# IPG-V1_rev0_24.net
KiCad netlist of a schematic drawn in Altium Designer
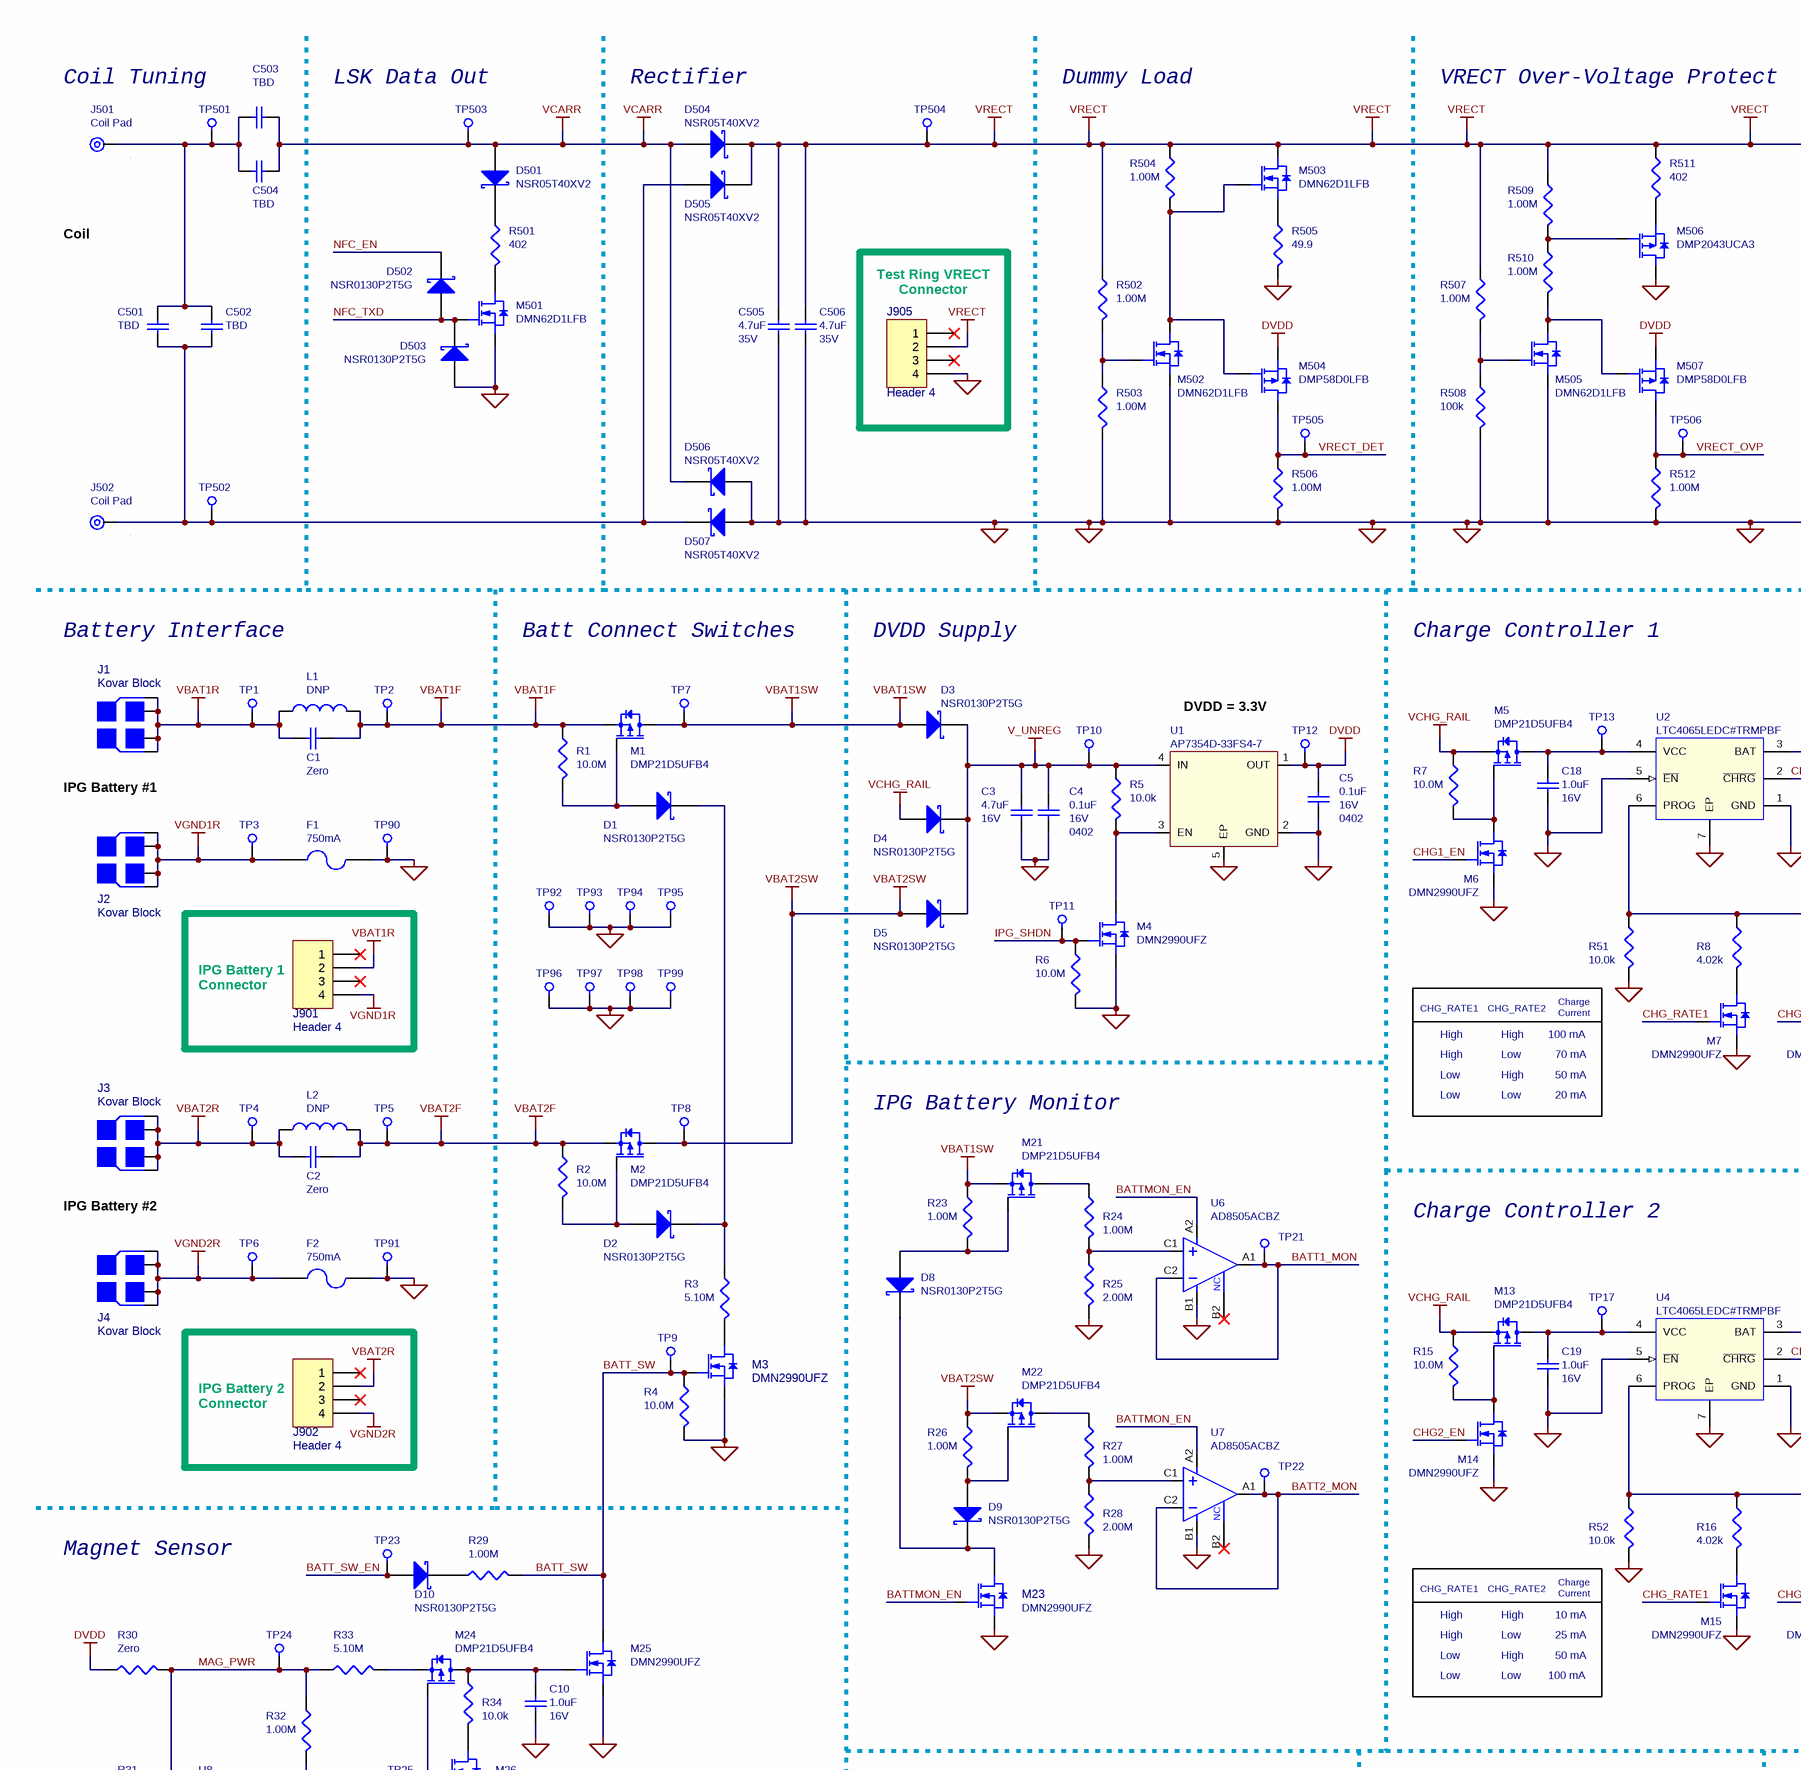
[diagram p0: IPG-V1_rev0.24.SchDoc, top left]
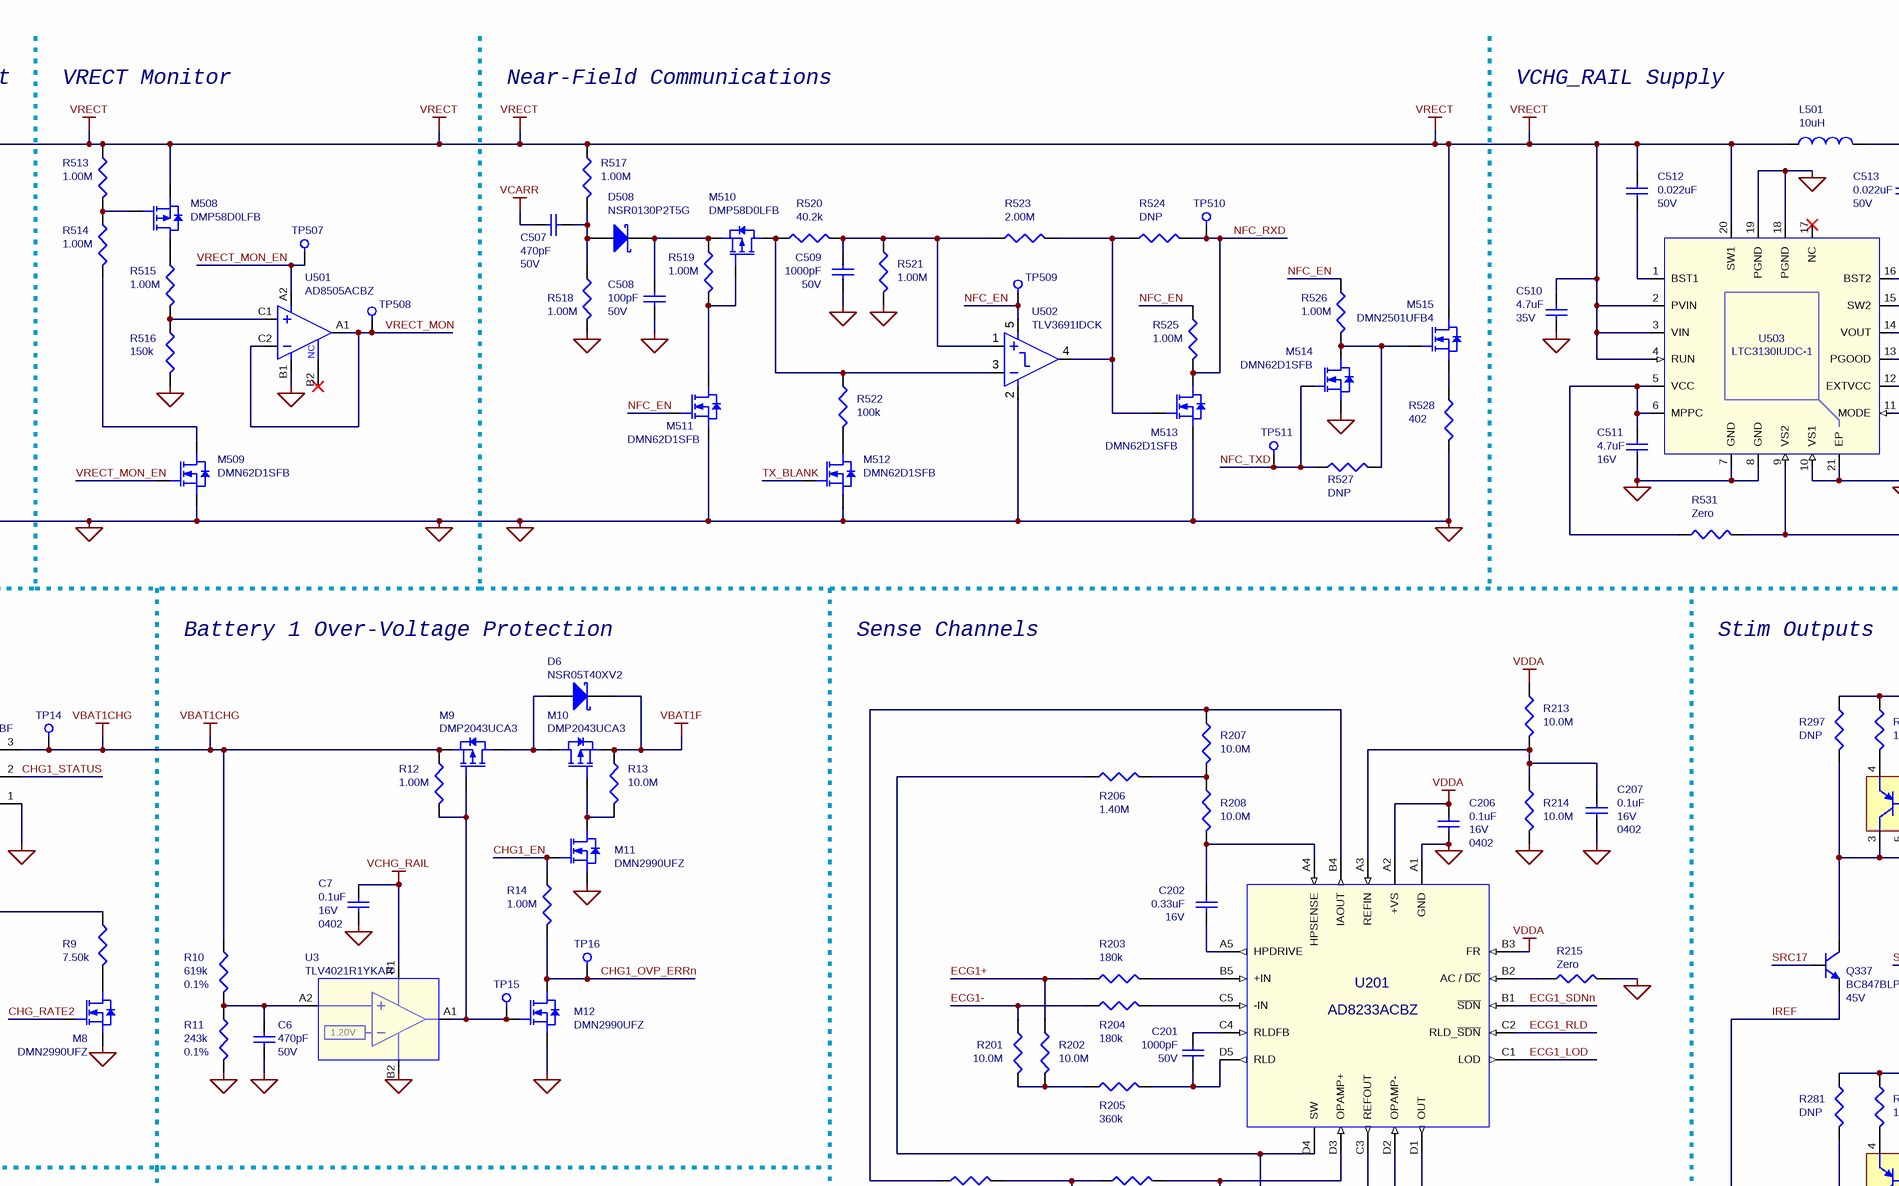
[diagram p1: IPG-V1_rev0.24.SchDoc, top middle]
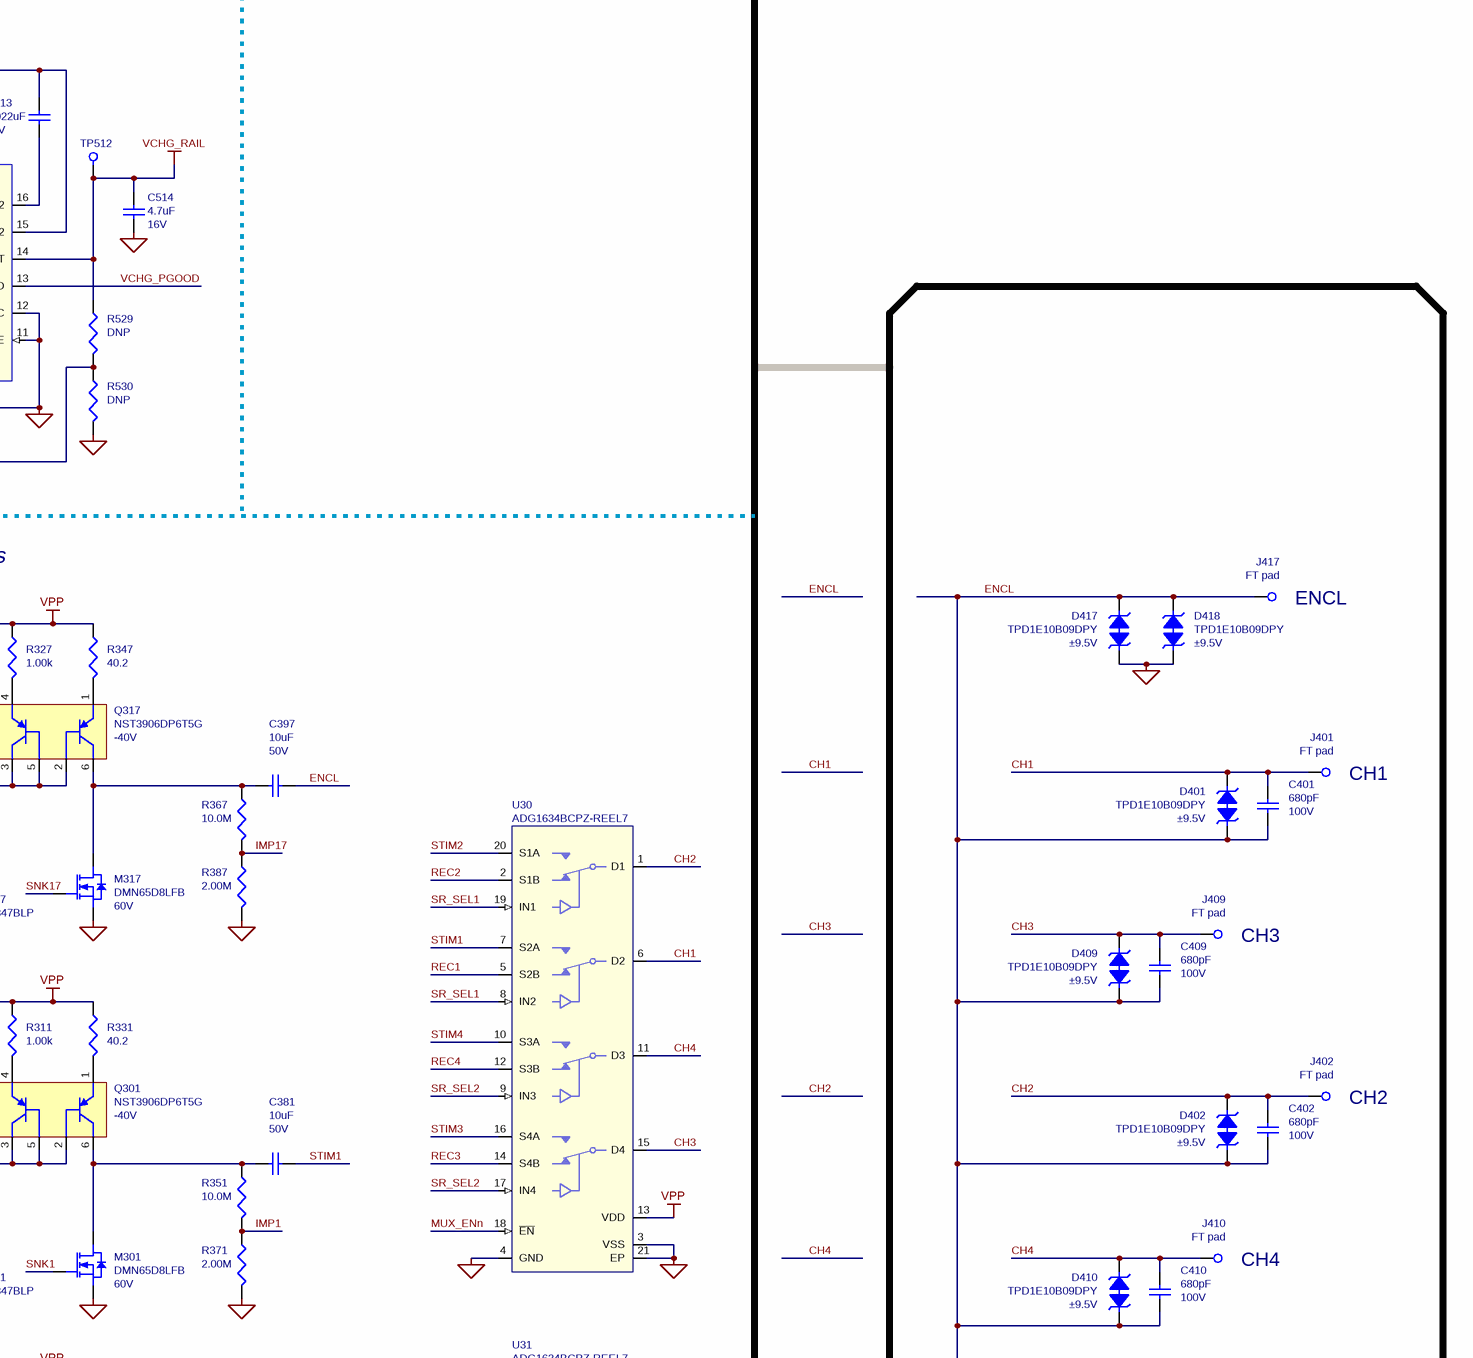
[diagram p2: IPG-V1_rev0.24.SchDoc, top right]
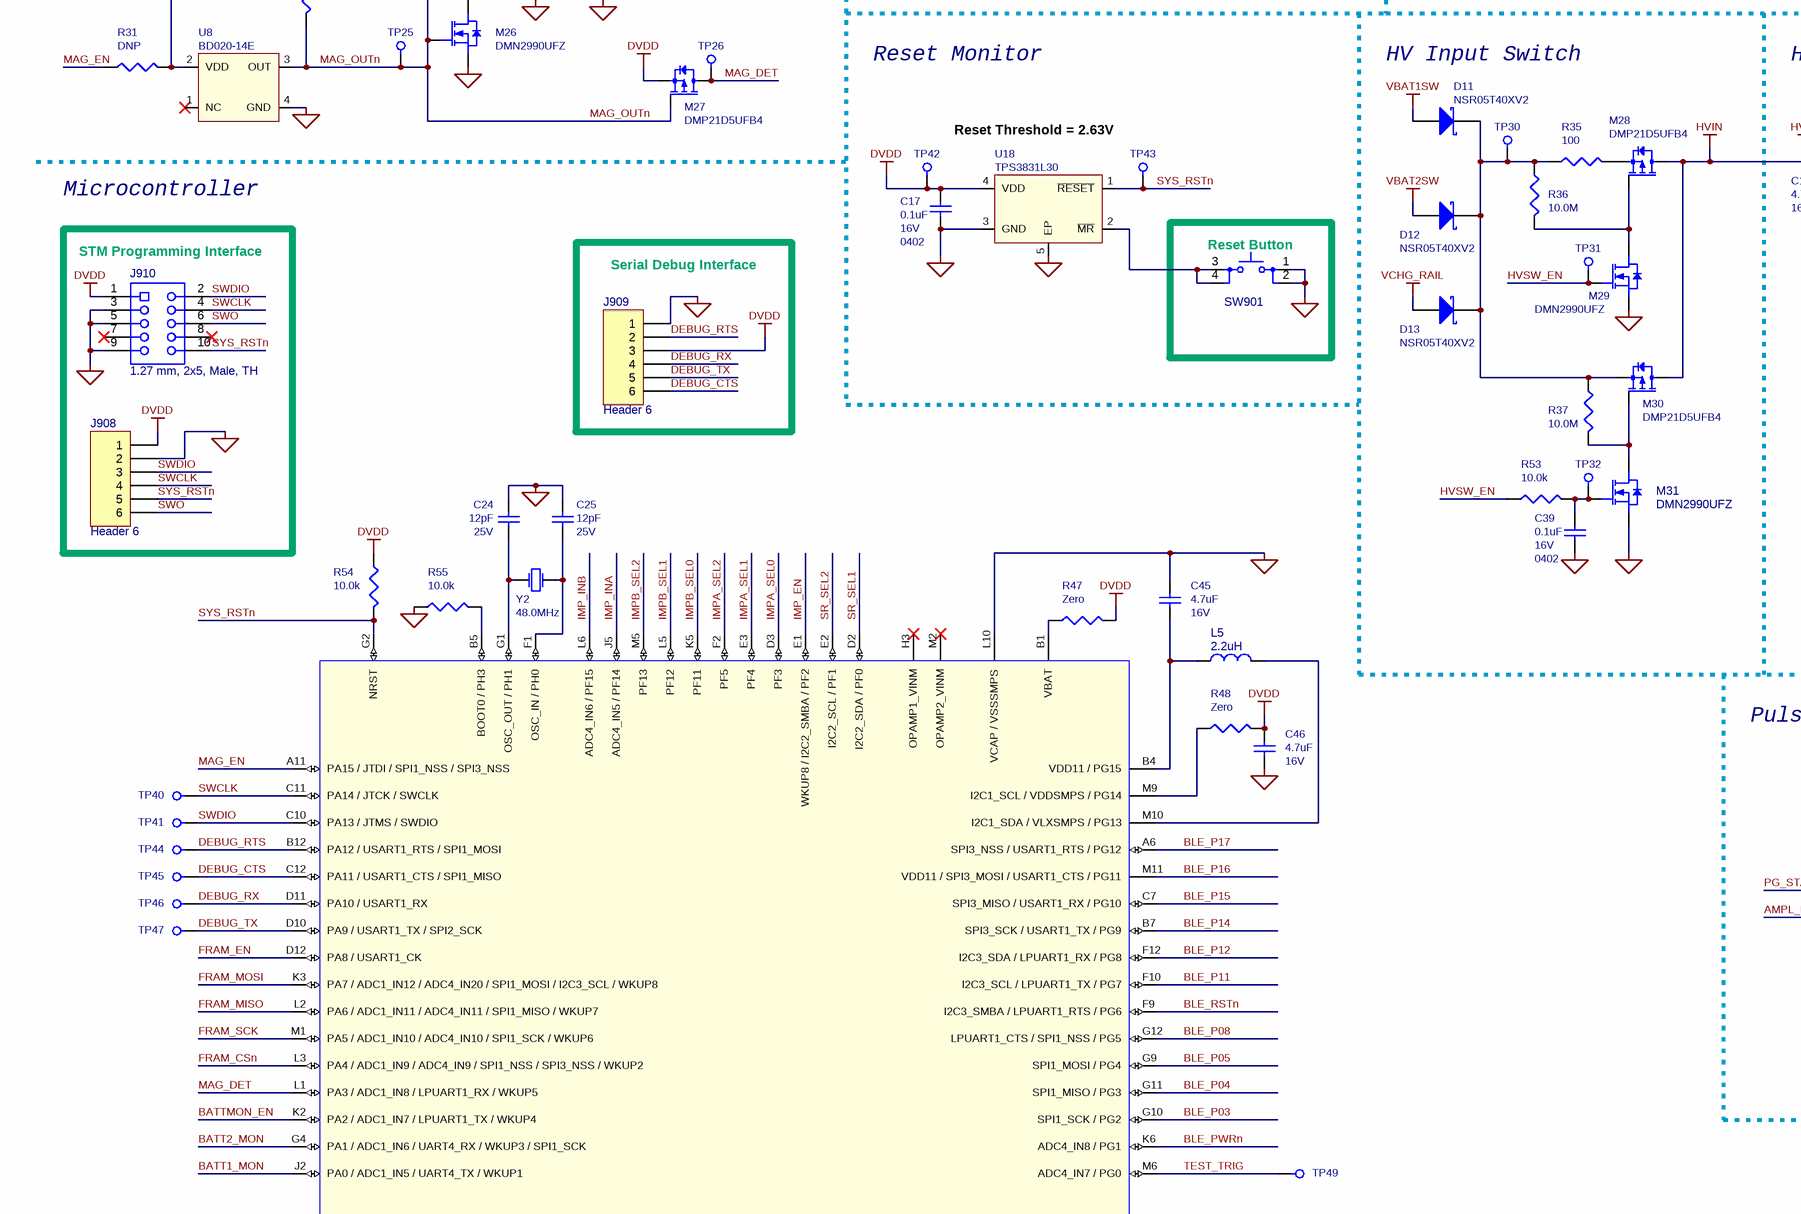
[diagram p3: IPG-V1_rev0.24.SchDoc, centre left]
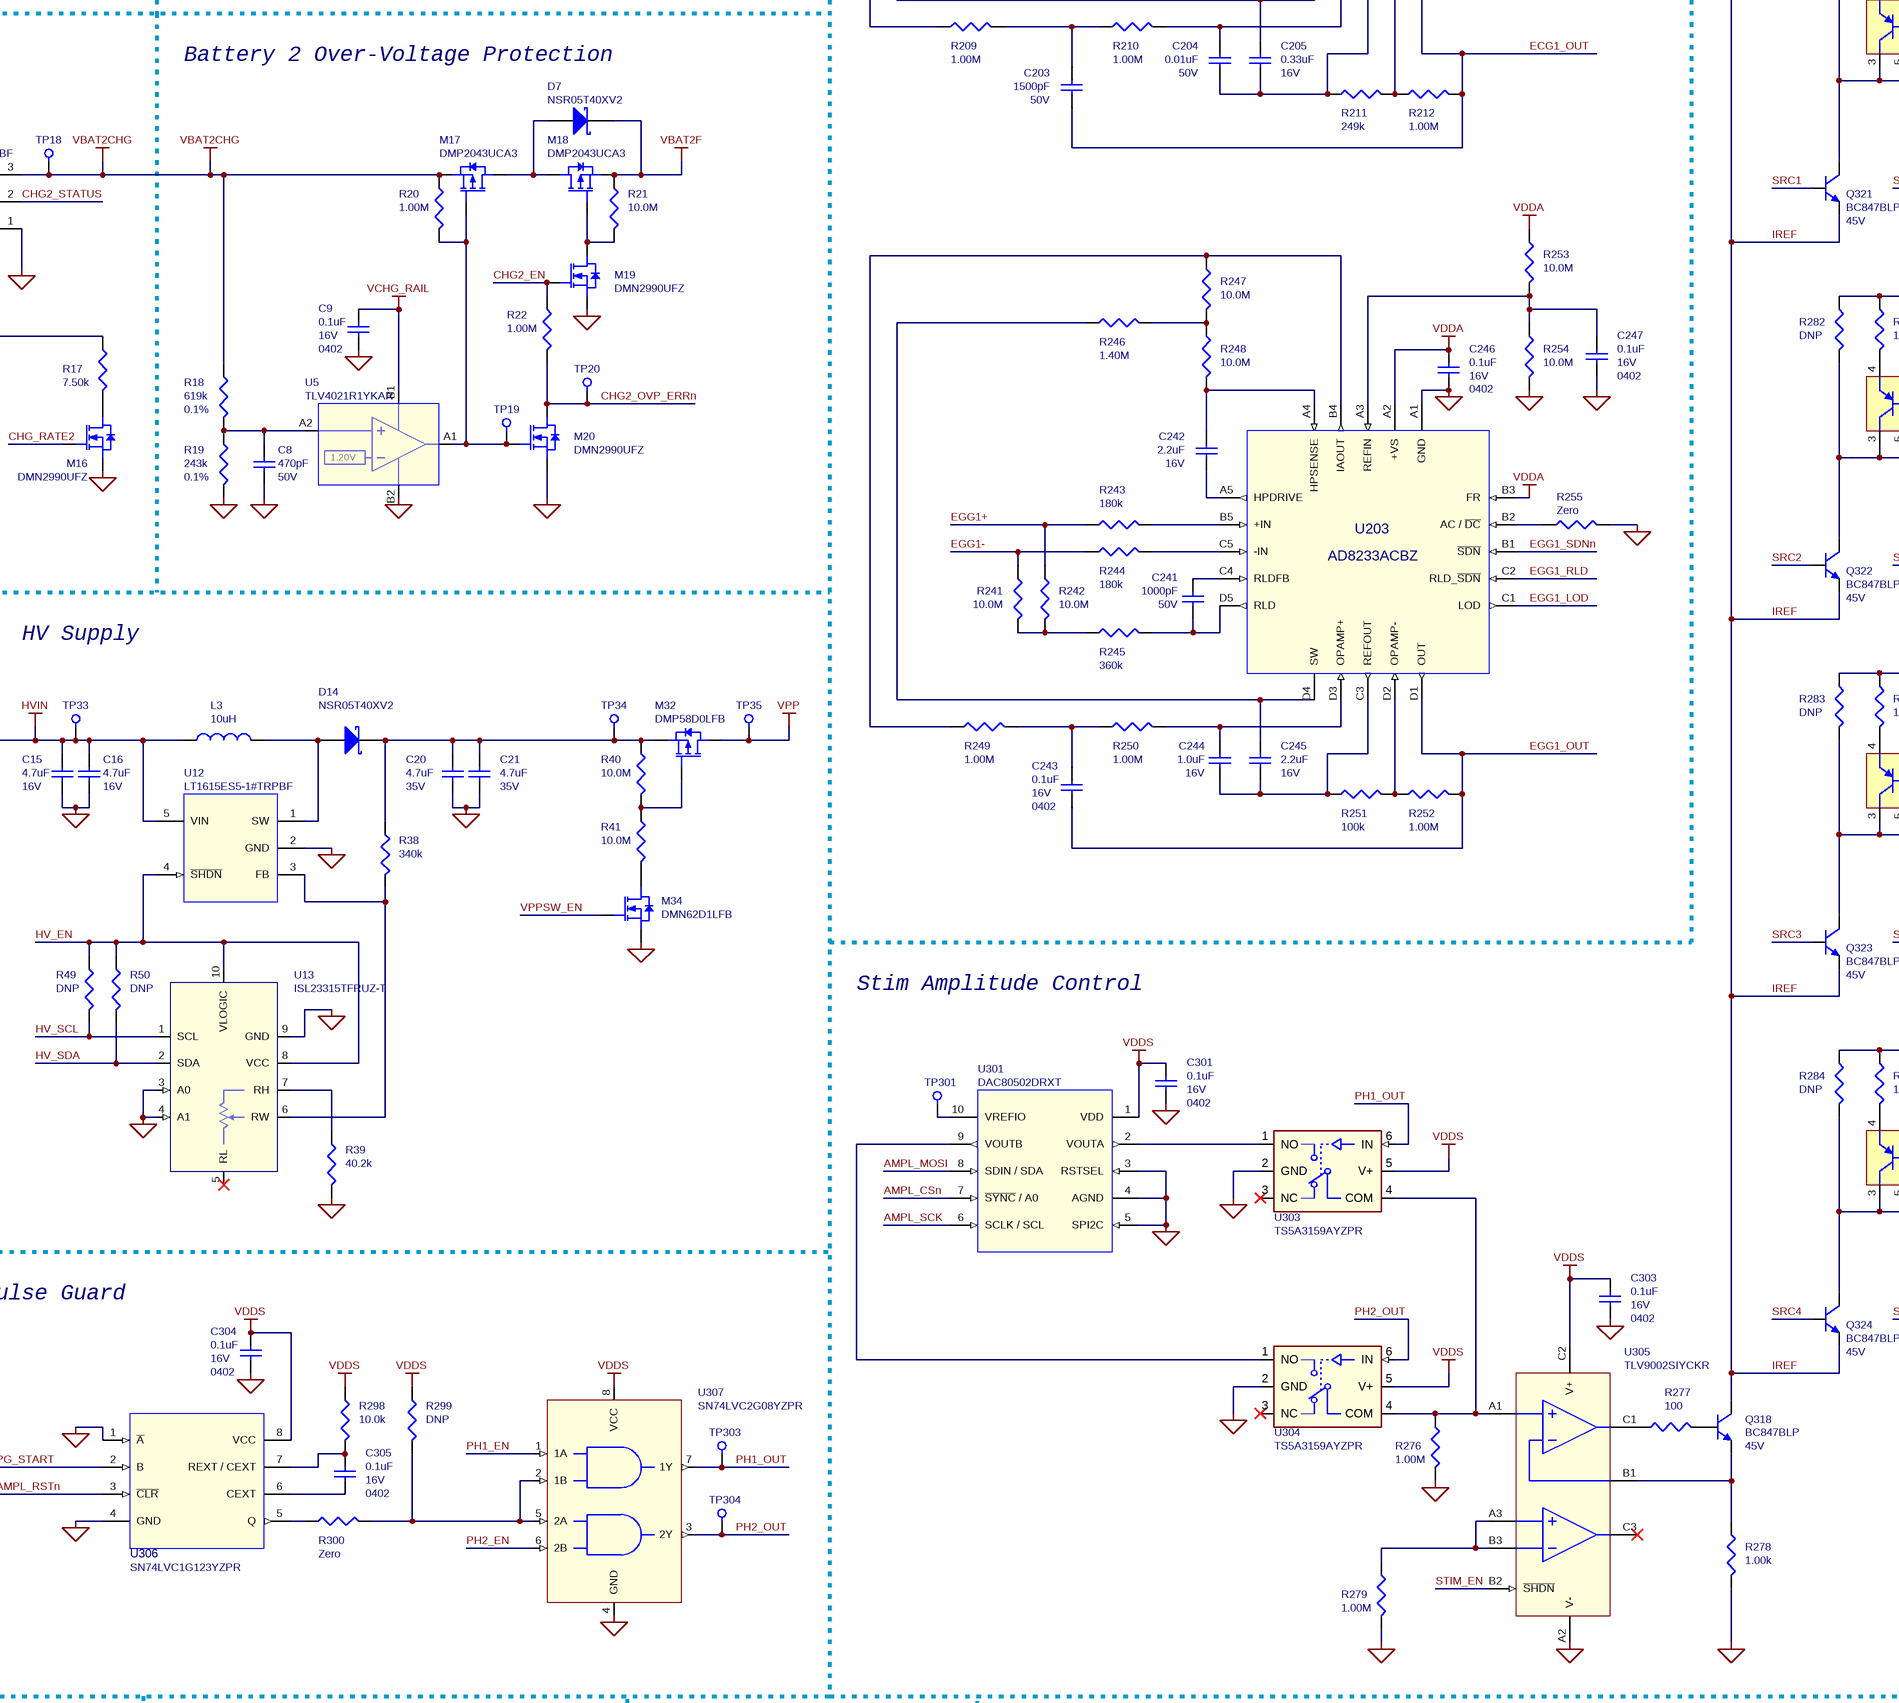
[diagram p4: IPG-V1_rev0.24.SchDoc, centre middle]
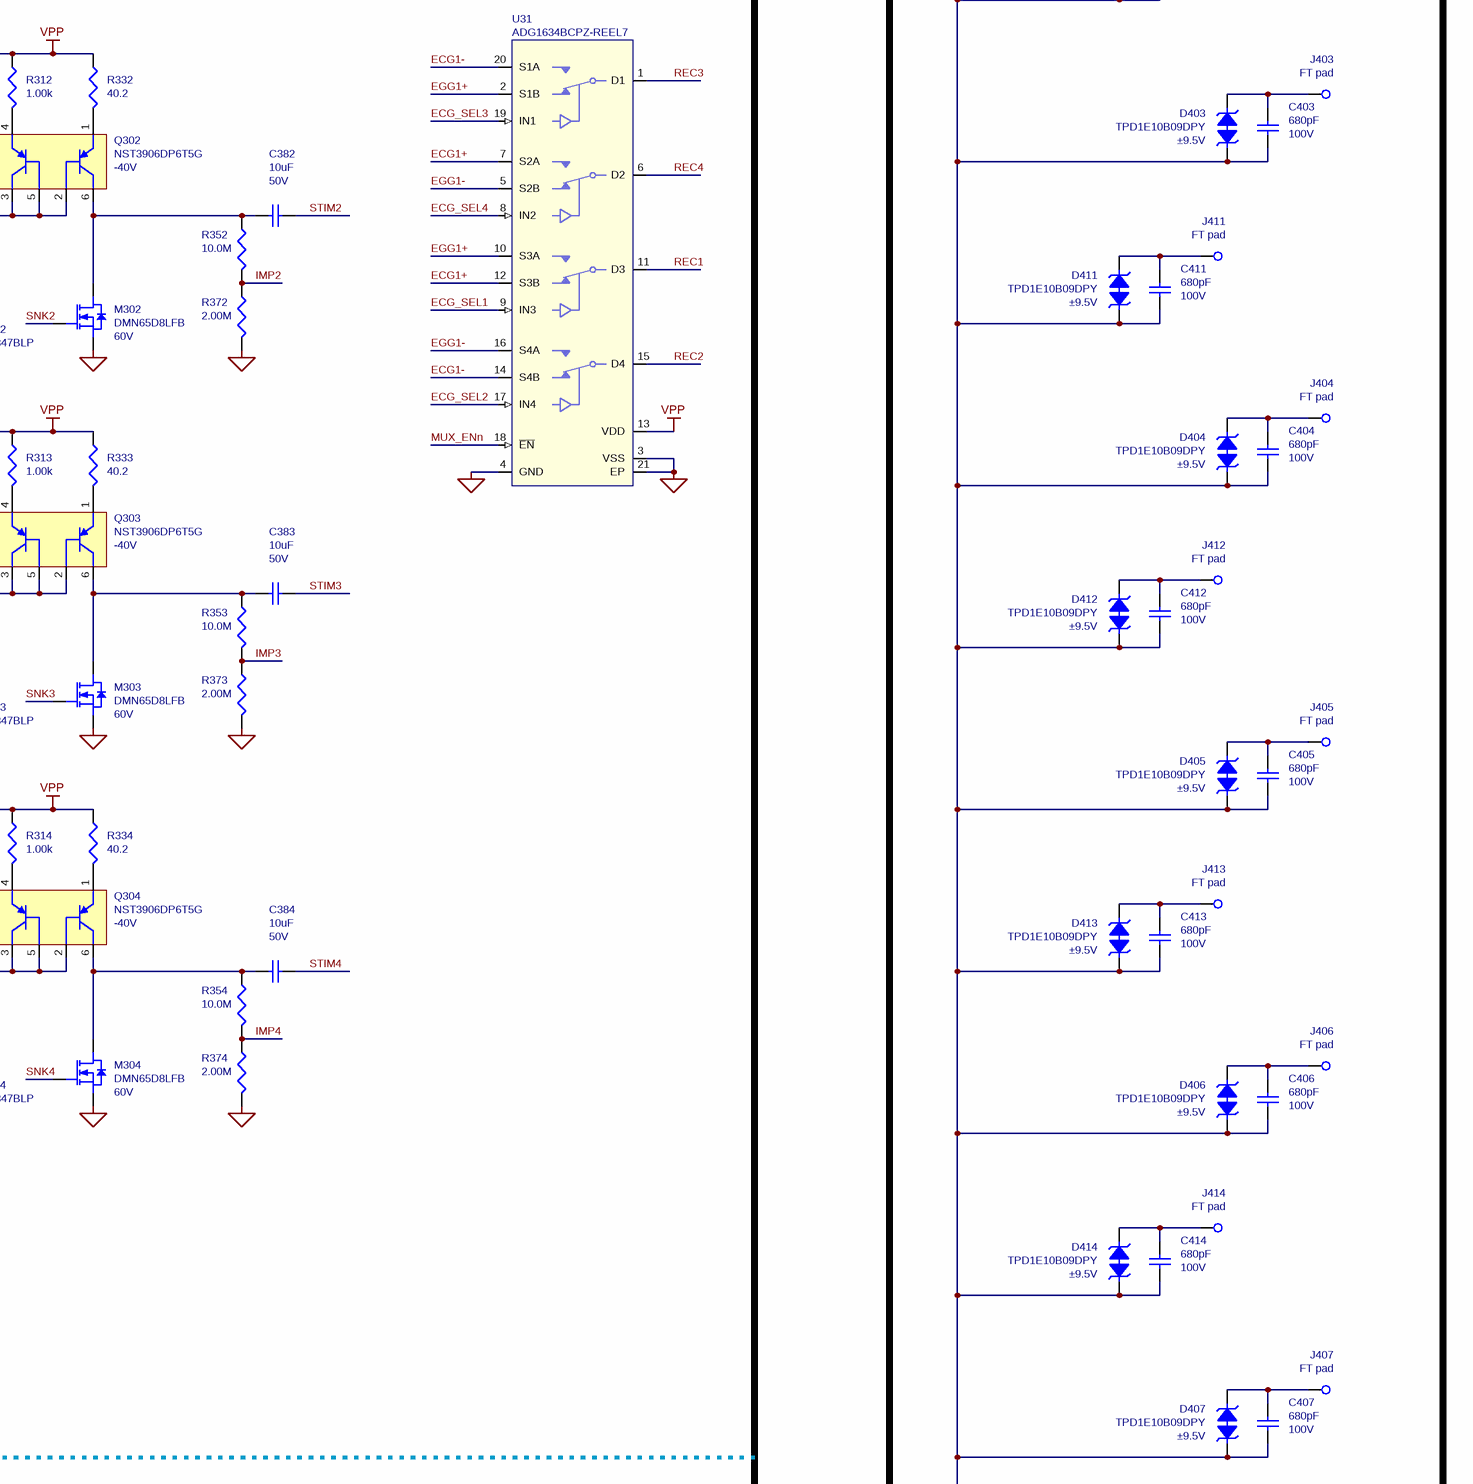
[diagram p5: IPG-V1_rev0.24.SchDoc, centre right]
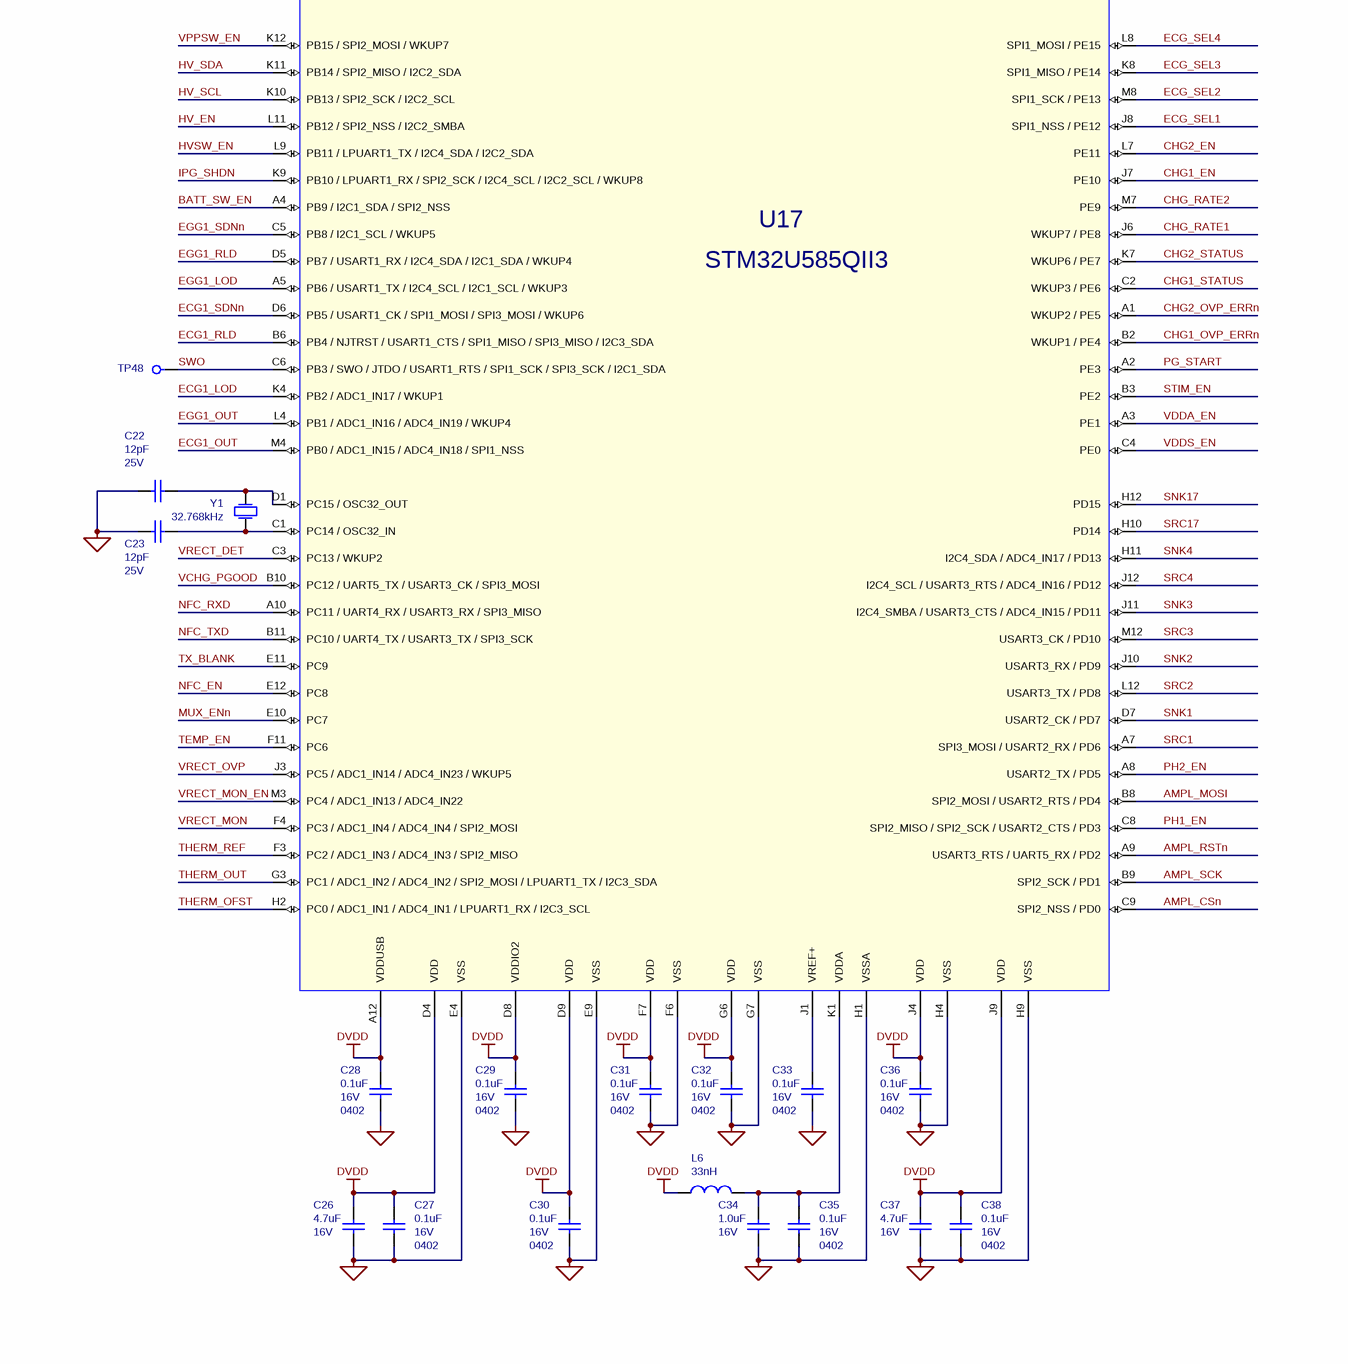
[diagram p6: IPG-V1_rev0.24.SchDoc, bottom left]
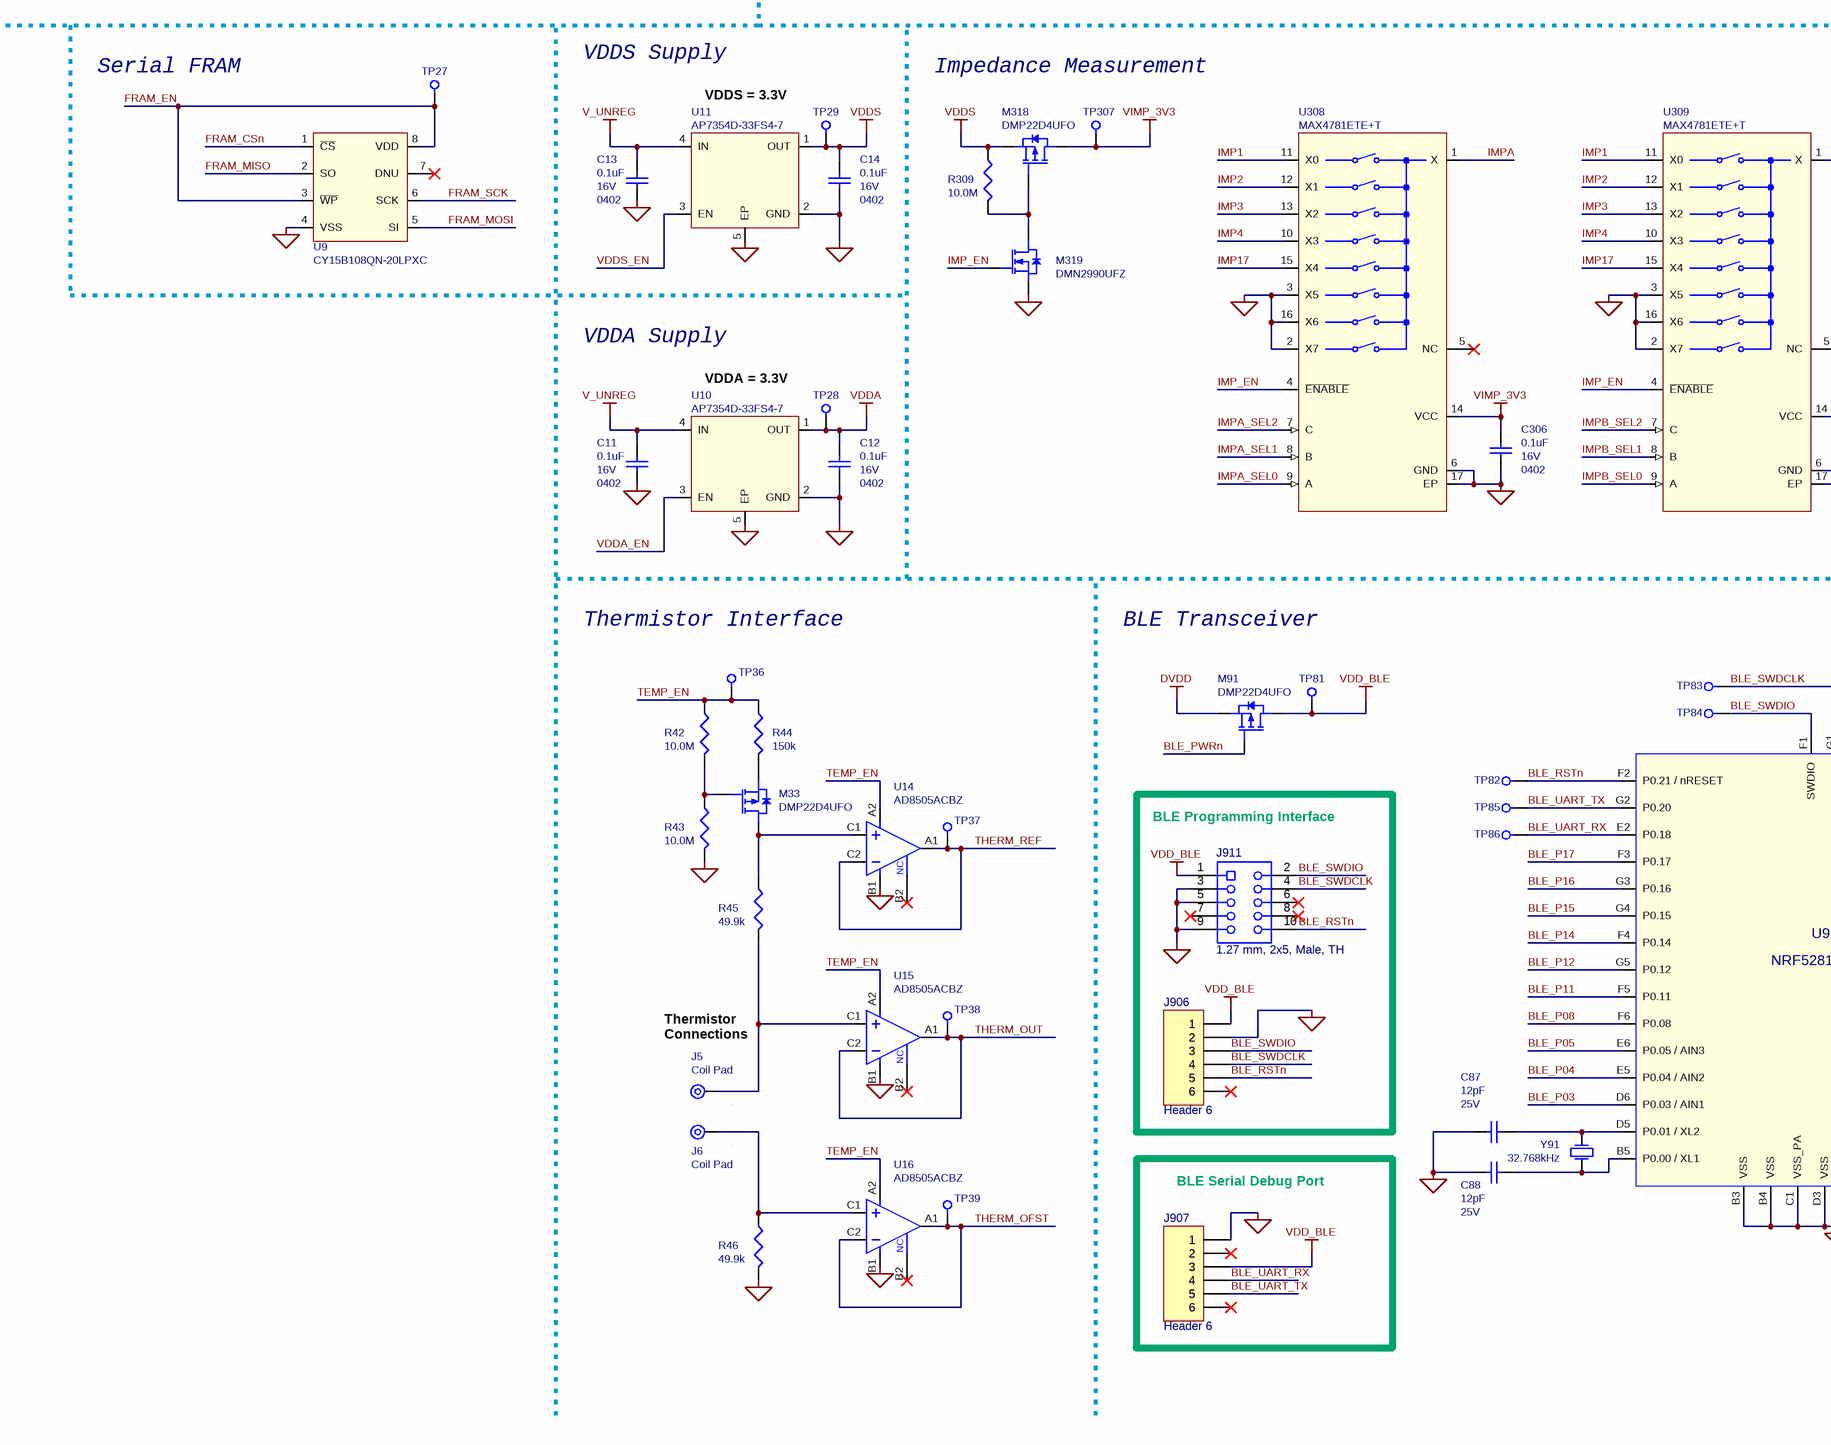
[diagram p7: IPG-V1_rev0.24.SchDoc, bottom middle]
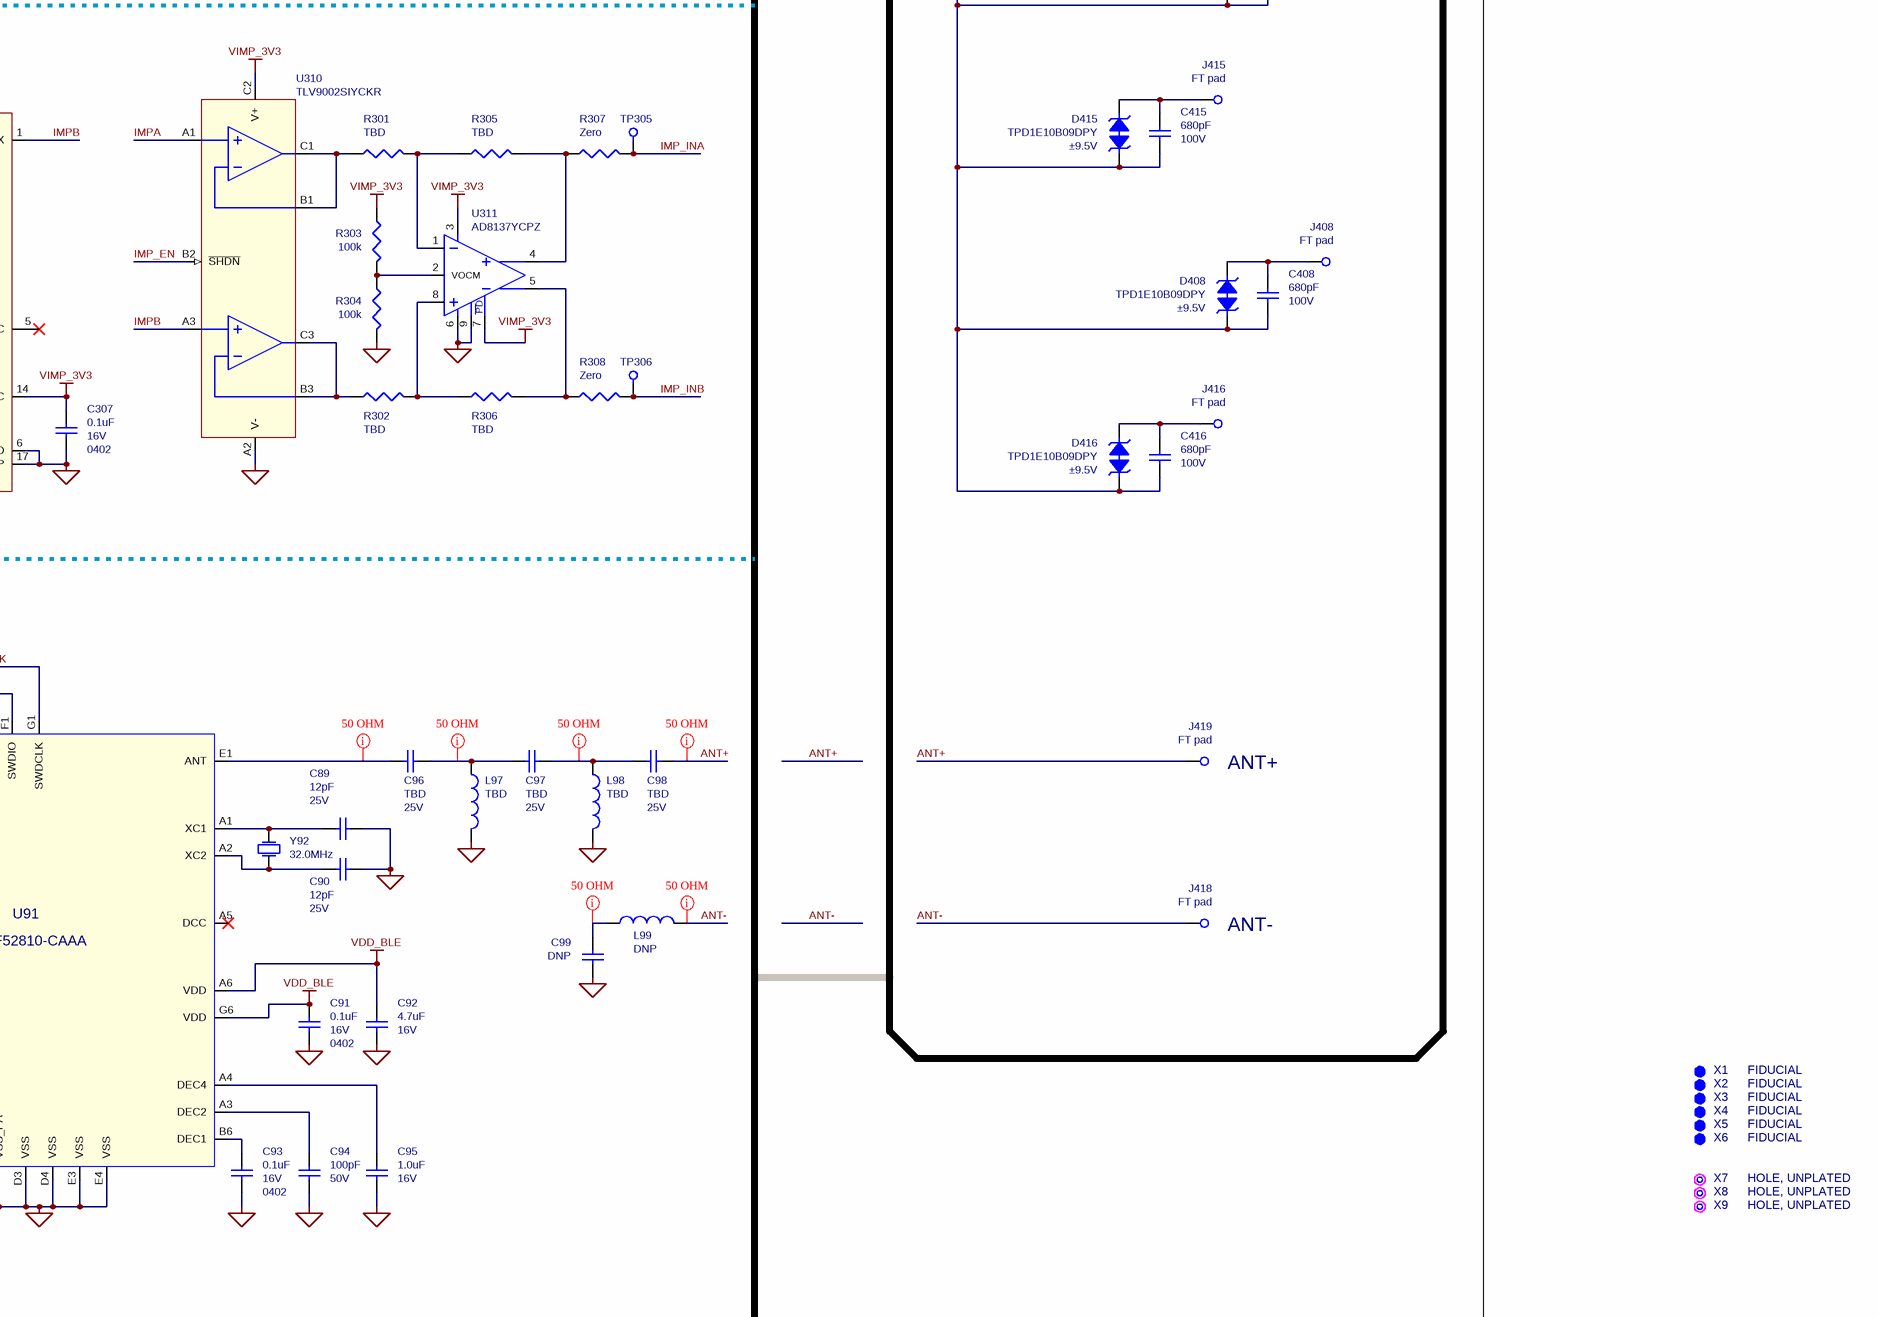
[diagram p8: IPG-V1_rev0.24.SchDoc, bottom right]

(export (version "E")
  (design (tool "Eeschema 10.0.6"))
  (components
    (comp (ref "C1")
      (value "Zero")
      (footprint "Capacitor:CAP0402_REDUCED")
      (description "Resistor, Zero ohms, 40V, 40mW, 1%, 0402, Implant-grade")
      (fields (field (name "MANUFACTURER") "Panasonic") (field (name "Comment") "Capacitor, Zero ohms, 0402"))
      (libsource (lib "Miscellaneous Devices") (part "Cap"))
    )
    (comp (ref "C2")
      (value "Zero")
      (footprint "Capacitor:CAP0402_REDUCED")
      (description "Resistor, Zero ohms, 40V, 40mW, 1%, 0402, Implant-grade")
      (fields (field (name "MANUFACTURER") "Panasonic") (field (name "Comment") "Capacitor, Zero ohms, 0402"))
      (libsource (lib "Miscellaneous Devices") (part "Cap"))
    )
    (comp (ref "C3")
      (value "4.7uF")
      (footprint "Capacitor:CAP0603_REDUCED")
      (description "Capacitor, 4.7uF, X5R, 16V, 10%, 0603, Implant-grade")
      (fields
        (field (name "MANUFACTURER") "Murata")
        (field (name "RATING") "16V")
        (field (name "Comment") "GCH188R61C475KE11")
      )
      (libsource (lib "Miscellaneous Devices") (part "Cap"))
    )
    (comp (ref "C4")
      (value "0.1uF")
      (footprint "Capacitor:CAP0402_REDUCED")
      (description "Capacitor, 0.1uF, X7R, 16V, 10%, 0402, Implant-grade")
      (fields
        (field (name "MANUFACTURER") "Murata")
        (field (name "RATING") "16V")
        (field (name "PACKAGE DESCRIPTION") "0402")
        (field (name "Comment") "GCH155R71C104KE01")
      )
      (libsource (lib "Miscellaneous Devices") (part "Cap"))
    )
    (comp (ref "C5")
      (value "0.1uF")
      (footprint "Capacitor:CAP0402_REDUCED")
      (description "Capacitor, 0.1uF, X7R, 16V, 10%, 0402, Implant-grade")
      (fields
        (field (name "MANUFACTURER") "Murata")
        (field (name "RATING") "16V")
        (field (name "PACKAGE DESCRIPTION") "0402")
        (field (name "Comment") "GCH155R71C104KE01")
      )
      (libsource (lib "Miscellaneous Devices") (part "Cap"))
    )
    (comp (ref "C6")
      (value "470pF")
      (footprint "Capacitor:CAP0402_REDUCED")
      (description "Capacitor, 470pF, X7R, 50V, 10%, 0402, Implant-grade")
      (fields
        (field (name "MANUFACTURER") "Murata")
        (field (name "RATING") "50V")
        (field (name "Comment") "GCH155R71H471KE01")
      )
      (libsource (lib "Miscellaneous Devices") (part "Cap"))
    )
    (comp (ref "C7")
      (value "0.1uF")
      (footprint "Capacitor:CAP0402_REDUCED")
      (description "Capacitor, 0.1uF, X7R, 16V, 10%, 0402, Implant-grade")
      (fields
        (field (name "MANUFACTURER") "Murata")
        (field (name "RATING") "16V")
        (field (name "PACKAGE DESCRIPTION") "0402")
        (field (name "Comment") "GCH155R71C104KE01")
      )
      (libsource (lib "Miscellaneous Devices") (part "Cap"))
    )
    (comp (ref "C8")
      (value "470pF")
      (footprint "Capacitor:CAP0402_REDUCED")
      (description "Capacitor, 470pF, X7R, 50V, 10%, 0402, Implant-grade")
      (fields
        (field (name "MANUFACTURER") "Murata")
        (field (name "RATING") "50V")
        (field (name "Comment") "GCH155R71H471KE01")
      )
      (libsource (lib "Miscellaneous Devices") (part "Cap"))
    )
    (comp (ref "C9")
      (value "0.1uF")
      (footprint "Capacitor:CAP0402_REDUCED")
      (description "Capacitor, 0.1uF, X7R, 16V, 10%, 0402, Implant-grade")
      (fields
        (field (name "MANUFACTURER") "Murata")
        (field (name "RATING") "16V")
        (field (name "PACKAGE DESCRIPTION") "0402")
        (field (name "Comment") "GCH155R71C104KE01")
      )
      (libsource (lib "Miscellaneous Devices") (part "Cap"))
    )
    (comp (ref "C10")
      (value "1.0uF")
      (footprint "Capacitor:CAP0603_REDUCED")
      (description "Capacitor, 1.0uF, X5R, 16V, 10%, 0603, Implant-grade")
      (fields
        (field (name "MANUFACTURER") "Murata")
        (field (name "RATING") "16V")
        (field (name "Comment") "GCH188R71C105KE01")
      )
      (libsource (lib "Miscellaneous Devices") (part "Cap"))
    )
    (comp (ref "C11")
      (value "0.1uF")
      (footprint "Capacitor:CAP0402_REDUCED")
      (description "Capacitor, 0.1uF, X7R, 16V, 10%, 0402, Implant-grade")
      (fields
        (field (name "MANUFACTURER") "Murata")
        (field (name "RATING") "16V")
        (field (name "PACKAGE DESCRIPTION") "0402")
        (field (name "Comment") "GCH155R71C104KE01")
      )
      (libsource (lib "Miscellaneous Devices") (part "Cap"))
    )
    (comp (ref "C12")
      (value "0.1uF")
      (footprint "Capacitor:CAP0402_REDUCED")
      (description "Capacitor, 0.1uF, X7R, 16V, 10%, 0402, Implant-grade")
      (fields
        (field (name "MANUFACTURER") "Murata")
        (field (name "RATING") "16V")
        (field (name "PACKAGE DESCRIPTION") "0402")
        (field (name "Comment") "GCH155R71C104KE01")
      )
      (libsource (lib "Miscellaneous Devices") (part "Cap"))
    )
    (comp (ref "C13")
      (value "0.1uF")
      (footprint "Capacitor:CAP0402_REDUCED")
      (description "Capacitor, 0.1uF, X7R, 16V, 10%, 0402, Implant-grade")
      (fields
        (field (name "MANUFACTURER") "Murata")
        (field (name "RATING") "16V")
        (field (name "PACKAGE DESCRIPTION") "0402")
        (field (name "Comment") "GCH155R71C104KE01")
      )
      (libsource (lib "Miscellaneous Devices") (part "Cap"))
    )
    (comp (ref "C14")
      (value "0.1uF")
      (footprint "Capacitor:CAP0402_REDUCED")
      (description "Capacitor, 0.1uF, X7R, 16V, 10%, 0402, Implant-grade")
      (fields
        (field (name "MANUFACTURER") "Murata")
        (field (name "RATING") "16V")
        (field (name "PACKAGE DESCRIPTION") "0402")
        (field (name "Comment") "GCH155R71C104KE01")
      )
      (libsource (lib "Miscellaneous Devices") (part "Cap"))
    )
    (comp (ref "C15")
      (value "4.7uF")
      (footprint "Capacitor:CAP0603_REDUCED")
      (description "Capacitor, 4.7uF, X5R, 16V, 10%, 0603, Implant-grade")
      (fields
        (field (name "MANUFACTURER") "Murata")
        (field (name "RATING") "16V")
        (field (name "Comment") "GCH188R61C475KE11")
      )
      (libsource (lib "Miscellaneous Devices") (part "Cap"))
    )
    (comp (ref "C16")
      (value "4.7uF")
      (footprint "Capacitor:CAP0603_REDUCED")
      (description "Capacitor, 4.7uF, X5R, 16V, 10%, 0603, Implant-grade")
      (fields
        (field (name "MANUFACTURER") "Murata")
        (field (name "RATING") "16V")
        (field (name "Comment") "GCH188R61C475KE11")
      )
      (libsource (lib "Miscellaneous Devices") (part "Cap"))
    )
    (comp (ref "C17")
      (value "0.1uF")
      (footprint "Capacitor:CAP0402_REDUCED")
      (description "Capacitor, 0.1uF, X7R, 16V, 10%, 0402, Implant-grade")
      (fields
        (field (name "MANUFACTURER") "Murata")
        (field (name "RATING") "16V")
        (field (name "PACKAGE DESCRIPTION") "0402")
        (field (name "Comment") "GCH155R71C104KE01")
      )
      (libsource (lib "Miscellaneous Devices") (part "Cap"))
    )
    (comp (ref "C18")
      (value "1.0uF")
      (footprint "Capacitor:CAP0603_REDUCED")
      (description "Capacitor, 1.0uF, X5R, 16V, 10%, 0603, Implant-grade")
      (fields
        (field (name "MANUFACTURER") "Murata")
        (field (name "RATING") "16V")
        (field (name "Comment") "GCH188R71C105KE01")
      )
      (libsource (lib "Miscellaneous Devices") (part "Cap"))
    )
    (comp (ref "C19")
      (value "1.0uF")
      (footprint "Capacitor:CAP0603_REDUCED")
      (description "Capacitor, 1.0uF, X5R, 16V, 10%, 0603, Implant-grade")
      (fields
        (field (name "MANUFACTURER") "Murata")
        (field (name "RATING") "16V")
        (field (name "Comment") "GCH188R71C105KE01")
      )
      (libsource (lib "Miscellaneous Devices") (part "Cap"))
    )
    (comp (ref "C20")
      (value "4.7uF")
      (footprint "Capacitor:CAP0805_REDUCED")
      (description "Capacitor, 4.7uF, X7S, 35V, 10%, 0805, Implant-grade")
      (fields
        (field (name "MANUFACTURER") "Murata")
        (field (name "RATING") "35V")
        (field (name "Comment") "GCH21BC7YA475KE11")
      )
      (libsource (lib "Miscellaneous Devices") (part "Cap"))
    )
    (comp (ref "C21")
      (value "4.7uF")
      (footprint "Capacitor:CAP0805_REDUCED")
      (description "Capacitor, 4.7uF, X7S, 35V, 10%, 0805, Implant-grade")
      (fields
        (field (name "MANUFACTURER") "Murata")
        (field (name "RATING") "35V")
        (field (name "Comment") "GCH21BC7YA475KE11")
      )
      (libsource (lib "Miscellaneous Devices") (part "Cap"))
    )
    (comp (ref "C22")
      (value "12pF")
      (footprint "Capacitor:CAP0402_REDUCED")
      (description "Capacitor, 12pF, C0G, 25V, ±0.05pF, 0402, Implant-grade")
      (fields
        (field (name "MANUFACTURER") "AVX")
        (field (name "RATING") "25V")
        (field (name "Comment") "C0402C120J3GACAUTO")
      )
      (libsource (lib "Miscellaneous Devices") (part "Cap"))
    )
    (comp (ref "C23")
      (value "12pF")
      (footprint "Capacitor:CAP0402_REDUCED")
      (description "Capacitor, 12pF, C0G, 25V, ±0.05pF, 0402, Implant-grade")
      (fields
        (field (name "MANUFACTURER") "AVX")
        (field (name "RATING") "25V")
        (field (name "Comment") "C0402C120J3GACAUTO")
      )
      (libsource (lib "Miscellaneous Devices") (part "Cap"))
    )
    (comp (ref "C24")
      (value "12pF")
      (footprint "Capacitor:CAP0402_REDUCED")
      (description "Capacitor, 12pF, C0G, 25V, ±0.05pF, 0402, Implant-grade")
      (fields
        (field (name "MANUFACTURER") "AVX")
        (field (name "RATING") "25V")
        (field (name "Comment") "C0402C120J3GACAUTO")
      )
      (libsource (lib "Miscellaneous Devices") (part "Cap"))
    )
    (comp (ref "C25")
      (value "12pF")
      (footprint "Capacitor:CAP0402_REDUCED")
      (description "Capacitor, 12pF, C0G, 25V, ±0.05pF, 0402, Implant-grade")
      (fields
        (field (name "MANUFACTURER") "AVX")
        (field (name "RATING") "25V")
        (field (name "Comment") "C0402C120J3GACAUTO")
      )
      (libsource (lib "Miscellaneous Devices") (part "Cap"))
    )
    (comp (ref "C26")
      (value "4.7uF")
      (footprint "Capacitor:CAP0603_REDUCED")
      (description "Capacitor, 4.7uF, X5R, 16V, 10%, 0603, Implant-grade")
      (fields
        (field (name "MANUFACTURER") "Murata")
        (field (name "RATING") "16V")
        (field (name "Comment") "GCH188R61C475KE11")
      )
      (libsource (lib "Miscellaneous Devices") (part "Cap"))
    )
    (comp (ref "C27")
      (value "0.1uF")
      (footprint "Capacitor:CAP0402_REDUCED")
      (description "Capacitor, 0.1uF, X7R, 16V, 10%, 0402, Implant-grade")
      (fields
        (field (name "MANUFACTURER") "Murata")
        (field (name "RATING") "16V")
        (field (name "PACKAGE DESCRIPTION") "0402")
        (field (name "Comment") "GCH155R71C104KE01")
      )
      (libsource (lib "Miscellaneous Devices") (part "Cap"))
    )
    (comp (ref "C28")
      (value "0.1uF")
      (footprint "Capacitor:CAP0402_REDUCED")
      (description "Capacitor, 0.1uF, X7R, 16V, 10%, 0402, Implant-grade")
      (fields
        (field (name "MANUFACTURER") "Murata")
        (field (name "RATING") "16V")
        (field (name "PACKAGE DESCRIPTION") "0402")
        (field (name "Comment") "GCH155R71C104KE01")
      )
      (libsource (lib "Miscellaneous Devices") (part "Cap"))
    )
    (comp (ref "C29")
      (value "0.1uF")
      (footprint "Capacitor:CAP0402_REDUCED")
      (description "Capacitor, 0.1uF, X7R, 16V, 10%, 0402, Implant-grade")
      (fields
        (field (name "MANUFACTURER") "Murata")
        (field (name "RATING") "16V")
        (field (name "PACKAGE DESCRIPTION") "0402")
        (field (name "Comment") "GCH155R71C104KE01")
      )
      (libsource (lib "Miscellaneous Devices") (part "Cap"))
    )
    (comp (ref "C30")
      (value "0.1uF")
      (footprint "Capacitor:CAP0402_REDUCED")
      (description "Capacitor, 0.1uF, X7R, 16V, 10%, 0402, Implant-grade")
      (fields
        (field (name "MANUFACTURER") "Murata")
        (field (name "RATING") "16V")
        (field (name "PACKAGE DESCRIPTION") "0402")
        (field (name "Comment") "GCH155R71C104KE01")
      )
      (libsource (lib "Miscellaneous Devices") (part "Cap"))
    )
    (comp (ref "C31")
      (value "0.1uF")
      (footprint "Capacitor:CAP0402_REDUCED")
      (description "Capacitor, 0.1uF, X7R, 16V, 10%, 0402, Implant-grade")
      (fields
        (field (name "MANUFACTURER") "Murata")
        (field (name "RATING") "16V")
        (field (name "PACKAGE DESCRIPTION") "0402")
        (field (name "Comment") "GCH155R71C104KE01")
      )
      (libsource (lib "Miscellaneous Devices") (part "Cap"))
    )
    (comp (ref "C32")
      (value "0.1uF")
      (footprint "Capacitor:CAP0402_REDUCED")
      (description "Capacitor, 0.1uF, X7R, 16V, 10%, 0402, Implant-grade")
      (fields
        (field (name "MANUFACTURER") "Murata")
        (field (name "RATING") "16V")
        (field (name "PACKAGE DESCRIPTION") "0402")
        (field (name "Comment") "GCH155R71C104KE01")
      )
      (libsource (lib "Miscellaneous Devices") (part "Cap"))
    )
    (comp (ref "C33")
      (value "0.1uF")
      (footprint "Capacitor:CAP0402_REDUCED")
      (description "Capacitor, 0.1uF, X7R, 16V, 10%, 0402, Implant-grade")
      (fields
        (field (name "MANUFACTURER") "Murata")
        (field (name "RATING") "16V")
        (field (name "PACKAGE DESCRIPTION") "0402")
        (field (name "Comment") "GCH155R71C104KE01")
      )
      (libsource (lib "Miscellaneous Devices") (part "Cap"))
    )
    (comp (ref "C34")
      (value "1.0uF")
      (footprint "Capacitor:CAP0603_REDUCED")
      (description "Capacitor, 1.0uF, X5R, 16V, 10%, 0603, Implant-grade")
      (fields
        (field (name "MANUFACTURER") "Murata")
        (field (name "RATING") "16V")
        (field (name "Comment") "GCH188R71C105KE01")
      )
      (libsource (lib "Miscellaneous Devices") (part "Cap"))
    )
    (comp (ref "C35")
      (value "0.1uF")
      (footprint "Capacitor:CAP0402_REDUCED")
      (description "Capacitor, 0.1uF, X7R, 16V, 10%, 0402, Implant-grade")
      (fields
        (field (name "MANUFACTURER") "Murata")
        (field (name "RATING") "16V")
        (field (name "PACKAGE DESCRIPTION") "0402")
        (field (name "Comment") "GCH155R71C104KE01")
      )
      (libsource (lib "Miscellaneous Devices") (part "Cap"))
    )
    (comp (ref "C36")
      (value "0.1uF")
      (footprint "Capacitor:CAP0402_REDUCED")
      (description "Capacitor, 0.1uF, X7R, 16V, 10%, 0402, Implant-grade")
      (fields
        (field (name "MANUFACTURER") "Murata")
        (field (name "RATING") "16V")
        (field (name "PACKAGE DESCRIPTION") "0402")
        (field (name "Comment") "GCH155R71C104KE01")
      )
      (libsource (lib "Miscellaneous Devices") (part "Cap"))
    )
    (comp (ref "C37")
      (value "4.7uF")
      (footprint "Capacitor:CAP0603_REDUCED")
      (description "Capacitor, 4.7uF, X5R, 16V, 10%, 0603, Implant-grade")
      (fields
        (field (name "MANUFACTURER") "Murata")
        (field (name "RATING") "16V")
        (field (name "Comment") "GCH188R61C475KE11")
      )
      (libsource (lib "Miscellaneous Devices") (part "Cap"))
    )
    (comp (ref "C38")
      (value "0.1uF")
      (footprint "Capacitor:CAP0402_REDUCED")
      (description "Capacitor, 0.1uF, X7R, 16V, 10%, 0402, Implant-grade")
      (fields
        (field (name "MANUFACTURER") "Murata")
        (field (name "RATING") "16V")
        (field (name "PACKAGE DESCRIPTION") "0402")
        (field (name "Comment") "GCH155R71C104KE01")
      )
      (libsource (lib "Miscellaneous Devices") (part "Cap"))
    )
    (comp (ref "C39")
      (value "0.1uF")
      (footprint "Capacitor:CAP0402_REDUCED")
      (description "Capacitor, 0.1uF, X7R, 16V, 10%, 0402, Implant-grade")
      (fields
        (field (name "MANUFACTURER") "Murata")
        (field (name "RATING") "16V")
        (field (name "PACKAGE DESCRIPTION") "0402")
        (field (name "Comment") "GCH155R71C104KE01")
      )
      (libsource (lib "Miscellaneous Devices") (part "Cap"))
    )
    (comp (ref "C45")
      (value "4.7uF")
      (footprint "Capacitor:CAP0603_REDUCED")
      (description "Capacitor, 4.7uF, X5R, 16V, 10%, 0603, Implant-grade")
      (fields
        (field (name "MANUFACTURER") "Murata")
        (field (name "RATING") "16V")
        (field (name "Comment") "GCH188R61C475KE11")
      )
      (libsource (lib "Miscellaneous Devices") (part "Cap"))
    )
    (comp (ref "C46")
      (value "4.7uF")
      (footprint "Capacitor:CAP0603_REDUCED")
      (description "Capacitor, 4.7uF, X5R, 16V, 10%, 0603, Implant-grade")
      (fields
        (field (name "MANUFACTURER") "Murata")
        (field (name "RATING") "16V")
        (field (name "Comment") "GCH188R61C475KE11")
      )
      (libsource (lib "Miscellaneous Devices") (part "Cap"))
    )
    (comp (ref "C87")
      (value "12pF")
      (footprint "Capacitor:CAP0402_REDUCED")
      (description "Capacitor, 12pF, C0G, 25V, ±0.05pF, 0402, Implant-grade")
      (fields
        (field (name "MANUFACTURER") "AVX")
        (field (name "RATING") "25V")
        (field (name "Comment") "C0402C120J3GACAUTO")
      )
      (libsource (lib "Miscellaneous Devices") (part "Cap"))
    )
    (comp (ref "C88")
      (value "12pF")
      (footprint "Capacitor:CAP0402_REDUCED")
      (description "Capacitor, 12pF, C0G, 25V, ±0.05pF, 0402, Implant-grade")
      (fields
        (field (name "MANUFACTURER") "AVX")
        (field (name "RATING") "25V")
        (field (name "Comment") "C0402C120J3GACAUTO")
      )
      (libsource (lib "Miscellaneous Devices") (part "Cap"))
    )
    (comp (ref "C89")
      (value "12pF")
      (footprint "Capacitor:CAP0402_REDUCED")
      (description "Capacitor, 12pF, C0G, 25V, ±0.05pF, 0402, Implant-grade")
      (fields
        (field (name "MANUFACTURER") "AVX")
        (field (name "RATING") "25V")
        (field (name "Comment") "C0402C120J3GACAUTO")
      )
      (libsource (lib "Miscellaneous Devices") (part "Cap"))
    )
    (comp (ref "C90")
      (value "12pF")
      (footprint "Capacitor:CAP0402_REDUCED")
      (description "Capacitor, 12pF, C0G, 25V, ±0.05pF, 0402, Implant-grade")
      (fields
        (field (name "MANUFACTURER") "AVX")
        (field (name "RATING") "25V")
        (field (name "Comment") "C0402C120J3GACAUTO")
      )
      (libsource (lib "Miscellaneous Devices") (part "Cap"))
    )
    (comp (ref "C91")
      (value "0.1uF")
      (footprint "Capacitor:CAP0402_REDUCED")
      (description "Capacitor, 0.1uF, X7R, 16V, 10%, 0402, Implant-grade")
      (fields
        (field (name "MANUFACTURER") "Murata")
        (field (name "RATING") "16V")
        (field (name "PACKAGE DESCRIPTION") "0402")
        (field (name "Comment") "GCH155R71C104KE01")
      )
      (libsource (lib "Miscellaneous Devices") (part "Cap"))
    )
    (comp (ref "C92")
      (value "4.7uF")
      (footprint "Capacitor:CAP0603_REDUCED")
      (description "Capacitor, 4.7uF, X5R, 16V, 10%, 0603, Implant-grade")
      (fields
        (field (name "MANUFACTURER") "Murata")
        (field (name "RATING") "16V")
        (field (name "Comment") "GCH188R61C475KE11")
      )
      (libsource (lib "Miscellaneous Devices") (part "Cap"))
    )
    (comp (ref "C93")
      (value "0.1uF")
      (footprint "Capacitor:CAP0402_REDUCED")
      (description "Capacitor, 0.1uF, X7R, 16V, 10%, 0402, Implant-grade")
      (fields
        (field (name "MANUFACTURER") "Murata")
        (field (name "RATING") "16V")
        (field (name "PACKAGE DESCRIPTION") "0402")
        (field (name "Comment") "GCH155R71C104KE01")
      )
      (libsource (lib "Miscellaneous Devices") (part "Cap"))
    )
    (comp (ref "C94")
      (value "100pF")
      (footprint "Capacitor:CAP0402_REDUCED")
      (description "Capacitor, 100pF, C0G, 50V, 5%, 0402, Implant-grade")
      (fields
        (field (name "MANUFACTURER") "Murata")
        (field (name "RATING") "50V")
        (field (name "Comment") "GCH1555C1H101JE01")
      )
      (libsource (lib "Miscellaneous Devices") (part "Cap"))
    )
    (comp (ref "C95")
      (value "1.0uF")
      (footprint "Capacitor:CAP0603_REDUCED")
      (description "Capacitor, 1.0uF, X5R, 16V, 10%, 0603, Implant-grade")
      (fields
        (field (name "MANUFACTURER") "Murata")
        (field (name "RATING") "16V")
        (field (name "Comment") "GCH188R71C105KE01")
      )
      (libsource (lib "Miscellaneous Devices") (part "Cap"))
    )
    (comp (ref "C96")
      (value "TBD")
      (footprint "Capacitor:CAP0402_REDUCED")
      (description "Capacitor, TBD, 0402")
      (fields (field (name "RATING") "25V"))
      (libsource (lib "Miscellaneous Devices") (part "Cap"))
    )
    (comp (ref "C97")
      (value "TBD")
      (footprint "Capacitor:CAP0402_REDUCED")
      (description "Capacitor, TBD, 0402")
      (fields (field (name "RATING") "25V"))
      (libsource (lib "Miscellaneous Devices") (part "Cap"))
    )
    (comp (ref "C98")
      (value "TBD")
      (footprint "Capacitor:CAP0402_REDUCED")
      (description "Capacitor, TBD, 0402")
      (fields (field (name "RATING") "25V"))
      (libsource (lib "Miscellaneous Devices") (part "Cap"))
    )
    (comp (ref "C99")
      (value "DNP")
      (footprint "Capacitor:CAP0402_REDUCED")
      (description "Capacitor, DNP, 0402")
      (libsource (lib "Miscellaneous Devices") (part "Cap"))
    )
    (comp (ref "C201")
      (value "1000pF")
      (footprint "Capacitor:CAP0402_REDUCED")
      (description "Capacitor, 1000pF, X7R, 50V, 10%, 0402, Implant-grade")
      (fields
        (field (name "MANUFACTURER") "Murata")
        (field (name "RATING") "50V")
        (field (name "Comment") "GRM1555C1H102JA01D")
      )
      (libsource (lib "Miscellaneous Devices") (part "Cap"))
    )
    (comp (ref "C202")
      (value "0.33uF")
      (footprint "Capacitor:CAP0402_REDUCED")
      (description "Capacitor, 0.33uF, X7S, 16V, 10%, 0402")
      (fields
        (field (name "MANUFACTURER") "TDK")
        (field (name "RATING") "16V")
        (field (name "Comment") "CGA2B1X7S1C334K050BC")
      )
      (libsource (lib "Miscellaneous Devices") (part "Cap"))
    )
    (comp (ref "C203")
      (value "1500pF")
      (footprint "Capacitor:CAP0402_REDUCED")
      (description "Capacitor, 1500pF, X7R, 50V, 10%, 0402")
      (fields
        (field (name "MANUFACTURER") "Murata")
        (field (name "RATING") "50V")
        (field (name "Comment") "GCM155R71H152KA37D")
      )
      (libsource (lib "Miscellaneous Devices") (part "Cap"))
    )
    (comp (ref "C204")
      (value "0.01uF")
      (footprint "Capacitor:CAP0402_REDUCED")
      (description "Capacitor, 0.01uF, X7R, 50V, 10%, 0402, Implant-grade")
      (fields
        (field (name "MANUFACTURER") "Murata")
        (field (name "RATING") "50V")
        (field (name "Comment") "GCH155R71H103KE01")
      )
      (libsource (lib "Miscellaneous Devices") (part "Cap"))
    )
    (comp (ref "C205")
      (value "0.33uF")
      (footprint "Capacitor:CAP0402_REDUCED")
      (description "Capacitor, 0.33uF, X7S, 16V, 10%, 0402")
      (fields
        (field (name "MANUFACTURER") "TDK")
        (field (name "RATING") "16V")
        (field (name "Comment") "CGA2B1X7S1C334K050BC")
      )
      (libsource (lib "Miscellaneous Devices") (part "Cap"))
    )
    (comp (ref "C206")
      (value "0.1uF")
      (footprint "Capacitor:CAP0402_REDUCED")
      (description "Capacitor, 0.1uF, X7R, 16V, 10%, 0402, Implant-grade")
      (fields
        (field (name "MANUFACTURER") "Murata")
        (field (name "RATING") "16V")
        (field (name "PACKAGE DESCRIPTION") "0402")
        (field (name "Comment") "GCH155R71C104KE01")
      )
      (libsource (lib "Miscellaneous Devices") (part "Cap"))
    )
    (comp (ref "C207")
      (value "0.1uF")
      (footprint "Capacitor:CAP0402_REDUCED")
      (description "Capacitor, 0.1uF, X7R, 16V, 10%, 0402, Implant-grade")
      (fields
        (field (name "MANUFACTURER") "Murata")
        (field (name "RATING") "16V")
        (field (name "PACKAGE DESCRIPTION") "0402")
        (field (name "Comment") "GCH155R71C104KE01")
      )
      (libsource (lib "Miscellaneous Devices") (part "Cap"))
    )
    (comp (ref "C241")
      (value "1000pF")
      (footprint "Capacitor:CAP0402_REDUCED")
      (description "Capacitor, 1000pF, X7R, 50V, 10%, 0402, Implant-grade")
      (fields
        (field (name "MANUFACTURER") "Murata")
        (field (name "RATING") "50V")
        (field (name "Comment") "GRM1555C1H102JA01D")
      )
      (libsource (lib "Miscellaneous Devices") (part "Cap"))
    )
    (comp (ref "C242")
      (value "2.2uF")
      (footprint "Capacitor:CAP0603_REDUCED")
      (description "Capacitor, 2.2uF, X7R, 16V, 10%, 0603, Implant-grade")
      (fields
        (field (name "MANUFACTURER") "Murata")
        (field (name "RATING") "16V")
        (field (name "Comment") "GRM188Z71C225ME43J")
      )
      (libsource (lib "Miscellaneous Devices") (part "Cap"))
    )
    (comp (ref "C243")
      (value "0.1uF")
      (footprint "Capacitor:CAP0402_REDUCED")
      (description "Capacitor, 0.1uF, X7R, 16V, 10%, 0402, Implant-grade")
      (fields
        (field (name "MANUFACTURER") "Murata")
        (field (name "RATING") "16V")
        (field (name "PACKAGE DESCRIPTION") "0402")
        (field (name "Comment") "GCH155R71C104KE01")
      )
      (libsource (lib "Miscellaneous Devices") (part "Cap"))
    )
    (comp (ref "C244")
      (value "1.0uF")
      (footprint "Capacitor:CAP0603_REDUCED")
      (description "Capacitor, 1.0uF, X5R, 16V, 10%, 0603, Implant-grade")
      (fields
        (field (name "MANUFACTURER") "Murata")
        (field (name "RATING") "16V")
        (field (name "Comment") "GCH188R71C105KE01")
      )
      (libsource (lib "Miscellaneous Devices") (part "Cap"))
    )
    (comp (ref "C245")
      (value "2.2uF")
      (footprint "Capacitor:CAP0603_REDUCED")
      (description "Capacitor, 2.2uF, X7R, 16V, 10%, 0603, Implant-grade")
      (fields
        (field (name "MANUFACTURER") "Murata")
        (field (name "RATING") "16V")
        (field (name "Comment") "GRM188Z71C225ME43J")
      )
      (libsource (lib "Miscellaneous Devices") (part "Cap"))
    )
    (comp (ref "C246")
      (value "0.1uF")
      (footprint "Capacitor:CAP0402_REDUCED")
      (description "Capacitor, 0.1uF, X7R, 16V, 10%, 0402, Implant-grade")
      (fields
        (field (name "MANUFACTURER") "Murata")
        (field (name "RATING") "16V")
        (field (name "PACKAGE DESCRIPTION") "0402")
        (field (name "Comment") "GCH155R71C104KE01")
      )
      (libsource (lib "Miscellaneous Devices") (part "Cap"))
    )
    (comp (ref "C247")
      (value "0.1uF")
      (footprint "Capacitor:CAP0402_REDUCED")
      (description "Capacitor, 0.1uF, X7R, 16V, 10%, 0402, Implant-grade")
      (fields
        (field (name "MANUFACTURER") "Murata")
        (field (name "RATING") "16V")
        (field (name "PACKAGE DESCRIPTION") "0402")
        (field (name "Comment") "GCH155R71C104KE01")
      )
      (libsource (lib "Miscellaneous Devices") (part "Cap"))
    )
    (comp (ref "C301")
      (value "0.1uF")
      (footprint "Capacitor:CAP0402_REDUCED")
      (description "Capacitor, 0.1uF, X7R, 16V, 10%, 0402, Implant-grade")
      (fields
        (field (name "MANUFACTURER") "Murata")
        (field (name "RATING") "16V")
        (field (name "PACKAGE DESCRIPTION") "0402")
        (field (name "Comment") "GCH155R71C104KE01")
      )
      (libsource (lib "Miscellaneous Devices") (part "Cap"))
    )
    (comp (ref "C303")
      (value "0.1uF")
      (footprint "Capacitor:CAP0402_REDUCED")
      (description "Capacitor, 0.1uF, X7R, 16V, 10%, 0402, Implant-grade")
      (fields
        (field (name "MANUFACTURER") "Murata")
        (field (name "RATING") "16V")
        (field (name "PACKAGE DESCRIPTION") "0402")
        (field (name "Comment") "GCH155R71C104KE01")
      )
      (libsource (lib "Miscellaneous Devices") (part "Cap"))
    )
    (comp (ref "C304")
      (value "0.1uF")
      (footprint "Capacitor:CAP0402_REDUCED")
      (description "Capacitor, 0.1uF, X7R, 16V, 10%, 0402, Implant-grade")
      (fields
        (field (name "MANUFACTURER") "Murata")
        (field (name "RATING") "16V")
        (field (name "PACKAGE DESCRIPTION") "0402")
        (field (name "Comment") "GCH155R71C104KE01")
      )
      (libsource (lib "Miscellaneous Devices") (part "Cap"))
    )
    (comp (ref "C305")
      (value "0.1uF")
      (footprint "Capacitor:CAP0402_REDUCED")
      (description "Capacitor, 0.1uF, X7R, 16V, 10%, 0402, Implant-grade")
      (fields
        (field (name "MANUFACTURER") "Murata")
        (field (name "RATING") "16V")
        (field (name "PACKAGE DESCRIPTION") "0402")
        (field (name "Comment") "GCH155R71C104KE01")
      )
      (libsource (lib "Miscellaneous Devices") (part "Cap"))
    )
    (comp (ref "C306")
      (value "0.1uF")
      (footprint "Capacitor:CAP0402_REDUCED")
      (description "Capacitor, 0.1uF, X7R, 16V, 10%, 0402, Implant-grade")
      (fields
        (field (name "MANUFACTURER") "Murata")
        (field (name "RATING") "16V")
        (field (name "PACKAGE DESCRIPTION") "0402")
        (field (name "Comment") "GCH155R71C104KE01")
      )
      (libsource (lib "Miscellaneous Devices") (part "Cap"))
    )
    (comp (ref "C307")
      (value "0.1uF")
      (footprint "Capacitor:CAP0402_REDUCED")
      (description "Capacitor, 0.1uF, X7R, 16V, 10%, 0402, Implant-grade")
      (fields
        (field (name "MANUFACTURER") "Murata")
        (field (name "RATING") "16V")
        (field (name "PACKAGE DESCRIPTION") "0402")
        (field (name "Comment") "GCH155R71C104KE01")
      )
      (libsource (lib "Miscellaneous Devices") (part "Cap"))
    )
    (comp (ref "C381")
      (value "10uF")
      (footprint "Capacitor:CAP0805_REDUCED")
      (description "Capacitor, 10uF, X5R, 50V, 10%, 0805")
      (fields
        (field (name "MANUFACTURER") "Murata")
        (field (name "RATING") "50V")
        (field (name "Comment") "GRM21BR61H106ME43L")
      )
      (libsource (lib "Miscellaneous Devices") (part "Cap"))
    )
    (comp (ref "C382")
      (value "10uF")
      (footprint "Capacitor:CAP0805_REDUCED")
      (description "Capacitor, 10uF, X5R, 50V, 10%, 0805")
      (fields
        (field (name "MANUFACTURER") "Murata")
        (field (name "RATING") "50V")
        (field (name "Comment") "GRM21BR61H106ME43L")
      )
      (libsource (lib "Miscellaneous Devices") (part "Cap"))
    )
    (comp (ref "C383")
      (value "10uF")
      (footprint "Capacitor:CAP0805_REDUCED")
      (description "Capacitor, 10uF, X5R, 50V, 10%, 0805")
      (fields
        (field (name "MANUFACTURER") "Murata")
        (field (name "RATING") "50V")
        (field (name "Comment") "GRM21BR61H106ME43L")
      )
      (libsource (lib "Miscellaneous Devices") (part "Cap"))
    )
    (comp (ref "C384")
      (value "10uF")
      (footprint "Capacitor:CAP0805_REDUCED")
      (description "Capacitor, 10uF, X5R, 50V, 10%, 0805")
      (fields
        (field (name "MANUFACTURER") "Murata")
        (field (name "RATING") "50V")
        (field (name "Comment") "GRM21BR61H106ME43L")
      )
      (libsource (lib "Miscellaneous Devices") (part "Cap"))
    )
    (comp (ref "C397")
      (value "10uF")
      (footprint "Capacitor:CAP0805_REDUCED")
      (description "Capacitor, 10uF, X5R, 50V, 10%, 0805")
      (fields
        (field (name "MANUFACTURER") "Murata")
        (field (name "RATING") "50V")
        (field (name "Comment") "GRM21BR61H106ME43L")
      )
      (libsource (lib "Miscellaneous Devices") (part "Cap"))
    )
    (comp (ref "C401")
      (value "680pF")
      (footprint "CAP0402_REDUCED")
      (description "Capacitor, 680pF, C0G, 100V, 5%, 0402")
      (fields
        (field (name "MANUFACTURER") "TDK")
        (field (name "RATING") "100V")
        (field (name "Comment") "C1005C0G2A681J050BE")
      )
      (libsource (lib "Miscellaneous Devices") (part "Cap"))
    )
    (comp (ref "C402")
      (value "680pF")
      (footprint "CAP0402_REDUCED")
      (description "Capacitor, 680pF, C0G, 100V, 5%, 0402")
      (fields
        (field (name "MANUFACTURER") "TDK")
        (field (name "RATING") "100V")
        (field (name "Comment") "C1005C0G2A681J050BE")
      )
      (libsource (lib "Miscellaneous Devices") (part "Cap"))
    )
    (comp (ref "C403")
      (value "680pF")
      (footprint "CAP0402_REDUCED")
      (description "Capacitor, 680pF, C0G, 100V, 5%, 0402")
      (fields
        (field (name "MANUFACTURER") "TDK")
        (field (name "RATING") "100V")
        (field (name "Comment") "C1005C0G2A681J050BE")
      )
      (libsource (lib "Miscellaneous Devices") (part "Cap"))
    )
    (comp (ref "C404")
      (value "680pF")
      (footprint "CAP0402_REDUCED")
      (description "Capacitor, 680pF, C0G, 100V, 5%, 0402")
      (fields
        (field (name "MANUFACTURER") "TDK")
        (field (name "RATING") "100V")
        (field (name "Comment") "C1005C0G2A681J050BE")
      )
      (libsource (lib "Miscellaneous Devices") (part "Cap"))
    )
    (comp (ref "C405")
      (value "680pF")
      (footprint "CAP0402_REDUCED")
      (description "Capacitor, 680pF, C0G, 100V, 5%, 0402")
      (fields
        (field (name "MANUFACTURER") "TDK")
        (field (name "RATING") "100V")
        (field (name "Comment") "C1005C0G2A681J050BE")
      )
      (libsource (lib "Miscellaneous Devices") (part "Cap"))
    )
    (comp (ref "C406")
      (value "680pF")
      (footprint "CAP0402_REDUCED")
      (description "Capacitor, 680pF, C0G, 100V, 5%, 0402")
      (fields
        (field (name "MANUFACTURER") "TDK")
        (field (name "RATING") "100V")
        (field (name "Comment") "C1005C0G2A681J050BE")
      )
      (libsource (lib "Miscellaneous Devices") (part "Cap"))
    )
    (comp (ref "C407")
      (value "680pF")
      (footprint "CAP0402_REDUCED")
      (description "Capacitor, 680pF, C0G, 100V, 5%, 0402")
      (fields
        (field (name "MANUFACTURER") "TDK")
        (field (name "RATING") "100V")
        (field (name "Comment") "C1005C0G2A681J050BE")
      )
      (libsource (lib "Miscellaneous Devices") (part "Cap"))
    )
    (comp (ref "C408")
      (value "680pF")
      (footprint "CAP0402_REDUCED")
      (description "Capacitor, 680pF, C0G, 100V, 5%, 0402")
      (fields
        (field (name "MANUFACTURER") "TDK")
        (field (name "RATING") "100V")
        (field (name "Comment") "C1005C0G2A681J050BE")
      )
      (libsource (lib "Miscellaneous Devices") (part "Cap"))
    )
    (comp (ref "C409")
      (value "680pF")
      (footprint "CAP0402_REDUCED")
      (description "Capacitor, 680pF, C0G, 100V, 5%, 0402")
      (fields
        (field (name "MANUFACTURER") "TDK")
        (field (name "RATING") "100V")
        (field (name "Comment") "C1005C0G2A681J050BE")
      )
      (libsource (lib "Miscellaneous Devices") (part "Cap"))
    )
    (comp (ref "C410")
      (value "680pF")
      (footprint "CAP0402_REDUCED")
      (description "Capacitor, 680pF, C0G, 100V, 5%, 0402")
      (fields
        (field (name "MANUFACTURER") "TDK")
        (field (name "RATING") "100V")
        (field (name "Comment") "C1005C0G2A681J050BE")
      )
      (libsource (lib "Miscellaneous Devices") (part "Cap"))
    )
    (comp (ref "C411")
      (value "680pF")
      (footprint "CAP0402_REDUCED")
      (description "Capacitor, 680pF, C0G, 100V, 5%, 0402")
      (fields
        (field (name "MANUFACTURER") "TDK")
        (field (name "RATING") "100V")
        (field (name "Comment") "C1005C0G2A681J050BE")
      )
      (libsource (lib "Miscellaneous Devices") (part "Cap"))
    )
    (comp (ref "C412")
      (value "680pF")
      (footprint "CAP0402_REDUCED")
      (description "Capacitor, 680pF, C0G, 100V, 5%, 0402")
      (fields
        (field (name "MANUFACTURER") "TDK")
        (field (name "RATING") "100V")
        (field (name "Comment") "C1005C0G2A681J050BE")
      )
      (libsource (lib "Miscellaneous Devices") (part "Cap"))
    )
    (comp (ref "C413")
      (value "680pF")
      (footprint "CAP0402_REDUCED")
      (description "Capacitor, 680pF, C0G, 100V, 5%, 0402")
      (fields
        (field (name "MANUFACTURER") "TDK")
        (field (name "RATING") "100V")
        (field (name "Comment") "C1005C0G2A681J050BE")
      )
      (libsource (lib "Miscellaneous Devices") (part "Cap"))
    )
    (comp (ref "C414")
      (value "680pF")
      (footprint "CAP0402_REDUCED")
      (description "Capacitor, 680pF, C0G, 100V, 5%, 0402")
      (fields
        (field (name "MANUFACTURER") "TDK")
        (field (name "RATING") "100V")
        (field (name "Comment") "C1005C0G2A681J050BE")
      )
      (libsource (lib "Miscellaneous Devices") (part "Cap"))
    )
    (comp (ref "C415")
      (value "680pF")
      (footprint "CAP0402_REDUCED")
      (description "Capacitor, 680pF, C0G, 100V, 5%, 0402")
      (fields
        (field (name "MANUFACTURER") "TDK")
        (field (name "RATING") "100V")
        (field (name "Comment") "C1005C0G2A681J050BE")
      )
      (libsource (lib "Miscellaneous Devices") (part "Cap"))
    )
    (comp (ref "C416")
      (value "680pF")
      (footprint "CAP0402_REDUCED")
      (description "Capacitor, 680pF, C0G, 100V, 5%, 0402")
      (fields
        (field (name "MANUFACTURER") "TDK")
        (field (name "RATING") "100V")
        (field (name "Comment") "C1005C0G2A681J050BE")
      )
      (libsource (lib "Miscellaneous Devices") (part "Cap"))
    )
    (comp (ref "C501")
      (value "TBD")
      (footprint "Capacitor:CAP0805_REDUCED")
      (description "Capacitor, TBD, 0805")
      (libsource (lib "Miscellaneous Devices") (part "Cap"))
    )
    (comp (ref "C502")
      (value "TBD")
      (footprint "Capacitor:CAP0805_REDUCED")
      (description "Capacitor, TBD, 0805")
      (libsource (lib "Miscellaneous Devices") (part "Cap"))
    )
    (comp (ref "C503")
      (value "TBD")
      (footprint "Capacitor:CAP0805_REDUCED")
      (description "Capacitor, TBD, 0805")
      (libsource (lib "Miscellaneous Devices") (part "Cap"))
    )
    (comp (ref "C504")
      (value "TBD")
      (footprint "Capacitor:CAP0805_REDUCED")
      (description "Capacitor, TBD, 0805")
      (libsource (lib "Miscellaneous Devices") (part "Cap"))
    )
    (comp (ref "C505")
      (value "4.7uF")
      (footprint "Capacitor:CAP0805_REDUCED")
      (description "Capacitor, 4.7uF, X7S, 35V, 10%, 0805, Implant-grade")
      (fields
        (field (name "MANUFACTURER") "Murata")
        (field (name "RATING") "35V")
        (field (name "Comment") "GCH21BC7YA475KE11")
      )
      (libsource (lib "Miscellaneous Devices") (part "Cap"))
    )
    (comp (ref "C506")
      (value "4.7uF")
      (footprint "Capacitor:CAP0805_REDUCED")
      (description "Capacitor, 4.7uF, X7S, 35V, 10%, 0805, Implant-grade")
      (fields
        (field (name "MANUFACTURER") "Murata")
        (field (name "RATING") "35V")
        (field (name "Comment") "GCH21BC7YA475KE11")
      )
      (libsource (lib "Miscellaneous Devices") (part "Cap"))
    )
    (comp (ref "C507")
      (value "470pF")
      (footprint "Capacitor:CAP0402_REDUCED")
      (description "Capacitor, 470pF, X7R, 50V, 10%, 0402, Implant-grade")
      (fields
        (field (name "MANUFACTURER") "Murata")
        (field (name "RATING") "50V")
        (field (name "Comment") "GCH155R71H471KE01")
      )
      (libsource (lib "Miscellaneous Devices") (part "Cap"))
    )
    (comp (ref "C508")
      (value "100pF")
      (footprint "Capacitor:CAP0402_REDUCED")
      (description "Capacitor, 100pF, C0G, 50V, 5%, 0402, Implant-grade")
      (fields
        (field (name "MANUFACTURER") "Murata")
        (field (name "RATING") "50V")
        (field (name "Comment") "GCH1555C1H101JE01")
      )
      (libsource (lib "Miscellaneous Devices") (part "Cap"))
    )
    (comp (ref "C509")
      (value "1000pF")
      (footprint "Capacitor:CAP0402_REDUCED")
      (description "Capacitor, 1000pF, X7R, 50V, 10%, 0402, Implant-grade")
      (fields
        (field (name "MANUFACTURER") "Murata")
        (field (name "RATING") "50V")
        (field (name "Comment") "GRM1555C1H102JA01D")
      )
      (libsource (lib "Miscellaneous Devices") (part "Cap"))
    )
    (comp (ref "C510")
      (value "4.7uF")
      (footprint "Capacitor:CAP0805_REDUCED")
      (description "Capacitor, 4.7uF, X7S, 35V, 10%, 0805, Implant-grade")
      (fields
        (field (name "MANUFACTURER") "Murata")
        (field (name "RATING") "35V")
        (field (name "Comment") "GCH21BC7YA475KE11")
      )
      (libsource (lib "Miscellaneous Devices") (part "Cap"))
    )
    (comp (ref "C511")
      (value "4.7uF")
      (footprint "Capacitor:CAP0603_REDUCED")
      (description "Capacitor, 4.7uF, X5R, 16V, 10%, 0603, Implant-grade")
      (fields
        (field (name "MANUFACTURER") "Murata")
        (field (name "RATING") "16V")
        (field (name "Comment") "GCH188R61C475KE11")
      )
      (libsource (lib "Miscellaneous Devices") (part "Cap"))
    )
    (comp (ref "C512")
      (value "0.022uF")
      (footprint "Capacitor:CAP0402_REDUCED")
      (description "Capacitor, 0.022uF, X7R, 50V, 10%, 0402, Implant-grade")
      (fields
        (field (name "MANUFACTURER") "Murata")
        (field (name "RATING") "50V")
        (field (name "Comment") "GCH155R71H223KE01")
      )
      (libsource (lib "Miscellaneous Devices") (part "Cap"))
    )
    (comp (ref "C513")
      (value "0.022uF")
      (footprint "Capacitor:CAP0402_REDUCED")
      (description "Capacitor, 0.022uF, X7R, 50V, 10%, 0402, Implant-grade")
      (fields
        (field (name "MANUFACTURER") "Murata")
        (field (name "RATING") "50V")
        (field (name "Comment") "GCH155R71H223KE01")
      )
      (libsource (lib "Miscellaneous Devices") (part "Cap"))
    )
    (comp (ref "C514")
      (value "4.7uF")
      (footprint "Capacitor:CAP0603_REDUCED")
      (description "Capacitor, 4.7uF, X5R, 16V, 10%, 0603, Implant-grade")
      (fields
        (field (name "MANUFACTURER") "Murata")
        (field (name "RATING") "16V")
        (field (name "Comment") "GCH188R61C475KE11")
      )
      (libsource (lib "Miscellaneous Devices") (part "Cap"))
    )
    (comp (ref "D1")
      (value "NSR0130P2T5G")
      (footprint "DiodeTransistor:ONSC_SOD-923_CASE514AB")
      (description "Schottky, 30V, 100mA, 385mV, 200mW, SOD-923")
      (fields (field (name "MANUFACTURER") "ON Semiconductor"))
      (libsource (lib "DiodeTransistor") (part "NSR0130P2T5G"))
    )
    (comp (ref "D2")
      (value "NSR0130P2T5G")
      (footprint "DiodeTransistor:ONSC_SOD-923_CASE514AB")
      (description "Schottky, 30V, 100mA, 385mV, 200mW, SOD-923")
      (fields (field (name "MANUFACTURER") "ON Semiconductor"))
      (libsource (lib "DiodeTransistor") (part "NSR0130P2T5G"))
    )
    (comp (ref "D3")
      (value "NSR0130P2T5G")
      (footprint "DiodeTransistor:ONSC_SOD-923_CASE514AB")
      (description "Schottky, 30V, 100mA, 385mV, 200mW, SOD-923")
      (fields (field (name "MANUFACTURER") "ON Semiconductor"))
      (libsource (lib "DiodeTransistor") (part "NSR0130P2T5G"))
    )
    (comp (ref "D4")
      (value "NSR0130P2T5G")
      (footprint "DiodeTransistor:ONSC_SOD-923_CASE514AB")
      (description "Schottky, 30V, 100mA, 385mV, 200mW, SOD-923")
      (fields (field (name "MANUFACTURER") "ON Semiconductor"))
      (libsource (lib "DiodeTransistor") (part "NSR0130P2T5G"))
    )
    (comp (ref "D5")
      (value "NSR0130P2T5G")
      (footprint "DiodeTransistor:ONSC_SOD-923_CASE514AB")
      (description "Schottky, 30V, 100mA, 385mV, 200mW, SOD-923")
      (fields (field (name "MANUFACTURER") "ON Semiconductor"))
      (libsource (lib "DiodeTransistor") (part "NSR0130P2T5G"))
    )
    (comp (ref "D6")
      (value "NSR05T40XV2")
      (footprint "DiodeTransistor:STM_SOD-523_REDUCED")
      (description "Schottky, 40V, 500mA, 530mV, SOD-523")
      (fields (field (name "MANUFACTURER") "ON Semiconductor"))
      (libsource (lib "DiodeTransistor") (part "NSR05T40XV2T5G"))
    )
    (comp (ref "D7")
      (value "NSR05T40XV2")
      (footprint "DiodeTransistor:STM_SOD-523_REDUCED")
      (description "Schottky, 40V, 500mA, 530mV, SOD-523")
      (fields (field (name "MANUFACTURER") "ON Semiconductor"))
      (libsource (lib "DiodeTransistor") (part "NSR05T40XV2T5G"))
    )
    (comp (ref "D8")
      (value "NSR0130P2T5G")
      (footprint "DiodeTransistor:ONSC_SOD-923_CASE514AB")
      (description "Schottky, 30V, 100mA, 385mV, 200mW, SOD-923")
      (fields (field (name "MANUFACTURER") "ON Semiconductor"))
      (libsource (lib "DiodeTransistor") (part "NSR0130P2T5G"))
    )
    (comp (ref "D9")
      (value "NSR0130P2T5G")
      (footprint "DiodeTransistor:ONSC_SOD-923_CASE514AB")
      (description "Schottky, 30V, 100mA, 385mV, 200mW, SOD-923")
      (fields (field (name "MANUFACTURER") "ON Semiconductor"))
      (libsource (lib "DiodeTransistor") (part "NSR0130P2T5G"))
    )
    (comp (ref "D10")
      (value "NSR0130P2T5G")
      (footprint "DiodeTransistor:ONSC_SOD-923_CASE514AB")
      (description "Schottky, 30V, 100mA, 385mV, 200mW, SOD-923")
      (fields (field (name "MANUFACTURER") "ON Semiconductor"))
      (libsource (lib "DiodeTransistor") (part "NSR0130P2T5G"))
    )
    (comp (ref "D11")
      (value "NSR05T40XV2")
      (footprint "DiodeTransistor:STM_SOD-523_REDUCED")
      (description "Schottky, 40V, 500mA, 530mV, SOD-523")
      (fields (field (name "MANUFACTURER") "ON Semiconductor"))
      (libsource (lib "DiodeTransistor") (part "NSR05T40XV2T5G"))
    )
    (comp (ref "D12")
      (value "NSR05T40XV2")
      (footprint "DiodeTransistor:STM_SOD-523_REDUCED")
      (description "Schottky, 40V, 500mA, 530mV, SOD-523")
      (fields (field (name "MANUFACTURER") "ON Semiconductor"))
      (libsource (lib "DiodeTransistor") (part "NSR05T40XV2T5G"))
    )
    (comp (ref "D13")
      (value "NSR05T40XV2")
      (footprint "DiodeTransistor:STM_SOD-523_REDUCED")
      (description "Schottky, 40V, 500mA, 530mV, SOD-523")
      (fields (field (name "MANUFACTURER") "ON Semiconductor"))
      (libsource (lib "DiodeTransistor") (part "NSR05T40XV2T5G"))
    )
    (comp (ref "D14")
      (value "NSR05T40XV2")
      (footprint "DiodeTransistor:STM_SOD-523_REDUCED")
      (description "Schottky, 40V, 500mA, 530mV, SOD-523")
      (fields (field (name "MANUFACTURER") "ON Semiconductor"))
      (libsource (lib "DiodeTransistor") (part "NSR05T40XV2T5G"))
    )
    (comp (ref "D401")
      (value "TPD1E10B09DPY")
      (footprint "DiodeTransistor:TI_DPY_R-PX1SON-N2")
      (description "TVS Diode, Bidirectional, ±9.5V, 4.5A, 0402")
      (fields
        (field (name "MANUFACTURER") "Texas Instruments")
        (field (name "RATING") "±9.5V")
        (field (name "Comment") "TPD1E10B09")
      )
      (libsource (lib "CB_Altium_Library") (part "TPD1E10B09"))
    )
    (comp (ref "D402")
      (value "TPD1E10B09DPY")
      (footprint "DiodeTransistor:TI_DPY_R-PX1SON-N2")
      (description "TVS Diode, Bidirectional, ±9.5V, 4.5A, 0402")
      (fields
        (field (name "MANUFACTURER") "Texas Instruments")
        (field (name "RATING") "±9.5V")
        (field (name "Comment") "TPD1E10B09")
      )
      (libsource (lib "CB_Altium_Library") (part "TPD1E10B09"))
    )
    (comp (ref "D403")
      (value "TPD1E10B09DPY")
      (footprint "DiodeTransistor:TI_DPY_R-PX1SON-N2")
      (description "TVS Diode, Bidirectional, ±9.5V, 4.5A, 0402")
      (fields
        (field (name "MANUFACTURER") "Texas Instruments")
        (field (name "RATING") "±9.5V")
        (field (name "Comment") "TPD1E10B09")
      )
      (libsource (lib "CB_Altium_Library") (part "TPD1E10B09"))
    )
    (comp (ref "D404")
      (value "TPD1E10B09DPY")
      (footprint "DiodeTransistor:TI_DPY_R-PX1SON-N2")
      (description "TVS Diode, Bidirectional, ±9.5V, 4.5A, 0402")
      (fields
        (field (name "MANUFACTURER") "Texas Instruments")
        (field (name "RATING") "±9.5V")
        (field (name "Comment") "TPD1E10B09")
      )
      (libsource (lib "CB_Altium_Library") (part "TPD1E10B09"))
    )
    (comp (ref "D405")
      (value "TPD1E10B09DPY")
      (footprint "DiodeTransistor:TI_DPY_R-PX1SON-N2")
      (description "TVS Diode, Bidirectional, ±9.5V, 4.5A, 0402")
      (fields
        (field (name "MANUFACTURER") "Texas Instruments")
        (field (name "RATING") "±9.5V")
        (field (name "Comment") "TPD1E10B09")
      )
      (libsource (lib "CB_Altium_Library") (part "TPD1E10B09"))
    )
    (comp (ref "D406")
      (value "TPD1E10B09DPY")
      (footprint "DiodeTransistor:TI_DPY_R-PX1SON-N2")
      (description "TVS Diode, Bidirectional, ±9.5V, 4.5A, 0402")
      (fields
        (field (name "MANUFACTURER") "Texas Instruments")
        (field (name "RATING") "±9.5V")
        (field (name "Comment") "TPD1E10B09")
      )
      (libsource (lib "CB_Altium_Library") (part "TPD1E10B09"))
    )
    (comp (ref "D407")
      (value "TPD1E10B09DPY")
      (footprint "DiodeTransistor:TI_DPY_R-PX1SON-N2")
      (description "TVS Diode, Bidirectional, ±9.5V, 4.5A, 0402")
      (fields
        (field (name "MANUFACTURER") "Texas Instruments")
        (field (name "RATING") "±9.5V")
        (field (name "Comment") "TPD1E10B09")
      )
      (libsource (lib "CB_Altium_Library") (part "TPD1E10B09"))
    )
    (comp (ref "D408")
      (value "TPD1E10B09DPY")
      (footprint "DiodeTransistor:TI_DPY_R-PX1SON-N2")
      (description "TVS Diode, Bidirectional, ±9.5V, 4.5A, 0402")
      (fields
        (field (name "MANUFACTURER") "Texas Instruments")
        (field (name "RATING") "±9.5V")
        (field (name "Comment") "TPD1E10B09")
      )
      (libsource (lib "CB_Altium_Library") (part "TPD1E10B09"))
    )
    (comp (ref "D409")
      (value "TPD1E10B09DPY")
      (footprint "DiodeTransistor:TI_DPY_R-PX1SON-N2")
      (description "TVS Diode, Bidirectional, ±9.5V, 4.5A, 0402")
      (fields
        (field (name "MANUFACTURER") "Texas Instruments")
        (field (name "RATING") "±9.5V")
        (field (name "Comment") "TPD1E10B09")
      )
      (libsource (lib "CB_Altium_Library") (part "TPD1E10B09"))
    )
    (comp (ref "D410")
      (value "TPD1E10B09DPY")
      (footprint "DiodeTransistor:TI_DPY_R-PX1SON-N2")
      (description "TVS Diode, Bidirectional, ±9.5V, 4.5A, 0402")
      (fields
        (field (name "MANUFACTURER") "Texas Instruments")
        (field (name "RATING") "±9.5V")
        (field (name "Comment") "TPD1E10B09")
      )
      (libsource (lib "CB_Altium_Library") (part "TPD1E10B09"))
    )
    (comp (ref "D411")
      (value "TPD1E10B09DPY")
      (footprint "DiodeTransistor:TI_DPY_R-PX1SON-N2")
      (description "TVS Diode, Bidirectional, ±9.5V, 4.5A, 0402")
      (fields
        (field (name "MANUFACTURER") "Texas Instruments")
        (field (name "RATING") "±9.5V")
        (field (name "Comment") "TPD1E10B09")
      )
      (libsource (lib "CB_Altium_Library") (part "TPD1E10B09"))
    )
    (comp (ref "D412")
      (value "TPD1E10B09DPY")
      (footprint "DiodeTransistor:TI_DPY_R-PX1SON-N2")
      (description "TVS Diode, Bidirectional, ±9.5V, 4.5A, 0402")
      (fields
        (field (name "MANUFACTURER") "Texas Instruments")
        (field (name "RATING") "±9.5V")
        (field (name "Comment") "TPD1E10B09")
      )
      (libsource (lib "CB_Altium_Library") (part "TPD1E10B09"))
    )
    (comp (ref "D413")
      (value "TPD1E10B09DPY")
      (footprint "DiodeTransistor:TI_DPY_R-PX1SON-N2")
      (description "TVS Diode, Bidirectional, ±9.5V, 4.5A, 0402")
      (fields
        (field (name "MANUFACTURER") "Texas Instruments")
        (field (name "RATING") "±9.5V")
        (field (name "Comment") "TPD1E10B09")
      )
      (libsource (lib "CB_Altium_Library") (part "TPD1E10B09"))
    )
    (comp (ref "D414")
      (value "TPD1E10B09DPY")
      (footprint "DiodeTransistor:TI_DPY_R-PX1SON-N2")
      (description "TVS Diode, Bidirectional, ±9.5V, 4.5A, 0402")
      (fields
        (field (name "MANUFACTURER") "Texas Instruments")
        (field (name "RATING") "±9.5V")
        (field (name "Comment") "TPD1E10B09")
      )
      (libsource (lib "CB_Altium_Library") (part "TPD1E10B09"))
    )
    (comp (ref "D415")
      (value "TPD1E10B09DPY")
      (footprint "DiodeTransistor:TI_DPY_R-PX1SON-N2")
      (description "TVS Diode, Bidirectional, ±9.5V, 4.5A, 0402")
      (fields
        (field (name "MANUFACTURER") "Texas Instruments")
        (field (name "RATING") "±9.5V")
        (field (name "Comment") "TPD1E10B09")
      )
      (libsource (lib "CB_Altium_Library") (part "TPD1E10B09"))
    )
    (comp (ref "D416")
      (value "TPD1E10B09DPY")
      (footprint "DiodeTransistor:TI_DPY_R-PX1SON-N2")
      (description "TVS Diode, Bidirectional, ±9.5V, 4.5A, 0402")
      (fields
        (field (name "MANUFACTURER") "Texas Instruments")
        (field (name "RATING") "±9.5V")
        (field (name "Comment") "TPD1E10B09")
      )
      (libsource (lib "CB_Altium_Library") (part "TPD1E10B09"))
    )
    (comp (ref "D417")
      (value "TPD1E10B09DPY")
      (footprint "DiodeTransistor:TI_DPY_R-PX1SON-N2")
      (description "TVS Diode, Bidirectional, ±9.5V, 4.5A, 0402")
      (fields
        (field (name "MANUFACTURER") "Texas Instruments")
        (field (name "RATING") "±9.5V")
        (field (name "Comment") "TPD1E10B09")
      )
      (libsource (lib "CB_Altium_Library") (part "TPD1E10B09"))
    )
    (comp (ref "D418")
      (value "TPD1E10B09DPY")
      (footprint "DiodeTransistor:TI_DPY_R-PX1SON-N2")
      (description "TVS Diode, Bidirectional, ±9.5V, 4.5A, 0402")
      (fields
        (field (name "MANUFACTURER") "Texas Instruments")
        (field (name "RATING") "±9.5V")
        (field (name "Comment") "TPD1E10B09")
      )
      (libsource (lib "CB_Altium_Library") (part "TPD1E10B09"))
    )
    (comp (ref "D501")
      (value "NSR05T40XV2")
      (footprint "DiodeTransistor:STM_SOD-523_REDUCED")
      (description "Schottky, 40V, 500mA, 530mV, SOD-523")
      (fields (field (name "MANUFACTURER") "ON Semiconductor"))
      (libsource (lib "DiodeTransistor") (part "NSR05T40XV2T5G"))
    )
    (comp (ref "D502")
      (value "NSR0130P2T5G")
      (footprint "DiodeTransistor:ONSC_SOD-923_CASE514AB")
      (description "Schottky, 30V, 100mA, 385mV, 200mW, SOD-923")
      (fields (field (name "MANUFACTURER") "ON Semiconductor"))
      (libsource (lib "DiodeTransistor") (part "NSR0130P2T5G"))
    )
    (comp (ref "D503")
      (value "NSR0130P2T5G")
      (footprint "DiodeTransistor:ONSC_SOD-923_CASE514AB")
      (description "Schottky, 30V, 100mA, 385mV, 200mW, SOD-923")
      (fields (field (name "MANUFACTURER") "ON Semiconductor"))
      (libsource (lib "DiodeTransistor") (part "NSR0130P2T5G"))
    )
    (comp (ref "D504")
      (value "NSR05T40XV2")
      (footprint "DiodeTransistor:STM_SOD-523_REDUCED")
      (description "Schottky, 40V, 500mA, 530mV, SOD-523")
      (fields (field (name "MANUFACTURER") "ON Semiconductor"))
      (libsource (lib "DiodeTransistor") (part "NSR05T40XV2T5G"))
    )
    (comp (ref "D505")
      (value "NSR05T40XV2")
      (footprint "DiodeTransistor:STM_SOD-523_REDUCED")
      (description "Schottky, 40V, 500mA, 530mV, SOD-523")
      (fields (field (name "MANUFACTURER") "ON Semiconductor"))
      (libsource (lib "DiodeTransistor") (part "NSR05T40XV2T5G"))
    )
    (comp (ref "D506")
      (value "NSR05T40XV2")
      (footprint "DiodeTransistor:STM_SOD-523_REDUCED")
      (description "Schottky, 40V, 500mA, 530mV, SOD-523")
      (fields (field (name "MANUFACTURER") "ON Semiconductor"))
      (libsource (lib "DiodeTransistor") (part "NSR05T40XV2T5G"))
    )
    (comp (ref "D507")
      (value "NSR05T40XV2")
      (footprint "DiodeTransistor:STM_SOD-523_REDUCED")
      (description "Schottky, 40V, 500mA, 530mV, SOD-523")
      (fields (field (name "MANUFACTURER") "ON Semiconductor"))
      (libsource (lib "DiodeTransistor") (part "NSR05T40XV2T5G"))
    )
    (comp (ref "D508")
      (value "NSR0130P2T5G")
      (footprint "DiodeTransistor:ONSC_SOD-923_CASE514AB")
      (description "Schottky, 30V, 100mA, 385mV, 200mW, SOD-923")
      (fields (field (name "MANUFACTURER") "ON Semiconductor"))
      (libsource (lib "DiodeTransistor") (part "NSR0130P2T5G"))
    )
    (comp (ref "F1")
      (value "750mA")
      (footprint "Resistor:LITTELFUSE_440series_1206_REDUCED")
      (description "Fuse, 750mA, 63V, 1206")
      (fields (field (name "MANUFACTURER") "Littelfuse") (field (name "Comment") "0440.750WR"))
      (libsource (lib "Miscellaneous Devices") (part "Fuse 2"))
    )
    (comp (ref "F2")
      (value "750mA")
      (footprint "Resistor:LITTELFUSE_440series_1206_REDUCED")
      (description "Fuse, 750mA, 63V, 1206")
      (fields (field (name "MANUFACTURER") "Littelfuse") (field (name "Comment") "0440.750WR"))
      (libsource (lib "Miscellaneous Devices") (part "Fuse 2"))
    )
    (comp (ref "J1")
      (value "Kovar Block")
      (footprint "KOVAR_BLOCK_PAD_1.53MM")
      (description "Kovar block, TBD")
      (fields (field (name "MANUFACTURER") "TBD"))
      (libsource (lib "CB") (part "Kovar Block"))
    )
    (comp (ref "J2")
      (value "Kovar Block")
      (footprint "KOVAR_BLOCK_PAD_1.53MM")
      (description "Kovar block, TBD")
      (fields (field (name "MANUFACTURER") "TBD"))
      (libsource (lib "CB") (part "Kovar Block"))
    )
    (comp (ref "J3")
      (value "Kovar Block")
      (footprint "KOVAR_BLOCK_PAD_1.53MM")
      (description "Kovar block, TBD")
      (fields (field (name "MANUFACTURER") "TBD"))
      (libsource (lib "CB") (part "Kovar Block"))
    )
    (comp (ref "J4")
      (value "Kovar Block")
      (footprint "KOVAR_BLOCK_PAD_1.53MM")
      (description "Kovar block, TBD")
      (fields (field (name "MANUFACTURER") "TBD"))
      (libsource (lib "CB") (part "Kovar Block"))
    )
    (comp (ref "J5")
      (value "Coil Pad")
      (footprint "FEEDHOLE_20mil")
      (description "Coil TH pad, hole size and ring TBD")
      (libsource (lib "CB_Altium_Library") (part "FT Pad"))
    )
    (comp (ref "J6")
      (value "Coil Pad")
      (footprint "FEEDHOLE_20mil")
      (description "Coil TH pad, hole size and ring TBD")
      (libsource (lib "CB_Altium_Library") (part "FT Pad"))
    )
    (comp (ref "J401")
      (value "FT pad")
      (footprint "FEEDHOLE_20mil")
      (description "FT pad, Thru-hole, 20 mil hole")
      (fields (field (name "Comment") "THPAD_20m"))
      (libsource (lib "Mechanical") (part "HOLE_20m"))
    )
    (comp (ref "J402")
      (value "FT pad")
      (footprint "FEEDHOLE_20mil")
      (description "FT pad, Thru-hole, 20 mil hole")
      (fields (field (name "Comment") "THPAD_20m"))
      (libsource (lib "Mechanical") (part "HOLE_20m"))
    )
    (comp (ref "J403")
      (value "FT pad")
      (footprint "FEEDHOLE_20mil")
      (description "FT pad, Thru-hole, 20 mil hole")
      (fields (field (name "Comment") "THPAD_20m"))
      (libsource (lib "Mechanical") (part "HOLE_20m"))
    )
    (comp (ref "J404")
      (value "FT pad")
      (footprint "FEEDHOLE_20mil")
      (description "FT pad, Thru-hole, 20 mil hole")
      (fields (field (name "Comment") "THPAD_20m"))
      (libsource (lib "Mechanical") (part "HOLE_20m"))
    )
    (comp (ref "J405")
      (value "FT pad")
      (footprint "FEEDHOLE_20mil")
      (description "FT pad, Thru-hole, 20 mil hole")
      (fields (field (name "Comment") "THPAD_20m"))
      (libsource (lib "Mechanical") (part "HOLE_20m"))
    )
    (comp (ref "J406")
      (value "FT pad")
      (footprint "FEEDHOLE_20mil")
      (description "FT pad, Thru-hole, 20 mil hole")
      (fields (field (name "Comment") "THPAD_20m"))
      (libsource (lib "Mechanical") (part "HOLE_20m"))
    )
    (comp (ref "J407")
      (value "FT pad")
      (footprint "FEEDHOLE_20mil")
      (description "FT pad, Thru-hole, 20 mil hole")
      (fields (field (name "Comment") "THPAD_20m"))
      (libsource (lib "Mechanical") (part "HOLE_20m"))
    )
    (comp (ref "J408")
      (value "FT pad")
      (footprint "FEEDHOLE_20mil")
      (description "FT pad, Thru-hole, 20 mil hole")
      (fields (field (name "Comment") "THPAD_20m"))
      (libsource (lib "Mechanical") (part "HOLE_20m"))
    )
    (comp (ref "J409")
      (value "FT pad")
      (footprint "FEEDHOLE_20mil")
      (description "FT pad, Thru-hole, 20 mil hole")
      (fields (field (name "Comment") "THPAD_20m"))
      (libsource (lib "Mechanical") (part "HOLE_20m"))
    )
    (comp (ref "J410")
      (value "FT pad")
      (footprint "FEEDHOLE_20mil")
      (description "FT pad, Thru-hole, 20 mil hole")
      (fields (field (name "Comment") "THPAD_20m"))
      (libsource (lib "Mechanical") (part "HOLE_20m"))
    )
    (comp (ref "J411")
      (value "FT pad")
      (footprint "FEEDHOLE_20mil")
      (description "FT pad, Thru-hole, 20 mil hole")
      (fields (field (name "Comment") "THPAD_20m"))
      (libsource (lib "Mechanical") (part "HOLE_20m"))
    )
    (comp (ref "J412")
      (value "FT pad")
      (footprint "FEEDHOLE_20mil")
      (description "FT pad, Thru-hole, 20 mil hole")
      (fields (field (name "Comment") "THPAD_20m"))
      (libsource (lib "Mechanical") (part "HOLE_20m"))
    )
    (comp (ref "J413")
      (value "FT pad")
      (footprint "FEEDHOLE_20mil")
      (description "FT pad, Thru-hole, 20 mil hole")
      (fields (field (name "Comment") "THPAD_20m"))
      (libsource (lib "Mechanical") (part "HOLE_20m"))
    )
    (comp (ref "J414")
      (value "FT pad")
      (footprint "FEEDHOLE_20mil")
      (description "FT pad, Thru-hole, 20 mil hole")
      (fields (field (name "Comment") "THPAD_20m"))
      (libsource (lib "Mechanical") (part "HOLE_20m"))
    )
    (comp (ref "J415")
      (value "FT pad")
      (footprint "FEEDHOLE_20mil")
      (description "FT pad, Thru-hole, 20 mil hole")
      (fields (field (name "Comment") "THPAD_20m"))
      (libsource (lib "Mechanical") (part "HOLE_20m"))
    )
    (comp (ref "J416")
      (value "FT pad")
      (footprint "FEEDHOLE_20mil")
      (description "FT pad, Thru-hole, 20 mil hole")
      (fields (field (name "Comment") "THPAD_20m"))
      (libsource (lib "Mechanical") (part "HOLE_20m"))
    )
    (comp (ref "J417")
      (value "FT pad")
      (footprint "FEEDHOLE_20mil")
      (description "FT pad, Thru-hole, 20 mil hole")
      (fields (field (name "Comment") "THPAD_20m"))
      (libsource (lib "Mechanical") (part "HOLE_20m"))
    )
    (comp (ref "J418")
      (value "FT pad")
      (footprint "FEEDHOLE_20mil")
      (description "FT pad, Thru-hole, 20 mil hole")
      (fields (field (name "Comment") "THPAD_20m"))
      (libsource (lib "Mechanical") (part "HOLE_20m"))
    )
    (comp (ref "J419")
      (value "FT pad")
      (footprint "FEEDHOLE_20mil")
      (description "FT pad, Thru-hole, 20 mil hole")
      (fields (field (name "Comment") "THPAD_20m"))
      (libsource (lib "Mechanical") (part "HOLE_20m"))
    )
    (comp (ref "J501")
      (value "Coil Pad")
      (footprint "FEEDHOLE_20mil")
      (description "Coil TH pad, hole size and ring TBD")
      (libsource (lib "CB_Altium_Library") (part "FT Pad"))
    )
    (comp (ref "J502")
      (value "Coil Pad")
      (footprint "FEEDHOLE_20mil")
      (description "Coil TH pad, hole size and ring TBD")
      (libsource (lib "CB_Altium_Library") (part "FT Pad"))
    )
    (comp (ref "J901")
      (value "Header 4")
      (footprint "Mechanical:SAMTEC_TMS-104-01-G-S")
      (description "Header, 1.27mm, male, 1x4, thru-hole")
      (fields (field (name "MANUFACTURER") "Samtec"))
      (libsource (lib "Mechanical") (part "TMS-104-01-G-S"))
    )
    (comp (ref "J902")
      (value "Header 4")
      (footprint "Mechanical:SAMTEC_TMS-104-01-G-S")
      (description "Header, 1.27mm, male, 1x4, thru-hole")
      (fields (field (name "MANUFACTURER") "Samtec"))
      (libsource (lib "Mechanical") (part "TMS-104-01-G-S"))
    )
    (comp (ref "J905")
      (value "Header 4")
      (footprint "Mechanical:SAMTEC_TMS-104-01-G-S")
      (description "Header, 1.27mm, male, 1x4, thru-hole")
      (fields (field (name "MANUFACTURER") "Samtec"))
      (libsource (lib "Mechanical") (part "TMS-104-01-G-S"))
    )
    (comp (ref "J906")
      (value "Header 6")
      (footprint "Mechanical:SAMTEC_TMS-106-01-G-S")
      (description "Header, 1.27mm, male, 1x6, thru-hole")
      (fields (field (name "MANUFACTURER") "Samtec"))
      (libsource (lib "Mechanical") (part "TMS-106-01-G-S"))
    )
    (comp (ref "J907")
      (value "Header 6")
      (footprint "Mechanical:SAMTEC_TMS-106-01-G-S")
      (description "Header, 1.27mm, male, 1x6, thru-hole")
      (fields (field (name "MANUFACTURER") "Samtec"))
      (libsource (lib "Mechanical") (part "TMS-106-01-G-S"))
    )
    (comp (ref "J908")
      (value "Header 6")
      (footprint "Mechanical:SAMTEC_TMS-106-01-G-S")
      (description "Header, 1.27mm, male, 1x6, thru-hole")
      (fields (field (name "MANUFACTURER") "Samtec"))
      (libsource (lib "Mechanical") (part "TMS-106-01-G-S"))
    )
    (comp (ref "J909")
      (value "Header 6")
      (footprint "Mechanical:SAMTEC_TMS-106-01-G-S")
      (description "Header, 1.27mm, male, 1x6, thru-hole")
      (fields (field (name "MANUFACTURER") "Samtec"))
      (libsource (lib "Mechanical") (part "TMS-106-01-G-S"))
    )
    (comp (ref "J910")
      (value "1.27 mm, 2x5, Male, TH")
      (footprint "Mechanical:SAMTEC_FTSH-105-01-XXX-D-K")
      (description "Connector, 1.27 mm, 2x5, Male, TH")
      (fields (field (name "MANUFACTURER") "Samtec"))
      (libsource (lib "Mechanical") (part "FTSH-105-01-F-D-K"))
    )
    (comp (ref "J911")
      (value "1.27 mm, 2x5, Male, TH")
      (footprint "Mechanical:SAMTEC_FTSH-105-01-XXX-D-K")
      (description "Connector, 1.27 mm, 2x5, Male, TH")
      (fields (field (name "MANUFACTURER") "Samtec"))
      (libsource (lib "Mechanical") (part "FTSH-105-01-F-D-K"))
    )
    (comp (ref "L1")
      (value "DNP")
      (footprint "Resistor:RES0402_REDUCED")
      (description "Inductor, DNP, 0402")
      (libsource (lib "Miscellaneous Devices") (part "Inductor"))
    )
    (comp (ref "L2")
      (value "DNP")
      (footprint "Resistor:RES0402_REDUCED")
      (description "Inductor, DNP, 0402")
      (libsource (lib "Miscellaneous Devices") (part "Inductor"))
    )
    (comp (ref "L3")
      (value "10uH")
      (footprint "Inductor:WURTH_74438323100_REDUCED")
      (description "Inductor, 10uH, 600mA, 20%, 1008")
      (fields (field (name "MANUFACTURER") "Wurth") (field (name "Comment") "74438323100"))
      (libsource (lib "Miscellaneous Devices") (part "Inductor"))
    )
    (comp (ref "L5")
      (value "2.2uH")
      (footprint "TDK_VLS252010HBX-1")
      (description "Inductor, 2.2uH, 1.76A, 1008")
      (fields (field (name "MANUFACTURER") "TDK") (field (name "Comment") "VLS252010HBX-2R2M-1"))
      (libsource (lib "Inductor") (part "VLS252010HBX-2R2M-1"))
    )
    (comp (ref "L6")
      (value "33nH")
      (footprint "Inductor:MURATA_LQG15HS")
      (description "Inductor, Unshielded, 33nH, 350mA, 0402")
      (fields (field (name "MANUFACTURER") "Murata") (field (name "Comment") "LQG15HS33NJ02D"))
      (libsource (lib "Inductor") (part "LQG15HS33NJ02D"))
    )
    (comp (ref "L97")
      (value "TBD")
      (footprint "Inductor:MURATA_LQG15HS_0.52mm_0.49mm")
      (description "Inductor, TBD, 0402")
      (libsource (lib "Miscellaneous Devices") (part "Inductor"))
    )
    (comp (ref "L98")
      (value "TBD")
      (footprint "Inductor:MURATA_LQG15HS_0.52mm_0.49mm")
      (description "Inductor, TBD, 0402")
      (libsource (lib "Miscellaneous Devices") (part "Inductor"))
    )
    (comp (ref "L99")
      (value "DNP")
      (footprint "Inductor:MURATA_LQG15HS_REDUCED")
      (description "Inductor, DNP, 0402")
      (libsource (lib "Miscellaneous Devices") (part "Inductor"))
    )
    (comp (ref "L501")
      (value "10uH")
      (footprint "Inductor:WURTH_74438323100_REDUCED")
      (description "Inductor, 10uH, 600mA, 20%, 1008")
      (fields (field (name "MANUFACTURER") "Wurth") (field (name "Comment") "74438323100"))
      (libsource (lib "Miscellaneous Devices") (part "Inductor"))
    )
    (comp (ref "M1")
      (value "DMP21D5UFB4")
      (footprint "DIODESINC_X2-DFN1006-3_REDUCED")
      (description "MOSFET, P-chan, -20V, X2-DFN1006-3")
      (fields (field (name "MANUFACTURER") "Diodes Inc") (field (name "Comment") "DMP21D5UFB4-7B"))
      (libsource (lib "DiodeTransistor") (part "DMP21D5UFB4-7B"))
    )
    (comp (ref "M2")
      (value "DMP21D5UFB4")
      (footprint "DIODESINC_X2-DFN1006-3_REDUCED")
      (description "MOSFET, P-chan, -20V, X2-DFN1006-3")
      (fields (field (name "MANUFACTURER") "Diodes Inc") (field (name "Comment") "DMP21D5UFB4-7B"))
      (libsource (lib "DiodeTransistor") (part "DMP21D5UFB4-7B"))
    )
    (comp (ref "M3")
      (value "DMN2990UFZ")
      (footprint "DiodeTransistor:DIODESINC_X2-DFN0606-3")
      (description "MOSFET, N-Chan, 20V, DFN0606")
      (fields (field (name "MANUFACTURER") "Diodes Inc"))
      (libsource (lib "DiodeTransistor") (part "DMN2990UFZ"))
    )
    (comp (ref "M4")
      (value "DMN2990UFZ")
      (footprint "DiodeTransistor:DIODESINC_X2-DFN0606-3")
      (description "MOSFET, N-Chan, 20V, DFN0606")
      (fields (field (name "MANUFACTURER") "Diodes Inc"))
      (libsource (lib "DiodeTransistor") (part "DMN2990UFZ"))
    )
    (comp (ref "M5")
      (value "DMP21D5UFB4")
      (footprint "DIODESINC_X2-DFN1006-3_REDUCED")
      (description "MOSFET, P-chan, -20V, X2-DFN1006-3")
      (fields (field (name "MANUFACTURER") "Diodes Inc") (field (name "Comment") "DMP21D5UFB4-7B"))
      (libsource (lib "DiodeTransistor") (part "DMP21D5UFB4-7B"))
    )
    (comp (ref "M6")
      (value "DMN2990UFZ")
      (footprint "DiodeTransistor:DIODESINC_X2-DFN0606-3")
      (description "MOSFET, N-Chan, 20V, DFN0606")
      (fields (field (name "MANUFACTURER") "Diodes Inc"))
      (libsource (lib "DiodeTransistor") (part "DMN2990UFZ"))
    )
    (comp (ref "M7")
      (value "DMN2990UFZ")
      (footprint "DiodeTransistor:DIODESINC_X2-DFN0606-3")
      (description "MOSFET, N-Chan, 20V, DFN0606")
      (fields (field (name "MANUFACTURER") "Diodes Inc"))
      (libsource (lib "DiodeTransistor") (part "DMN2990UFZ"))
    )
    (comp (ref "M8")
      (value "DMN2990UFZ")
      (footprint "DiodeTransistor:DIODESINC_X2-DFN0606-3")
      (description "MOSFET, N-Chan, 20V, DFN0606")
      (fields (field (name "MANUFACTURER") "Diodes Inc"))
      (libsource (lib "DiodeTransistor") (part "DMN2990UFZ"))
    )
    (comp (ref "M9")
      (value "DMP2043UCA3")
      (footprint "DiodeTransistor:DIODESINC_X2-DSN1010-3_CUSTOMPIN")
      (description "MOSFET, P-chan, -20V, DFN1010-3")
      (fields (field (name "MANUFACTURER") "Diodes Inc") (field (name "Comment") "DMP2043UCA3-7"))
      (libsource (lib "CB_Altium_Library") (part "DMP22D4UFO"))
    )
    (comp (ref "M10")
      (value "DMP2043UCA3")
      (footprint "DiodeTransistor:DIODESINC_X2-DSN1010-3_CUSTOMPIN")
      (description "MOSFET, P-chan, -20V, DFN1010-3")
      (fields (field (name "MANUFACTURER") "Diodes Inc") (field (name "Comment") "DMP2043UCA3-7"))
      (libsource (lib "CB_Altium_Library") (part "DMP22D4UFO"))
    )
    (comp (ref "M11")
      (value "DMN2990UFZ")
      (footprint "DiodeTransistor:DIODESINC_X2-DFN0606-3")
      (description "MOSFET, N-Chan, 20V, DFN0606")
      (fields (field (name "MANUFACTURER") "Diodes Inc"))
      (libsource (lib "DiodeTransistor") (part "DMN2990UFZ"))
    )
    (comp (ref "M12")
      (value "DMN2990UFZ")
      (footprint "DiodeTransistor:DIODESINC_X2-DFN0606-3")
      (description "MOSFET, N-Chan, 20V, DFN0606")
      (fields (field (name "MANUFACTURER") "Diodes Inc"))
      (libsource (lib "DiodeTransistor") (part "DMN2990UFZ"))
    )
    (comp (ref "M13")
      (value "DMP21D5UFB4")
      (footprint "DIODESINC_X2-DFN1006-3_REDUCED")
      (description "MOSFET, P-chan, -20V, X2-DFN1006-3")
      (fields (field (name "MANUFACTURER") "Diodes Inc") (field (name "Comment") "DMP21D5UFB4-7B"))
      (libsource (lib "DiodeTransistor") (part "DMP21D5UFB4-7B"))
    )
    (comp (ref "M14")
      (value "DMN2990UFZ")
      (footprint "DiodeTransistor:DIODESINC_X2-DFN0606-3")
      (description "MOSFET, N-Chan, 20V, DFN0606")
      (fields (field (name "MANUFACTURER") "Diodes Inc"))
      (libsource (lib "DiodeTransistor") (part "DMN2990UFZ"))
    )
    (comp (ref "M15")
      (value "DMN2990UFZ")
      (footprint "DiodeTransistor:DIODESINC_X2-DFN0606-3")
      (description "MOSFET, N-Chan, 20V, DFN0606")
      (fields (field (name "MANUFACTURER") "Diodes Inc"))
      (libsource (lib "DiodeTransistor") (part "DMN2990UFZ"))
    )
    (comp (ref "M16")
      (value "DMN2990UFZ")
      (footprint "DiodeTransistor:DIODESINC_X2-DFN0606-3")
      (description "MOSFET, N-Chan, 20V, DFN0606")
      (fields (field (name "MANUFACTURER") "Diodes Inc"))
      (libsource (lib "DiodeTransistor") (part "DMN2990UFZ"))
    )
    (comp (ref "M17")
      (value "DMP2043UCA3")
      (footprint "DiodeTransistor:DIODESINC_X2-DSN1010-3_CUSTOMPIN")
      (description "MOSFET, P-chan, -20V, DFN1010-3")
      (fields (field (name "MANUFACTURER") "Diodes Inc") (field (name "Comment") "DMP2043UCA3-7"))
      (libsource (lib "CB_Altium_Library") (part "DMP22D4UFO"))
    )
    (comp (ref "M18")
      (value "DMP2043UCA3")
      (footprint "DiodeTransistor:DIODESINC_X2-DSN1010-3_CUSTOMPIN")
      (description "MOSFET, P-chan, -20V, DFN1010-3")
      (fields (field (name "MANUFACTURER") "Diodes Inc") (field (name "Comment") "DMP2043UCA3-7"))
      (libsource (lib "CB_Altium_Library") (part "DMP22D4UFO"))
    )
    (comp (ref "M19")
      (value "DMN2990UFZ")
      (footprint "DiodeTransistor:DIODESINC_X2-DFN0606-3")
      (description "MOSFET, N-Chan, 20V, DFN0606")
      (fields (field (name "MANUFACTURER") "Diodes Inc"))
      (libsource (lib "DiodeTransistor") (part "DMN2990UFZ"))
    )
    (comp (ref "M20")
      (value "DMN2990UFZ")
      (footprint "DiodeTransistor:DIODESINC_X2-DFN0606-3")
      (description "MOSFET, N-Chan, 20V, DFN0606")
      (fields (field (name "MANUFACTURER") "Diodes Inc"))
      (libsource (lib "DiodeTransistor") (part "DMN2990UFZ"))
    )
    (comp (ref "M21")
      (value "DMP21D5UFB4")
      (footprint "DIODESINC_X2-DFN1006-3_REDUCED")
      (description "MOSFET, P-chan, -20V, X2-DFN1006-3")
      (fields (field (name "MANUFACTURER") "Diodes Inc") (field (name "Comment") "DMP21D5UFB4-7B"))
      (libsource (lib "DiodeTransistor") (part "DMP21D5UFB4-7B"))
    )
    (comp (ref "M22")
      (value "DMP21D5UFB4")
      (footprint "DIODESINC_X2-DFN1006-3_REDUCED")
      (description "MOSFET, P-chan, -20V, X2-DFN1006-3")
      (fields (field (name "MANUFACTURER") "Diodes Inc") (field (name "Comment") "DMP21D5UFB4-7B"))
      (libsource (lib "DiodeTransistor") (part "DMP21D5UFB4-7B"))
    )
    (comp (ref "M23")
      (value "DMN2990UFZ")
      (footprint "DiodeTransistor:DIODESINC_X2-DFN0606-3")
      (description "MOSFET, N-Chan, 20V, DFN0606")
      (fields (field (name "MANUFACTURER") "Diodes Inc"))
      (libsource (lib "DiodeTransistor") (part "DMN2990UFZ"))
    )
    (comp (ref "M24")
      (value "DMP21D5UFB4")
      (footprint "DIODESINC_X2-DFN1006-3_REDUCED")
      (description "MOSFET, P-chan, -20V, X2-DFN1006-3")
      (fields (field (name "MANUFACTURER") "Diodes Inc") (field (name "Comment") "DMP21D5UFB4-7B"))
      (libsource (lib "DiodeTransistor") (part "DMP21D5UFB4-7B"))
    )
    (comp (ref "M25")
      (value "DMN2990UFZ")
      (footprint "DiodeTransistor:DIODESINC_X2-DFN0606-3")
      (description "MOSFET, N-Chan, 20V, DFN0606")
      (fields (field (name "MANUFACTURER") "Diodes Inc"))
      (libsource (lib "DiodeTransistor") (part "DMN2990UFZ"))
    )
    (comp (ref "M26")
      (value "DMN2990UFZ")
      (footprint "DiodeTransistor:DIODESINC_X2-DFN0606-3")
      (description "MOSFET, N-Chan, 20V, DFN0606")
      (fields (field (name "MANUFACTURER") "Diodes Inc"))
      (libsource (lib "DiodeTransistor") (part "DMN2990UFZ"))
    )
    (comp (ref "M27")
      (value "DMP21D5UFB4")
      (footprint "DIODESINC_X2-DFN1006-3_REDUCED")
      (description "MOSFET, P-chan, -20V, X2-DFN1006-3")
      (fields (field (name "MANUFACTURER") "Diodes Inc") (field (name "Comment") "DMP21D5UFB4-7B"))
      (libsource (lib "DiodeTransistor") (part "DMP21D5UFB4-7B"))
    )
    (comp (ref "M28")
      (value "DMP21D5UFB4")
      (footprint "DIODESINC_X2-DFN1006-3_REDUCED")
      (description "MOSFET, P-chan, -20V, X2-DFN1006-3")
      (fields (field (name "MANUFACTURER") "Diodes Inc") (field (name "Comment") "DMP21D5UFB4-7B"))
      (libsource (lib "DiodeTransistor") (part "DMP21D5UFB4-7B"))
    )
    (comp (ref "M29")
      (value "DMN2990UFZ")
      (footprint "DiodeTransistor:DIODESINC_X2-DFN0606-3")
      (description "MOSFET, N-Chan, 20V, DFN0606")
      (fields (field (name "MANUFACTURER") "Diodes Inc"))
      (libsource (lib "DiodeTransistor") (part "DMN2990UFZ"))
    )
    (comp (ref "M30")
      (value "DMP21D5UFB4")
      (footprint "DIODESINC_X2-DFN1006-3_REDUCED")
      (description "MOSFET, P-chan, -20V, X2-DFN1006-3")
      (fields (field (name "MANUFACTURER") "Diodes Inc") (field (name "Comment") "DMP21D5UFB4-7B"))
      (libsource (lib "DiodeTransistor") (part "DMP21D5UFB4-7B"))
    )
    (comp (ref "M31")
      (value "DMN2990UFZ")
      (footprint "DiodeTransistor:DIODESINC_X2-DFN0606-3")
      (description "MOSFET, N-Chan, 20V, DFN0606")
      (fields (field (name "MANUFACTURER") "Diodes Inc"))
      (libsource (lib "DiodeTransistor") (part "DMN2990UFZ"))
    )
    (comp (ref "M32")
      (value "DMP58D0LFB")
      (footprint "DiodeTransistor:DIODESINC_X1-DFN1006-3")
      (description "MOSFET, P-chan, -50V, DFN1006")
      (fields (field (name "MANUFACTURER") "Diodes Inc"))
      (libsource (lib "DiodeTransistor") (part "DMP58D0LFB"))
    )
    (comp (ref "M33")
      (value "DMP22D4UFO")
      (footprint "DiodeTransistor:DIODESINC_X2-DFN0604-3")
      (description "MOSFET, P-chan, -20V, DFN0604")
      (fields (field (name "MANUFACTURER") "Diodes Inc"))
      (libsource (lib "DiodeTransistor") (part "DMP22D4UFO"))
    )
    (comp (ref "M34")
      (value "DMN62D1LFB")
      (footprint "DiodeTransistor:DIODESINC_X1-DFN1006-3")
      (description "MOSFET, N-Chan, 60V, 320mA, DFN1006")
      (fields (field (name "MANUFACTURER") "Diodes Inc") (field (name "Comment") "DMN62D1LFB-7B"))
      (libsource (lib "DiodeTransistor") (part "DMN62D1SFB"))
    )
    (comp (ref "M91")
      (value "DMP22D4UFO")
      (footprint "DiodeTransistor:DIODESINC_X2-DFN0604-3")
      (description "MOSFET, P-chan, -20V, DFN0604")
      (fields (field (name "MANUFACTURER") "Diodes Inc"))
      (libsource (lib "DiodeTransistor") (part "DMP22D4UFO"))
    )
    (comp (ref "M301")
      (value "DMN65D8LFB")
      (footprint "DIODESINC_X1-DFN1006-3")
      (description "MOSFET, N-Chan, 60V, DFN1006")
      (fields
        (field (name "MANUFACTURER") "Diodes Inc")
        (field (name "RATING") "60V")
        (field (name "Comment") "DMN65D8LFB-7B")
      )
      (libsource (lib "DiodeTransistor") (part "DMN65D8LFB-7B"))
    )
    (comp (ref "M302")
      (value "DMN65D8LFB")
      (footprint "DIODESINC_X1-DFN1006-3")
      (description "MOSFET, N-Chan, 60V, DFN1006")
      (fields
        (field (name "MANUFACTURER") "Diodes Inc")
        (field (name "RATING") "60V")
        (field (name "Comment") "DMN65D8LFB-7B")
      )
      (libsource (lib "DiodeTransistor") (part "DMN65D8LFB-7B"))
    )
    (comp (ref "M303")
      (value "DMN65D8LFB")
      (footprint "DIODESINC_X1-DFN1006-3")
      (description "MOSFET, N-Chan, 60V, DFN1006")
      (fields
        (field (name "MANUFACTURER") "Diodes Inc")
        (field (name "RATING") "60V")
        (field (name "Comment") "DMN65D8LFB-7B")
      )
      (libsource (lib "DiodeTransistor") (part "DMN65D8LFB-7B"))
    )
    (comp (ref "M304")
      (value "DMN65D8LFB")
      (footprint "DIODESINC_X1-DFN1006-3")
      (description "MOSFET, N-Chan, 60V, DFN1006")
      (fields
        (field (name "MANUFACTURER") "Diodes Inc")
        (field (name "RATING") "60V")
        (field (name "Comment") "DMN65D8LFB-7B")
      )
      (libsource (lib "DiodeTransistor") (part "DMN65D8LFB-7B"))
    )
    (comp (ref "M317")
      (value "DMN65D8LFB")
      (footprint "DIODESINC_X1-DFN1006-3")
      (description "MOSFET, N-Chan, 60V, DFN1006")
      (fields
        (field (name "MANUFACTURER") "Diodes Inc")
        (field (name "RATING") "60V")
        (field (name "Comment") "DMN65D8LFB-7B")
      )
      (libsource (lib "DiodeTransistor") (part "DMN65D8LFB-7B"))
    )
    (comp (ref "M318")
      (value "DMP22D4UFO")
      (footprint "DiodeTransistor:DIODESINC_X2-DFN0604-3")
      (description "MOSFET, P-chan, -20V, DFN0604")
      (fields (field (name "MANUFACTURER") "Diodes Inc"))
      (libsource (lib "DiodeTransistor") (part "DMP22D4UFO"))
    )
    (comp (ref "M319")
      (value "DMN2990UFZ")
      (footprint "DiodeTransistor:DIODESINC_X2-DFN0606-3")
      (description "MOSFET, N-Chan, 20V, DFN0606")
      (fields (field (name "MANUFACTURER") "Diodes Inc"))
      (libsource (lib "DiodeTransistor") (part "DMN2990UFZ"))
    )
    (comp (ref "M501")
      (value "DMN62D1LFB")
      (footprint "DiodeTransistor:DIODESINC_X1-DFN1006-3")
      (description "MOSFET, N-Chan, 60V, 320mA, DFN1006")
      (fields (field (name "MANUFACTURER") "Diodes Inc") (field (name "Comment") "DMN62D1LFB-7B"))
      (libsource (lib "DiodeTransistor") (part "DMN62D1SFB"))
    )
    (comp (ref "M502")
      (value "DMN62D1LFB")
      (footprint "DiodeTransistor:DIODESINC_X1-DFN1006-3")
      (description "MOSFET, N-Chan, 60V, 320mA, DFN1006")
      (fields (field (name "MANUFACTURER") "Diodes Inc") (field (name "Comment") "DMN62D1LFB-7B"))
      (libsource (lib "DiodeTransistor") (part "DMN62D1SFB"))
    )
    (comp (ref "M503")
      (value "DMN62D1LFB")
      (footprint "DiodeTransistor:DIODESINC_X1-DFN1006-3")
      (description "MOSFET, N-Chan, 60V, 320mA, DFN1006")
      (fields (field (name "MANUFACTURER") "Diodes Inc") (field (name "Comment") "DMN62D1LFB-7B"))
      (libsource (lib "DiodeTransistor") (part "DMN62D1SFB"))
    )
    (comp (ref "M504")
      (value "DMP58D0LFB")
      (footprint "DiodeTransistor:DIODESINC_X1-DFN1006-3")
      (description "MOSFET, P-chan, -50V, DFN1006")
      (fields (field (name "MANUFACTURER") "Diodes Inc"))
      (libsource (lib "DiodeTransistor") (part "DMP58D0LFB"))
    )
    (comp (ref "M505")
      (value "DMN62D1LFB")
      (footprint "DiodeTransistor:DIODESINC_X1-DFN1006-3")
      (description "MOSFET, N-Chan, 60V, 320mA, DFN1006")
      (fields (field (name "MANUFACTURER") "Diodes Inc") (field (name "Comment") "DMN62D1LFB-7B"))
      (libsource (lib "DiodeTransistor") (part "DMN62D1SFB"))
    )
    (comp (ref "M506")
      (value "DMP2043UCA3")
      (footprint "DiodeTransistor:DIODESINC_X2-DSN1010-3_CUSTOMPIN")
      (description "MOSFET, P-chan, -20V, DFN1010-3")
      (fields (field (name "MANUFACTURER") "Diodes Inc") (field (name "Comment") "DMP2043UCA3-7"))
      (libsource (lib "CB_Altium_Library") (part "DMP22D4UFO"))
    )
    (comp (ref "M507")
      (value "DMP58D0LFB")
      (footprint "DiodeTransistor:DIODESINC_X1-DFN1006-3")
      (description "MOSFET, P-chan, -50V, DFN1006")
      (fields (field (name "MANUFACTURER") "Diodes Inc"))
      (libsource (lib "DiodeTransistor") (part "DMP58D0LFB"))
    )
    (comp (ref "M508")
      (value "DMP58D0LFB")
      (footprint "DiodeTransistor:DIODESINC_X1-DFN1006-3")
      (description "MOSFET, P-chan, -50V, DFN1006")
      (fields (field (name "MANUFACTURER") "Diodes Inc"))
      (libsource (lib "DiodeTransistor") (part "DMP58D0LFB"))
    )
    (comp (ref "M509")
      (value "DMN62D1SFB")
      (footprint "DiodeTransistor:DIODESINC_X1-DFN1006-3")
      (description "MOSFET, N-Chan, 60V, DFN1006")
      (fields (field (name "MANUFACTURER") "Diodes Inc"))
      (libsource (lib "DiodeTransistor") (part "DMN62D1SFB"))
    )
    (comp (ref "M510")
      (value "DMP58D0LFB")
      (footprint "DiodeTransistor:DIODESINC_X1-DFN1006-3")
      (description "MOSFET, P-chan, -50V, DFN1006")
      (fields (field (name "MANUFACTURER") "Diodes Inc"))
      (libsource (lib "DiodeTransistor") (part "DMP58D0LFB"))
    )
    (comp (ref "M511")
      (value "DMN62D1SFB")
      (footprint "DiodeTransistor:DIODESINC_X1-DFN1006-3")
      (description "MOSFET, N-Chan, 60V, DFN1006")
      (fields (field (name "MANUFACTURER") "Diodes Inc"))
      (libsource (lib "DiodeTransistor") (part "DMN62D1SFB"))
    )
    (comp (ref "M512")
      (value "DMN62D1SFB")
      (footprint "DiodeTransistor:DIODESINC_X1-DFN1006-3")
      (description "MOSFET, N-Chan, 60V, DFN1006")
      (fields (field (name "MANUFACTURER") "Diodes Inc"))
      (libsource (lib "DiodeTransistor") (part "DMN62D1SFB"))
    )
    (comp (ref "M513")
      (value "DMN62D1SFB")
      (footprint "DiodeTransistor:DIODESINC_X1-DFN1006-3")
      (description "MOSFET, N-Chan, 60V, DFN1006")
      (fields (field (name "MANUFACTURER") "Diodes Inc"))
      (libsource (lib "DiodeTransistor") (part "DMN62D1SFB"))
    )
    (comp (ref "M514")
      (value "DMN62D1SFB")
      (footprint "DiodeTransistor:DIODESINC_X1-DFN1006-3")
      (description "MOSFET, N-Chan, 60V, DFN1006")
      (fields (field (name "MANUFACTURER") "Diodes Inc"))
      (libsource (lib "DiodeTransistor") (part "DMN62D1SFB"))
    )
    (comp (ref "M515")
      (value "DMN2501UFB4")
      (footprint "DiodeTransistor:DIODESINC_X1-DFN1006-3")
      (description "MOSFET, N-Chan, 20V, DFN1006")
      (fields (field (name "MANUFACTURER") "Diodes Inc"))
      (libsource (lib "DiodeTransistor") (part "DMN62D1SFB"))
    )
    (comp (ref "Q301")
      (value "NST3906DP6T5G")
      (footprint "DiodeTransistor:DIODESINC_SOT-963-6")
      (description "Transistor, Dual PNP, -40V, 200mA, SOT963")
      (fields (field (name "MANUFACTURER") "ON Semi") (field (name "RATING") "-40V"))
      (libsource (lib "MPS") (part "DP0150BDJ"))
    )
    (comp (ref "Q302")
      (value "NST3906DP6T5G")
      (footprint "DiodeTransistor:DIODESINC_SOT-963-6")
      (description "Transistor, Dual PNP, -40V, 200mA, SOT963")
      (fields (field (name "MANUFACTURER") "ON Semi") (field (name "RATING") "-40V"))
      (libsource (lib "MPS") (part "DP0150BDJ"))
    )
    (comp (ref "Q303")
      (value "NST3906DP6T5G")
      (footprint "DiodeTransistor:DIODESINC_SOT-963-6")
      (description "Transistor, Dual PNP, -40V, 200mA, SOT963")
      (fields (field (name "MANUFACTURER") "ON Semi") (field (name "RATING") "-40V"))
      (libsource (lib "MPS") (part "DP0150BDJ"))
    )
    (comp (ref "Q304")
      (value "NST3906DP6T5G")
      (footprint "DiodeTransistor:DIODESINC_SOT-963-6")
      (description "Transistor, Dual PNP, -40V, 200mA, SOT963")
      (fields (field (name "MANUFACTURER") "ON Semi") (field (name "RATING") "-40V"))
      (libsource (lib "MPS") (part "DP0150BDJ"))
    )
    (comp (ref "Q317")
      (value "NST3906DP6T5G")
      (footprint "DiodeTransistor:DIODESINC_SOT-963-6")
      (description "Transistor, Dual PNP, -40V, 200mA, SOT963")
      (fields (field (name "MANUFACTURER") "ON Semi") (field (name "RATING") "-40V"))
      (libsource (lib "MPS") (part "DP0150BDJ"))
    )
    (comp (ref "Q318")
      (value "BC847BLP")
      (footprint "DIODESINC_X1-DFN1006-3")
      (description "Transistor, NPN, 45V, 100mA, DFN1006")
      (fields
        (field (name "MANUFACTURER") "Diodes Inc")
        (field (name "RATING") "45V")
        (field (name "Comment") "BC847BLP-7B")
      )
      (libsource (lib "DiodeTransistor") (part "BC847BLP-7B"))
    )
    (comp (ref "Q321")
      (value "BC847BLP")
      (footprint "DIODESINC_X1-DFN1006-3")
      (description "Transistor, NPN, 45V, 100mA, DFN1006")
      (fields
        (field (name "MANUFACTURER") "Diodes Inc")
        (field (name "RATING") "45V")
        (field (name "Comment") "BC847BLP-7B")
      )
      (libsource (lib "DiodeTransistor") (part "BC847BLP-7B"))
    )
    (comp (ref "Q322")
      (value "BC847BLP")
      (footprint "DIODESINC_X1-DFN1006-3")
      (description "Transistor, NPN, 45V, 100mA, DFN1006")
      (fields
        (field (name "MANUFACTURER") "Diodes Inc")
        (field (name "RATING") "45V")
        (field (name "Comment") "BC847BLP-7B")
      )
      (libsource (lib "DiodeTransistor") (part "BC847BLP-7B"))
    )
    (comp (ref "Q323")
      (value "BC847BLP")
      (footprint "DIODESINC_X1-DFN1006-3")
      (description "Transistor, NPN, 45V, 100mA, DFN1006")
      (fields
        (field (name "MANUFACTURER") "Diodes Inc")
        (field (name "RATING") "45V")
        (field (name "Comment") "BC847BLP-7B")
      )
      (libsource (lib "DiodeTransistor") (part "BC847BLP-7B"))
    )
    (comp (ref "Q324")
      (value "BC847BLP")
      (footprint "DIODESINC_X1-DFN1006-3")
      (description "Transistor, NPN, 45V, 100mA, DFN1006")
      (fields
        (field (name "MANUFACTURER") "Diodes Inc")
        (field (name "RATING") "45V")
        (field (name "Comment") "BC847BLP-7B")
      )
      (libsource (lib "DiodeTransistor") (part "BC847BLP-7B"))
    )
    (comp (ref "Q337")
      (value "BC847BLP")
      (footprint "DIODESINC_X1-DFN1006-3")
      (description "Transistor, NPN, 45V, 100mA, DFN1006")
      (fields
        (field (name "MANUFACTURER") "Diodes Inc")
        (field (name "RATING") "45V")
        (field (name "Comment") "BC847BLP-7B")
      )
      (libsource (lib "DiodeTransistor") (part "BC847BLP-7B"))
    )
    (comp (ref "R1")
      (value "10.0M")
      (footprint "Resistor:RES0402_REDUCED")
      (description "Resistor, 10.0M, 40V, 40mW, 1%, 0402, Implant-grade")
      (fields (field (name "MANUFACTURER") "Panasonic") (field (name "Comment") "WA20SM-1005F-NS62TRX"))
      (libsource (lib "GTXSchematicLibrary") (part "RC1005F106CS"))
    )
    (comp (ref "R2")
      (value "10.0M")
      (footprint "Resistor:RES0402_REDUCED")
      (description "Resistor, 10.0M, 40V, 40mW, 1%, 0402, Implant-grade")
      (fields (field (name "MANUFACTURER") "Panasonic") (field (name "Comment") "WA20SM-1005F-NS62TRX"))
      (libsource (lib "GTXSchematicLibrary") (part "RC1005F106CS"))
    )
    (comp (ref "R3")
      (value "5.10M")
      (footprint "Resistor:RES0402_REDUCED")
      (description "Resistor, 5.10M, 40V, 40mW, 5%, 0402, Implant-grade")
      (fields (field (name "MANUFACTURER") "Panasonic") (field (name "Comment") "WA20SM-5104F-NS62TRX"))
      (libsource (lib "GTXSchematicLibrary") (part "RC1005F106CS"))
    )
    (comp (ref "R4")
      (value "10.0M")
      (footprint "Resistor:RES0402_REDUCED")
      (description "Resistor, 10.0M, 40V, 40mW, 1%, 0402, Implant-grade")
      (fields (field (name "MANUFACTURER") "Panasonic") (field (name "Comment") "WA20SM-1005F-NS62TRX"))
      (libsource (lib "GTXSchematicLibrary") (part "RC1005F106CS"))
    )
    (comp (ref "R5")
      (value "10.0k")
      (footprint "Resistor:RES0402_REDUCED")
      (description "Resistor, 10.0k, 40V, 40mW, 1%, 0402, Implant-grade")
      (fields (field (name "MANUFACTURER") "Panasonic") (field (name "Comment") "WA20SM-1002F-NS62TRX"))
      (libsource (lib "GTXSchematicLibrary") (part "RC1005F106CS"))
    )
    (comp (ref "R6")
      (value "10.0M")
      (footprint "RES0402_REDUCED")
      (description "Resistor, 10.0M, 40V, 40mW, 1%, 0402, Implant-grade")
      (fields (field (name "MANUFACTURER") "Panasonic") (field (name "Comment") "WA20SM-1005F-NS62TRX"))
      (libsource (lib "GTXSchematicLibrary") (part "RC1005F106CS"))
    )
    (comp (ref "R7")
      (value "10.0M")
      (footprint "RES0402_REDUCED")
      (description "Resistor, 10.0M, 40V, 40mW, 1%, 0402, Implant-grade")
      (fields (field (name "MANUFACTURER") "Panasonic") (field (name "Comment") "WA20SM-1005F-NS62TRX"))
      (libsource (lib "GTXSchematicLibrary") (part "RC1005F106CS"))
    )
    (comp (ref "R8")
      (value "4.02k")
      (footprint "Resistor:RES0402_REDUCED")
      (description "Resistor, 4.02k, 40V, 40mW, 1%, 0402, Implant-grade")
      (fields (field (name "MANUFACTURER") "Panasonic") (field (name "Comment") "WA20SM-4021F-NS62TRX"))
      (libsource (lib "GTXSchematicLibrary") (part "RC1005F106CS"))
    )
    (comp (ref "R9")
      (value "7.50k")
      (footprint "Resistor:RES0402_REDUCED")
      (description "Resistor, 7.50k, 40V, 40mW, 1%, 0402, Implant-grade")
      (fields (field (name "MANUFACTURER") "Panasonic") (field (name "Comment") "WA20SM-7501F-NS62TRX"))
      (libsource (lib "GTXSchematicLibrary") (part "RC1005F106CS"))
    )
    (comp (ref "R10")
      (value "619k")
      (footprint "Resistor:RES0402_REDUCED")
      (description "Resistor, 619k, 40V, 100mW, 0.1%, 0402")
      (fields
        (field (name "MANUFACTURER") "Vishay")
        (field (name "RATING") "0.1%")
        (field (name "Comment") "MCS0402MD6193BE000")
      )
      (libsource (lib "GTXSchematicLibrary") (part "RC1005F106CS"))
    )
    (comp (ref "R11")
      (value "243k")
      (footprint "Resistor:RES0402_REDUCED")
      (description "Resistor, 243k, 40V, 100mW, 0.1%, 0402")
      (fields
        (field (name "MANUFACTURER") "TE Connectivity")
        (field (name "RATING") "0.1%")
        (field (name "Comment") "RP73PF1E243KBTDF")
      )
      (libsource (lib "GTXSchematicLibrary") (part "RC1005F106CS"))
    )
    (comp (ref "R12")
      (value "1.00M")
      (footprint "Resistor:RES0402_REDUCED")
      (description "Resistor, 1.00M, 40V, 40mW, 1%, 0402, Implant-grade")
      (fields (field (name "MANUFACTURER") "Panasonic") (field (name "Comment") "WA20SM-1004F-NS62TRX"))
      (libsource (lib "GTXSchematicLibrary") (part "RC1005F106CS"))
    )
    (comp (ref "R13")
      (value "10.0M")
      (footprint "Resistor:RES0402_REDUCED")
      (description "Resistor, 10.0M, 40V, 40mW, 1%, 0402, Implant-grade")
      (fields (field (name "MANUFACTURER") "Panasonic") (field (name "Comment") "WA20SM-1005F-NS62TRX"))
      (libsource (lib "GTXSchematicLibrary") (part "RC1005F106CS"))
    )
    (comp (ref "R14")
      (value "1.00M")
      (footprint "Resistor:RES0402_REDUCED")
      (description "Resistor, 1.00M, 40V, 40mW, 1%, 0402, Implant-grade")
      (fields (field (name "MANUFACTURER") "Panasonic") (field (name "Comment") "WA20SM-1004F-NS62TRX"))
      (libsource (lib "GTXSchematicLibrary") (part "RC1005F106CS"))
    )
    (comp (ref "R15")
      (value "10.0M")
      (footprint "RES0402_REDUCED")
      (description "Resistor, 10.0M, 40V, 40mW, 1%, 0402, Implant-grade")
      (fields (field (name "MANUFACTURER") "Panasonic") (field (name "Comment") "WA20SM-1005F-NS62TRX"))
      (libsource (lib "GTXSchematicLibrary") (part "RC1005F106CS"))
    )
    (comp (ref "R16")
      (value "4.02k")
      (footprint "Resistor:RES0402_REDUCED")
      (description "Resistor, 4.02k, 40V, 40mW, 1%, 0402, Implant-grade")
      (fields (field (name "MANUFACTURER") "Panasonic") (field (name "Comment") "WA20SM-4021F-NS62TRX"))
      (libsource (lib "GTXSchematicLibrary") (part "RC1005F106CS"))
    )
    (comp (ref "R17")
      (value "7.50k")
      (footprint "Resistor:RES0402_REDUCED")
      (description "Resistor, 7.50k, 40V, 40mW, 1%, 0402, Implant-grade")
      (fields (field (name "MANUFACTURER") "Panasonic") (field (name "Comment") "WA20SM-7501F-NS62TRX"))
      (libsource (lib "GTXSchematicLibrary") (part "RC1005F106CS"))
    )
    (comp (ref "R18")
      (value "619k")
      (footprint "Resistor:RES0402_REDUCED")
      (description "Resistor, 619k, 40V, 100mW, 0.1%, 0402")
      (fields
        (field (name "MANUFACTURER") "Vishay")
        (field (name "RATING") "0.1%")
        (field (name "Comment") "MCS0402MD6193BE000")
      )
      (libsource (lib "GTXSchematicLibrary") (part "RC1005F106CS"))
    )
    (comp (ref "R19")
      (value "243k")
      (footprint "Resistor:RES0402_REDUCED")
      (description "Resistor, 243k, 40V, 100mW, 0.1%, 0402")
      (fields
        (field (name "MANUFACTURER") "TE Connectivity")
        (field (name "RATING") "0.1%")
        (field (name "Comment") "RP73PF1E243KBTDF")
      )
      (libsource (lib "GTXSchematicLibrary") (part "RC1005F106CS"))
    )
    (comp (ref "R20")
      (value "1.00M")
      (footprint "Resistor:RES0402_REDUCED")
      (description "Resistor, 1.00M, 40V, 40mW, 1%, 0402, Implant-grade")
      (fields (field (name "MANUFACTURER") "Panasonic") (field (name "Comment") "WA20SM-1004F-NS62TRX"))
      (libsource (lib "GTXSchematicLibrary") (part "RC1005F106CS"))
    )
    (comp (ref "R21")
      (value "10.0M")
      (footprint "Resistor:RES0402_REDUCED")
      (description "Resistor, 10.0M, 40V, 40mW, 1%, 0402, Implant-grade")
      (fields (field (name "MANUFACTURER") "Panasonic") (field (name "Comment") "WA20SM-1005F-NS62TRX"))
      (libsource (lib "GTXSchematicLibrary") (part "RC1005F106CS"))
    )
    (comp (ref "R22")
      (value "1.00M")
      (footprint "Resistor:RES0402_REDUCED")
      (description "Resistor, 1.00M, 40V, 40mW, 1%, 0402, Implant-grade")
      (fields (field (name "MANUFACTURER") "Panasonic") (field (name "Comment") "WA20SM-1004F-NS62TRX"))
      (libsource (lib "GTXSchematicLibrary") (part "RC1005F106CS"))
    )
    (comp (ref "R23")
      (value "1.00M")
      (footprint "Resistor:RES0402_REDUCED")
      (description "Resistor, 1.00M, 40V, 40mW, 1%, 0402, Implant-grade")
      (fields (field (name "MANUFACTURER") "Panasonic") (field (name "Comment") "WA20SM-1004F-NS62TRX"))
      (libsource (lib "GTXSchematicLibrary") (part "RC1005F106CS"))
    )
    (comp (ref "R24")
      (value "1.00M")
      (footprint "Resistor:RES0402_REDUCED")
      (description "Resistor, 1.00M, 40V, 40mW, 1%, 0402, Implant-grade")
      (fields (field (name "MANUFACTURER") "Panasonic") (field (name "Comment") "WA20SM-1004F-NS62TRX"))
      (libsource (lib "GTXSchematicLibrary") (part "RC1005F106CS"))
    )
    (comp (ref "R25")
      (value "2.00M")
      (footprint "Resistor:RES0402_REDUCED")
      (description "Resistor, 2.00M, 40V, 40mW, 1%, 0402, Implant-grade")
      (fields (field (name "MANUFACTURER") "Panasonic") (field (name "Comment") "WA20SM-2004F-NS62TRX"))
      (libsource (lib "GTXSchematicLibrary") (part "RC1005F106CS"))
    )
    (comp (ref "R26")
      (value "1.00M")
      (footprint "Resistor:RES0402_REDUCED")
      (description "Resistor, 1.00M, 40V, 40mW, 1%, 0402, Implant-grade")
      (fields (field (name "MANUFACTURER") "Panasonic") (field (name "Comment") "WA20SM-1004F-NS62TRX"))
      (libsource (lib "GTXSchematicLibrary") (part "RC1005F106CS"))
    )
    (comp (ref "R27")
      (value "1.00M")
      (footprint "Resistor:RES0402_REDUCED")
      (description "Resistor, 1.00M, 40V, 40mW, 1%, 0402, Implant-grade")
      (fields (field (name "MANUFACTURER") "Panasonic") (field (name "Comment") "WA20SM-1004F-NS62TRX"))
      (libsource (lib "GTXSchematicLibrary") (part "RC1005F106CS"))
    )
    (comp (ref "R28")
      (value "2.00M")
      (footprint "Resistor:RES0402_REDUCED")
      (description "Resistor, 2.00M, 40V, 40mW, 1%, 0402, Implant-grade")
      (fields (field (name "MANUFACTURER") "Panasonic") (field (name "Comment") "WA20SM-2004F-NS62TRX"))
      (libsource (lib "GTXSchematicLibrary") (part "RC1005F106CS"))
    )
    (comp (ref "R29")
      (value "1.00M")
      (footprint "Resistor:RES0402_REDUCED")
      (description "Resistor, 1.00M, 40V, 40mW, 1%, 0402, Implant-grade")
      (fields (field (name "MANUFACTURER") "Panasonic") (field (name "Comment") "WA20SM-1004F-NS62TRX"))
      (libsource (lib "GTXSchematicLibrary") (part "RC1005F106CS"))
    )
    (comp (ref "R30")
      (value "Zero")
      (footprint "Resistor:RES0402_REDUCED")
      (description "Resistor, Zero ohms, 40V, 40mW, 1%, 0402, Implant-grade")
      (fields (field (name "MANUFACTURER") "Panasonic") (field (name "Comment") "WAJ20PG-NS62TRX"))
      (libsource (lib "CELERO") (part "R_ZERO_0402"))
    )
    (comp (ref "R31")
      (value "DNP")
      (footprint "Resistor:RES0402_REDUCED")
      (description "Resistor, DNP, 0402")
      (libsource (lib "GTXSchematicLibrary") (part "RC1005F106CS"))
    )
    (comp (ref "R32")
      (value "1.00M")
      (footprint "Resistor:RES0402_REDUCED")
      (description "Resistor, 1.00M, 40V, 40mW, 1%, 0402, Implant-grade")
      (fields (field (name "MANUFACTURER") "Panasonic") (field (name "Comment") "WA20SM-1004F-NS62TRX"))
      (libsource (lib "GTXSchematicLibrary") (part "RC1005F106CS"))
    )
    (comp (ref "R33")
      (value "5.10M")
      (footprint "Resistor:RES0402_REDUCED")
      (description "Resistor, 5.10M, 40V, 40mW, 5%, 0402, Implant-grade")
      (fields (field (name "MANUFACTURER") "Panasonic") (field (name "Comment") "WA20SM-5104F-NS62TRX"))
      (libsource (lib "GTXSchematicLibrary") (part "RC1005F106CS"))
    )
    (comp (ref "R34")
      (value "10.0k")
      (footprint "Resistor:RES0402_REDUCED")
      (description "Resistor, 10.0k, 40V, 40mW, 1%, 0402, Implant-grade")
      (fields (field (name "MANUFACTURER") "Panasonic") (field (name "Comment") "WA20SM-1002F-NS62TRX"))
      (libsource (lib "GTXSchematicLibrary") (part "RC1005F106CS"))
    )
    (comp (ref "R35")
      (value "100")
      (footprint "Resistor:RES0402_REDUCED")
      (description "Resistor, 100, 40V, 40mW, 1%, 0402, Implant-grade")
      (fields (field (name "MANUFACTURER") "Panasonic") (field (name "Comment") "WA20SM-1000F-NS62TRX"))
      (libsource (lib "GTXSchematicLibrary") (part "RC1005F106CS"))
    )
    (comp (ref "R36")
      (value "10.0M")
      (footprint "RES0402_REDUCED")
      (description "Resistor, 10.0M, 40V, 40mW, 1%, 0402, Implant-grade")
      (fields (field (name "MANUFACTURER") "Panasonic") (field (name "Comment") "WA20SM-1005F-NS62TRX"))
      (libsource (lib "GTXSchematicLibrary") (part "RC1005F106CS"))
    )
    (comp (ref "R37")
      (value "10.0M")
      (footprint "RES0402_REDUCED")
      (description "Resistor, 10.0M, 40V, 40mW, 1%, 0402, Implant-grade")
      (fields (field (name "MANUFACTURER") "Panasonic") (field (name "Comment") "WA20SM-1005F-NS62TRX"))
      (libsource (lib "GTXSchematicLibrary") (part "RC1005F106CS"))
    )
    (comp (ref "R38")
      (value "340k")
      (footprint "Resistor:RES0402_REDUCED")
      (description "Resistor, 340k, 40V, 40mW, 1%, 0402, Implant-grade")
      (fields (field (name "MANUFACTURER") "Panasonic") (field (name "Comment") "WA20SM-3403F-NS62TRX"))
      (libsource (lib "GTXSchematicLibrary") (part "RC1005F106CS"))
    )
    (comp (ref "R39")
      (value "40.2k")
      (footprint "Resistor:RES0402_REDUCED")
      (description "Resistor, 40.2k, 40V, 40mW, 1%, 0402, Implant-grade")
      (fields (field (name "MANUFACTURER") "Panasonic") (field (name "Comment") "WA20SM-4022F-NS62TRX"))
      (libsource (lib "GTXSchematicLibrary") (part "RC1005F106CS"))
    )
    (comp (ref "R40")
      (value "10.0M")
      (footprint "Resistor:RES0402_REDUCED")
      (description "Resistor, 10.0M, 40V, 40mW, 1%, 0402, Implant-grade")
      (fields (field (name "MANUFACTURER") "Panasonic") (field (name "Comment") "WA20SM-1005F-NS62TRX"))
      (libsource (lib "GTXSchematicLibrary") (part "RC1005F106CS"))
    )
    (comp (ref "R41")
      (value "10.0M")
      (footprint "Resistor:RES0402_REDUCED")
      (description "Resistor, 10.0M, 40V, 40mW, 1%, 0402, Implant-grade")
      (fields (field (name "MANUFACTURER") "Panasonic") (field (name "Comment") "WA20SM-1005F-NS62TRX"))
      (libsource (lib "GTXSchematicLibrary") (part "RC1005F106CS"))
    )
    (comp (ref "R42")
      (value "10.0M")
      (footprint "Resistor:RES0402_REDUCED")
      (description "Resistor, 10.0M, 40V, 40mW, 1%, 0402, Implant-grade")
      (fields (field (name "MANUFACTURER") "Panasonic") (field (name "Comment") "WA20SM-1005F-NS62TRX"))
      (libsource (lib "GTXSchematicLibrary") (part "RC1005F106CS"))
    )
    (comp (ref "R43")
      (value "10.0M")
      (footprint "Resistor:RES0402_REDUCED")
      (description "Resistor, 10.0M, 40V, 40mW, 1%, 0402, Implant-grade")
      (fields (field (name "MANUFACTURER") "Panasonic") (field (name "Comment") "WA20SM-1005F-NS62TRX"))
      (libsource (lib "GTXSchematicLibrary") (part "RC1005F106CS"))
    )
    (comp (ref "R44")
      (value "150k")
      (footprint "Resistor:RES0402_REDUCED")
      (description "Resistor, 150k, 40V, 40mW, 1%, 0402, Implant-grade")
      (fields (field (name "MANUFACTURER") "Panasonic") (field (name "Comment") "WA20SM-1503F-NS62TRX"))
      (libsource (lib "GTXSchematicLibrary") (part "RC1005F106CS"))
    )
    (comp (ref "R45")
      (value "49.9k")
      (footprint "Resistor:RES0402_REDUCED")
      (description "Resistor, 49.9k, 40V, 40mW, 1%, 0402, Implant-grade")
      (fields (field (name "MANUFACTURER") "Panasonic") (field (name "Comment") "WA20SM-4992F-NS62TRX"))
      (libsource (lib "GTXSchematicLibrary") (part "RC1005F106CS"))
    )
    (comp (ref "R46")
      (value "49.9k")
      (footprint "Resistor:RES0402_REDUCED")
      (description "Resistor, 49.9k, 40V, 40mW, 1%, 0402, Implant-grade")
      (fields (field (name "MANUFACTURER") "Panasonic") (field (name "Comment") "WA20SM-4992F-NS62TRX"))
      (libsource (lib "GTXSchematicLibrary") (part "RC1005F106CS"))
    )
    (comp (ref "R47")
      (value "Zero")
      (footprint "Resistor:RES0402_REDUCED")
      (description "Resistor, Zero ohms, 40V, 40mW, 1%, 0402, Implant-grade")
      (fields (field (name "MANUFACTURER") "Panasonic") (field (name "Comment") "WAJ20PG-NS62TRX"))
      (libsource (lib "CELERO") (part "R_ZERO_0402"))
    )
    (comp (ref "R48")
      (value "Zero")
      (footprint "Resistor:RES0402_REDUCED")
      (description "Resistor, Zero ohms, 40V, 40mW, 1%, 0402, Implant-grade")
      (fields (field (name "MANUFACTURER") "Panasonic") (field (name "Comment") "WAJ20PG-NS62TRX"))
      (libsource (lib "CELERO") (part "R_ZERO_0402"))
    )
    (comp (ref "R49")
      (value "DNP")
      (footprint "Resistor:RES0402_REDUCED")
      (description "Resistor, DNP, 0402")
      (libsource (lib "GTXSchematicLibrary") (part "RC1005F106CS"))
    )
    (comp (ref "R50")
      (value "DNP")
      (footprint "Resistor:RES0402_REDUCED")
      (description "Resistor, DNP, 0402")
      (libsource (lib "GTXSchematicLibrary") (part "RC1005F106CS"))
    )
    (comp (ref "R51")
      (value "10.0k")
      (footprint "Resistor:RES0402_REDUCED")
      (description "Resistor, 10.0k, 40V, 40mW, 1%, 0402, Implant-grade")
      (fields (field (name "MANUFACTURER") "Panasonic") (field (name "Comment") "WA20SM-1002F-NS62TRX"))
      (libsource (lib "GTXSchematicLibrary") (part "RC1005F106CS"))
    )
    (comp (ref "R52")
      (value "10.0k")
      (footprint "Resistor:RES0402_REDUCED")
      (description "Resistor, 10.0k, 40V, 40mW, 1%, 0402, Implant-grade")
      (fields (field (name "MANUFACTURER") "Panasonic") (field (name "Comment") "WA20SM-1002F-NS62TRX"))
      (libsource (lib "GTXSchematicLibrary") (part "RC1005F106CS"))
    )
    (comp (ref "R53")
      (value "10.0k")
      (footprint "Resistor:RES0402_REDUCED")
      (description "Resistor, 10.0k, 40V, 40mW, 1%, 0402, Implant-grade")
      (fields (field (name "MANUFACTURER") "Panasonic") (field (name "Comment") "WA20SM-1002F-NS62TRX"))
      (libsource (lib "GTXSchematicLibrary") (part "RC1005F106CS"))
    )
    (comp (ref "R54")
      (value "10.0k")
      (footprint "Resistor:RES0402_REDUCED")
      (description "Resistor, 10.0k, 40V, 40mW, 1%, 0402, Implant-grade")
      (fields (field (name "MANUFACTURER") "Panasonic") (field (name "Comment") "WA20SM-1002F-NS62TRX"))
      (libsource (lib "GTXSchematicLibrary") (part "RC1005F106CS"))
    )
    (comp (ref "R55")
      (value "10.0k")
      (footprint "Resistor:RES0402_REDUCED")
      (description "Resistor, 10.0k, 40V, 40mW, 1%, 0402, Implant-grade")
      (fields (field (name "MANUFACTURER") "Panasonic") (field (name "Comment") "WA20SM-1002F-NS62TRX"))
      (libsource (lib "GTXSchematicLibrary") (part "RC1005F106CS"))
    )
    (comp (ref "R201")
      (value "10.0M")
      (footprint "RES0402_REDUCED")
      (description "Resistor, 10.0M, 40V, 40mW, 1%, 0402, Implant-grade")
      (fields (field (name "MANUFACTURER") "Panasonic") (field (name "Comment") "WA20SM-1005F-NS62TRX"))
      (libsource (lib "GTXSchematicLibrary") (part "RC1005F106CS"))
    )
    (comp (ref "R202")
      (value "10.0M")
      (footprint "RES0402_REDUCED")
      (description "Resistor, 10.0M, 40V, 40mW, 1%, 0402, Implant-grade")
      (fields (field (name "MANUFACTURER") "Panasonic") (field (name "Comment") "WA20SM-1005F-NS62TRX"))
      (libsource (lib "GTXSchematicLibrary") (part "RC1005F106CS"))
    )
    (comp (ref "R203")
      (value "180k")
      (footprint "Resistor:RES0402_REDUCED")
      (description "Resistor, 180k, 40V, 40mW, 1%, 0402")
      (fields (field (name "MANUFACTURER") "KOA Speer") (field (name "Comment") "RK73H1ETTP1803F"))
      (libsource (lib "GTXSchematicLibrary") (part "RC1005F106CS"))
    )
    (comp (ref "R204")
      (value "180k")
      (footprint "Resistor:RES0402_REDUCED")
      (description "Resistor, 180k, 40V, 40mW, 1%, 0402")
      (fields (field (name "MANUFACTURER") "KOA Speer") (field (name "Comment") "RK73H1ETTP1803F"))
      (libsource (lib "GTXSchematicLibrary") (part "RC1005F106CS"))
    )
    (comp (ref "R205")
      (value "360k")
      (footprint "Resistor:RES0402_REDUCED")
      (description "Resistor, 360k, 40V, 40mW, 1%, 0402, Implant-grade")
      (fields (field (name "MANUFACTURER") "Panasonic") (field (name "Comment") "WA20SM-3603F-NS62TRX"))
      (libsource (lib "GTXSchematicLibrary") (part "RC1005F106CS"))
    )
    (comp (ref "R206")
      (value "1.40M")
      (footprint "Resistor:RES0402_REDUCED")
      (description "Resistor, 1.40M, 40V, 40mW, 1%, 0402, Implant-grade")
      (fields (field (name "MANUFACTURER") "Yageo") (field (name "Comment") "WA20SM-1404F-NS62TRX"))
      (libsource (lib "GTXSchematicLibrary") (part "RC1005F106CS"))
    )
    (comp (ref "R207")
      (value "10.0M")
      (footprint "RES0402_REDUCED")
      (description "Resistor, 10.0M, 40V, 40mW, 1%, 0402, Implant-grade")
      (fields (field (name "MANUFACTURER") "Panasonic") (field (name "Comment") "WA20SM-1005F-NS62TRX"))
      (libsource (lib "GTXSchematicLibrary") (part "RC1005F106CS"))
    )
    (comp (ref "R208")
      (value "10.0M")
      (footprint "RES0402_REDUCED")
      (description "Resistor, 10.0M, 40V, 40mW, 1%, 0402, Implant-grade")
      (fields (field (name "MANUFACTURER") "Panasonic") (field (name "Comment") "WA20SM-1005F-NS62TRX"))
      (libsource (lib "GTXSchematicLibrary") (part "RC1005F106CS"))
    )
    (comp (ref "R209")
      (value "1.00M")
      (footprint "Resistor:RES0402_REDUCED")
      (description "Resistor, 1.00M, 40V, 40mW, 1%, 0402, Implant-grade")
      (fields (field (name "MANUFACTURER") "Panasonic") (field (name "Comment") "WA20SM-1004F-NS62TRX"))
      (libsource (lib "GTXSchematicLibrary") (part "RC1005F106CS"))
    )
    (comp (ref "R210")
      (value "1.00M")
      (footprint "Resistor:RES0402_REDUCED")
      (description "Resistor, 1.00M, 40V, 40mW, 1%, 0402, Implant-grade")
      (fields (field (name "MANUFACTURER") "Panasonic") (field (name "Comment") "WA20SM-1004F-NS62TRX"))
      (libsource (lib "GTXSchematicLibrary") (part "RC1005F106CS"))
    )
    (comp (ref "R211")
      (value "249k")
      (footprint "Resistor:RES0402_REDUCED")
      (description "Resistor, 249k, 40V, 40mW, 1%, 0402, Implant-grade")
      (fields (field (name "MANUFACTURER") "Panasonic") (field (name "Comment") "WA20SM-2493F-NS62TRX"))
      (libsource (lib "GTXSchematicLibrary") (part "RC1005F106CS"))
    )
    (comp (ref "R212")
      (value "1.00M")
      (footprint "Resistor:RES0402_REDUCED")
      (description "Resistor, 1.00M, 40V, 40mW, 1%, 0402, Implant-grade")
      (fields (field (name "MANUFACTURER") "Panasonic") (field (name "Comment") "WA20SM-1004F-NS62TRX"))
      (libsource (lib "GTXSchematicLibrary") (part "RC1005F106CS"))
    )
    (comp (ref "R213")
      (value "10.0M")
      (footprint "RES0402_REDUCED")
      (description "Resistor, 10.0M, 40V, 40mW, 1%, 0402, Implant-grade")
      (fields (field (name "MANUFACTURER") "Panasonic") (field (name "Comment") "WA20SM-1005F-NS62TRX"))
      (libsource (lib "GTXSchematicLibrary") (part "RC1005F106CS"))
    )
    (comp (ref "R214")
      (value "10.0M")
      (footprint "RES0402_REDUCED")
      (description "Resistor, 10.0M, 40V, 40mW, 1%, 0402, Implant-grade")
      (fields (field (name "MANUFACTURER") "Panasonic") (field (name "Comment") "WA20SM-1005F-NS62TRX"))
      (libsource (lib "GTXSchematicLibrary") (part "RC1005F106CS"))
    )
    (comp (ref "R215")
      (value "Zero")
      (footprint "Resistor:RES0402_REDUCED")
      (description "Resistor, Zero ohms, 40V, 40mW, 1%, 0402, Implant-grade")
      (fields (field (name "MANUFACTURER") "Panasonic") (field (name "Comment") "WAJ20PG-NS62TRX"))
      (libsource (lib "CELERO") (part "R_ZERO_0402"))
    )
    (comp (ref "R241")
      (value "10.0M")
      (footprint "RES0402_REDUCED")
      (description "Resistor, 10.0M, 40V, 40mW, 1%, 0402, Implant-grade")
      (fields (field (name "MANUFACTURER") "Panasonic") (field (name "Comment") "WA20SM-1005F-NS62TRX"))
      (libsource (lib "GTXSchematicLibrary") (part "RC1005F106CS"))
    )
    (comp (ref "R242")
      (value "10.0M")
      (footprint "RES0402_REDUCED")
      (description "Resistor, 10.0M, 40V, 40mW, 1%, 0402, Implant-grade")
      (fields (field (name "MANUFACTURER") "Panasonic") (field (name "Comment") "WA20SM-1005F-NS62TRX"))
      (libsource (lib "GTXSchematicLibrary") (part "RC1005F106CS"))
    )
    (comp (ref "R243")
      (value "180k")
      (footprint "Resistor:RES0402_REDUCED")
      (description "Resistor, 180k, 40V, 40mW, 1%, 0402")
      (fields (field (name "MANUFACTURER") "KOA Speer") (field (name "Comment") "RK73H1ETTP1803F"))
      (libsource (lib "GTXSchematicLibrary") (part "RC1005F106CS"))
    )
    (comp (ref "R244")
      (value "180k")
      (footprint "Resistor:RES0402_REDUCED")
      (description "Resistor, 180k, 40V, 40mW, 1%, 0402")
      (fields (field (name "MANUFACTURER") "KOA Speer") (field (name "Comment") "RK73H1ETTP1803F"))
      (libsource (lib "GTXSchematicLibrary") (part "RC1005F106CS"))
    )
    (comp (ref "R245")
      (value "360k")
      (footprint "Resistor:RES0402_REDUCED")
      (description "Resistor, 360k, 40V, 40mW, 1%, 0402, Implant-grade")
      (fields (field (name "MANUFACTURER") "Panasonic") (field (name "Comment") "WA20SM-3603F-NS62TRX"))
      (libsource (lib "GTXSchematicLibrary") (part "RC1005F106CS"))
    )
    (comp (ref "R246")
      (value "1.40M")
      (footprint "Resistor:RES0402_REDUCED")
      (description "Resistor, 1.40M, 40V, 40mW, 1%, 0402, Implant-grade")
      (fields (field (name "MANUFACTURER") "Yageo") (field (name "Comment") "WA20SM-1404F-NS62TRX"))
      (libsource (lib "GTXSchematicLibrary") (part "RC1005F106CS"))
    )
    (comp (ref "R247")
      (value "10.0M")
      (footprint "RES0402_REDUCED")
      (description "Resistor, 10.0M, 40V, 40mW, 1%, 0402, Implant-grade")
      (fields (field (name "MANUFACTURER") "Panasonic") (field (name "Comment") "WA20SM-1005F-NS62TRX"))
      (libsource (lib "GTXSchematicLibrary") (part "RC1005F106CS"))
    )
    (comp (ref "R248")
      (value "10.0M")
      (footprint "RES0402_REDUCED")
      (description "Resistor, 10.0M, 40V, 40mW, 1%, 0402, Implant-grade")
      (fields (field (name "MANUFACTURER") "Panasonic") (field (name "Comment") "WA20SM-1005F-NS62TRX"))
      (libsource (lib "GTXSchematicLibrary") (part "RC1005F106CS"))
    )
    (comp (ref "R249")
      (value "1.00M")
      (footprint "Resistor:RES0402_REDUCED")
      (description "Resistor, 1.00M, 40V, 40mW, 1%, 0402, Implant-grade")
      (fields (field (name "MANUFACTURER") "Panasonic") (field (name "Comment") "WA20SM-1004F-NS62TRX"))
      (libsource (lib "GTXSchematicLibrary") (part "RC1005F106CS"))
    )
    (comp (ref "R250")
      (value "1.00M")
      (footprint "Resistor:RES0402_REDUCED")
      (description "Resistor, 1.00M, 40V, 40mW, 1%, 0402, Implant-grade")
      (fields (field (name "MANUFACTURER") "Panasonic") (field (name "Comment") "WA20SM-1004F-NS62TRX"))
      (libsource (lib "GTXSchematicLibrary") (part "RC1005F106CS"))
    )
    (comp (ref "R251")
      (value "100k")
      (footprint "Resistor:RES0402_REDUCED")
      (description "Resistor, 100k, 40V, 40mW, 1%, 0402, Implant-grade")
      (fields (field (name "MANUFACTURER") "Panasonic") (field (name "Comment") "WA20SM-1003F-NS62TRX"))
      (libsource (lib "GTXSchematicLibrary") (part "RC1005F106CS"))
    )
    (comp (ref "R252")
      (value "1.00M")
      (footprint "Resistor:RES0402_REDUCED")
      (description "Resistor, 1.00M, 40V, 40mW, 1%, 0402, Implant-grade")
      (fields (field (name "MANUFACTURER") "Panasonic") (field (name "Comment") "WA20SM-1004F-NS62TRX"))
      (libsource (lib "GTXSchematicLibrary") (part "RC1005F106CS"))
    )
    (comp (ref "R253")
      (value "10.0M")
      (footprint "RES0402_REDUCED")
      (description "Resistor, 10.0M, 40V, 40mW, 1%, 0402, Implant-grade")
      (fields (field (name "MANUFACTURER") "Panasonic") (field (name "Comment") "WA20SM-1005F-NS62TRX"))
      (libsource (lib "GTXSchematicLibrary") (part "RC1005F106CS"))
    )
    (comp (ref "R254")
      (value "10.0M")
      (footprint "RES0402_REDUCED")
      (description "Resistor, 10.0M, 40V, 40mW, 1%, 0402, Implant-grade")
      (fields (field (name "MANUFACTURER") "Panasonic") (field (name "Comment") "WA20SM-1005F-NS62TRX"))
      (libsource (lib "GTXSchematicLibrary") (part "RC1005F106CS"))
    )
    (comp (ref "R255")
      (value "Zero")
      (footprint "Resistor:RES0402_REDUCED")
      (description "Resistor, Zero ohms, 40V, 40mW, 1%, 0402, Implant-grade")
      (fields (field (name "MANUFACTURER") "Panasonic") (field (name "Comment") "WAJ20PG-NS62TRX"))
      (libsource (lib "CELERO") (part "R_ZERO_0402"))
    )
    (comp (ref "R276")
      (value "1.00M")
      (footprint "Resistor:RES0402_REDUCED")
      (description "Resistor, 1.00M, 40V, 40mW, 1%, 0402, Implant-grade")
      (fields (field (name "MANUFACTURER") "Panasonic") (field (name "Comment") "WA20SM-1004F-NS62TRX"))
      (libsource (lib "GTXSchematicLibrary") (part "RC1005F106CS"))
    )
    (comp (ref "R277")
      (value "100")
      (footprint "Resistor:RES0402_REDUCED")
      (description "Resistor, 100 ohms, 1%, 50V, 0.1W, 0402")
      (fields (field (name "MANUFACTURER") "Panasonic") (field (name "Comment") "ERJ-2RKF1000X"))
      (libsource (lib "MPS") (part "ERJ-2GEJ106X"))
    )
    (comp (ref "R278")
      (value "1.00k")
      (footprint "Resistor:RES0402_REDUCED")
      (description "Resistor, 1.00k, 1%, 50V, 0.1W, 0402")
      (fields (field (name "MANUFACTURER") "Panasonic") (field (name "Comment") "ERJ-2RKF1001X"))
      (libsource (lib "MPS") (part "ERJ-2GEJ106X"))
    )
    (comp (ref "R279")
      (value "1.00M")
      (footprint "Resistor:RES0402_REDUCED")
      (description "Resistor, 1.00M, 40V, 40mW, 1%, 0402, Implant-grade")
      (fields (field (name "MANUFACTURER") "Panasonic") (field (name "Comment") "WA20SM-1004F-NS62TRX"))
      (libsource (lib "GTXSchematicLibrary") (part "RC1005F106CS"))
    )
    (comp (ref "R281")
      (value "DNP")
      (footprint "Resistor:RES0402_REDUCED")
      (description "Resistor, DNP, 0402")
      (libsource (lib "GTXSchematicLibrary") (part "RC1005F106CS"))
    )
    (comp (ref "R282")
      (value "DNP")
      (footprint "Resistor:RES0402_REDUCED")
      (description "Resistor, DNP, 0402")
      (libsource (lib "GTXSchematicLibrary") (part "RC1005F106CS"))
    )
    (comp (ref "R283")
      (value "DNP")
      (footprint "Resistor:RES0402_REDUCED")
      (description "Resistor, DNP, 0402")
      (libsource (lib "GTXSchematicLibrary") (part "RC1005F106CS"))
    )
    (comp (ref "R284")
      (value "DNP")
      (footprint "Resistor:RES0402_REDUCED")
      (description "Resistor, DNP, 0402")
      (libsource (lib "GTXSchematicLibrary") (part "RC1005F106CS"))
    )
    (comp (ref "R297")
      (value "DNP")
      (footprint "Resistor:RES0402_REDUCED")
      (description "Resistor, DNP, 0402")
      (libsource (lib "GTXSchematicLibrary") (part "RC1005F106CS"))
    )
    (comp (ref "R298")
      (value "10.0k")
      (footprint "Resistor:RES0402_REDUCED")
      (description "Resistor, 10.0k, 40V, 40mW, 1%, 0402, Implant-grade")
      (fields (field (name "MANUFACTURER") "Panasonic") (field (name "Comment") "WA20SM-1002F-NS62TRX"))
      (libsource (lib "GTXSchematicLibrary") (part "RC1005F106CS"))
    )
    (comp (ref "R299")
      (value "DNP")
      (footprint "Resistor:RES0402_REDUCED")
      (description "Resistor, DNP, 0402")
      (libsource (lib "GTXSchematicLibrary") (part "RC1005F106CS"))
    )
    (comp (ref "R300")
      (value "Zero")
      (footprint "Resistor:RES0402_REDUCED")
      (description "Resistor, Zero ohms, 40V, 40mW, 1%, 0402, Implant-grade")
      (fields (field (name "MANUFACTURER") "Panasonic") (field (name "Comment") "WAJ20PG-NS62TRX"))
      (libsource (lib "CELERO") (part "R_ZERO_0402"))
    )
    (comp (ref "R301")
      (value "TBD")
      (footprint "Resistor:RES0402_REDUCED")
      (description "Resistor, TBD, 0402")
      (fields (field (name "Comment") "Resistor. TBD, 0402"))
      (libsource (lib "GTXSchematicLibrary") (part "RC1005F106CS"))
    )
    (comp (ref "R302")
      (value "TBD")
      (footprint "Resistor:RES0402_REDUCED")
      (description "Resistor, TBD, 0402")
      (fields (field (name "Comment") "Resistor. TBD, 0402"))
      (libsource (lib "GTXSchematicLibrary") (part "RC1005F106CS"))
    )
    (comp (ref "R303")
      (value "100k")
      (footprint "Resistor:RES0402_REDUCED")
      (description "Resistor, 100k, 40V, 40mW, 1%, 0402, Implant-grade")
      (fields (field (name "MANUFACTURER") "Panasonic") (field (name "Comment") "WA20SM-1003F-NS62TRX"))
      (libsource (lib "GTXSchematicLibrary") (part "RC1005F106CS"))
    )
    (comp (ref "R304")
      (value "100k")
      (footprint "Resistor:RES0402_REDUCED")
      (description "Resistor, 100k, 40V, 40mW, 1%, 0402, Implant-grade")
      (fields (field (name "MANUFACTURER") "Panasonic") (field (name "Comment") "WA20SM-1003F-NS62TRX"))
      (libsource (lib "GTXSchematicLibrary") (part "RC1005F106CS"))
    )
    (comp (ref "R305")
      (value "TBD")
      (footprint "Resistor:RES0402_REDUCED")
      (description "Resistor, TBD, 0402")
      (fields (field (name "Comment") "Resistor. TBD, 0402"))
      (libsource (lib "GTXSchematicLibrary") (part "RC1005F106CS"))
    )
    (comp (ref "R306")
      (value "TBD")
      (footprint "Resistor:RES0402_REDUCED")
      (description "Resistor, TBD, 0402")
      (fields (field (name "Comment") "Resistor. TBD, 0402"))
      (libsource (lib "GTXSchematicLibrary") (part "RC1005F106CS"))
    )
    (comp (ref "R307")
      (value "Zero")
      (footprint "Resistor:RES0402_REDUCED")
      (description "Resistor, Zero ohms, 40V, 40mW, 1%, 0402, Implant-grade")
      (fields (field (name "MANUFACTURER") "Panasonic") (field (name "Comment") "WAJ20PG-NS62TRX"))
      (libsource (lib "CELERO") (part "R_ZERO_0402"))
    )
    (comp (ref "R308")
      (value "Zero")
      (footprint "Resistor:RES0402_REDUCED")
      (description "Resistor, Zero ohms, 40V, 40mW, 1%, 0402, Implant-grade")
      (fields (field (name "MANUFACTURER") "Panasonic") (field (name "Comment") "WAJ20PG-NS62TRX"))
      (libsource (lib "CELERO") (part "R_ZERO_0402"))
    )
    (comp (ref "R309")
      (value "10.0M")
      (footprint "RES0402_REDUCED")
      (description "Resistor, 10.0M, 40V, 40mW, 1%, 0402, Implant-grade")
      (fields (field (name "MANUFACTURER") "Panasonic") (field (name "Comment") "WA20SM-1005F-NS62TRX"))
      (libsource (lib "GTXSchematicLibrary") (part "RC1005F106CS"))
    )
    (comp (ref "R311")
      (value "1.00k")
      (footprint "Resistor:RES0402_REDUCED")
      (description "Resistor, 1.00k, 1%, 50V, 0.1W, 0402")
      (fields (field (name "MANUFACTURER") "Panasonic") (field (name "Comment") "ERJ-2RKF1001X"))
      (libsource (lib "MPS") (part "ERJ-2GEJ106X"))
    )
    (comp (ref "R312")
      (value "1.00k")
      (footprint "Resistor:RES0402_REDUCED")
      (description "Resistor, 1.00k, 1%, 50V, 0.1W, 0402")
      (fields (field (name "MANUFACTURER") "Panasonic") (field (name "Comment") "ERJ-2RKF1001X"))
      (libsource (lib "MPS") (part "ERJ-2GEJ106X"))
    )
    (comp (ref "R313")
      (value "1.00k")
      (footprint "Resistor:RES0402_REDUCED")
      (description "Resistor, 1.00k, 1%, 50V, 0.1W, 0402")
      (fields (field (name "MANUFACTURER") "Panasonic") (field (name "Comment") "ERJ-2RKF1001X"))
      (libsource (lib "MPS") (part "ERJ-2GEJ106X"))
    )
    (comp (ref "R314")
      (value "1.00k")
      (footprint "Resistor:RES0402_REDUCED")
      (description "Resistor, 1.00k, 1%, 50V, 0.1W, 0402")
      (fields (field (name "MANUFACTURER") "Panasonic") (field (name "Comment") "ERJ-2RKF1001X"))
      (libsource (lib "MPS") (part "ERJ-2GEJ106X"))
    )
    (comp (ref "R327")
      (value "1.00k")
      (footprint "Resistor:RES0402_REDUCED")
      (description "Resistor, 1.00k, 1%, 50V, 0.1W, 0402")
      (fields (field (name "MANUFACTURER") "Panasonic") (field (name "Comment") "ERJ-2RKF1001X"))
      (libsource (lib "MPS") (part "ERJ-2GEJ106X"))
    )
    (comp (ref "R331")
      (value "40.2")
      (footprint "Resistor:RES0402_REDUCED")
      (description "Resistor, 40.2 ohms, 50V, 100mW, 1%, 0402")
      (fields (field (name "MANUFACTURER") "Panasonic") (field (name "Comment") "ERJ-2RKF40R2X"))
      (libsource (lib "MPS") (part "ERJ-2GEJ106X"))
    )
    (comp (ref "R332")
      (value "40.2")
      (footprint "Resistor:RES0402_REDUCED")
      (description "Resistor, 40.2 ohms, 50V, 100mW, 1%, 0402")
      (fields (field (name "MANUFACTURER") "Panasonic") (field (name "Comment") "ERJ-2RKF40R2X"))
      (libsource (lib "MPS") (part "ERJ-2GEJ106X"))
    )
    (comp (ref "R333")
      (value "40.2")
      (footprint "Resistor:RES0402_REDUCED")
      (description "Resistor, 40.2 ohms, 50V, 100mW, 1%, 0402")
      (fields (field (name "MANUFACTURER") "Panasonic") (field (name "Comment") "ERJ-2RKF40R2X"))
      (libsource (lib "MPS") (part "ERJ-2GEJ106X"))
    )
    (comp (ref "R334")
      (value "40.2")
      (footprint "Resistor:RES0402_REDUCED")
      (description "Resistor, 40.2 ohms, 50V, 100mW, 1%, 0402")
      (fields (field (name "MANUFACTURER") "Panasonic") (field (name "Comment") "ERJ-2RKF40R2X"))
      (libsource (lib "MPS") (part "ERJ-2GEJ106X"))
    )
    (comp (ref "R347")
      (value "40.2")
      (footprint "Resistor:RES0402_REDUCED")
      (description "Resistor, 40.2 ohms, 50V, 100mW, 1%, 0402")
      (fields (field (name "MANUFACTURER") "Panasonic") (field (name "Comment") "ERJ-2RKF40R2X"))
      (libsource (lib "MPS") (part "ERJ-2GEJ106X"))
    )
    (comp (ref "R351")
      (value "10.0M")
      (footprint "RES0402_REDUCED")
      (description "Resistor, 10.0M, 40V, 40mW, 1%, 0402, Implant-grade")
      (fields (field (name "MANUFACTURER") "Panasonic") (field (name "Comment") "WA20SM-1005F-NS62TRX"))
      (libsource (lib "GTXSchematicLibrary") (part "RC1005F106CS"))
    )
    (comp (ref "R352")
      (value "10.0M")
      (footprint "RES0402_REDUCED")
      (description "Resistor, 10.0M, 40V, 40mW, 1%, 0402, Implant-grade")
      (fields (field (name "MANUFACTURER") "Panasonic") (field (name "Comment") "WA20SM-1005F-NS62TRX"))
      (libsource (lib "GTXSchematicLibrary") (part "RC1005F106CS"))
    )
    (comp (ref "R353")
      (value "10.0M")
      (footprint "RES0402_REDUCED")
      (description "Resistor, 10.0M, 40V, 40mW, 1%, 0402, Implant-grade")
      (fields (field (name "MANUFACTURER") "Panasonic") (field (name "Comment") "WA20SM-1005F-NS62TRX"))
      (libsource (lib "GTXSchematicLibrary") (part "RC1005F106CS"))
    )
    (comp (ref "R354")
      (value "10.0M")
      (footprint "RES0402_REDUCED")
      (description "Resistor, 10.0M, 40V, 40mW, 1%, 0402, Implant-grade")
      (fields (field (name "MANUFACTURER") "Panasonic") (field (name "Comment") "WA20SM-1005F-NS62TRX"))
      (libsource (lib "GTXSchematicLibrary") (part "RC1005F106CS"))
    )
    (comp (ref "R367")
      (value "10.0M")
      (footprint "RES0402_REDUCED")
      (description "Resistor, 10.0M, 40V, 40mW, 1%, 0402, Implant-grade")
      (fields (field (name "MANUFACTURER") "Panasonic") (field (name "Comment") "WA20SM-1005F-NS62TRX"))
      (libsource (lib "GTXSchematicLibrary") (part "RC1005F106CS"))
    )
    (comp (ref "R371")
      (value "2.00M")
      (footprint "Resistor:RES0402_REDUCED")
      (description "Resistor, 2.00M, 40V, 40mW, 1%, 0402, Implant-grade")
      (fields (field (name "MANUFACTURER") "Panasonic") (field (name "Comment") "WA20SM-2004F-NS62TRX"))
      (libsource (lib "GTXSchematicLibrary") (part "RC1005F106CS"))
    )
    (comp (ref "R372")
      (value "2.00M")
      (footprint "Resistor:RES0402_REDUCED")
      (description "Resistor, 2.00M, 40V, 40mW, 1%, 0402, Implant-grade")
      (fields (field (name "MANUFACTURER") "Panasonic") (field (name "Comment") "WA20SM-2004F-NS62TRX"))
      (libsource (lib "GTXSchematicLibrary") (part "RC1005F106CS"))
    )
    (comp (ref "R373")
      (value "2.00M")
      (footprint "Resistor:RES0402_REDUCED")
      (description "Resistor, 2.00M, 40V, 40mW, 1%, 0402, Implant-grade")
      (fields (field (name "MANUFACTURER") "Panasonic") (field (name "Comment") "WA20SM-2004F-NS62TRX"))
      (libsource (lib "GTXSchematicLibrary") (part "RC1005F106CS"))
    )
    (comp (ref "R374")
      (value "2.00M")
      (footprint "Resistor:RES0402_REDUCED")
      (description "Resistor, 2.00M, 40V, 40mW, 1%, 0402, Implant-grade")
      (fields (field (name "MANUFACTURER") "Panasonic") (field (name "Comment") "WA20SM-2004F-NS62TRX"))
      (libsource (lib "GTXSchematicLibrary") (part "RC1005F106CS"))
    )
    (comp (ref "R387")
      (value "2.00M")
      (footprint "Resistor:RES0402_REDUCED")
      (description "Resistor, 2.00M, 40V, 40mW, 1%, 0402, Implant-grade")
      (fields (field (name "MANUFACTURER") "Panasonic") (field (name "Comment") "WA20SM-2004F-NS62TRX"))
      (libsource (lib "GTXSchematicLibrary") (part "RC1005F106CS"))
    )
    (comp (ref "R501")
      (value "402")
      (footprint "Resistor:RES0805_L_REDUCED")
      (description "Resistor, 402 ohms, 40V, 40mW, 1%, 0805, Implant-grade")
      (fields (field (name "MANUFACTURER") "Panasonic") (field (name "Comment") "WA20SM-4020F-NS62TRX"))
      (libsource (lib "GTXSchematicLibrary") (part "RC1005F106CS"))
    )
    (comp (ref "R502")
      (value "1.00M")
      (footprint "Resistor:RES0402_REDUCED")
      (description "Resistor, 1.00M, 40V, 40mW, 1%, 0402, Implant-grade")
      (fields (field (name "MANUFACTURER") "Panasonic") (field (name "Comment") "WA20SM-1004F-NS62TRX"))
      (libsource (lib "GTXSchematicLibrary") (part "RC1005F106CS"))
    )
    (comp (ref "R503")
      (value "1.00M")
      (footprint "Resistor:RES0402_REDUCED")
      (description "Resistor, 1.00M, 40V, 40mW, 1%, 0402, Implant-grade")
      (fields (field (name "MANUFACTURER") "Panasonic") (field (name "Comment") "WA20SM-1004F-NS62TRX"))
      (libsource (lib "GTXSchematicLibrary") (part "RC1005F106CS"))
    )
    (comp (ref "R504")
      (value "1.00M")
      (footprint "Resistor:RES0402_REDUCED")
      (description "Resistor, 1.00M, 40V, 40mW, 1%, 0402, Implant-grade")
      (fields (field (name "MANUFACTURER") "Panasonic") (field (name "Comment") "WA20SM-1004F-NS62TRX"))
      (libsource (lib "GTXSchematicLibrary") (part "RC1005F106CS"))
    )
    (comp (ref "R505")
      (value "49.9")
      (footprint "Resistor:RES0805_L_REDUCED")
      (description "Resistor, 49.9 ohms, 125V, 200mW, 1%, 0805, Implant-grade")
      (fields (field (name "MANUFACTURER") "Panasonic") (field (name "Comment") "WA86SM-49R9F-NS62TRX"))
      (libsource (lib "GTXSchematicLibrary") (part "RC1005F106CS"))
    )
    (comp (ref "R506")
      (value "1.00M")
      (footprint "Resistor:RES0402_REDUCED")
      (description "Resistor, 1.00M, 40V, 40mW, 1%, 0402, Implant-grade")
      (fields (field (name "MANUFACTURER") "Panasonic") (field (name "Comment") "WA20SM-1004F-NS62TRX"))
      (libsource (lib "GTXSchematicLibrary") (part "RC1005F106CS"))
    )
    (comp (ref "R507")
      (value "1.00M")
      (footprint "Resistor:RES0402_REDUCED")
      (description "Resistor, 1.00M, 40V, 40mW, 1%, 0402, Implant-grade")
      (fields (field (name "MANUFACTURER") "Panasonic") (field (name "Comment") "WA20SM-1004F-NS62TRX"))
      (libsource (lib "GTXSchematicLibrary") (part "RC1005F106CS"))
    )
    (comp (ref "R508")
      (value "100k")
      (footprint "Resistor:RES0402_REDUCED")
      (description "Resistor, 100k, 40V, 40mW, 1%, 0402, Implant-grade")
      (fields (field (name "MANUFACTURER") "Panasonic") (field (name "Comment") "WA20SM-1003F-NS62TRX"))
      (libsource (lib "GTXSchematicLibrary") (part "RC1005F106CS"))
    )
    (comp (ref "R509")
      (value "1.00M")
      (footprint "Resistor:RES0402_REDUCED")
      (description "Resistor, 1.00M, 40V, 40mW, 1%, 0402, Implant-grade")
      (fields (field (name "MANUFACTURER") "Panasonic") (field (name "Comment") "WA20SM-1004F-NS62TRX"))
      (libsource (lib "GTXSchematicLibrary") (part "RC1005F106CS"))
    )
    (comp (ref "R510")
      (value "1.00M")
      (footprint "Resistor:RES0402_REDUCED")
      (description "Resistor, 1.00M, 40V, 40mW, 1%, 0402, Implant-grade")
      (fields (field (name "MANUFACTURER") "Panasonic") (field (name "Comment") "WA20SM-1004F-NS62TRX"))
      (libsource (lib "GTXSchematicLibrary") (part "RC1005F106CS"))
    )
    (comp (ref "R511")
      (value "402")
      (footprint "Resistor:RES0805_L_REDUCED")
      (description "Resistor, 402 ohms, 40V, 40mW, 1%, 0805, Implant-grade")
      (fields (field (name "MANUFACTURER") "Panasonic") (field (name "Comment") "WA20SM-4020F-NS62TRX"))
      (libsource (lib "GTXSchematicLibrary") (part "RC1005F106CS"))
    )
    (comp (ref "R512")
      (value "1.00M")
      (footprint "Resistor:RES0402_REDUCED")
      (description "Resistor, 1.00M, 40V, 40mW, 1%, 0402, Implant-grade")
      (fields (field (name "MANUFACTURER") "Panasonic") (field (name "Comment") "WA20SM-1004F-NS62TRX"))
      (libsource (lib "GTXSchematicLibrary") (part "RC1005F106CS"))
    )
    (comp (ref "R513")
      (value "1.00M")
      (footprint "Resistor:RES0402_REDUCED")
      (description "Resistor, 1.00M, 40V, 40mW, 1%, 0402, Implant-grade")
      (fields (field (name "MANUFACTURER") "Panasonic") (field (name "Comment") "WA20SM-1004F-NS62TRX"))
      (libsource (lib "GTXSchematicLibrary") (part "RC1005F106CS"))
    )
    (comp (ref "R514")
      (value "1.00M")
      (footprint "Resistor:RES0402_REDUCED")
      (description "Resistor, 1.00M, 40V, 40mW, 1%, 0402, Implant-grade")
      (fields (field (name "MANUFACTURER") "Panasonic") (field (name "Comment") "WA20SM-1004F-NS62TRX"))
      (libsource (lib "GTXSchematicLibrary") (part "RC1005F106CS"))
    )
    (comp (ref "R515")
      (value "1.00M")
      (footprint "Resistor:RES0402_REDUCED")
      (description "Resistor, 1.00M, 40V, 40mW, 1%, 0402, Implant-grade")
      (fields (field (name "MANUFACTURER") "Panasonic") (field (name "Comment") "WA20SM-1004F-NS62TRX"))
      (libsource (lib "GTXSchematicLibrary") (part "RC1005F106CS"))
    )
    (comp (ref "R516")
      (value "150k")
      (footprint "Resistor:RES0402_REDUCED")
      (description "Resistor, 150k, 40V, 40mW, 1%, 0402, Implant-grade")
      (fields (field (name "MANUFACTURER") "Panasonic") (field (name "Comment") "WA20SM-1503F-NS62TRX"))
      (libsource (lib "GTXSchematicLibrary") (part "RC1005F106CS"))
    )
    (comp (ref "R517")
      (value "1.00M")
      (footprint "Resistor:RES0402_REDUCED")
      (description "Resistor, 1.00M, 40V, 40mW, 1%, 0402, Implant-grade")
      (fields (field (name "MANUFACTURER") "Panasonic") (field (name "Comment") "WA20SM-1004F-NS62TRX"))
      (libsource (lib "GTXSchematicLibrary") (part "RC1005F106CS"))
    )
    (comp (ref "R518")
      (value "1.00M")
      (footprint "Resistor:RES0402_REDUCED")
      (description "Resistor, 1.00M, 40V, 40mW, 1%, 0402, Implant-grade")
      (fields (field (name "MANUFACTURER") "Panasonic") (field (name "Comment") "WA20SM-1004F-NS62TRX"))
      (libsource (lib "GTXSchematicLibrary") (part "RC1005F106CS"))
    )
    (comp (ref "R519")
      (value "1.00M")
      (footprint "Resistor:RES0402_REDUCED")
      (description "Resistor, 1.00M, 40V, 40mW, 1%, 0402, Implant-grade")
      (fields (field (name "MANUFACTURER") "Panasonic") (field (name "Comment") "WA20SM-1004F-NS62TRX"))
      (libsource (lib "GTXSchematicLibrary") (part "RC1005F106CS"))
    )
    (comp (ref "R520")
      (value "40.2k")
      (footprint "Resistor:RES0402_REDUCED")
      (description "Resistor, 40.2k, 40V, 40mW, 1%, 0402, Implant-grade")
      (fields (field (name "MANUFACTURER") "Panasonic") (field (name "Comment") "WA20SM-4022F-NS62TRX"))
      (libsource (lib "GTXSchematicLibrary") (part "RC1005F106CS"))
    )
    (comp (ref "R521")
      (value "1.00M")
      (footprint "Resistor:RES0402_REDUCED")
      (description "Resistor, 1.00M, 40V, 40mW, 1%, 0402, Implant-grade")
      (fields (field (name "MANUFACTURER") "Panasonic") (field (name "Comment") "WA20SM-1004F-NS62TRX"))
      (libsource (lib "GTXSchematicLibrary") (part "RC1005F106CS"))
    )
    (comp (ref "R522")
      (value "100k")
      (footprint "Resistor:RES0402_REDUCED")
      (description "Resistor, 100k, 40V, 40mW, 1%, 0402, Implant-grade")
      (fields (field (name "MANUFACTURER") "Panasonic") (field (name "Comment") "WA20SM-1003F-NS62TRX"))
      (libsource (lib "GTXSchematicLibrary") (part "RC1005F106CS"))
    )
    (comp (ref "R523")
      (value "2.00M")
      (footprint "Resistor:RES0402_REDUCED")
      (description "Resistor, 2.00M, 40V, 40mW, 1%, 0402, Implant-grade")
      (fields (field (name "MANUFACTURER") "Panasonic") (field (name "Comment") "WA20SM-2004F-NS62TRX"))
      (libsource (lib "GTXSchematicLibrary") (part "RC1005F106CS"))
    )
    (comp (ref "R524")
      (value "DNP")
      (footprint "Resistor:RES0402_REDUCED")
      (description "Resistor, DNP, 0402")
      (libsource (lib "GTXSchematicLibrary") (part "RC1005F106CS"))
    )
    (comp (ref "R525")
      (value "1.00M")
      (footprint "Resistor:RES0402_REDUCED")
      (description "Resistor, 1.00M, 40V, 40mW, 1%, 0402, Implant-grade")
      (fields (field (name "MANUFACTURER") "Panasonic") (field (name "Comment") "WA20SM-1004F-NS62TRX"))
      (libsource (lib "GTXSchematicLibrary") (part "RC1005F106CS"))
    )
    (comp (ref "R526")
      (value "1.00M")
      (footprint "Resistor:RES0402_REDUCED")
      (description "Resistor, 1.00M, 40V, 40mW, 1%, 0402, Implant-grade")
      (fields (field (name "MANUFACTURER") "Panasonic") (field (name "Comment") "WA20SM-1004F-NS62TRX"))
      (libsource (lib "GTXSchematicLibrary") (part "RC1005F106CS"))
    )
    (comp (ref "R527")
      (value "DNP")
      (footprint "Resistor:RES0402_REDUCED")
      (description "Resistor, DNP, 0402")
      (libsource (lib "GTXSchematicLibrary") (part "RC1005F106CS"))
    )
    (comp (ref "R528")
      (value "402")
      (footprint "Resistor:RES0805_L_REDUCED")
      (description "Resistor, 402 ohms, 40V, 40mW, 1%, 0805, Implant-grade")
      (fields (field (name "MANUFACTURER") "Panasonic") (field (name "Comment") "WA20SM-4020F-NS62TRX"))
      (libsource (lib "GTXSchematicLibrary") (part "RC1005F106CS"))
    )
    (comp (ref "R529")
      (value "DNP")
      (footprint "Resistor:RES0402_REDUCED")
      (description "Resistor, DNP, 0402")
      (libsource (lib "GTXSchematicLibrary") (part "RC1005F106CS"))
    )
    (comp (ref "R530")
      (value "DNP")
      (footprint "Resistor:RES0402_REDUCED")
      (description "Resistor, DNP, 0402")
      (libsource (lib "GTXSchematicLibrary") (part "RC1005F106CS"))
    )
    (comp (ref "R531")
      (value "Zero")
      (footprint "Resistor:RES0402_REDUCED")
      (description "Resistor, Zero ohms, 40V, 40mW, 1%, 0402, Implant-grade")
      (fields (field (name "MANUFACTURER") "Panasonic") (field (name "Comment") "WAJ20PG-NS62TRX"))
      (libsource (lib "CELERO") (part "R_ZERO_0402"))
    )
    (comp (ref "SW901")
      (value "PB")
      (footprint "CK_PTS647")
      (description "Pushbutton, NO-MOM, 12V, 0.05A, SMT")
      (fields (field (name "MANUFACTURER") "C&K"))
      (libsource (lib "Mechanical") (part "PTS 647 SN50 SMTR2 LFS"))
    )
    (comp (ref "TP1")
      (value "Test Point")
      (footprint "Mechanical:testpad_0.9mm")
      (description "Test pad, 0.90mm circular pad")
      (libsource (lib "CB_Altium_Library") (part "Test Point"))
    )
    (comp (ref "TP2")
      (value "Test Point")
      (footprint "Mechanical:testpad_0.9mm")
      (description "Test pad, 0.90mm circular pad")
      (libsource (lib "CB_Altium_Library") (part "Test Point"))
    )
    (comp (ref "TP3")
      (value "Test Point")
      (footprint "Mechanical:testpad_0.9mm")
      (description "Test pad, 0.90mm circular pad")
      (libsource (lib "CB_Altium_Library") (part "Test Point"))
    )
    (comp (ref "TP4")
      (value "Test Point")
      (footprint "Mechanical:testpad_0.9mm")
      (description "Test pad, 0.90mm circular pad")
      (libsource (lib "CB_Altium_Library") (part "Test Point"))
    )
    (comp (ref "TP5")
      (value "Test Point")
      (footprint "Mechanical:testpad_0.9mm")
      (description "Test pad, 0.90mm circular pad")
      (libsource (lib "CB_Altium_Library") (part "Test Point"))
    )
    (comp (ref "TP6")
      (value "Test Point")
      (footprint "Mechanical:testpad_0.9mm")
      (description "Test pad, 0.90mm circular pad")
      (libsource (lib "CB_Altium_Library") (part "Test Point"))
    )
    (comp (ref "TP7")
      (value "Test Point")
      (footprint "Mechanical:testpad_0.9mm")
      (description "Test pad, 0.90mm circular pad")
      (libsource (lib "CB_Altium_Library") (part "Test Point"))
    )
    (comp (ref "TP8")
      (value "Test Point")
      (footprint "Mechanical:testpad_0.9mm")
      (description "Test pad, 0.90mm circular pad")
      (libsource (lib "CB_Altium_Library") (part "Test Point"))
    )
    (comp (ref "TP9")
      (value "Test Point")
      (footprint "Mechanical:testpad_0.9mm")
      (description "Test pad, 0.90mm circular pad")
      (libsource (lib "CB_Altium_Library") (part "Test Point"))
    )
    (comp (ref "TP10")
      (value "Test Point")
      (footprint "Mechanical:testpad_0.9mm")
      (description "Test pad, 0.90mm circular pad")
      (libsource (lib "CB_Altium_Library") (part "Test Point"))
    )
    (comp (ref "TP11")
      (value "Test Point")
      (footprint "Mechanical:testpad_0.9mm")
      (description "Test pad, 0.90mm circular pad")
      (libsource (lib "CB_Altium_Library") (part "Test Point"))
    )
    (comp (ref "TP12")
      (value "Test Point")
      (footprint "Mechanical:testpad_0.9mm")
      (description "Test pad, 0.90mm circular pad")
      (libsource (lib "CB_Altium_Library") (part "Test Point"))
    )
    (comp (ref "TP13")
      (value "Test Point")
      (footprint "Mechanical:testpad_0.9mm")
      (description "Test pad, 0.90mm circular pad")
      (libsource (lib "CB_Altium_Library") (part "Test Point"))
    )
    (comp (ref "TP14")
      (value "Test Point")
      (footprint "Mechanical:testpad_0.9mm")
      (description "Test pad, 0.90mm circular pad")
      (libsource (lib "CB_Altium_Library") (part "Test Point"))
    )
    (comp (ref "TP15")
      (value "Test Point")
      (footprint "Mechanical:testpad_0.9mm")
      (description "Test pad, 0.90mm circular pad")
      (libsource (lib "CB_Altium_Library") (part "Test Point"))
    )
    (comp (ref "TP16")
      (value "Test Point")
      (footprint "Mechanical:testpad_0.9mm")
      (description "Test pad, 0.90mm circular pad")
      (libsource (lib "CB_Altium_Library") (part "Test Point"))
    )
    (comp (ref "TP17")
      (value "Test Point")
      (footprint "Mechanical:testpad_0.9mm")
      (description "Test pad, 0.90mm circular pad")
      (libsource (lib "CB_Altium_Library") (part "Test Point"))
    )
    (comp (ref "TP18")
      (value "Test Point")
      (footprint "Mechanical:testpad_0.9mm")
      (description "Test pad, 0.90mm circular pad")
      (libsource (lib "CB_Altium_Library") (part "Test Point"))
    )
    (comp (ref "TP19")
      (value "Test Point")
      (footprint "Mechanical:testpad_0.9mm")
      (description "Test pad, 0.90mm circular pad")
      (libsource (lib "CB_Altium_Library") (part "Test Point"))
    )
    (comp (ref "TP20")
      (value "Test Point")
      (footprint "Mechanical:testpad_0.9mm")
      (description "Test pad, 0.90mm circular pad")
      (libsource (lib "CB_Altium_Library") (part "Test Point"))
    )
    (comp (ref "TP21")
      (value "Test Point")
      (footprint "Mechanical:testpad_0.9mm")
      (description "Test pad, 0.90mm circular pad")
      (libsource (lib "CB_Altium_Library") (part "Test Point"))
    )
    (comp (ref "TP22")
      (value "Test Point")
      (footprint "Mechanical:testpad_0.9mm")
      (description "Test pad, 0.90mm circular pad")
      (libsource (lib "CB_Altium_Library") (part "Test Point"))
    )
    (comp (ref "TP23")
      (value "Test Point")
      (footprint "Mechanical:testpad_0.9mm")
      (description "Test pad, 0.90mm circular pad")
      (libsource (lib "CB_Altium_Library") (part "Test Point"))
    )
    (comp (ref "TP24")
      (value "Test Point")
      (footprint "Mechanical:testpad_0.9mm")
      (description "Test pad, 0.90mm circular pad")
      (libsource (lib "CB_Altium_Library") (part "Test Point"))
    )
    (comp (ref "TP25")
      (value "Test Point")
      (footprint "Mechanical:testpad_0.9mm")
      (description "Test pad, 0.90mm circular pad")
      (libsource (lib "CB_Altium_Library") (part "Test Point"))
    )
    (comp (ref "TP26")
      (value "Test Point")
      (footprint "Mechanical:testpad_0.9mm")
      (description "Test pad, 0.90mm circular pad")
      (libsource (lib "CB_Altium_Library") (part "Test Point"))
    )
    (comp (ref "TP27")
      (value "Test Point")
      (footprint "Mechanical:testpad_0.9mm")
      (description "Test pad, 0.90mm circular pad")
      (libsource (lib "CB_Altium_Library") (part "Test Point"))
    )
    (comp (ref "TP28")
      (value "Test Point")
      (footprint "Mechanical:testpad_0.9mm")
      (description "Test pad, 0.90mm circular pad")
      (libsource (lib "CB_Altium_Library") (part "Test Point"))
    )
    (comp (ref "TP29")
      (value "Test Point")
      (footprint "Mechanical:testpad_0.9mm")
      (description "Test pad, 0.90mm circular pad")
      (libsource (lib "CB_Altium_Library") (part "Test Point"))
    )
    (comp (ref "TP30")
      (value "Test Point")
      (footprint "Mechanical:testpad_0.9mm")
      (description "Test pad, 0.90mm circular pad")
      (libsource (lib "CB_Altium_Library") (part "Test Point"))
    )
    (comp (ref "TP31")
      (value "Test Point")
      (footprint "Mechanical:testpad_0.9mm")
      (description "Test pad, 0.90mm circular pad")
      (libsource (lib "CB_Altium_Library") (part "Test Point"))
    )
    (comp (ref "TP32")
      (value "Test Point")
      (footprint "Mechanical:testpad_0.9mm")
      (description "Test pad, 0.90mm circular pad")
      (libsource (lib "CB_Altium_Library") (part "Test Point"))
    )
    (comp (ref "TP33")
      (value "Test Point")
      (footprint "Mechanical:testpad_0.9mm")
      (description "Test pad, 0.90mm circular pad")
      (libsource (lib "CB_Altium_Library") (part "Test Point"))
    )
    (comp (ref "TP34")
      (value "Test Point")
      (footprint "Mechanical:testpad_0.9mm")
      (description "Test pad, 0.90mm circular pad")
      (libsource (lib "CB_Altium_Library") (part "Test Point"))
    )
    (comp (ref "TP35")
      (value "Test Point")
      (footprint "Mechanical:testpad_0.9mm")
      (description "Test pad, 0.90mm circular pad")
      (libsource (lib "CB_Altium_Library") (part "Test Point"))
    )
    (comp (ref "TP36")
      (value "Test Point")
      (footprint "Mechanical:testpad_0.9mm")
      (description "Test pad, 0.90mm circular pad")
      (libsource (lib "CB_Altium_Library") (part "Test Point"))
    )
    (comp (ref "TP37")
      (value "Test Point")
      (footprint "Mechanical:testpad_0.9mm")
      (description "Test pad, 0.90mm circular pad")
      (libsource (lib "CB_Altium_Library") (part "Test Point"))
    )
    (comp (ref "TP38")
      (value "Test Point")
      (footprint "Mechanical:testpad_0.9mm")
      (description "Test pad, 0.90mm circular pad")
      (libsource (lib "CB_Altium_Library") (part "Test Point"))
    )
    (comp (ref "TP39")
      (value "Test Point")
      (footprint "Mechanical:testpad_0.9mm")
      (description "Test pad, 0.90mm circular pad")
      (libsource (lib "CB_Altium_Library") (part "Test Point"))
    )
    (comp (ref "TP40")
      (value "Test Point")
      (footprint "Mechanical:testpad_0.9mm")
      (description "Test pad, 0.90mm circular pad")
      (libsource (lib "CB_Altium_Library") (part "Test Point"))
    )
    (comp (ref "TP41")
      (value "Test Point")
      (footprint "Mechanical:testpad_0.9mm")
      (description "Test pad, 0.90mm circular pad")
      (libsource (lib "CB_Altium_Library") (part "Test Point"))
    )
    (comp (ref "TP42")
      (value "Test Point")
      (footprint "Mechanical:testpad_0.9mm")
      (description "Test pad, 0.90mm circular pad")
      (libsource (lib "CB_Altium_Library") (part "Test Point"))
    )
    (comp (ref "TP43")
      (value "Test Point")
      (footprint "Mechanical:testpad_0.9mm")
      (description "Test pad, 0.90mm circular pad")
      (libsource (lib "CB_Altium_Library") (part "Test Point"))
    )
    (comp (ref "TP44")
      (value "Test Point")
      (footprint "Mechanical:testpad_0.9mm")
      (description "Test pad, 0.90mm circular pad")
      (libsource (lib "CB_Altium_Library") (part "Test Point"))
    )
    (comp (ref "TP45")
      (value "Test Point")
      (footprint "Mechanical:testpad_0.9mm")
      (description "Test pad, 0.90mm circular pad")
      (libsource (lib "CB_Altium_Library") (part "Test Point"))
    )
    (comp (ref "TP46")
      (value "Test Point")
      (footprint "Mechanical:testpad_0.9mm")
      (description "Test pad, 0.90mm circular pad")
      (libsource (lib "CB_Altium_Library") (part "Test Point"))
    )
    (comp (ref "TP47")
      (value "Test Point")
      (footprint "Mechanical:testpad_0.9mm")
      (description "Test pad, 0.90mm circular pad")
      (libsource (lib "CB_Altium_Library") (part "Test Point"))
    )
    (comp (ref "TP48")
      (value "Test Point")
      (footprint "Mechanical:testpad_0.9mm")
      (description "Test pad, 0.90mm circular pad")
      (libsource (lib "CB_Altium_Library") (part "Test Point"))
    )
    (comp (ref "TP49")
      (value "Test Point")
      (footprint "Mechanical:testpad_0.9mm")
      (description "Test pad, 0.90mm circular pad")
      (libsource (lib "CB_Altium_Library") (part "Test Point"))
    )
    (comp (ref "TP81")
      (value "Test Point")
      (footprint "Mechanical:testpad_0.9mm")
      (description "Test pad, 0.90mm circular pad")
      (libsource (lib "CB_Altium_Library") (part "Test Point"))
    )
    (comp (ref "TP82")
      (value "Test Point")
      (footprint "Mechanical:testpad_0.9mm")
      (description "Test pad, 0.90mm circular pad")
      (libsource (lib "CB_Altium_Library") (part "Test Point"))
    )
    (comp (ref "TP83")
      (value "Test Point")
      (footprint "Mechanical:testpad_0.9mm")
      (description "Test pad, 0.90mm circular pad")
      (libsource (lib "CB_Altium_Library") (part "Test Point"))
    )
    (comp (ref "TP84")
      (value "Test Point")
      (footprint "Mechanical:testpad_0.9mm")
      (description "Test pad, 0.90mm circular pad")
      (libsource (lib "CB_Altium_Library") (part "Test Point"))
    )
    (comp (ref "TP85")
      (value "Test Point")
      (footprint "Mechanical:testpad_0.9mm")
      (description "Test pad, 0.90mm circular pad")
      (libsource (lib "CB_Altium_Library") (part "Test Point"))
    )
    (comp (ref "TP86")
      (value "Test Point")
      (footprint "Mechanical:testpad_0.9mm")
      (description "Test pad, 0.90mm circular pad")
      (libsource (lib "CB_Altium_Library") (part "Test Point"))
    )
    (comp (ref "TP90")
      (value "Test Point")
      (footprint "Mechanical:testpad_0.9mm")
      (description "Test pad, 0.90mm circular pad")
      (libsource (lib "CB_Altium_Library") (part "Test Point"))
    )
    (comp (ref "TP91")
      (value "Test Point")
      (footprint "Mechanical:testpad_0.9mm")
      (description "Test pad, 0.90mm circular pad")
      (libsource (lib "CB_Altium_Library") (part "Test Point"))
    )
    (comp (ref "TP92")
      (value "Test Point")
      (footprint "Mechanical:testpad_0.9mm")
      (description "Test pad, 0.90mm circular pad")
      (libsource (lib "CB_Altium_Library") (part "Test Point"))
    )
    (comp (ref "TP93")
      (value "Test Point")
      (footprint "Mechanical:testpad_0.9mm")
      (description "Test pad, 0.90mm circular pad")
      (libsource (lib "CB_Altium_Library") (part "Test Point"))
    )
    (comp (ref "TP94")
      (value "Test Point")
      (footprint "Mechanical:testpad_0.9mm")
      (description "Test pad, 0.90mm circular pad")
      (libsource (lib "CB_Altium_Library") (part "Test Point"))
    )
    (comp (ref "TP95")
      (value "Test Point")
      (footprint "Mechanical:testpad_0.9mm")
      (description "Test pad, 0.90mm circular pad")
      (libsource (lib "CB_Altium_Library") (part "Test Point"))
    )
    (comp (ref "TP96")
      (value "Test Point")
      (footprint "Mechanical:testpad_0.9mm")
      (description "Test pad, 0.90mm circular pad")
      (libsource (lib "CB_Altium_Library") (part "Test Point"))
    )
    (comp (ref "TP97")
      (value "Test Point")
      (footprint "Mechanical:testpad_0.9mm")
      (description "Test pad, 0.90mm circular pad")
      (libsource (lib "CB_Altium_Library") (part "Test Point"))
    )
    (comp (ref "TP98")
      (value "Test Point")
      (footprint "Mechanical:testpad_0.9mm")
      (description "Test pad, 0.90mm circular pad")
      (libsource (lib "CB_Altium_Library") (part "Test Point"))
    )
    (comp (ref "TP99")
      (value "Test Point")
      (footprint "Mechanical:testpad_0.9mm")
      (description "Test pad, 0.90mm circular pad")
      (libsource (lib "CB_Altium_Library") (part "Test Point"))
    )
    (comp (ref "TP301")
      (value "Test Point")
      (footprint "Mechanical:testpad_0.9mm")
      (description "Test pad, 0.90mm circular pad")
      (libsource (lib "CB_Altium_Library") (part "Test Point"))
    )
    (comp (ref "TP303")
      (value "Test Point")
      (footprint "Mechanical:testpad_0.9mm")
      (description "Test pad, 0.90mm circular pad")
      (libsource (lib "CB_Altium_Library") (part "Test Point"))
    )
    (comp (ref "TP304")
      (value "Test Point")
      (footprint "Mechanical:testpad_0.9mm")
      (description "Test pad, 0.90mm circular pad")
      (libsource (lib "CB_Altium_Library") (part "Test Point"))
    )
    (comp (ref "TP305")
      (value "Test Point")
      (footprint "Mechanical:testpad_0.9mm")
      (description "Test pad, 0.90mm circular pad")
      (libsource (lib "CB_Altium_Library") (part "Test Point"))
    )
    (comp (ref "TP306")
      (value "Test Point")
      (footprint "Mechanical:testpad_0.9mm")
      (description "Test pad, 0.90mm circular pad")
      (libsource (lib "CB_Altium_Library") (part "Test Point"))
    )
    (comp (ref "TP307")
      (value "Test Point")
      (footprint "Mechanical:testpad_0.9mm")
      (description "Test pad, 0.90mm circular pad")
      (libsource (lib "CB_Altium_Library") (part "Test Point"))
    )
    (comp (ref "TP501")
      (value "Test Point")
      (footprint "Mechanical:testpad_0.9mm")
      (description "Test pad, 0.90mm circular pad")
      (libsource (lib "CB_Altium_Library") (part "Test Point"))
    )
    (comp (ref "TP502")
      (value "Test Point")
      (footprint "Mechanical:testpad_0.9mm")
      (description "Test pad, 0.90mm circular pad")
      (libsource (lib "CB_Altium_Library") (part "Test Point"))
    )
    (comp (ref "TP503")
      (value "Test Point")
      (footprint "Mechanical:testpad_0.9mm")
      (description "Test pad, 0.90mm circular pad")
      (libsource (lib "CB_Altium_Library") (part "Test Point"))
    )
    (comp (ref "TP504")
      (value "Test Point")
      (footprint "Mechanical:testpad_0.9mm")
      (description "Test pad, 0.90mm circular pad")
      (libsource (lib "CB_Altium_Library") (part "Test Point"))
    )
    (comp (ref "TP505")
      (value "Test Point")
      (footprint "Mechanical:testpad_0.9mm")
      (description "Test pad, 0.90mm circular pad")
      (libsource (lib "CB_Altium_Library") (part "Test Point"))
    )
    (comp (ref "TP506")
      (value "Test Point")
      (footprint "Mechanical:testpad_0.9mm")
      (description "Test pad, 0.90mm circular pad")
      (libsource (lib "CB_Altium_Library") (part "Test Point"))
    )
    (comp (ref "TP507")
      (value "Test Point")
      (footprint "Mechanical:testpad_0.9mm")
      (description "Test pad, 0.90mm circular pad")
      (libsource (lib "CB_Altium_Library") (part "Test Point"))
    )
    (comp (ref "TP508")
      (value "Test Point")
      (footprint "Mechanical:testpad_0.9mm")
      (description "Test pad, 0.90mm circular pad")
      (libsource (lib "CB_Altium_Library") (part "Test Point"))
    )
    (comp (ref "TP509")
      (value "Test Point")
      (footprint "Mechanical:testpad_0.9mm")
      (description "Test pad, 0.90mm circular pad")
      (libsource (lib "CB_Altium_Library") (part "Test Point"))
    )
    (comp (ref "TP510")
      (value "Test Point")
      (footprint "Mechanical:testpad_0.9mm")
      (description "Test pad, 0.90mm circular pad")
      (libsource (lib "CB_Altium_Library") (part "Test Point"))
    )
    (comp (ref "TP511")
      (value "Test Point")
      (footprint "Mechanical:testpad_0.9mm")
      (description "Test pad, 0.90mm circular pad")
      (libsource (lib "CB_Altium_Library") (part "Test Point"))
    )
    (comp (ref "TP512")
      (value "Test Point")
      (footprint "Mechanical:testpad_0.9mm")
      (description "Test pad, 0.90mm circular pad")
      (libsource (lib "CB_Altium_Library") (part "Test Point"))
    )
    (comp (ref "U1")
      (value "AP7354D-33FS4-7")
      (footprint "DIODESINC_X2-DFN1010-4 (Type B)_REDUCED")
      (description "LDO Regulator, 3.3V, Shutdown, DFN1010-4")
      (fields (field (name "MANUFACTURER") "Diodes Inc"))
      (libsource (lib "CB_Altium_Library") (part "AP7354D"))
    )
    (comp (ref "U2")
      (value "LTC4065LEDC#TRMPBF")
      (footprint "LT_DC6")
      (description "Charge Controller, 4.2V, 250mA, DFN-6")
      (fields (field (name "MANUFACTURER") "Linear Technology"))
      (libsource (lib "CB_Altium_Library") (part "LTC4065"))
    )
    (comp (ref "U3")
      (value "TLV4021R1YKAR")
      (footprint "TI_YKA0004")
      (description "Comparator, 1.2V Reference, Open-drain, BGA-4")
      (fields (field (name "MANUFACTURER") "Texas Instruments"))
      (libsource (lib "CB_Altium_Library") (part "TLV4021R1YKAR"))
    )
    (comp (ref "U4")
      (value "LTC4065LEDC#TRMPBF")
      (footprint "LT_DC6")
      (description "Charge Controller, 4.2V, 250mA, DFN-6")
      (fields (field (name "MANUFACTURER") "Linear Technology"))
      (libsource (lib "CB_Altium_Library") (part "LTC4065"))
    )
    (comp (ref "U5")
      (value "TLV4021R1YKAR")
      (footprint "TI_YKA0004")
      (description "Comparator, 1.2V Reference, Open-drain, BGA-4")
      (fields (field (name "MANUFACTURER") "Texas Instruments"))
      (libsource (lib "CB_Altium_Library") (part "TLV4021R1YKAR"))
    )
    (comp (ref "U6")
      (value "AD8505ACBZ")
      (footprint "CB_Library:AD_CB-6-7(WLCSP6)")
      (description "Op Amp, Rail-to-Rail, 95kHz, WLCSP-6")
      (fields (field (name "MANUFACTURER") "Analog Devices"))
      (libsource (lib "CB_Altium_Library") (part "AD8505ACBZ"))
    )
    (comp (ref "U7")
      (value "AD8505ACBZ")
      (footprint "CB_Library:AD_CB-6-7(WLCSP6)")
      (description "Op Amp, Rail-to-Rail, 95kHz, WLCSP-6")
      (fields (field (name "MANUFACTURER") "Analog Devices"))
      (libsource (lib "CB_Altium_Library") (part "AD8505ACBZ"))
    )
    (comp (ref "U8")
      (value "BD020-14E")
      (footprint "NVE_ULLGA4")
      (description "Magnet Sensor, 15 Gauss, ULLGA4, Implant-grade")
      (fields (field (name "MANUFACTURER") "NVE"))
      (libsource (lib "CB_Altium_Library") (part "BD027-14E"))
    )
    (comp (ref "U9")
      (value "CY15B108QN-20LPXC")
      (footprint "CY_002-18131_GQFN8")
      (description "FRAM, 8 Mbit (1024k x 8), SPI, 1.8-3.6V, QFN-8")
      (fields (field (name "MANUFACTURER") "Cypress Semiconductor"))
      (libsource (lib "CB_Altium_Library") (part "CY15B108QN"))
    )
    (comp (ref "U10")
      (value "AP7354D-33FS4-7")
      (footprint "DIODESINC_X2-DFN1010-4 (Type B)_REDUCED")
      (description "LDO Regulator, 3.3V, Shutdown, DFN1010-4")
      (fields (field (name "MANUFACTURER") "Diodes Inc"))
      (libsource (lib "CB_Altium_Library") (part "AP7354D"))
    )
    (comp (ref "U11")
      (value "AP7354D-33FS4-7")
      (footprint "DIODESINC_X2-DFN1010-4 (Type B)_REDUCED")
      (description "LDO Regulator, 3.3V, Shutdown, DFN1010-4")
      (fields (field (name "MANUFACTURER") "Diodes Inc"))
      (libsource (lib "CB_Altium_Library") (part "AP7354D"))
    )
    (comp (ref "U12")
      (value "LT1615ES5-1#TRPBF")
      (footprint "LT_S5_L")
      (description "Boost converter, SEPIC, 100 mA, SOT23-5")
      (fields (field (name "MANUFACTURER") "Linear Technology"))
      (libsource (lib "CB_Altium_Library") (part "LT1615"))
    )
    (comp (ref "U13")
      (value "ISL23315TFRUZ-T")
      (footprint "RENESAS_L10.2.1X1.6A_UTQFN10")
      (description "Digital potentiometer, 256 taps, 100k, I2C, QFN-10")
      (fields (field (name "MANUFACTURER") "Renesas"))
      (libsource (lib "CB_Altium_Library") (part "ISL23315"))
    )
    (comp (ref "U14")
      (value "AD8505ACBZ")
      (footprint "AD_CB-6-7(WLCSP6)")
      (description "Op Amp, Rail-to-Rail, 95kHz, WLCSP-6")
      (fields (field (name "MANUFACTURER") "Analog Devices"))
      (libsource (lib "CB_Altium_Library") (part "AD8505ACBZ"))
    )
    (comp (ref "U15")
      (value "AD8505ACBZ")
      (footprint "AD_CB-6-7(WLCSP6)")
      (description "Op Amp, Rail-to-Rail, 95kHz, WLCSP-6")
      (fields (field (name "MANUFACTURER") "Analog Devices"))
      (libsource (lib "CB_Altium_Library") (part "AD8505ACBZ"))
    )
    (comp (ref "U16")
      (value "AD8505ACBZ")
      (footprint "AD_CB-6-7(WLCSP6)")
      (description "Op Amp, Rail-to-Rail, 95kHz, WLCSP-6")
      (fields (field (name "MANUFACTURER") "Analog Devices"))
      (libsource (lib "CB_Altium_Library") (part "AD8505ACBZ"))
    )
    (comp (ref "U17")
      (value "STM32U585QII3")
      (footprint "STM_UFBGA132")
      (description "Microcontroller, ARM Cortex-M33, 2.0 MB Flash, 786 kB RAM, BGA-132")
      (fields (field (name "MANUFACTURER") "STMicro"))
      (libsource (lib "CB_Altium_Library") (part "STM32U585QII3"))
    )
    (comp (ref "U18")
      (value "TPS3831L30")
      (footprint "TI_X2SON_DQN0004A")
      (description "Reset Monitor, 2.63V, Active low, X2SON")
      (fields (field (name "MANUFACTURER") "Texas Instruments"))
      (libsource (lib "CB_Altium_Library") (part "TPS3831_b"))
    )
    (comp (ref "U30")
      (value "ADG1634BCPZ-REEL7")
      (footprint "AD_CP-20-8")
      (description "Analog switch, Quad SPDT, 4.5 ohm, QFN20")
      (fields (field (name "MANUFACTURER") "Analog Devices"))
      (libsource (lib "CB_Altium_Library") (part "ADG5234"))
    )
    (comp (ref "U31")
      (value "ADG1634BCPZ-REEL7")
      (footprint "AD_CP-20-8")
      (description "Analog switch, Quad SPDT, 4.5 ohm, QFN20")
      (fields (field (name "MANUFACTURER") "Analog Devices"))
      (libsource (lib "CB_Altium_Library") (part "ADG5234"))
    )
    (comp (ref "U91")
      (value "NRF52810-CAAA")
      (footprint "NORDIC_WLCSP_2.482x2.464")
      (description "Bluetooth radio, v5.0, 192 kB Flash, 24 kB RAM, BGA-33")
      (fields (field (name "MANUFACTURER") "Nordic"))
      (libsource (lib "CB_Altium_Library") (part "NRF52810"))
    )
    (comp (ref "U201")
      (value "AD8233ACBZ")
      (footprint "AD_CB-20-13_WLCSP20")
      (description "Analog front end, ECG, RLD amp, BGA-20")
      (fields (field (name "MANUFACTURER") "Analog Devices"))
      (libsource (lib "CB_Altium_Library") (part "AD8233"))
    )
    (comp (ref "U203")
      (value "AD8233ACBZ")
      (footprint "AD_CB-20-13_WLCSP20")
      (description "Analog front end, ECG, RLD amp, BGA-20")
      (fields (field (name "MANUFACTURER") "Analog Devices"))
      (libsource (lib "CB_Altium_Library") (part "AD8233"))
    )
    (comp (ref "U301")
      (value "DAC80502DRXT")
      (footprint "TI_DRX0010A")
      (description "DAC, 16-bit, Dual channel, SPI/I2C, WSON-10")
      (fields (field (name "MANUFACTURER") "Texas Instruments"))
      (libsource (lib "CB_Altium_Library") (part "DAC80502DRXT"))
    )
    (comp (ref "U303")
      (value "TS5A3159AYZPR")
      (footprint "TI_YZP6")
      (description "Analog Switch, SPDT, 2:1, DSBGA6")
      (fields (field (name "MANUFACTURER") "Texas Instruments"))
      (libsource (lib "*") (part "TS5A3159A_0"))
    )
    (comp (ref "U304")
      (value "TS5A3159AYZPR")
      (footprint "TI_YZP6")
      (description "Analog Switch, SPDT, 2:1, DSBGA6")
      (fields (field (name "MANUFACTURER") "Texas Instruments"))
      (libsource (lib "*") (part "TS5A3159A_0"))
    )
    (comp (ref "U305")
      (value "TLV9002SIYCKR")
      (footprint "TI_YCK0009")
      (description "Op Amp, Dual, Rail-to-Rail, 1MHz, BGA-9")
      (fields (field (name "MANUFACTURER") "Texas Instruments"))
      (libsource (lib "CB_Altium_Library") (part "TLV9002SIYCKR_d"))
    )
    (comp (ref "U306")
      (value "SN74LVC1G123YZPR")
      (footprint "TI_YZP0008")
      (description "Monostable, RC set, dual triggers, BGA-8")
      (fields (field (name "MANUFACTURER") "Texas Instruments"))
      (libsource (lib "CB_Altium_Library") (part "SN74LVC1G123DCUR"))
    )
    (comp (ref "U307")
      (value "SN74LVC2G08YZPR")
      (footprint "TI_YZP0008")
      (description "AND gate, Dual 2-input, BGA-8")
      (fields (field (name "MANUFACTURER") "Texas Instruments"))
      (libsource (lib "CB_Altium_Library") (part "SN74LVC2G08DCU"))
    )
    (comp (ref "U308")
      (value "MAX4781ETE+T")
      (footprint "MAXIM_21-0136")
      (description "Multiplexer, 8:1, 0.7 ohms, QFN-16")
      (fields (field (name "MANUFACTURER") "Maxim"))
      (libsource (lib "CB_Altium_Library") (part "MAX4781ETE+T"))
    )
    (comp (ref "U309")
      (value "MAX4781ETE+T")
      (footprint "MAXIM_21-0136")
      (description "Multiplexer, 8:1, 0.7 ohms, QFN-16")
      (fields (field (name "MANUFACTURER") "Maxim"))
      (libsource (lib "CB_Altium_Library") (part "MAX4781ETE+T"))
    )
    (comp (ref "U310")
      (value "TLV9002SIYCKR")
      (footprint "TI_YCK0009")
      (description "Op Amp, Dual, Rail-to-Rail, 1MHz, BGA-9")
      (fields (field (name "MANUFACTURER") "Texas Instruments"))
      (libsource (lib "CB_Altium_Library") (part "TLV9002SIYCKR_b"))
    )
    (comp (ref "U311")
      (value "AD8137YCPZ")
      (footprint "AD_CP-8-13")
      (description "Differential Amplifier, 110 MHz, DFN-8")
      (fields (field (name "MANUFACTURER") "Analog Devices"))
      (libsource (lib "CB_Altium_Library") (part "AD8137"))
    )
    (comp (ref "U501")
      (value "AD8505ACBZ")
      (footprint "AD_CB-6-7(WLCSP6)")
      (description "Op Amp, Rail-to-Rail, 95kHz, WLCSP-6")
      (fields (field (name "MANUFACTURER") "Analog Devices"))
      (libsource (lib "CB_Altium_Library") (part "AD8505ACBZ"))
    )
    (comp (ref "U502")
      (value "TLV3691IDCK")
      (footprint "TI_DCK5_REDUCED")
      (description "Comparator, Push-pull output, SC-70")
      (fields (field (name "MANUFACTURER") "Texas Instruments"))
      (libsource (lib "CB_Library") (part "TLV3691IDCK"))
    )
    (comp (ref "U503")
      (value "LTC3130IUDC-1")
      (footprint "LT_UDC-20_REDUCED")
      (description "Buck-Boost Converter, Selectable Voltage, QFN-20")
      (fields (field (name "MANUFACTURER") "Analog Devices"))
      (libsource (lib "CB_Altium_Library") (part "LTC3130IUDC-1"))
    )
    (comp (ref "X1")
      (value "FIDUCIAL")
      (footprint "Fid_IPC-7351B")
      (description "FIDUCIAL_MARK")
      (libsource (lib "Mechanical") (part "FIDUCIAL"))
    )
    (comp (ref "X2")
      (value "FIDUCIAL")
      (footprint "Fid_IPC-7351B")
      (description "FIDUCIAL_MARK")
      (libsource (lib "Mechanical") (part "FIDUCIAL"))
    )
    (comp (ref "X3")
      (value "FIDUCIAL")
      (footprint "Fid_IPC-7351B")
      (description "FIDUCIAL_MARK")
      (libsource (lib "Mechanical") (part "FIDUCIAL"))
    )
    (comp (ref "X4")
      (value "FIDUCIAL")
      (footprint "Fid_IPC-7351B")
      (description "FIDUCIAL_MARK")
      (libsource (lib "Mechanical") (part "FIDUCIAL"))
    )
    (comp (ref "X5")
      (value "FIDUCIAL")
      (footprint "Fid_IPC-7351B")
      (description "FIDUCIAL_MARK")
      (libsource (lib "Mechanical") (part "FIDUCIAL"))
    )
    (comp (ref "X6")
      (value "FIDUCIAL")
      (footprint "Fid_IPC-7351B")
      (description "FIDUCIAL_MARK")
      (libsource (lib "Mechanical") (part "FIDUCIAL"))
    )
    (comp (ref "X7")
      (value "HOLE, UNPLATED")
      (footprint "HOLE_UNPLATED_3.5MM")
      (description "Hole, Unplated")
      (libsource (lib "Mechanical") (part "HOLE_UNPLATED"))
    )
    (comp (ref "X8")
      (value "HOLE, UNPLATED")
      (footprint "HOLE_UNPLATED_3.5MM")
      (description "Hole, Unplated")
      (libsource (lib "Mechanical") (part "HOLE_UNPLATED"))
    )
    (comp (ref "X9")
      (value "HOLE, UNPLATED")
      (footprint "HOLE_UNPLATED_3.5MM")
      (description "Hole, Unplated")
      (libsource (lib "Mechanical") (part "HOLE_UNPLATED"))
    )
    (comp (ref "Y1")
      (value "32.768kHz")
      (footprint "Crystal:MICROCRYSTAL_CC8V-T1A")
      (description "Crystal, 32.768kHz, 6.0pF, 70k, CC8V, Implant-grade")
      (fields (field (name "MANUFACTURER") "TBD") (field (name "Comment") "CC8V-T1A32.768kHz"))
      (libsource (lib "") (part "Crystal_1"))
    )
    (comp (ref "Y2")
      (value "48.0MHz")
      (footprint "Crystal:MICROCRYSTAL_CC8A-T1A")
      (description "Crystal, 48.0MHz, 9.0pF, 20 ohms, CC8A, Implant-grade")
      (fields (field (name "MANUFACTURER") "TBD") (field (name "Comment") "CC8A-T1A48.000MHz"))
      (libsource (lib "CB_Altium_Library") (part "Crystal"))
    )
    (comp (ref "Y91")
      (value "32.768kHz")
      (footprint "Crystal:MICROCRYSTAL_CC8V-T1A")
      (description "Crystal, 32.768kHz, 6.0pF, 70k, CC8V, Implant-grade")
      (fields (field (name "MANUFACTURER") "TBD") (field (name "Comment") "CC8V-T1A32.768kHz"))
      (libsource (lib "") (part "Crystal_1"))
    )
    (comp (ref "Y92")
      (value "32.0MHz")
      (footprint "Crystal:MICROCRYSTAL_CC8A-T1A")
      (description "Crystal, 48.0MHz, 9.0pF, 20 ohms, CC8A, Implant-grade")
      (fields (field (name "MANUFACTURER") "TBD") (field (name "Comment") "CC8A-T1A48.000MHz"))
      (libsource (lib "") (part "Crystal_1"))
    )
  )
  (nets
    (net (code "1") (name "/AMPL_CSn") (class "Default")
      (node (ref "U17") (pin "C9") (pinfunction "SPI2_NSS_/_PD0_C9") (pintype "bidirectional"))
      (node (ref "U301") (pin "7") (pinfunction "~{SYNC}_/_A0_7") (pintype "input"))
    )
    (net (code "2") (name "/AMPL_MOSI") (class "Default")
      (node (ref "U17") (pin "B8") (pinfunction "SPI2_MOSI_/_USART2_RTS_/_PD4_B8") (pintype "bidirectional"))
      (node (ref "U301") (pin "8") (pinfunction "SDIN_/_SDA_8") (pintype "input"))
    )
    (net (code "3") (name "/AMPL_RSTn") (class "Default")
      (node (ref "U17") (pin "A9") (pinfunction "USART3_RTS_/_UART5_RX_/_PD2_A9") (pintype "bidirectional"))
      (node (ref "U306") (pin "3") (pinfunction "~{CLR}_3") (pintype "input"))
    )
    (net (code "4") (name "/AMPL_SCK") (class "Default")
      (node (ref "U17") (pin "B9") (pinfunction "SPI2_SCK_/_PD1_B9") (pintype "bidirectional"))
      (node (ref "U301") (pin "6") (pinfunction "SCLK_/_SCL_6") (pintype "input"))
    )
    (net (code "5") (name "/ANT+") (class "Default")
      (node (ref "C98") (pin "2") (pinfunction "2_2") (pintype "passive"))
      (node (ref "J419") (pin "1") (pinfunction "1_1") (pintype "passive"))
    )
    (net (code "6") (name "/ANT-") (class "Default")
      (node (ref "J418") (pin "1") (pinfunction "1_1") (pintype "passive"))
      (node (ref "L99") (pin "2") (pinfunction "2_2") (pintype "passive"))
    )
    (net (code "7") (name "/BATT1_MON") (class "Default")
      (node (ref "TP21") (pin "1") (pinfunction "1_1") (pintype "passive"))
      (node (ref "U17") (pin "J2") (pinfunction "PA0_/_ADC1_IN5_/_UART4_TX_/_WKUP1_J2") (pintype "bidirectional"))
      (node (ref "U6") (pin "A1") (pinfunction "OUT_A1") (pintype "passive"))
      (node (ref "U6") (pin "C2") (pinfunction "IN-_C2") (pintype "passive"))
    )
    (net (code "8") (name "/BATT2_MON") (class "Default")
      (node (ref "TP22") (pin "1") (pinfunction "1_1") (pintype "passive"))
      (node (ref "U17") (pin "G4") (pinfunction "PA1_/_ADC1_IN6_/_UART4_RX_/_WKUP3_/_SPI1_SCK_G4") (pintype "bidirectional"))
      (node (ref "U7") (pin "A1") (pinfunction "OUT_A1") (pintype "passive"))
      (node (ref "U7") (pin "C2") (pinfunction "IN-_C2") (pintype "passive"))
    )
    (net (code "9") (name "/BATTMON_EN") (class "Default")
      (node (ref "M23") (pin "1") (pinfunction "G_1") (pintype "passive"))
      (node (ref "U17") (pin "K2") (pinfunction "PA2_/_ADC1_IN7_/_LPUART1_TX_/_WKUP4_K2") (pintype "bidirectional"))
      (node (ref "U6") (pin "A2") (pinfunction "V+_A2") (pintype "power_in"))
      (node (ref "U7") (pin "A2") (pinfunction "V+_A2") (pintype "power_in"))
    )
    (net (code "10") (name "/BATT_SW") (class "Default")
      (node (ref "M25") (pin "3") (pinfunction "D_3") (pintype "passive"))
      (node (ref "M3") (pin "1") (pinfunction "G_1") (pintype "passive"))
      (node (ref "R29") (pin "2") (pinfunction "2_2") (pintype "passive"))
      (node (ref "R4") (pin "1") (pinfunction "1_1") (pintype "passive"))
      (node (ref "TP9") (pin "1") (pinfunction "1_1") (pintype "passive"))
    )
    (net (code "11") (name "/BATT_SW_EN") (class "Default")
      (node (ref "D10") (pin "2") (pinfunction "A_2") (pintype "passive"))
      (node (ref "TP23") (pin "1") (pinfunction "1_1") (pintype "passive"))
      (node (ref "U17") (pin "A4") (pinfunction "PB9_/_I2C1_SDA_/_SPI2_NSS_A4") (pintype "bidirectional"))
    )
    (net (code "12") (name "/BLE_P03") (class "Default")
      (node (ref "U17") (pin "G10") (pinfunction "SPI1_SCK_/_PG2_G10") (pintype "bidirectional"))
      (node (ref "U91") (pin "D6") (pinfunction "P0.03_/_AIN1_D6") (pintype "passive"))
    )
    (net (code "13") (name "/BLE_P04") (class "Default")
      (node (ref "U17") (pin "G11") (pinfunction "SPI1_MISO_/_PG3_G11") (pintype "bidirectional"))
      (node (ref "U91") (pin "E5") (pinfunction "P0.04_/_AIN2_E5") (pintype "passive"))
    )
    (net (code "14") (name "/BLE_P05") (class "Default")
      (node (ref "U17") (pin "G9") (pinfunction "SPI1_MOSI_/_PG4_G9") (pintype "bidirectional"))
      (node (ref "U91") (pin "E6") (pinfunction "P0.05_/_AIN3_E6") (pintype "passive"))
    )
    (net (code "15") (name "/BLE_P08") (class "Default")
      (node (ref "U17") (pin "G12") (pinfunction "LPUART1_CTS_/_SPI1_NSS_/_PG5_G12") (pintype "bidirectional"))
      (node (ref "U91") (pin "F6") (pinfunction "P0.08_F6") (pintype "passive"))
    )
    (net (code "16") (name "/BLE_P11") (class "Default")
      (node (ref "U17") (pin "F10") (pinfunction "I2C3_SCL_/_LPUART1_TX_/_PG7_F10") (pintype "bidirectional"))
      (node (ref "U91") (pin "F5") (pinfunction "P0.11_F5") (pintype "passive"))
    )
    (net (code "17") (name "/BLE_P12") (class "Default")
      (node (ref "U17") (pin "F12") (pinfunction "I2C3_SDA_/_LPUART1_RX_/_PG8_F12") (pintype "bidirectional"))
      (node (ref "U91") (pin "G5") (pinfunction "P0.12_G5") (pintype "passive"))
    )
    (net (code "18") (name "/BLE_P14") (class "Default")
      (node (ref "U17") (pin "B7") (pinfunction "SPI3_SCK_/_USART1_TX_/_PG9_B7") (pintype "bidirectional"))
      (node (ref "U91") (pin "F4") (pinfunction "P0.14_F4") (pintype "passive"))
    )
    (net (code "19") (name "/BLE_P15") (class "Default")
      (node (ref "U17") (pin "C7") (pinfunction "SPI3_MISO_/_USART1_RX_/_PG10_C7") (pintype "bidirectional"))
      (node (ref "U91") (pin "G4") (pinfunction "P0.15_G4") (pintype "passive"))
    )
    (net (code "20") (name "/BLE_P16") (class "Default")
      (node (ref "U17") (pin "M11") (pinfunction "VDD11_/_SPI3_MOSI_/_USART1_CTS_/_PG11_M11") (pintype "power_in"))
      (node (ref "U91") (pin "G3") (pinfunction "P0.16_G3") (pintype "passive"))
    )
    (net (code "21") (name "/BLE_P17") (class "Default")
      (node (ref "U17") (pin "A6") (pinfunction "SPI3_NSS_/_USART1_RTS_/_PG12_A6") (pintype "bidirectional"))
      (node (ref "U91") (pin "F3") (pinfunction "P0.17_F3") (pintype "passive"))
    )
    (net (code "22") (name "/BLE_PWRn") (class "Default")
      (node (ref "M91") (pin "1") (pinfunction "G_1") (pintype "passive"))
      (node (ref "U17") (pin "K6") (pinfunction "ADC4_IN8_/_PG1_K6") (pintype "bidirectional"))
    )
    (net (code "23") (name "/BLE_RSTn") (class "Default")
      (node (ref "J906") (pin "5") (pinfunction "5_5") (pintype "passive"))
      (node (ref "J911") (pin "10") (pinfunction "10_10") (pintype "passive"))
      (node (ref "TP82") (pin "1") (pinfunction "1_1") (pintype "passive"))
      (node (ref "U17") (pin "F9") (pinfunction "I2C3_SMBA_/_LPUART1_RTS_/_PG6_F9") (pintype "bidirectional"))
      (node (ref "U91") (pin "F2") (pinfunction "P0.21_/_nRESET_F2") (pintype "passive"))
    )
    (net (code "24") (name "/BLE_SWDCLK") (class "Default")
      (node (ref "J906") (pin "4") (pinfunction "4_4") (pintype "passive"))
      (node (ref "J911") (pin "4") (pinfunction "4_4") (pintype "passive"))
      (node (ref "TP83") (pin "1") (pinfunction "1_1") (pintype "passive"))
      (node (ref "U91") (pin "G1") (pinfunction "SWDCLK_G1") (pintype "passive"))
    )
    (net (code "25") (name "/BLE_SWDIO") (class "Default")
      (node (ref "J906") (pin "3") (pinfunction "3_3") (pintype "passive"))
      (node (ref "J911") (pin "2") (pinfunction "2_2") (pintype "passive"))
      (node (ref "TP84") (pin "1") (pinfunction "1_1") (pintype "passive"))
      (node (ref "U91") (pin "F1") (pinfunction "SWDIO_F1") (pintype "passive"))
    )
    (net (code "26") (name "/BLE_UART_RX") (class "Default")
      (node (ref "J907") (pin "4") (pinfunction "4_4") (pintype "passive"))
      (node (ref "TP86") (pin "1") (pinfunction "1_1") (pintype "passive"))
      (node (ref "U91") (pin "E2") (pinfunction "P0.18_E2") (pintype "passive"))
    )
    (net (code "27") (name "/BLE_UART_TX") (class "Default")
      (node (ref "J907") (pin "5") (pinfunction "5_5") (pintype "passive"))
      (node (ref "TP85") (pin "1") (pinfunction "1_1") (pintype "passive"))
      (node (ref "U91") (pin "G2") (pinfunction "P0.20_G2") (pintype "passive"))
    )
    (net (code "28") (name "/CH1") (class "Default")
      (node (ref "C401") (pin "2") (pinfunction "2_2") (pintype "passive"))
      (node (ref "D401") (pin "2") (pinfunction "2_2") (pintype "passive"))
      (node (ref "J401") (pin "1") (pinfunction "1_1") (pintype "passive"))
      (node (ref "U30") (pin "6") (pinfunction "D2_6") (pintype "passive"))
    )
    (net (code "29") (name "/CH2") (class "Default")
      (node (ref "C402") (pin "2") (pinfunction "2_2") (pintype "passive"))
      (node (ref "D402") (pin "2") (pinfunction "2_2") (pintype "passive"))
      (node (ref "J402") (pin "1") (pinfunction "1_1") (pintype "passive"))
      (node (ref "U30") (pin "1") (pinfunction "D1_1") (pintype "passive"))
    )
    (net (code "30") (name "/CH3") (class "Default")
      (node (ref "C409") (pin "2") (pinfunction "2_2") (pintype "passive"))
      (node (ref "D409") (pin "2") (pinfunction "2_2") (pintype "passive"))
      (node (ref "J409") (pin "1") (pinfunction "1_1") (pintype "passive"))
      (node (ref "U30") (pin "15") (pinfunction "D4_15") (pintype "passive"))
    )
    (net (code "31") (name "/CH4") (class "Default")
      (node (ref "C410") (pin "2") (pinfunction "2_2") (pintype "passive"))
      (node (ref "D410") (pin "2") (pinfunction "2_2") (pintype "passive"))
      (node (ref "J410") (pin "1") (pinfunction "1_1") (pintype "passive"))
      (node (ref "U30") (pin "11") (pinfunction "D3_11") (pintype "passive"))
    )
    (net (code "32") (name "/CHG1_EN") (class "Default")
      (node (ref "M11") (pin "1") (pinfunction "G_1") (pintype "passive"))
      (node (ref "M6") (pin "1") (pinfunction "G_1") (pintype "passive"))
      (node (ref "R14") (pin "1") (pinfunction "1_1") (pintype "passive"))
      (node (ref "U17") (pin "J7") (pinfunction "PE10_J7") (pintype "bidirectional"))
    )
    (net (code "33") (name "/CHG1_OVP_ERRn") (class "Default")
      (node (ref "M12") (pin "3") (pinfunction "D_3") (pintype "passive"))
      (node (ref "R14") (pin "2") (pinfunction "2_2") (pintype "passive"))
      (node (ref "TP16") (pin "1") (pinfunction "1_1") (pintype "passive"))
      (node (ref "U17") (pin "B2") (pinfunction "WKUP1_/_PE4_B2") (pintype "bidirectional"))
    )
    (net (code "34") (name "/CHG1_STATUS") (class "Default")
      (node (ref "U17") (pin "C2") (pinfunction "WKUP3_/_PE6_C2") (pintype "bidirectional"))
      (node (ref "U2") (pin "2") (pinfunction "~{CHRG}_2") (pintype "open_collector"))
    )
    (net (code "35") (name "/CHG2_EN") (class "Default")
      (node (ref "M14") (pin "1") (pinfunction "G_1") (pintype "passive"))
      (node (ref "M19") (pin "1") (pinfunction "G_1") (pintype "passive"))
      (node (ref "R22") (pin "1") (pinfunction "1_1") (pintype "passive"))
      (node (ref "U17") (pin "L7") (pinfunction "PE11_L7") (pintype "bidirectional"))
    )
    (net (code "36") (name "/CHG2_OVP_ERRn") (class "Default")
      (node (ref "M20") (pin "3") (pinfunction "D_3") (pintype "passive"))
      (node (ref "R22") (pin "2") (pinfunction "2_2") (pintype "passive"))
      (node (ref "TP20") (pin "1") (pinfunction "1_1") (pintype "passive"))
      (node (ref "U17") (pin "A1") (pinfunction "WKUP2_/_PE5_A1") (pintype "bidirectional"))
    )
    (net (code "37") (name "/CHG2_STATUS") (class "Default")
      (node (ref "U17") (pin "K7") (pinfunction "WKUP6_/_PE7_K7") (pintype "bidirectional"))
      (node (ref "U4") (pin "2") (pinfunction "~{CHRG}_2") (pintype "open_collector"))
    )
    (net (code "38") (name "/CHG_RATE1") (class "Default")
      (node (ref "M15") (pin "1") (pinfunction "G_1") (pintype "passive"))
      (node (ref "M7") (pin "1") (pinfunction "G_1") (pintype "passive"))
      (node (ref "U17") (pin "J6") (pinfunction "WKUP7_/_PE8_J6") (pintype "bidirectional"))
    )
    (net (code "39") (name "/CHG_RATE2") (class "Default")
      (node (ref "M16") (pin "1") (pinfunction "G_1") (pintype "passive"))
      (node (ref "M8") (pin "1") (pinfunction "G_1") (pintype "passive"))
      (node (ref "U17") (pin "M7") (pinfunction "PE9_M7") (pintype "bidirectional"))
    )
    (net (code "40") (name "/DEBUG_CTS") (class "Default")
      (node (ref "J909") (pin "6") (pinfunction "6_6") (pintype "passive"))
      (node (ref "TP45") (pin "1") (pinfunction "1_1") (pintype "passive"))
      (node (ref "U17") (pin "C12") (pinfunction "PA11_/_USART1_CTS_/_SPI1_MISO_C12") (pintype "bidirectional"))
    )
    (net (code "41") (name "/DEBUG_RTS") (class "Default")
      (node (ref "J909") (pin "2") (pinfunction "2_2") (pintype "passive"))
      (node (ref "TP44") (pin "1") (pinfunction "1_1") (pintype "passive"))
      (node (ref "U17") (pin "B12") (pinfunction "PA12_/_USART1_RTS_/_SPI1_MOSI_B12") (pintype "bidirectional"))
    )
    (net (code "42") (name "/DEBUG_RX") (class "Default")
      (node (ref "J909") (pin "4") (pinfunction "4_4") (pintype "passive"))
      (node (ref "TP46") (pin "1") (pinfunction "1_1") (pintype "passive"))
      (node (ref "U17") (pin "D11") (pinfunction "PA10_/_USART1_RX_D11") (pintype "bidirectional"))
    )
    (net (code "43") (name "/DEBUG_TX") (class "Default")
      (node (ref "J909") (pin "5") (pinfunction "5_5") (pintype "passive"))
      (node (ref "TP47") (pin "1") (pinfunction "1_1") (pintype "passive"))
      (node (ref "U17") (pin "D10") (pinfunction "PA9_/_USART1_TX_/_SPI2_SCK_D10") (pintype "bidirectional"))
    )
    (net (code "44") (name "/ECG1+") (class "Default")
      (node (ref "R202") (pin "1") (pinfunction "1_1") (pintype "passive"))
      (node (ref "R203") (pin "1") (pinfunction "1_1") (pintype "passive"))
      (node (ref "U31") (pin "12") (pinfunction "S3B_12") (pintype "passive"))
      (node (ref "U31") (pin "7") (pinfunction "S2A_7") (pintype "passive"))
    )
    (net (code "45") (name "/ECG1-") (class "Default")
      (node (ref "R201") (pin "1") (pinfunction "1_1") (pintype "passive"))
      (node (ref "R204") (pin "1") (pinfunction "1_1") (pintype "passive"))
      (node (ref "U31") (pin "14") (pinfunction "S4B_14") (pintype "passive"))
      (node (ref "U31") (pin "20") (pinfunction "S1A_20") (pintype "passive"))
    )
    (net (code "46") (name "/ECG1_LOD") (class "Default")
      (node (ref "U17") (pin "K4") (pinfunction "PB2_/_ADC1_IN17_/_WKUP1_K4") (pintype "bidirectional"))
      (node (ref "U201") (pin "C1") (pinfunction "LOD_C1") (pintype "output"))
    )
    (net (code "47") (name "/ECG1_OUT") (class "Default")
      (node (ref "C203") (pin "1") (pinfunction "1_1") (pintype "passive"))
      (node (ref "R212") (pin "2") (pinfunction "2_2") (pintype "passive"))
      (node (ref "U17") (pin "M4") (pinfunction "PB0_/_ADC1_IN15_/_ADC4_IN18_/_SPI1_NSS_M4") (pintype "bidirectional"))
      (node (ref "U201") (pin "D1") (pinfunction "OUT_D1") (pintype "output"))
    )
    (net (code "48") (name "/ECG1_RLD") (class "Default")
      (node (ref "U17") (pin "B6") (pinfunction "PB4_/_NJTRST_/_USART1_CTS_/_SPI1_MISO_/_SPI3_MISO_/_I2C3_SDA_B6") (pintype "bidirectional"))
      (node (ref "U201") (pin "C2") (pinfunction "RLD_~{SDN}_C2") (pintype "input"))
    )
    (net (code "49") (name "/ECG1_SDNn") (class "Default")
      (node (ref "U17") (pin "D6") (pinfunction "PB5_/_USART1_CK_/_SPI1_MOSI_/_SPI3_MOSI_/_WKUP6_D6") (pintype "bidirectional"))
      (node (ref "U201") (pin "B1") (pinfunction "~{SDN}_B1") (pintype "input"))
    )
    (net (code "50") (name "/ECG_SEL1") (class "Default")
      (node (ref "U17") (pin "J8") (pinfunction "SPI1_NSS_/_PE12_J8") (pintype "bidirectional"))
      (node (ref "U31") (pin "9") (pinfunction "IN3_9") (pintype "input"))
    )
    (net (code "51") (name "/ECG_SEL2") (class "Default")
      (node (ref "U17") (pin "M8") (pinfunction "SPI1_SCK_/_PE13_M8") (pintype "bidirectional"))
      (node (ref "U31") (pin "17") (pinfunction "IN4_17") (pintype "input"))
    )
    (net (code "52") (name "/ECG_SEL3") (class "Default")
      (node (ref "U17") (pin "K8") (pinfunction "SPI1_MISO_/_PE14_K8") (pintype "bidirectional"))
      (node (ref "U31") (pin "19") (pinfunction "IN1_19") (pintype "input"))
    )
    (net (code "53") (name "/ECG_SEL4") (class "Default")
      (node (ref "U17") (pin "L8") (pinfunction "SPI1_MOSI_/_PE15_L8") (pintype "bidirectional"))
      (node (ref "U31") (pin "8") (pinfunction "IN2_8") (pintype "input"))
    )
    (net (code "54") (name "/EGG1+") (class "Default")
      (node (ref "R242") (pin "1") (pinfunction "1_1") (pintype "passive"))
      (node (ref "R243") (pin "1") (pinfunction "1_1") (pintype "passive"))
      (node (ref "U31") (pin "10") (pinfunction "S3A_10") (pintype "passive"))
      (node (ref "U31") (pin "2") (pinfunction "S1B_2") (pintype "passive"))
    )
    (net (code "55") (name "/EGG1-") (class "Default")
      (node (ref "R241") (pin "1") (pinfunction "1_1") (pintype "passive"))
      (node (ref "R244") (pin "1") (pinfunction "1_1") (pintype "passive"))
      (node (ref "U31") (pin "16") (pinfunction "S4A_16") (pintype "passive"))
      (node (ref "U31") (pin "5") (pinfunction "S2B_5") (pintype "passive"))
    )
    (net (code "56") (name "/EGG1_LOD") (class "Default")
      (node (ref "U17") (pin "A5") (pinfunction "PB6_/_USART1_TX_/_I2C4_SCL_/_I2C1_SCL_/_WKUP3_A5") (pintype "bidirectional"))
      (node (ref "U203") (pin "C1") (pinfunction "LOD_C1") (pintype "output"))
    )
    (net (code "57") (name "/EGG1_OUT") (class "Default")
      (node (ref "C243") (pin "1") (pinfunction "1_1") (pintype "passive"))
      (node (ref "R252") (pin "2") (pinfunction "2_2") (pintype "passive"))
      (node (ref "U17") (pin "L4") (pinfunction "PB1_/_ADC1_IN16_/_ADC4_IN19_/_WKUP4_L4") (pintype "bidirectional"))
      (node (ref "U203") (pin "D1") (pinfunction "OUT_D1") (pintype "output"))
    )
    (net (code "58") (name "/EGG1_RLD") (class "Default")
      (node (ref "U17") (pin "D5") (pinfunction "PB7_/_USART1_RX_/_I2C4_SDA_/_I2C1_SDA_/_WKUP4_D5") (pintype "bidirectional"))
      (node (ref "U203") (pin "C2") (pinfunction "RLD_~{SDN}_C2") (pintype "input"))
    )
    (net (code "59") (name "/EGG1_SDNn") (class "Default")
      (node (ref "U17") (pin "C5") (pinfunction "PB8_/_I2C1_SCL_/_WKUP5_C5") (pintype "bidirectional"))
      (node (ref "U203") (pin "B1") (pinfunction "~{SDN}_B1") (pintype "input"))
    )
    (net (code "60") (name "/ENCL") (class "Default")
      (node (ref "C397") (pin "2") (pinfunction "2_2") (pintype "passive"))
      (node (ref "C401") (pin "1") (pinfunction "1_1") (pintype "passive"))
      (node (ref "C402") (pin "1") (pinfunction "1_1") (pintype "passive"))
      (node (ref "C403") (pin "1") (pinfunction "1_1") (pintype "passive"))
      (node (ref "C404") (pin "1") (pinfunction "1_1") (pintype "passive"))
      (node (ref "C405") (pin "1") (pinfunction "1_1") (pintype "passive"))
      (node (ref "C406") (pin "1") (pinfunction "1_1") (pintype "passive"))
      (node (ref "C407") (pin "1") (pinfunction "1_1") (pintype "passive"))
      (node (ref "C408") (pin "1") (pinfunction "1_1") (pintype "passive"))
      (node (ref "C409") (pin "1") (pinfunction "1_1") (pintype "passive"))
      (node (ref "C410") (pin "1") (pinfunction "1_1") (pintype "passive"))
      (node (ref "C411") (pin "1") (pinfunction "1_1") (pintype "passive"))
      (node (ref "C412") (pin "1") (pinfunction "1_1") (pintype "passive"))
      (node (ref "C413") (pin "1") (pinfunction "1_1") (pintype "passive"))
      (node (ref "C414") (pin "1") (pinfunction "1_1") (pintype "passive"))
      (node (ref "C415") (pin "1") (pinfunction "1_1") (pintype "passive"))
      (node (ref "C416") (pin "1") (pinfunction "1_1") (pintype "passive"))
      (node (ref "D401") (pin "1") (pinfunction "1_1") (pintype "passive"))
      (node (ref "D402") (pin "1") (pinfunction "1_1") (pintype "passive"))
      (node (ref "D403") (pin "1") (pinfunction "1_1") (pintype "passive"))
      (node (ref "D404") (pin "1") (pinfunction "1_1") (pintype "passive"))
      (node (ref "D405") (pin "1") (pinfunction "1_1") (pintype "passive"))
      (node (ref "D406") (pin "1") (pinfunction "1_1") (pintype "passive"))
      (node (ref "D407") (pin "1") (pinfunction "1_1") (pintype "passive"))
      (node (ref "D408") (pin "1") (pinfunction "1_1") (pintype "passive"))
      (node (ref "D409") (pin "1") (pinfunction "1_1") (pintype "passive"))
      (node (ref "D410") (pin "1") (pinfunction "1_1") (pintype "passive"))
      (node (ref "D411") (pin "1") (pinfunction "1_1") (pintype "passive"))
      (node (ref "D412") (pin "1") (pinfunction "1_1") (pintype "passive"))
      (node (ref "D413") (pin "1") (pinfunction "1_1") (pintype "passive"))
      (node (ref "D414") (pin "1") (pinfunction "1_1") (pintype "passive"))
      (node (ref "D415") (pin "1") (pinfunction "1_1") (pintype "passive"))
      (node (ref "D416") (pin "1") (pinfunction "1_1") (pintype "passive"))
      (node (ref "D417") (pin "2") (pinfunction "2_2") (pintype "passive"))
      (node (ref "D418") (pin "2") (pinfunction "2_2") (pintype "passive"))
      (node (ref "J417") (pin "1") (pinfunction "1_1") (pintype "passive"))
    )
    (net (code "61") (name "/FRAM_CSn") (class "Default")
      (node (ref "U17") (pin "L3") (pinfunction "PA4_/_ADC1_IN9_/_ADC4_IN9_/_SPI1_NSS_/_SPI3_NSS_/_WKUP2_L3") (pintype "bidirectional"))
      (node (ref "U9") (pin "1") (pinfunction "~{CS}_1") (pintype "passive"))
    )
    (net (code "62") (name "/FRAM_EN") (class "Default")
      (node (ref "TP27") (pin "1") (pinfunction "1_1") (pintype "passive"))
      (node (ref "U17") (pin "D12") (pinfunction "PA8_/_USART1_CK_D12") (pintype "bidirectional"))
      (node (ref "U9") (pin "3") (pinfunction "~{WP}_3") (pintype "passive"))
      (node (ref "U9") (pin "8") (pinfunction "VDD_8") (pintype "power_in"))
    )
    (net (code "63") (name "/FRAM_MISO") (class "Default")
      (node (ref "U17") (pin "L2") (pinfunction "PA6_/_ADC1_IN11_/_ADC4_IN11_/_SPI1_MISO_/_WKUP7_L2") (pintype "bidirectional"))
      (node (ref "U9") (pin "2") (pinfunction "SO_2") (pintype "passive"))
    )
    (net (code "64") (name "/FRAM_MOSI") (class "Default")
      (node (ref "U17") (pin "K3") (pinfunction "PA7_/_ADC1_IN12_/_ADC4_IN20_/_SPI1_MOSI_/_I2C3_SCL_/_WKUP8_K3") (pintype "bidirectional"))
      (node (ref "U9") (pin "5") (pinfunction "SI_5") (pintype "passive"))
    )
    (net (code "65") (name "/FRAM_SCK") (class "Default")
      (node (ref "U17") (pin "M1") (pinfunction "PA5_/_ADC1_IN10_/_ADC4_IN10_/_SPI1_SCK_/_WKUP6_M1") (pintype "bidirectional"))
      (node (ref "U9") (pin "6") (pinfunction "SCK_6") (pintype "passive"))
    )
    (net (code "66") (name "/HVSW_EN") (class "Default")
      (node (ref "M29") (pin "1") (pinfunction "G_1") (pintype "passive"))
      (node (ref "R53") (pin "1") (pinfunction "1_1") (pintype "passive"))
      (node (ref "TP31") (pin "1") (pinfunction "1_1") (pintype "passive"))
      (node (ref "U17") (pin "L9") (pinfunction "PB11_/_LPUART1_TX_/_I2C4_SDA_/_I2C2_SDA_L9") (pintype "bidirectional"))
    )
    (net (code "67") (name "/HV_EN") (class "Default")
      (node (ref "R49") (pin "1") (pinfunction "1_1") (pintype "passive"))
      (node (ref "R50") (pin "1") (pinfunction "1_1") (pintype "passive"))
      (node (ref "U12") (pin "4") (pinfunction "~{SHDN}_4") (pintype "input"))
      (node (ref "U13") (pin "10") (pinfunction "VLOGIC_10") (pintype "power_in"))
      (node (ref "U13") (pin "8") (pinfunction "VCC_8") (pintype "power_in"))
      (node (ref "U17") (pin "L11") (pinfunction "PB12_/_SPI2_NSS_/_I2C2_SMBA_L11") (pintype "bidirectional"))
    )
    (net (code "68") (name "/HV_SCL") (class "Default")
      (node (ref "R49") (pin "2") (pinfunction "2_2") (pintype "passive"))
      (node (ref "U13") (pin "1") (pinfunction "SCL_1") (pintype "passive"))
      (node (ref "U17") (pin "K10") (pinfunction "PB13_/_SPI2_SCK_/_I2C2_SCL_K10") (pintype "bidirectional"))
    )
    (net (code "69") (name "/HV_SDA") (class "Default")
      (node (ref "R50") (pin "2") (pinfunction "2_2") (pintype "passive"))
      (node (ref "U13") (pin "2") (pinfunction "SDA_2") (pintype "passive"))
      (node (ref "U17") (pin "K11") (pinfunction "PB14_/_SPI2_MISO_/_I2C2_SDA_K11") (pintype "bidirectional"))
    )
    (net (code "70") (name "/IMP1") (class "Default")
      (node (ref "R351") (pin "2") (pinfunction "2_2") (pintype "passive"))
      (node (ref "R371") (pin "1") (pinfunction "1_1") (pintype "passive"))
      (node (ref "U308") (pin "11") (pinfunction "X0_11") (pintype "passive"))
      (node (ref "U309") (pin "11") (pinfunction "X0_11") (pintype "passive"))
    )
    (net (code "71") (name "/IMP2") (class "Default")
      (node (ref "R352") (pin "2") (pinfunction "2_2") (pintype "passive"))
      (node (ref "R372") (pin "1") (pinfunction "1_1") (pintype "passive"))
      (node (ref "U308") (pin "12") (pinfunction "X1_12") (pintype "passive"))
      (node (ref "U309") (pin "12") (pinfunction "X1_12") (pintype "passive"))
    )
    (net (code "72") (name "/IMP3") (class "Default")
      (node (ref "R353") (pin "2") (pinfunction "2_2") (pintype "passive"))
      (node (ref "R373") (pin "1") (pinfunction "1_1") (pintype "passive"))
      (node (ref "U308") (pin "13") (pinfunction "X2_13") (pintype "passive"))
      (node (ref "U309") (pin "13") (pinfunction "X2_13") (pintype "passive"))
    )
    (net (code "73") (name "/IMP4") (class "Default")
      (node (ref "R354") (pin "2") (pinfunction "2_2") (pintype "passive"))
      (node (ref "R374") (pin "1") (pinfunction "1_1") (pintype "passive"))
      (node (ref "U308") (pin "10") (pinfunction "X3_10") (pintype "passive"))
      (node (ref "U309") (pin "10") (pinfunction "X3_10") (pintype "passive"))
    )
    (net (code "74") (name "/IMP17") (class "Default")
      (node (ref "R367") (pin "2") (pinfunction "2_2") (pintype "passive"))
      (node (ref "R387") (pin "1") (pinfunction "1_1") (pintype "passive"))
      (node (ref "U308") (pin "15") (pinfunction "X4_15") (pintype "passive"))
      (node (ref "U309") (pin "15") (pinfunction "X4_15") (pintype "passive"))
    )
    (net (code "75") (name "/IMPA") (class "Default")
      (node (ref "U308") (pin "1") (pinfunction "X_1") (pintype "passive"))
      (node (ref "U310") (pin "A1") (pinfunction "IN1+_A1") (pintype "passive"))
    )
    (net (code "76") (name "/IMPA_SEL0") (class "Default")
      (node (ref "U17") (pin "D3") (pinfunction "PF3_D3") (pintype "bidirectional"))
      (node (ref "U308") (pin "9") (pinfunction "A_9") (pintype "input"))
    )
    (net (code "77") (name "/IMPA_SEL1") (class "Default")
      (node (ref "U17") (pin "E3") (pinfunction "PF4_E3") (pintype "bidirectional"))
      (node (ref "U308") (pin "8") (pinfunction "B_8") (pintype "input"))
    )
    (net (code "78") (name "/IMPA_SEL2") (class "Default")
      (node (ref "U17") (pin "F2") (pinfunction "PF5_F2") (pintype "bidirectional"))
      (node (ref "U308") (pin "7") (pinfunction "C_7") (pintype "input"))
    )
    (net (code "79") (name "/IMPB") (class "Default")
      (node (ref "U309") (pin "1") (pinfunction "X_1") (pintype "passive"))
      (node (ref "U310") (pin "A3") (pinfunction "IN2+_A3") (pintype "passive"))
    )
    (net (code "80") (name "/IMPB_SEL0") (class "Default")
      (node (ref "U17") (pin "K5") (pinfunction "PF11_K5") (pintype "bidirectional"))
      (node (ref "U309") (pin "9") (pinfunction "A_9") (pintype "input"))
    )
    (net (code "81") (name "/IMPB_SEL1") (class "Default")
      (node (ref "U17") (pin "L5") (pinfunction "PF12_L5") (pintype "bidirectional"))
      (node (ref "U309") (pin "8") (pinfunction "B_8") (pintype "input"))
    )
    (net (code "82") (name "/IMPB_SEL2") (class "Default")
      (node (ref "U17") (pin "M5") (pinfunction "PF13_M5") (pintype "bidirectional"))
      (node (ref "U309") (pin "7") (pinfunction "C_7") (pintype "input"))
    )
    (net (code "83") (name "/IMP_EN") (class "Default")
      (node (ref "M319") (pin "1") (pinfunction "G_1") (pintype "passive"))
      (node (ref "U17") (pin "E1") (pinfunction "WKUP8_/_I2C2_SMBA_/_PF2_E1") (pintype "bidirectional"))
      (node (ref "U308") (pin "4") (pinfunction "~{ENABLE}_4") (pintype "passive"))
      (node (ref "U309") (pin "4") (pinfunction "~{ENABLE}_4") (pintype "passive"))
      (node (ref "U310") (pin "B2") (pinfunction "~{SHDN}_B2") (pintype "input"))
    )
    (net (code "84") (name "/IMP_INA") (class "Default")
      (node (ref "R307") (pin "2") (pinfunction "2_2") (pintype "passive"))
      (node (ref "TP305") (pin "1") (pinfunction "1_1") (pintype "passive"))
      (node (ref "U17") (pin "J5") (pinfunction "ADC4_IN5_/_PF14_J5") (pintype "bidirectional"))
    )
    (net (code "85") (name "/IMP_INB") (class "Default")
      (node (ref "R308") (pin "2") (pinfunction "2_2") (pintype "passive"))
      (node (ref "TP306") (pin "1") (pinfunction "1_1") (pintype "passive"))
      (node (ref "U17") (pin "L6") (pinfunction "ADC4_IN6_/_PF15_L6") (pintype "bidirectional"))
    )
    (net (code "86") (name "/IPG_SHDN") (class "Default")
      (node (ref "M4") (pin "1") (pinfunction "G_1") (pintype "passive"))
      (node (ref "R6") (pin "1") (pinfunction "1_1") (pintype "passive"))
      (node (ref "TP11") (pin "1") (pinfunction "1_1") (pintype "passive"))
      (node (ref "U17") (pin "K9") (pinfunction "PB10_/_LPUART1_RX_/_SPI2_SCK_/_I2C4_SCL_/_I2C2_SCL_/_WKUP8_K9") (pintype "bidirectional"))
    )
    (net (code "87") (name "/IREF") (class "Default")
      (node (ref "Q318") (pin "3") (pinfunction "C_3") (pintype "passive"))
      (node (ref "Q321") (pin "2") (pinfunction "E_2") (pintype "passive"))
      (node (ref "Q322") (pin "2") (pinfunction "E_2") (pintype "passive"))
      (node (ref "Q323") (pin "2") (pinfunction "E_2") (pintype "passive"))
      (node (ref "Q324") (pin "2") (pinfunction "E_2") (pintype "passive"))
      (node (ref "Q337") (pin "2") (pinfunction "E_2") (pintype "passive"))
    )
    (net (code "88") (name "/MAG_DET") (class "Default")
      (node (ref "M27") (pin "3") (pinfunction "D_3") (pintype "passive"))
      (node (ref "TP26") (pin "1") (pinfunction "1_1") (pintype "passive"))
      (node (ref "U17") (pin "L1") (pinfunction "PA3_/_ADC1_IN8_/_LPUART1_RX_/_WKUP5_L1") (pintype "bidirectional"))
    )
    (net (code "89") (name "/MAG_EN") (class "Default")
      (node (ref "R31") (pin "1") (pinfunction "1_1") (pintype "passive"))
      (node (ref "U17") (pin "A11") (pinfunction "PA15_/_JTDI_/_SPI1_NSS_/_SPI3_NSS_A11") (pintype "bidirectional"))
    )
    (net (code "90") (name "/MAG_OUTn") (class "Default")
      (node (ref "M24") (pin "1") (pinfunction "G_1") (pintype "passive"))
      (node (ref "M26") (pin "1") (pinfunction "G_1") (pintype "passive"))
      (node (ref "M27") (pin "1") (pinfunction "G_1") (pintype "passive"))
      (node (ref "R32") (pin "2") (pinfunction "2_2") (pintype "passive"))
      (node (ref "TP25") (pin "1") (pinfunction "1_1") (pintype "passive"))
      (node (ref "U8") (pin "3") (pinfunction "OUT_3") (pintype "passive"))
    )
    (net (code "91") (name "/MAG_PWR") (class "Default")
      (node (ref "R30") (pin "2") (pinfunction "2_2") (pintype "passive"))
      (node (ref "R31") (pin "2") (pinfunction "2_2") (pintype "passive"))
      (node (ref "R32") (pin "1") (pinfunction "1_1") (pintype "passive"))
      (node (ref "R33") (pin "1") (pinfunction "1_1") (pintype "passive"))
      (node (ref "TP24") (pin "1") (pinfunction "1_1") (pintype "passive"))
      (node (ref "U8") (pin "2") (pinfunction "VDD_2") (pintype "power_in"))
    )
    (net (code "92") (name "/MUX_ENn") (class "Default")
      (node (ref "U17") (pin "E10") (pinfunction "PC7_E10") (pintype "bidirectional"))
      (node (ref "U30") (pin "18") (pinfunction "~{EN}_18") (pintype "input"))
      (node (ref "U31") (pin "18") (pinfunction "~{EN}_18") (pintype "input"))
    )
    (net (code "93") (name "/NFC_EN") (class "Default")
      (node (ref "D502") (pin "1") (pinfunction "K_1") (pintype "passive"))
      (node (ref "M511") (pin "1") (pinfunction "G_1") (pintype "passive"))
      (node (ref "R525") (pin "1") (pinfunction "1_1") (pintype "passive"))
      (node (ref "R526") (pin "1") (pinfunction "1_1") (pintype "passive"))
      (node (ref "TP509") (pin "1") (pinfunction "1_1") (pintype "passive"))
      (node (ref "U17") (pin "E12") (pinfunction "PC8_E12") (pintype "bidirectional"))
      (node (ref "U502") (pin "5") (pinfunction "V+_5") (pintype "power_in"))
    )
    (net (code "94") (name "/NFC_RXD") (class "Default")
      (node (ref "M513") (pin "3") (pinfunction "D_3") (pintype "passive"))
      (node (ref "R524") (pin "2") (pinfunction "2_2") (pintype "passive"))
      (node (ref "R525") (pin "2") (pinfunction "2_2") (pintype "passive"))
      (node (ref "TP510") (pin "1") (pinfunction "1_1") (pintype "passive"))
      (node (ref "U17") (pin "A10") (pinfunction "PC11_/_UART4_RX_/_USART3_RX_/_SPI3_MISO_A10") (pintype "bidirectional"))
    )
    (net (code "95") (name "/NFC_TXD") (class "Default")
      (node (ref "D502") (pin "2") (pinfunction "A_2") (pintype "passive"))
      (node (ref "D503") (pin "1") (pinfunction "K_1") (pintype "passive"))
      (node (ref "M501") (pin "1") (pinfunction "G_1") (pintype "passive"))
      (node (ref "M514") (pin "1") (pinfunction "G_1") (pintype "passive"))
      (node (ref "R527") (pin "1") (pinfunction "1_1") (pintype "passive"))
      (node (ref "TP511") (pin "1") (pinfunction "1_1") (pintype "passive"))
      (node (ref "U17") (pin "B11") (pinfunction "PC10_/_UART4_TX_/_USART3_TX_/_SPI3_SCK_B11") (pintype "bidirectional"))
    )
    (net (code "96") (name "/PG_START") (class "Default")
      (node (ref "U17") (pin "A2") (pinfunction "PE3_A2") (pintype "bidirectional"))
      (node (ref "U306") (pin "2") (pinfunction "B_2") (pintype "input"))
    )
    (net (code "97") (name "/PH1_EN") (class "Default")
      (node (ref "U17") (pin "C8") (pinfunction "SPI2_MISO_/_SPI2_SCK_/_USART2_CTS_/_PD3_C8") (pintype "bidirectional"))
      (node (ref "U307") (pin "1") (pinfunction "1A_1") (pintype "input"))
    )
    (net (code "98") (name "/PH1_OUT") (class "Default")
      (node (ref "TP303") (pin "1") (pinfunction "1_1") (pintype "passive"))
      (node (ref "U303") (pin "6") (pinfunction "IN_6") (pintype "input"))
      (node (ref "U307") (pin "7") (pinfunction "1Y_7") (pintype "output"))
    )
    (net (code "99") (name "/PH2_EN") (class "Default")
      (node (ref "U17") (pin "A8") (pinfunction "USART2_TX_/_PD5_A8") (pintype "bidirectional"))
      (node (ref "U307") (pin "6") (pinfunction "2B_6") (pintype "input"))
    )
    (net (code "100") (name "/PH2_OUT") (class "Default")
      (node (ref "TP304") (pin "1") (pinfunction "1_1") (pintype "passive"))
      (node (ref "U304") (pin "6") (pinfunction "IN_6") (pintype "input"))
      (node (ref "U307") (pin "3") (pinfunction "2Y_3") (pintype "output"))
    )
    (net (code "101") (name "/REC1") (class "Default")
      (node (ref "U30") (pin "5") (pinfunction "S2B_5") (pintype "passive"))
      (node (ref "U31") (pin "11") (pinfunction "D3_11") (pintype "passive"))
    )
    (net (code "102") (name "/REC2") (class "Default")
      (node (ref "U30") (pin "2") (pinfunction "S1B_2") (pintype "passive"))
      (node (ref "U31") (pin "15") (pinfunction "D4_15") (pintype "passive"))
    )
    (net (code "103") (name "/REC3") (class "Default")
      (node (ref "U30") (pin "14") (pinfunction "S4B_14") (pintype "passive"))
      (node (ref "U31") (pin "1") (pinfunction "D1_1") (pintype "passive"))
    )
    (net (code "104") (name "/REC4") (class "Default")
      (node (ref "U30") (pin "12") (pinfunction "S3B_12") (pintype "passive"))
      (node (ref "U31") (pin "6") (pinfunction "D2_6") (pintype "passive"))
    )
    (net (code "105") (name "/SNK1") (class "Default")
      (node (ref "M301") (pin "1") (pinfunction "G_1") (pintype "passive"))
      (node (ref "U17") (pin "D7") (pinfunction "USART2_CK_/_PD7_D7") (pintype "bidirectional"))
    )
    (net (code "106") (name "/SNK2") (class "Default")
      (node (ref "M302") (pin "1") (pinfunction "G_1") (pintype "passive"))
      (node (ref "U17") (pin "J10") (pinfunction "USART3_RX_/_PD9_J10") (pintype "bidirectional"))
    )
    (net (code "107") (name "/SNK3") (class "Default")
      (node (ref "M303") (pin "1") (pinfunction "G_1") (pintype "passive"))
      (node (ref "U17") (pin "J11") (pinfunction "I2C4_SMBA_/_USART3_CTS_/_ADC4_IN15_/_PD11_J11") (pintype "bidirectional"))
    )
    (net (code "108") (name "/SNK4") (class "Default")
      (node (ref "M304") (pin "1") (pinfunction "G_1") (pintype "passive"))
      (node (ref "U17") (pin "H11") (pinfunction "I2C4_SDA_/_ADC4_IN17_/_PD13_H11") (pintype "bidirectional"))
    )
    (net (code "109") (name "/SNK17") (class "Default")
      (node (ref "M317") (pin "1") (pinfunction "G_1") (pintype "passive"))
      (node (ref "U17") (pin "H12") (pinfunction "PD15_H12") (pintype "bidirectional"))
    )
    (net (code "110") (name "/SRC1") (class "Default")
      (node (ref "Q321") (pin "1") (pinfunction "B_1") (pintype "passive"))
      (node (ref "U17") (pin "A7") (pinfunction "SPI3_MOSI_/_USART2_RX_/_PD6_A7") (pintype "bidirectional"))
    )
    (net (code "111") (name "/SRC2") (class "Default")
      (node (ref "Q322") (pin "1") (pinfunction "B_1") (pintype "passive"))
      (node (ref "U17") (pin "L12") (pinfunction "USART3_TX_/_PD8_L12") (pintype "bidirectional"))
    )
    (net (code "112") (name "/SRC3") (class "Default")
      (node (ref "Q323") (pin "1") (pinfunction "B_1") (pintype "passive"))
      (node (ref "U17") (pin "M12") (pinfunction "USART3_CK_/_PD10_M12") (pintype "bidirectional"))
    )
    (net (code "113") (name "/SRC4") (class "Default")
      (node (ref "Q324") (pin "1") (pinfunction "B_1") (pintype "passive"))
      (node (ref "U17") (pin "J12") (pinfunction "I2C4_SCL_/_USART3_RTS_/_ADC4_IN16_/_PD12_J12") (pintype "bidirectional"))
    )
    (net (code "114") (name "/SRC17") (class "Default")
      (node (ref "Q337") (pin "1") (pinfunction "B_1") (pintype "passive"))
      (node (ref "U17") (pin "H10") (pinfunction "PD14_H10") (pintype "bidirectional"))
    )
    (net (code "115") (name "/SR_SEL1") (class "Default")
      (node (ref "U17") (pin "D2") (pinfunction "I2C2_SDA_/_PF0_D2") (pintype "bidirectional"))
      (node (ref "U30") (pin "19") (pinfunction "IN1_19") (pintype "input"))
      (node (ref "U30") (pin "8") (pinfunction "IN2_8") (pintype "input"))
    )
    (net (code "116") (name "/SR_SEL2") (class "Default")
      (node (ref "U17") (pin "E2") (pinfunction "I2C2_SCL_/_PF1_E2") (pintype "bidirectional"))
      (node (ref "U30") (pin "17") (pinfunction "IN4_17") (pintype "input"))
      (node (ref "U30") (pin "9") (pinfunction "IN3_9") (pintype "input"))
    )
    (net (code "117") (name "/STIM1") (class "Default")
      (node (ref "C381") (pin "2") (pinfunction "2_2") (pintype "passive"))
      (node (ref "U30") (pin "7") (pinfunction "S2A_7") (pintype "passive"))
    )
    (net (code "118") (name "/STIM2") (class "Default")
      (node (ref "C382") (pin "2") (pinfunction "2_2") (pintype "passive"))
      (node (ref "U30") (pin "20") (pinfunction "S1A_20") (pintype "passive"))
    )
    (net (code "119") (name "/STIM3") (class "Default")
      (node (ref "C383") (pin "2") (pinfunction "2_2") (pintype "passive"))
      (node (ref "U30") (pin "16") (pinfunction "S4A_16") (pintype "passive"))
    )
    (net (code "120") (name "/STIM4") (class "Default")
      (node (ref "C384") (pin "2") (pinfunction "2_2") (pintype "passive"))
      (node (ref "U30") (pin "10") (pinfunction "S3A_10") (pintype "passive"))
    )
    (net (code "121") (name "/STIM_EN") (class "Default")
      (node (ref "U17") (pin "B3") (pinfunction "PE2_B3") (pintype "bidirectional"))
      (node (ref "U305") (pin "B2") (pinfunction "~{SHDN}_B2") (pintype "input"))
    )
    (net (code "122") (name "/SWCLK") (class "Default")
      (node (ref "J908") (pin "4") (pinfunction "4_4") (pintype "passive"))
      (node (ref "J910") (pin "4") (pinfunction "4_4") (pintype "passive"))
      (node (ref "TP40") (pin "1") (pinfunction "1_1") (pintype "passive"))
      (node (ref "U17") (pin "C11") (pinfunction "PA14_/_JTCK_/_SWCLK_C11") (pintype "bidirectional"))
    )
    (net (code "123") (name "/SWDIO") (class "Default")
      (node (ref "J908") (pin "3") (pinfunction "3_3") (pintype "passive"))
      (node (ref "J910") (pin "2") (pinfunction "2_2") (pintype "passive"))
      (node (ref "TP41") (pin "1") (pinfunction "1_1") (pintype "passive"))
      (node (ref "U17") (pin "C10") (pinfunction "PA13_/_JTMS_/_SWDIO_C10") (pintype "bidirectional"))
    )
    (net (code "124") (name "/SWO") (class "Default")
      (node (ref "J908") (pin "6") (pinfunction "6_6") (pintype "passive"))
      (node (ref "J910") (pin "6") (pinfunction "6_6") (pintype "passive"))
      (node (ref "TP48") (pin "1") (pinfunction "1_1") (pintype "passive"))
      (node (ref "U17") (pin "C6") (pinfunction "PB3_/_SWO_/_JTDO_/_USART1_RTS_/_SPI1_SCK_/_SPI3_SCK_/_I2C1_SDA_C6") (pintype "bidirectional"))
    )
    (net (code "125") (name "/SYS_RSTn") (class "Default")
      (node (ref "J908") (pin "5") (pinfunction "5_5") (pintype "passive"))
      (node (ref "J910") (pin "10") (pinfunction "10_10") (pintype "passive"))
      (node (ref "R54") (pin "2") (pinfunction "2_2") (pintype "passive"))
      (node (ref "TP43") (pin "1") (pinfunction "1_1") (pintype "passive"))
      (node (ref "U17") (pin "G2") (pinfunction "NRST_G2") (pintype "bidirectional"))
      (node (ref "U18") (pin "1") (pinfunction "~{RESET}_1") (pintype "passive"))
    )
    (net (code "126") (name "/TEMP_EN") (class "Default")
      (node (ref "R42") (pin "1") (pinfunction "1_1") (pintype "passive"))
      (node (ref "R44") (pin "1") (pinfunction "1_1") (pintype "passive"))
      (node (ref "TP36") (pin "1") (pinfunction "1_1") (pintype "passive"))
      (node (ref "U14") (pin "A2") (pinfunction "V+_A2") (pintype "power_in"))
      (node (ref "U15") (pin "A2") (pinfunction "V+_A2") (pintype "power_in"))
      (node (ref "U16") (pin "A2") (pinfunction "V+_A2") (pintype "power_in"))
      (node (ref "U17") (pin "F11") (pinfunction "PC6_F11") (pintype "bidirectional"))
    )
    (net (code "127") (name "/TEST_TRIG") (class "Default")
      (node (ref "TP49") (pin "1") (pinfunction "1_1") (pintype "passive"))
      (node (ref "U17") (pin "M6") (pinfunction "ADC4_IN7_/_PG0_M6") (pintype "bidirectional"))
    )
    (net (code "128") (name "/THERM_OFST") (class "Default")
      (node (ref "TP39") (pin "1") (pinfunction "1_1") (pintype "passive"))
      (node (ref "U16") (pin "A1") (pinfunction "OUT_A1") (pintype "passive"))
      (node (ref "U16") (pin "C2") (pinfunction "IN-_C2") (pintype "passive"))
      (node (ref "U17") (pin "H2") (pinfunction "PC0_/_ADC1_IN1_/_ADC4_IN1_/_LPUART1_RX_/_I2C3_SCL_H2") (pintype "bidirectional"))
    )
    (net (code "129") (name "/THERM_OUT") (class "Default")
      (node (ref "TP38") (pin "1") (pinfunction "1_1") (pintype "passive"))
      (node (ref "U15") (pin "A1") (pinfunction "OUT_A1") (pintype "passive"))
      (node (ref "U15") (pin "C2") (pinfunction "IN-_C2") (pintype "passive"))
      (node (ref "U17") (pin "G3") (pinfunction "PC1_/_ADC1_IN2_/_ADC4_IN2_/_SPI2_MOSI_/_LPUART1_TX_/_I2C3_SDA_G3") (pintype "bidirectional"))
    )
    (net (code "130") (name "/THERM_REF") (class "Default")
      (node (ref "TP37") (pin "1") (pinfunction "1_1") (pintype "passive"))
      (node (ref "U14") (pin "A1") (pinfunction "OUT_A1") (pintype "passive"))
      (node (ref "U14") (pin "C2") (pinfunction "IN-_C2") (pintype "passive"))
      (node (ref "U17") (pin "F3") (pinfunction "PC2_/_ADC1_IN3_/_ADC4_IN3_/_SPI2_MISO_F3") (pintype "bidirectional"))
    )
    (net (code "131") (name "/TX_BLANK") (class "Default")
      (node (ref "M512") (pin "1") (pinfunction "G_1") (pintype "passive"))
      (node (ref "U17") (pin "E11") (pinfunction "PC9_E11") (pintype "bidirectional"))
    )
    (net (code "132") (name "/VCHG_PGOOD") (class "Default")
      (node (ref "U17") (pin "B10") (pinfunction "PC12_/_UART5_TX_/_USART3_CK_/_SPI3_MOSI_B10") (pintype "bidirectional"))
      (node (ref "U503") (pin "13") (pinfunction "PGOOD_13") (pintype "open_collector"))
    )
    (net (code "133") (name "/VDDA_EN") (class "Default")
      (node (ref "U10") (pin "3") (pinfunction "EN_3") (pintype "passive"))
      (node (ref "U17") (pin "A3") (pinfunction "PE1_A3") (pintype "bidirectional"))
    )
    (net (code "134") (name "/VDDS_EN") (class "Default")
      (node (ref "U11") (pin "3") (pinfunction "EN_3") (pintype "passive"))
      (node (ref "U17") (pin "C4") (pinfunction "PE0_C4") (pintype "bidirectional"))
    )
    (net (code "135") (name "/VPPSW_EN") (class "Default")
      (node (ref "M34") (pin "1") (pinfunction "G_1") (pintype "passive"))
      (node (ref "U17") (pin "K12") (pinfunction "PB15_/_SPI2_MOSI_/_WKUP7_K12") (pintype "bidirectional"))
    )
    (net (code "136") (name "/VRECT_DET") (class "Default")
      (node (ref "M504") (pin "3") (pinfunction "D_3") (pintype "passive"))
      (node (ref "R506") (pin "1") (pinfunction "1_1") (pintype "passive"))
      (node (ref "TP505") (pin "1") (pinfunction "1_1") (pintype "passive"))
      (node (ref "U17") (pin "C3") (pinfunction "PC13_/_WKUP2_C3") (pintype "bidirectional"))
    )
    (net (code "137") (name "/VRECT_MON") (class "Default")
      (node (ref "TP508") (pin "1") (pinfunction "1_1") (pintype "passive"))
      (node (ref "U17") (pin "F4") (pinfunction "PC3_/_ADC1_IN4_/_ADC4_IN4_/_SPI2_MOSI_F4") (pintype "bidirectional"))
      (node (ref "U501") (pin "A1") (pinfunction "OUT_A1") (pintype "passive"))
      (node (ref "U501") (pin "C2") (pinfunction "IN-_C2") (pintype "passive"))
    )
    (net (code "138") (name "/VRECT_MON_EN") (class "Default")
      (node (ref "M509") (pin "1") (pinfunction "G_1") (pintype "passive"))
      (node (ref "TP507") (pin "1") (pinfunction "1_1") (pintype "passive"))
      (node (ref "U17") (pin "M3") (pinfunction "PC4_/_ADC1_IN13_/_ADC4_IN22_M3") (pintype "bidirectional"))
      (node (ref "U501") (pin "A2") (pinfunction "V+_A2") (pintype "power_in"))
    )
    (net (code "139") (name "/VRECT_OVP") (class "Default")
      (node (ref "M507") (pin "3") (pinfunction "D_3") (pintype "passive"))
      (node (ref "R512") (pin "1") (pinfunction "1_1") (pintype "passive"))
      (node (ref "TP506") (pin "1") (pinfunction "1_1") (pintype "passive"))
      (node (ref "U17") (pin "J3") (pinfunction "PC5_/_ADC1_IN14_/_ADC4_IN23_/_WKUP5_J3") (pintype "bidirectional"))
    )
    (net (code "140") (name "DVDD") (class "Default")
      (node (ref "C17") (pin "2") (pinfunction "2_2") (pintype "passive"))
      (node (ref "C26") (pin "1") (pinfunction "1_1") (pintype "passive"))
      (node (ref "C27") (pin "2") (pinfunction "2_2") (pintype "passive"))
      (node (ref "C28") (pin "2") (pinfunction "2_2") (pintype "passive"))
      (node (ref "C29") (pin "2") (pinfunction "2_2") (pintype "passive"))
      (node (ref "C30") (pin "2") (pinfunction "2_2") (pintype "passive"))
      (node (ref "C31") (pin "2") (pinfunction "2_2") (pintype "passive"))
      (node (ref "C32") (pin "2") (pinfunction "2_2") (pintype "passive"))
      (node (ref "C36") (pin "2") (pinfunction "2_2") (pintype "passive"))
      (node (ref "C37") (pin "1") (pinfunction "1_1") (pintype "passive"))
      (node (ref "C38") (pin "2") (pinfunction "2_2") (pintype "passive"))
      (node (ref "C46") (pin "1") (pinfunction "1_1") (pintype "passive"))
      (node (ref "C5") (pin "2") (pinfunction "2_2") (pintype "passive"))
      (node (ref "J908") (pin "1") (pinfunction "1_1") (pintype "passive"))
      (node (ref "J909") (pin "3") (pinfunction "3_3") (pintype "passive"))
      (node (ref "J910") (pin "1") (pinfunction "1_1") (pintype "passive"))
      (node (ref "L6") (pin "1") (pinfunction "1_1") (pintype "passive"))
      (node (ref "M27") (pin "2") (pinfunction "S_2") (pintype "passive"))
      (node (ref "M504") (pin "2") (pinfunction "S_2") (pintype "passive"))
      (node (ref "M507") (pin "2") (pinfunction "S_2") (pintype "passive"))
      (node (ref "M91") (pin "2") (pinfunction "S_2") (pintype "passive"))
      (node (ref "R30") (pin "1") (pinfunction "1_1") (pintype "passive"))
      (node (ref "R47") (pin "2") (pinfunction "2_2") (pintype "passive"))
      (node (ref "R48") (pin "2") (pinfunction "2_2") (pintype "passive"))
      (node (ref "R54") (pin "1") (pinfunction "1_1") (pintype "passive"))
      (node (ref "TP12") (pin "1") (pinfunction "1_1") (pintype "passive"))
      (node (ref "TP42") (pin "1") (pinfunction "1_1") (pintype "passive"))
      (node (ref "U1") (pin "1") (pinfunction "OUT_1") (pintype "passive"))
      (node (ref "U17") (pin "A12") (pinfunction "VDDUSB_A12") (pintype "power_in"))
      (node (ref "U17") (pin "D4") (pinfunction "VDD_D4") (pintype "power_in"))
      (node (ref "U17") (pin "D8") (pinfunction "VDDIO2_D8") (pintype "power_in"))
      (node (ref "U17") (pin "D9") (pinfunction "VDD_D9") (pintype "power_in"))
      (node (ref "U17") (pin "F7") (pinfunction "VDD_F7") (pintype "power_in"))
      (node (ref "U17") (pin "G6") (pinfunction "VDD_G6") (pintype "power_in"))
      (node (ref "U17") (pin "J4") (pinfunction "VDD_J4") (pintype "power_in"))
      (node (ref "U17") (pin "J9") (pinfunction "VDD_J9") (pintype "power_in"))
      (node (ref "U18") (pin "4") (pinfunction "VDD_4") (pintype "passive"))
    )
    (net (code "141") (name "GND") (class "Default")
      (node (ref "C10") (pin "2") (pinfunction "2_2") (pintype "passive"))
      (node (ref "C11") (pin "1") (pinfunction "1_1") (pintype "passive"))
      (node (ref "C12") (pin "1") (pinfunction "1_1") (pintype "passive"))
      (node (ref "C13") (pin "1") (pinfunction "1_1") (pintype "passive"))
      (node (ref "C14") (pin "1") (pinfunction "1_1") (pintype "passive"))
      (node (ref "C15") (pin "2") (pinfunction "2_2") (pintype "passive"))
      (node (ref "C16") (pin "2") (pinfunction "2_2") (pintype "passive"))
      (node (ref "C17") (pin "1") (pinfunction "1_1") (pintype "passive"))
      (node (ref "C18") (pin "2") (pinfunction "2_2") (pintype "passive"))
      (node (ref "C19") (pin "2") (pinfunction "2_2") (pintype "passive"))
      (node (ref "C20") (pin "2") (pinfunction "2_2") (pintype "passive"))
      (node (ref "C206") (pin "1") (pinfunction "1_1") (pintype "passive"))
      (node (ref "C207") (pin "1") (pinfunction "1_1") (pintype "passive"))
      (node (ref "C21") (pin "2") (pinfunction "2_2") (pintype "passive"))
      (node (ref "C22") (pin "1") (pinfunction "1_1") (pintype "passive"))
      (node (ref "C23") (pin "1") (pinfunction "1_1") (pintype "passive"))
      (node (ref "C24") (pin "2") (pinfunction "2_2") (pintype "passive"))
      (node (ref "C246") (pin "1") (pinfunction "1_1") (pintype "passive"))
      (node (ref "C247") (pin "1") (pinfunction "1_1") (pintype "passive"))
      (node (ref "C25") (pin "2") (pinfunction "2_2") (pintype "passive"))
      (node (ref "C26") (pin "2") (pinfunction "2_2") (pintype "passive"))
      (node (ref "C27") (pin "1") (pinfunction "1_1") (pintype "passive"))
      (node (ref "C28") (pin "1") (pinfunction "1_1") (pintype "passive"))
      (node (ref "C29") (pin "1") (pinfunction "1_1") (pintype "passive"))
      (node (ref "C3") (pin "2") (pinfunction "2_2") (pintype "passive"))
      (node (ref "C30") (pin "1") (pinfunction "1_1") (pintype "passive"))
      (node (ref "C301") (pin "1") (pinfunction "1_1") (pintype "passive"))
      (node (ref "C303") (pin "1") (pinfunction "1_1") (pintype "passive"))
      (node (ref "C304") (pin "1") (pinfunction "1_1") (pintype "passive"))
      (node (ref "C306") (pin "1") (pinfunction "1_1") (pintype "passive"))
      (node (ref "C307") (pin "1") (pinfunction "1_1") (pintype "passive"))
      (node (ref "C31") (pin "1") (pinfunction "1_1") (pintype "passive"))
      (node (ref "C32") (pin "1") (pinfunction "1_1") (pintype "passive"))
      (node (ref "C33") (pin "1") (pinfunction "1_1") (pintype "passive"))
      (node (ref "C34") (pin "2") (pinfunction "2_2") (pintype "passive"))
      (node (ref "C35") (pin "1") (pinfunction "1_1") (pintype "passive"))
      (node (ref "C36") (pin "1") (pinfunction "1_1") (pintype "passive"))
      (node (ref "C37") (pin "2") (pinfunction "2_2") (pintype "passive"))
      (node (ref "C38") (pin "1") (pinfunction "1_1") (pintype "passive"))
      (node (ref "C39") (pin "1") (pinfunction "1_1") (pintype "passive"))
      (node (ref "C4") (pin "1") (pinfunction "1_1") (pintype "passive"))
      (node (ref "C45") (pin "1") (pinfunction "1_1") (pintype "passive"))
      (node (ref "C46") (pin "2") (pinfunction "2_2") (pintype "passive"))
      (node (ref "C5") (pin "1") (pinfunction "1_1") (pintype "passive"))
      (node (ref "C505") (pin "1") (pinfunction "1_1") (pintype "passive"))
      (node (ref "C506") (pin "1") (pinfunction "1_1") (pintype "passive"))
      (node (ref "C508") (pin "1") (pinfunction "1_1") (pintype "passive"))
      (node (ref "C509") (pin "1") (pinfunction "1_1") (pintype "passive"))
      (node (ref "C510") (pin "1") (pinfunction "1_1") (pintype "passive"))
      (node (ref "C511") (pin "2") (pinfunction "2_2") (pintype "passive"))
      (node (ref "C514") (pin "2") (pinfunction "2_2") (pintype "passive"))
      (node (ref "C6") (pin "1") (pinfunction "1_1") (pintype "passive"))
      (node (ref "C7") (pin "1") (pinfunction "1_1") (pintype "passive"))
      (node (ref "C8") (pin "1") (pinfunction "1_1") (pintype "passive"))
      (node (ref "C87") (pin "1") (pinfunction "1_1") (pintype "passive"))
      (node (ref "C88") (pin "1") (pinfunction "1_1") (pintype "passive"))
      (node (ref "C89") (pin "2") (pinfunction "2_2") (pintype "passive"))
      (node (ref "C9") (pin "1") (pinfunction "1_1") (pintype "passive"))
      (node (ref "C90") (pin "2") (pinfunction "2_2") (pintype "passive"))
      (node (ref "C91") (pin "1") (pinfunction "1_1") (pintype "passive"))
      (node (ref "C92") (pin "2") (pinfunction "2_2") (pintype "passive"))
      (node (ref "C93") (pin "1") (pinfunction "1_1") (pintype "passive"))
      (node (ref "C94") (pin "1") (pinfunction "1_1") (pintype "passive"))
      (node (ref "C95") (pin "2") (pinfunction "2_2") (pintype "passive"))
      (node (ref "C99") (pin "2") (pinfunction "2_2") (pintype "passive"))
      (node (ref "D417") (pin "1") (pinfunction "1_1") (pintype "passive"))
      (node (ref "D418") (pin "1") (pinfunction "1_1") (pintype "passive"))
      (node (ref "D503") (pin "2") (pinfunction "A_2") (pintype "passive"))
      (node (ref "D506") (pin "2") (pinfunction "A_2") (pintype "passive"))
      (node (ref "D507") (pin "2") (pinfunction "A_2") (pintype "passive"))
      (node (ref "F1") (pin "2") (pinfunction "2_2") (pintype "passive"))
      (node (ref "F2") (pin "2") (pinfunction "2_2") (pintype "passive"))
      (node (ref "J905") (pin "4") (pinfunction "4_4") (pintype "passive"))
      (node (ref "J906") (pin "2") (pinfunction "2_2") (pintype "passive"))
      (node (ref "J907") (pin "1") (pinfunction "1_1") (pintype "passive"))
      (node (ref "J908") (pin "2") (pinfunction "2_2") (pintype "passive"))
      (node (ref "J909") (pin "1") (pinfunction "1_1") (pintype "passive"))
      (node (ref "J910") (pin "3") (pinfunction "3_3") (pintype "passive"))
      (node (ref "J910") (pin "5") (pinfunction "5_5") (pintype "passive"))
      (node (ref "J910") (pin "9") (pinfunction "9_9") (pintype "passive"))
      (node (ref "J911") (pin "3") (pinfunction "3_3") (pintype "passive"))
      (node (ref "J911") (pin "5") (pinfunction "5_5") (pintype "passive"))
      (node (ref "J911") (pin "9") (pinfunction "9_9") (pintype "passive"))
      (node (ref "L97") (pin "2") (pinfunction "2_2") (pintype "passive"))
      (node (ref "L98") (pin "2") (pinfunction "2_2") (pintype "passive"))
      (node (ref "M11") (pin "2") (pinfunction "S_2") (pintype "passive"))
      (node (ref "M12") (pin "2") (pinfunction "S_2") (pintype "passive"))
      (node (ref "M14") (pin "2") (pinfunction "S_2") (pintype "passive"))
      (node (ref "M15") (pin "2") (pinfunction "S_2") (pintype "passive"))
      (node (ref "M16") (pin "2") (pinfunction "S_2") (pintype "passive"))
      (node (ref "M19") (pin "2") (pinfunction "S_2") (pintype "passive"))
      (node (ref "M20") (pin "2") (pinfunction "S_2") (pintype "passive"))
      (node (ref "M23") (pin "2") (pinfunction "S_2") (pintype "passive"))
      (node (ref "M25") (pin "2") (pinfunction "S_2") (pintype "passive"))
      (node (ref "M26") (pin "2") (pinfunction "S_2") (pintype "passive"))
      (node (ref "M29") (pin "2") (pinfunction "S_2") (pintype "passive"))
      (node (ref "M3") (pin "2") (pinfunction "S_2") (pintype "passive"))
      (node (ref "M301") (pin "2") (pinfunction "S_2") (pintype "passive"))
      (node (ref "M302") (pin "2") (pinfunction "S_2") (pintype "passive"))
      (node (ref "M303") (pin "2") (pinfunction "S_2") (pintype "passive"))
      (node (ref "M304") (pin "2") (pinfunction "S_2") (pintype "passive"))
      (node (ref "M31") (pin "2") (pinfunction "S_2") (pintype "passive"))
      (node (ref "M317") (pin "2") (pinfunction "S_2") (pintype "passive"))
      (node (ref "M319") (pin "2") (pinfunction "S_2") (pintype "passive"))
      (node (ref "M34") (pin "2") (pinfunction "S_2") (pintype "passive"))
      (node (ref "M4") (pin "2") (pinfunction "S_2") (pintype "passive"))
      (node (ref "M501") (pin "2") (pinfunction "S_2") (pintype "passive"))
      (node (ref "M502") (pin "2") (pinfunction "S_2") (pintype "passive"))
      (node (ref "M505") (pin "2") (pinfunction "S_2") (pintype "passive"))
      (node (ref "M506") (pin "1") (pinfunction "D_1") (pintype "passive"))
      (node (ref "M509") (pin "2") (pinfunction "S_2") (pintype "passive"))
      (node (ref "M511") (pin "2") (pinfunction "S_2") (pintype "passive"))
      (node (ref "M512") (pin "2") (pinfunction "S_2") (pintype "passive"))
      (node (ref "M513") (pin "2") (pinfunction "S_2") (pintype "passive"))
      (node (ref "M514") (pin "2") (pinfunction "S_2") (pintype "passive"))
      (node (ref "M6") (pin "2") (pinfunction "S_2") (pintype "passive"))
      (node (ref "M7") (pin "2") (pinfunction "S_2") (pintype "passive"))
      (node (ref "M8") (pin "2") (pinfunction "S_2") (pintype "passive"))
      (node (ref "R11") (pin "2") (pinfunction "2_2") (pintype "passive"))
      (node (ref "R19") (pin "2") (pinfunction "2_2") (pintype "passive"))
      (node (ref "R214") (pin "2") (pinfunction "2_2") (pintype "passive"))
      (node (ref "R215") (pin "2") (pinfunction "2_2") (pintype "passive"))
      (node (ref "R25") (pin "2") (pinfunction "2_2") (pintype "passive"))
      (node (ref "R254") (pin "2") (pinfunction "2_2") (pintype "passive"))
      (node (ref "R255") (pin "2") (pinfunction "2_2") (pintype "passive"))
      (node (ref "R276") (pin "2") (pinfunction "2_2") (pintype "passive"))
      (node (ref "R278") (pin "2") (pinfunction "2_2") (pintype "passive"))
      (node (ref "R279") (pin "2") (pinfunction "2_2") (pintype "passive"))
      (node (ref "R28") (pin "2") (pinfunction "2_2") (pintype "passive"))
      (node (ref "R304") (pin "2") (pinfunction "2_2") (pintype "passive"))
      (node (ref "R371") (pin "2") (pinfunction "2_2") (pintype "passive"))
      (node (ref "R372") (pin "2") (pinfunction "2_2") (pintype "passive"))
      (node (ref "R373") (pin "2") (pinfunction "2_2") (pintype "passive"))
      (node (ref "R374") (pin "2") (pinfunction "2_2") (pintype "passive"))
      (node (ref "R387") (pin "2") (pinfunction "2_2") (pintype "passive"))
      (node (ref "R39") (pin "2") (pinfunction "2_2") (pintype "passive"))
      (node (ref "R4") (pin "2") (pinfunction "2_2") (pintype "passive"))
      (node (ref "R43") (pin "2") (pinfunction "2_2") (pintype "passive"))
      (node (ref "R46") (pin "2") (pinfunction "2_2") (pintype "passive"))
      (node (ref "R503") (pin "2") (pinfunction "2_2") (pintype "passive"))
      (node (ref "R505") (pin "2") (pinfunction "2_2") (pintype "passive"))
      (node (ref "R506") (pin "2") (pinfunction "2_2") (pintype "passive"))
      (node (ref "R508") (pin "2") (pinfunction "2_2") (pintype "passive"))
      (node (ref "R51") (pin "2") (pinfunction "2_2") (pintype "passive"))
      (node (ref "R512") (pin "2") (pinfunction "2_2") (pintype "passive"))
      (node (ref "R516") (pin "2") (pinfunction "2_2") (pintype "passive"))
      (node (ref "R518") (pin "2") (pinfunction "2_2") (pintype "passive"))
      (node (ref "R52") (pin "2") (pinfunction "2_2") (pintype "passive"))
      (node (ref "R521") (pin "2") (pinfunction "2_2") (pintype "passive"))
      (node (ref "R528") (pin "2") (pinfunction "2_2") (pintype "passive"))
      (node (ref "R530") (pin "2") (pinfunction "2_2") (pintype "passive"))
      (node (ref "R55") (pin "1") (pinfunction "1_1") (pintype "passive"))
      (node (ref "R6") (pin "2") (pinfunction "2_2") (pintype "passive"))
      (node (ref "SW901") (pin "1") (pinfunction "1_1") (pintype "passive"))
      (node (ref "SW901") (pin "2") (pinfunction "2_2") (pintype "passive"))
      (node (ref "TP90") (pin "1") (pinfunction "1_1") (pintype "passive"))
      (node (ref "TP91") (pin "1") (pinfunction "1_1") (pintype "passive"))
      (node (ref "TP92") (pin "1") (pinfunction "1_1") (pintype "passive"))
      (node (ref "TP93") (pin "1") (pinfunction "1_1") (pintype "passive"))
      (node (ref "TP94") (pin "1") (pinfunction "1_1") (pintype "passive"))
      (node (ref "TP95") (pin "1") (pinfunction "1_1") (pintype "passive"))
      (node (ref "TP96") (pin "1") (pinfunction "1_1") (pintype "passive"))
      (node (ref "TP97") (pin "1") (pinfunction "1_1") (pintype "passive"))
      (node (ref "TP98") (pin "1") (pinfunction "1_1") (pintype "passive"))
      (node (ref "TP99") (pin "1") (pinfunction "1_1") (pintype "passive"))
      (node (ref "U1") (pin "2") (pinfunction "GND_2") (pintype "power_in"))
      (node (ref "U1") (pin "5") (pinfunction "EP_5") (pintype "passive"))
      (node (ref "U10") (pin "2") (pinfunction "GND_2") (pintype "power_in"))
      (node (ref "U10") (pin "5") (pinfunction "EP_5") (pintype "passive"))
      (node (ref "U11") (pin "2") (pinfunction "GND_2") (pintype "power_in"))
      (node (ref "U11") (pin "5") (pinfunction "EP_5") (pintype "passive"))
      (node (ref "U12") (pin "2") (pinfunction "GND_2") (pintype "power_in"))
      (node (ref "U13") (pin "3") (pinfunction "A0_3") (pintype "input"))
      (node (ref "U13") (pin "4") (pinfunction "A1_4") (pintype "input"))
      (node (ref "U13") (pin "9") (pinfunction "GND_9") (pintype "power_in"))
      (node (ref "U14") (pin "B1") (pinfunction "V-_B1") (pintype "power_in"))
      (node (ref "U15") (pin "B1") (pinfunction "V-_B1") (pintype "power_in"))
      (node (ref "U16") (pin "B1") (pinfunction "V-_B1") (pintype "power_in"))
      (node (ref "U17") (pin "E4") (pinfunction "VSS_E4") (pintype "power_in"))
      (node (ref "U17") (pin "E9") (pinfunction "VSS_E9") (pintype "power_in"))
      (node (ref "U17") (pin "F6") (pinfunction "VSS_F6") (pintype "power_in"))
      (node (ref "U17") (pin "G7") (pinfunction "VSS_G7") (pintype "power_in"))
      (node (ref "U17") (pin "H1") (pinfunction "VSSA_H1") (pintype "power_in"))
      (node (ref "U17") (pin "H4") (pinfunction "VSS_H4") (pintype "power_in"))
      (node (ref "U17") (pin "H9") (pinfunction "VSS_H9") (pintype "power_in"))
      (node (ref "U17") (pin "L10") (pinfunction "VCAP_/_VSSSMPS_L10") (pintype "power_in"))
      (node (ref "U18") (pin "3") (pinfunction "GND_3") (pintype "passive"))
      (node (ref "U18") (pin "5") (pinfunction "EP_5") (pintype "passive"))
      (node (ref "U2") (pin "1") (pinfunction "GND_1") (pintype "power_in"))
      (node (ref "U2") (pin "5") (pinfunction "~{EN}_5") (pintype "input"))
      (node (ref "U2") (pin "7") (pinfunction "EP_7") (pintype "power_in"))
      (node (ref "U201") (pin "A1") (pinfunction "GND_A1") (pintype "power_in"))
      (node (ref "U203") (pin "A1") (pinfunction "GND_A1") (pintype "power_in"))
      (node (ref "U3") (pin "B2") (pinfunction "V-_B2") (pintype "power_in"))
      (node (ref "U30") (pin "21") (pinfunction "EP_21") (pintype "power_in"))
      (node (ref "U30") (pin "3") (pinfunction "VSS_3") (pintype "power_in"))
      (node (ref "U30") (pin "4") (pinfunction "GND_4") (pintype "power_in"))
      (node (ref "U301") (pin "3") (pinfunction "RSTSEL_3") (pintype "input"))
      (node (ref "U301") (pin "4") (pinfunction "AGND_4") (pintype "power_in"))
      (node (ref "U301") (pin "5") (pinfunction "SPI2C_5") (pintype "input"))
      (node (ref "U303") (pin "2") (pinfunction "GND_2") (pintype "power_in"))
      (node (ref "U304") (pin "2") (pinfunction "GND_2") (pintype "power_in"))
      (node (ref "U305") (pin "A2") (pinfunction "V-_A2") (pintype "power_in"))
      (node (ref "U306") (pin "1") (pinfunction "~{A}_1") (pintype "input"))
      (node (ref "U306") (pin "4") (pinfunction "GND_4") (pintype "power_in"))
      (node (ref "U307") (pin "4") (pinfunction "GND_4") (pintype "power_in"))
      (node (ref "U308") (pin "16") (pinfunction "X6_16") (pintype "passive"))
      (node (ref "U308") (pin "17") (pinfunction "EP_17") (pintype "passive"))
      (node (ref "U308") (pin "2") (pinfunction "X7_2") (pintype "passive"))
      (node (ref "U308") (pin "3") (pinfunction "X5_3") (pintype "passive"))
      (node (ref "U308") (pin "6") (pinfunction "GND_6") (pintype "passive"))
      (node (ref "U309") (pin "16") (pinfunction "X6_16") (pintype "passive"))
      (node (ref "U309") (pin "17") (pinfunction "EP_17") (pintype "passive"))
      (node (ref "U309") (pin "2") (pinfunction "X7_2") (pintype "passive"))
      (node (ref "U309") (pin "3") (pinfunction "X5_3") (pintype "passive"))
      (node (ref "U309") (pin "6") (pinfunction "GND_6") (pintype "passive"))
      (node (ref "U31") (pin "21") (pinfunction "EP_21") (pintype "power_in"))
      (node (ref "U31") (pin "3") (pinfunction "VSS_3") (pintype "power_in"))
      (node (ref "U31") (pin "4") (pinfunction "GND_4") (pintype "power_in"))
      (node (ref "U310") (pin "A2") (pinfunction "V-_A2") (pintype "power_in"))
      (node (ref "U311") (pin "6") (pinfunction "VS-_6") (pintype "power_in"))
      (node (ref "U311") (pin "9") (pinfunction "EP_9") (pintype "passive"))
      (node (ref "U4") (pin "1") (pinfunction "GND_1") (pintype "power_in"))
      (node (ref "U4") (pin "5") (pinfunction "~{EN}_5") (pintype "input"))
      (node (ref "U4") (pin "7") (pinfunction "EP_7") (pintype "power_in"))
      (node (ref "U5") (pin "B2") (pinfunction "V-_B2") (pintype "power_in"))
      (node (ref "U501") (pin "B1") (pinfunction "V-_B1") (pintype "power_in"))
      (node (ref "U502") (pin "2") (pinfunction "V-_2") (pintype "power_in"))
      (node (ref "U503") (pin "10") (pinfunction "VS1_10") (pintype "input"))
      (node (ref "U503") (pin "11") (pinfunction "MODE_11") (pintype "input"))
      (node (ref "U503") (pin "12") (pinfunction "EXTVCC_12") (pintype "power_in"))
      (node (ref "U503") (pin "18") (pinfunction "PGND_18") (pintype "power_in"))
      (node (ref "U503") (pin "19") (pinfunction "PGND_19") (pintype "power_in"))
      (node (ref "U503") (pin "21") (pinfunction "EP_21") (pintype "power_in"))
      (node (ref "U503") (pin "7") (pinfunction "GND_7") (pintype "power_in"))
      (node (ref "U503") (pin "8") (pinfunction "GND_8") (pintype "power_in"))
      (node (ref "U6") (pin "B1") (pinfunction "V-_B1") (pintype "power_in"))
      (node (ref "U7") (pin "B1") (pinfunction "V-_B1") (pintype "power_in"))
      (node (ref "U8") (pin "4") (pinfunction "GND_4") (pintype "power_in"))
      (node (ref "U9") (pin "4") (pinfunction "VSS_4") (pintype "power_in"))
      (node (ref "U91") (pin "B3") (pinfunction "VSS_B3") (pintype "passive"))
      (node (ref "U91") (pin "B4") (pinfunction "VSS_B4") (pintype "passive"))
      (node (ref "U91") (pin "C1") (pinfunction "VSS_PA_C1") (pintype "passive"))
      (node (ref "U91") (pin "D3") (pinfunction "VSS_D3") (pintype "passive"))
      (node (ref "U91") (pin "D4") (pinfunction "VSS_D4") (pintype "passive"))
      (node (ref "U91") (pin "E3") (pinfunction "VSS_E3") (pintype "passive"))
      (node (ref "U91") (pin "E4") (pinfunction "VSS_E4") (pintype "passive"))
    )
    (net (code "142") (name "HVIN") (class "Default")
      (node (ref "C15") (pin "1") (pinfunction "1_1") (pintype "passive"))
      (node (ref "C16") (pin "1") (pinfunction "1_1") (pintype "passive"))
      (node (ref "L3") (pin "1") (pinfunction "1_1") (pintype "passive"))
      (node (ref "M28") (pin "3") (pinfunction "D_3") (pintype "passive"))
      (node (ref "M30") (pin "3") (pinfunction "D_3") (pintype "passive"))
      (node (ref "TP33") (pin "1") (pinfunction "1_1") (pintype "passive"))
      (node (ref "U12") (pin "5") (pinfunction "VIN_5") (pintype "power_in"))
    )
    (net (code "143") (name "Net-(C96-Pad2)") (class "Default")
      (node (ref "C96") (pin "2") (pinfunction "2_2") (pintype "passive"))
      (node (ref "C97") (pin "1") (pinfunction "1_1") (pintype "passive"))
      (node (ref "L97") (pin "1") (pinfunction "1_1") (pintype "passive"))
    )
    (net (code "144") (name "Net-(C97-Pad2)") (class "Default")
      (node (ref "C97") (pin "2") (pinfunction "2_2") (pintype "passive"))
      (node (ref "C98") (pin "1") (pinfunction "1_1") (pintype "passive"))
      (node (ref "L98") (pin "1") (pinfunction "1_1") (pintype "passive"))
    )
    (net (code "145") (name "Net-(C99-Pad1)") (class "Default")
      (node (ref "C99") (pin "1") (pinfunction "1_1") (pintype "passive"))
      (node (ref "L99") (pin "1") (pinfunction "1_1") (pintype "passive"))
    )
    (net (code "146") (name "Net-(C203-Pad2)") (class "Default")
      (node (ref "C203") (pin "2") (pinfunction "2_2") (pintype "passive"))
      (node (ref "R209") (pin "2") (pinfunction "2_2") (pintype "passive"))
      (node (ref "R210") (pin "1") (pinfunction "1_1") (pintype "passive"))
    )
    (net (code "147") (name "Net-(C243-Pad2)") (class "Default")
      (node (ref "C243") (pin "2") (pinfunction "2_2") (pintype "passive"))
      (node (ref "R249") (pin "2") (pinfunction "2_2") (pintype "passive"))
      (node (ref "R250") (pin "1") (pinfunction "1_1") (pintype "passive"))
    )
    (net (code "148") (name "Net-(C403-Pad2)") (class "Default")
      (node (ref "C403") (pin "2") (pinfunction "2_2") (pintype "passive"))
      (node (ref "D403") (pin "2") (pinfunction "2_2") (pintype "passive"))
      (node (ref "J403") (pin "1") (pinfunction "1_1") (pintype "passive"))
    )
    (net (code "149") (name "Net-(C404-Pad2)") (class "Default")
      (node (ref "C404") (pin "2") (pinfunction "2_2") (pintype "passive"))
      (node (ref "D404") (pin "2") (pinfunction "2_2") (pintype "passive"))
      (node (ref "J404") (pin "1") (pinfunction "1_1") (pintype "passive"))
    )
    (net (code "150") (name "Net-(C405-Pad2)") (class "Default")
      (node (ref "C405") (pin "2") (pinfunction "2_2") (pintype "passive"))
      (node (ref "D405") (pin "2") (pinfunction "2_2") (pintype "passive"))
      (node (ref "J405") (pin "1") (pinfunction "1_1") (pintype "passive"))
    )
    (net (code "151") (name "Net-(C406-Pad2)") (class "Default")
      (node (ref "C406") (pin "2") (pinfunction "2_2") (pintype "passive"))
      (node (ref "D406") (pin "2") (pinfunction "2_2") (pintype "passive"))
      (node (ref "J406") (pin "1") (pinfunction "1_1") (pintype "passive"))
    )
    (net (code "152") (name "Net-(C407-Pad2)") (class "Default")
      (node (ref "C407") (pin "2") (pinfunction "2_2") (pintype "passive"))
      (node (ref "D407") (pin "2") (pinfunction "2_2") (pintype "passive"))
      (node (ref "J407") (pin "1") (pinfunction "1_1") (pintype "passive"))
    )
    (net (code "153") (name "Net-(C408-Pad2)") (class "Default")
      (node (ref "C408") (pin "2") (pinfunction "2_2") (pintype "passive"))
      (node (ref "D408") (pin "2") (pinfunction "2_2") (pintype "passive"))
      (node (ref "J408") (pin "1") (pinfunction "1_1") (pintype "passive"))
    )
    (net (code "154") (name "Net-(C411-Pad2)") (class "Default")
      (node (ref "C411") (pin "2") (pinfunction "2_2") (pintype "passive"))
      (node (ref "D411") (pin "2") (pinfunction "2_2") (pintype "passive"))
      (node (ref "J411") (pin "1") (pinfunction "1_1") (pintype "passive"))
    )
    (net (code "155") (name "Net-(C412-Pad2)") (class "Default")
      (node (ref "C412") (pin "2") (pinfunction "2_2") (pintype "passive"))
      (node (ref "D412") (pin "2") (pinfunction "2_2") (pintype "passive"))
      (node (ref "J412") (pin "1") (pinfunction "1_1") (pintype "passive"))
    )
    (net (code "156") (name "Net-(C413-Pad2)") (class "Default")
      (node (ref "C413") (pin "2") (pinfunction "2_2") (pintype "passive"))
      (node (ref "D413") (pin "2") (pinfunction "2_2") (pintype "passive"))
      (node (ref "J413") (pin "1") (pinfunction "1_1") (pintype "passive"))
    )
    (net (code "157") (name "Net-(C414-Pad2)") (class "Default")
      (node (ref "C414") (pin "2") (pinfunction "2_2") (pintype "passive"))
      (node (ref "D414") (pin "2") (pinfunction "2_2") (pintype "passive"))
      (node (ref "J414") (pin "1") (pinfunction "1_1") (pintype "passive"))
    )
    (net (code "158") (name "Net-(C415-Pad2)") (class "Default")
      (node (ref "C415") (pin "2") (pinfunction "2_2") (pintype "passive"))
      (node (ref "D415") (pin "2") (pinfunction "2_2") (pintype "passive"))
      (node (ref "J415") (pin "1") (pinfunction "1_1") (pintype "passive"))
    )
    (net (code "159") (name "Net-(C416-Pad2)") (class "Default")
      (node (ref "C416") (pin "2") (pinfunction "2_2") (pintype "passive"))
      (node (ref "D416") (pin "2") (pinfunction "2_2") (pintype "passive"))
      (node (ref "J416") (pin "1") (pinfunction "1_1") (pintype "passive"))
    )
    (net (code "160") (name "Net-(C501-Pad1)") (class "Default")
      (node (ref "C501") (pin "1") (pinfunction "1_1") (pintype "passive"))
      (node (ref "C502") (pin "1") (pinfunction "1_1") (pintype "passive"))
      (node (ref "C503") (pin "1") (pinfunction "1_1") (pintype "passive"))
      (node (ref "C504") (pin "1") (pinfunction "1_1") (pintype "passive"))
      (node (ref "J501") (pin "1") (pinfunction "1_1") (pintype "passive"))
      (node (ref "TP501") (pin "1") (pinfunction "1_1") (pintype "passive"))
    )
    (net (code "161") (name "Net-(D1-A)") (class "Default")
      (node (ref "D1") (pin "2") (pinfunction "A_2") (pintype "passive"))
      (node (ref "M1") (pin "1") (pinfunction "G_1") (pintype "passive"))
      (node (ref "R1") (pin "2") (pinfunction "2_2") (pintype "passive"))
    )
    (net (code "162") (name "Net-(D1-K)") (class "Default")
      (node (ref "D1") (pin "1") (pinfunction "K_1") (pintype "passive"))
      (node (ref "D2") (pin "1") (pinfunction "K_1") (pintype "passive"))
      (node (ref "R3") (pin "1") (pinfunction "1_1") (pintype "passive"))
    )
    (net (code "163") (name "Net-(D2-A)") (class "Default")
      (node (ref "D2") (pin "2") (pinfunction "A_2") (pintype "passive"))
      (node (ref "M2") (pin "1") (pinfunction "G_1") (pintype "passive"))
      (node (ref "R2") (pin "2") (pinfunction "2_2") (pintype "passive"))
    )
    (net (code "164") (name "Net-(D6-A)") (class "Default")
      (node (ref "D6") (pin "2") (pinfunction "A_2") (pintype "passive"))
      (node (ref "M10") (pin "1") (pinfunction "D_1") (pintype "passive"))
      (node (ref "M9") (pin "1") (pinfunction "D_1") (pintype "passive"))
    )
    (net (code "165") (name "Net-(D7-A)") (class "Default")
      (node (ref "D7") (pin "2") (pinfunction "A_2") (pintype "passive"))
      (node (ref "M17") (pin "1") (pinfunction "D_1") (pintype "passive"))
      (node (ref "M18") (pin "1") (pinfunction "D_1") (pintype "passive"))
    )
    (net (code "166") (name "Net-(D8-A)") (class "Default")
      (node (ref "D8") (pin "2") (pinfunction "A_2") (pintype "passive"))
      (node (ref "M21") (pin "1") (pinfunction "G_1") (pintype "passive"))
      (node (ref "R23") (pin "2") (pinfunction "2_2") (pintype "passive"))
    )
    (net (code "167") (name "Net-(D8-K)") (class "Default")
      (node (ref "D8") (pin "1") (pinfunction "K_1") (pintype "passive"))
      (node (ref "D9") (pin "1") (pinfunction "K_1") (pintype "passive"))
      (node (ref "M23") (pin "3") (pinfunction "D_3") (pintype "passive"))
    )
    (net (code "168") (name "Net-(D9-A)") (class "Default")
      (node (ref "D9") (pin "2") (pinfunction "A_2") (pintype "passive"))
      (node (ref "M22") (pin "1") (pinfunction "G_1") (pintype "passive"))
      (node (ref "R26") (pin "2") (pinfunction "2_2") (pintype "passive"))
    )
    (net (code "169") (name "Net-(D10-K)") (class "Default")
      (node (ref "D10") (pin "1") (pinfunction "K_1") (pintype "passive"))
      (node (ref "R29") (pin "1") (pinfunction "1_1") (pintype "passive"))
    )
    (net (code "170") (name "Net-(D11-K)") (class "Default")
      (node (ref "D11") (pin "1") (pinfunction "K_1") (pintype "passive"))
      (node (ref "D12") (pin "1") (pinfunction "K_1") (pintype "passive"))
      (node (ref "D13") (pin "1") (pinfunction "K_1") (pintype "passive"))
      (node (ref "M30") (pin "2") (pinfunction "S_2") (pintype "passive"))
      (node (ref "R35") (pin "1") (pinfunction "1_1") (pintype "passive"))
      (node (ref "R36") (pin "1") (pinfunction "1_1") (pintype "passive"))
      (node (ref "R37") (pin "1") (pinfunction "1_1") (pintype "passive"))
      (node (ref "TP30") (pin "1") (pinfunction "1_1") (pintype "passive"))
    )
    (net (code "171") (name "Net-(D14-A)") (class "Default")
      (node (ref "D14") (pin "2") (pinfunction "A_2") (pintype "passive"))
      (node (ref "L3") (pin "2") (pinfunction "2_2") (pintype "passive"))
      (node (ref "U12") (pin "1") (pinfunction "SW_1") (pintype "passive"))
    )
    (net (code "172") (name "Net-(D14-K)") (class "Default")
      (node (ref "C20") (pin "1") (pinfunction "1_1") (pintype "passive"))
      (node (ref "C21") (pin "1") (pinfunction "1_1") (pintype "passive"))
      (node (ref "D14") (pin "1") (pinfunction "K_1") (pintype "passive"))
      (node (ref "M32") (pin "2") (pinfunction "S_2") (pintype "passive"))
      (node (ref "R38") (pin "1") (pinfunction "1_1") (pintype "passive"))
      (node (ref "R40") (pin "1") (pinfunction "1_1") (pintype "passive"))
      (node (ref "TP34") (pin "1") (pinfunction "1_1") (pintype "passive"))
    )
    (net (code "173") (name "Net-(D501-K)") (class "Default")
      (node (ref "D501") (pin "1") (pinfunction "K_1") (pintype "passive"))
      (node (ref "R501") (pin "1") (pinfunction "1_1") (pintype "passive"))
    )
    (net (code "174") (name "Net-(D505-A)") (class "Default")
      (node (ref "C501") (pin "2") (pinfunction "2_2") (pintype "passive"))
      (node (ref "C502") (pin "2") (pinfunction "2_2") (pintype "passive"))
      (node (ref "D505") (pin "2") (pinfunction "A_2") (pintype "passive"))
      (node (ref "D507") (pin "1") (pinfunction "K_1") (pintype "passive"))
      (node (ref "J502") (pin "1") (pinfunction "1_1") (pintype "passive"))
      (node (ref "TP502") (pin "1") (pinfunction "1_1") (pintype "passive"))
    )
    (net (code "175") (name "Net-(D508-A)") (class "Default")
      (node (ref "C507") (pin "2") (pinfunction "2_2") (pintype "passive"))
      (node (ref "D508") (pin "2") (pinfunction "A_2") (pintype "passive"))
      (node (ref "R517") (pin "2") (pinfunction "2_2") (pintype "passive"))
      (node (ref "R518") (pin "1") (pinfunction "1_1") (pintype "passive"))
    )
    (net (code "176") (name "Net-(D508-K)") (class "Default")
      (node (ref "C508") (pin "2") (pinfunction "2_2") (pintype "passive"))
      (node (ref "D508") (pin "1") (pinfunction "K_1") (pintype "passive"))
      (node (ref "M510") (pin "2") (pinfunction "S_2") (pintype "passive"))
      (node (ref "R519") (pin "1") (pinfunction "1_1") (pintype "passive"))
    )
    (net (code "177") (name "Net-(M3-D)") (class "Default")
      (node (ref "M3") (pin "3") (pinfunction "D_3") (pintype "passive"))
      (node (ref "R3") (pin "2") (pinfunction "2_2") (pintype "passive"))
    )
    (net (code "178") (name "Net-(M4-D)") (class "Default")
      (node (ref "M4") (pin "3") (pinfunction "D_3") (pintype "passive"))
      (node (ref "R5") (pin "2") (pinfunction "2_2") (pintype "passive"))
      (node (ref "U1") (pin "3") (pinfunction "EN_3") (pintype "passive"))
    )
    (net (code "179") (name "Net-(M5-D)") (class "Default")
      (node (ref "C18") (pin "1") (pinfunction "1_1") (pintype "passive"))
      (node (ref "M5") (pin "3") (pinfunction "D_3") (pintype "passive"))
      (node (ref "TP13") (pin "1") (pinfunction "1_1") (pintype "passive"))
      (node (ref "U2") (pin "4") (pinfunction "VCC_4") (pintype "power_in"))
    )
    (net (code "180") (name "Net-(M5-G)") (class "Default")
      (node (ref "M5") (pin "1") (pinfunction "G_1") (pintype "passive"))
      (node (ref "M6") (pin "3") (pinfunction "D_3") (pintype "passive"))
      (node (ref "R7") (pin "2") (pinfunction "2_2") (pintype "passive"))
    )
    (net (code "181") (name "Net-(M7-D)") (class "Default")
      (node (ref "M7") (pin "3") (pinfunction "D_3") (pintype "passive"))
      (node (ref "R8") (pin "2") (pinfunction "2_2") (pintype "passive"))
    )
    (net (code "182") (name "Net-(M8-D)") (class "Default")
      (node (ref "M8") (pin "3") (pinfunction "D_3") (pintype "passive"))
      (node (ref "R9") (pin "2") (pinfunction "2_2") (pintype "passive"))
    )
    (net (code "183") (name "Net-(M10-G)") (class "Default")
      (node (ref "M10") (pin "2") (pinfunction "G_2") (pintype "passive"))
      (node (ref "M11") (pin "3") (pinfunction "D_3") (pintype "passive"))
      (node (ref "R13") (pin "2") (pinfunction "2_2") (pintype "passive"))
    )
    (net (code "184") (name "Net-(M12-G)") (class "Default")
      (node (ref "M12") (pin "1") (pinfunction "G_1") (pintype "passive"))
      (node (ref "M9") (pin "2") (pinfunction "G_2") (pintype "passive"))
      (node (ref "R12") (pin "2") (pinfunction "2_2") (pintype "passive"))
      (node (ref "TP15") (pin "1") (pinfunction "1_1") (pintype "passive"))
      (node (ref "U3") (pin "A1") (pinfunction "OUT_A1") (pintype "power_in"))
    )
    (net (code "185") (name "Net-(M13-D)") (class "Default")
      (node (ref "C19") (pin "1") (pinfunction "1_1") (pintype "passive"))
      (node (ref "M13") (pin "3") (pinfunction "D_3") (pintype "passive"))
      (node (ref "TP17") (pin "1") (pinfunction "1_1") (pintype "passive"))
      (node (ref "U4") (pin "4") (pinfunction "VCC_4") (pintype "power_in"))
    )
    (net (code "186") (name "Net-(M13-G)") (class "Default")
      (node (ref "M13") (pin "1") (pinfunction "G_1") (pintype "passive"))
      (node (ref "M14") (pin "3") (pinfunction "D_3") (pintype "passive"))
      (node (ref "R15") (pin "2") (pinfunction "2_2") (pintype "passive"))
    )
    (net (code "187") (name "Net-(M15-D)") (class "Default")
      (node (ref "M15") (pin "3") (pinfunction "D_3") (pintype "passive"))
      (node (ref "R16") (pin "2") (pinfunction "2_2") (pintype "passive"))
    )
    (net (code "188") (name "Net-(M16-D)") (class "Default")
      (node (ref "M16") (pin "3") (pinfunction "D_3") (pintype "passive"))
      (node (ref "R17") (pin "2") (pinfunction "2_2") (pintype "passive"))
    )
    (net (code "189") (name "Net-(M17-G)") (class "Default")
      (node (ref "M17") (pin "2") (pinfunction "G_2") (pintype "passive"))
      (node (ref "M20") (pin "1") (pinfunction "G_1") (pintype "passive"))
      (node (ref "R20") (pin "2") (pinfunction "2_2") (pintype "passive"))
      (node (ref "TP19") (pin "1") (pinfunction "1_1") (pintype "passive"))
      (node (ref "U5") (pin "A1") (pinfunction "OUT_A1") (pintype "power_in"))
    )
    (net (code "190") (name "Net-(M18-G)") (class "Default")
      (node (ref "M18") (pin "2") (pinfunction "G_2") (pintype "passive"))
      (node (ref "M19") (pin "3") (pinfunction "D_3") (pintype "passive"))
      (node (ref "R21") (pin "2") (pinfunction "2_2") (pintype "passive"))
    )
    (net (code "191") (name "Net-(M21-D)") (class "Default")
      (node (ref "M21") (pin "3") (pinfunction "D_3") (pintype "passive"))
      (node (ref "R24") (pin "1") (pinfunction "1_1") (pintype "passive"))
    )
    (net (code "192") (name "Net-(M22-D)") (class "Default")
      (node (ref "M22") (pin "3") (pinfunction "D_3") (pintype "passive"))
      (node (ref "R27") (pin "1") (pinfunction "1_1") (pintype "passive"))
    )
    (net (code "193") (name "Net-(M24-D)") (class "Default")
      (node (ref "C10") (pin "1") (pinfunction "1_1") (pintype "passive"))
      (node (ref "M24") (pin "3") (pinfunction "D_3") (pintype "passive"))
      (node (ref "M25") (pin "1") (pinfunction "G_1") (pintype "passive"))
      (node (ref "R34") (pin "1") (pinfunction "1_1") (pintype "passive"))
    )
    (net (code "194") (name "Net-(M24-S)") (class "Default")
      (node (ref "M24") (pin "2") (pinfunction "S_2") (pintype "passive"))
      (node (ref "R33") (pin "2") (pinfunction "2_2") (pintype "passive"))
    )
    (net (code "195") (name "Net-(M26-D)") (class "Default")
      (node (ref "M26") (pin "3") (pinfunction "D_3") (pintype "passive"))
      (node (ref "R34") (pin "2") (pinfunction "2_2") (pintype "passive"))
    )
    (net (code "196") (name "Net-(M28-G)") (class "Default")
      (node (ref "M28") (pin "1") (pinfunction "G_1") (pintype "passive"))
      (node (ref "M29") (pin "3") (pinfunction "D_3") (pintype "passive"))
      (node (ref "R36") (pin "2") (pinfunction "2_2") (pintype "passive"))
    )
    (net (code "197") (name "Net-(M28-S)") (class "Default")
      (node (ref "M28") (pin "2") (pinfunction "S_2") (pintype "passive"))
      (node (ref "R35") (pin "2") (pinfunction "2_2") (pintype "passive"))
    )
    (net (code "198") (name "Net-(M30-G)") (class "Default")
      (node (ref "M30") (pin "1") (pinfunction "G_1") (pintype "passive"))
      (node (ref "M31") (pin "3") (pinfunction "D_3") (pintype "passive"))
      (node (ref "R37") (pin "2") (pinfunction "2_2") (pintype "passive"))
    )
    (net (code "199") (name "Net-(M31-G)") (class "Default")
      (node (ref "C39") (pin "2") (pinfunction "2_2") (pintype "passive"))
      (node (ref "M31") (pin "1") (pinfunction "G_1") (pintype "passive"))
      (node (ref "R53") (pin "2") (pinfunction "2_2") (pintype "passive"))
      (node (ref "TP32") (pin "1") (pinfunction "1_1") (pintype "passive"))
    )
    (net (code "200") (name "Net-(M32-G)") (class "Default")
      (node (ref "M32") (pin "1") (pinfunction "G_1") (pintype "passive"))
      (node (ref "R40") (pin "2") (pinfunction "2_2") (pintype "passive"))
      (node (ref "R41") (pin "1") (pinfunction "1_1") (pintype "passive"))
    )
    (net (code "201") (name "Net-(M33-D)") (class "Default")
      (node (ref "M33") (pin "3") (pinfunction "D_3") (pintype "passive"))
      (node (ref "R45") (pin "1") (pinfunction "1_1") (pintype "passive"))
      (node (ref "U14") (pin "C1") (pinfunction "IN+_C1") (pintype "passive"))
    )
    (net (code "202") (name "Net-(M33-G)") (class "Default")
      (node (ref "M33") (pin "1") (pinfunction "G_1") (pintype "passive"))
      (node (ref "R42") (pin "2") (pinfunction "2_2") (pintype "passive"))
      (node (ref "R43") (pin "1") (pinfunction "1_1") (pintype "passive"))
    )
    (net (code "203") (name "Net-(M33-S)") (class "Default")
      (node (ref "M33") (pin "2") (pinfunction "S_2") (pintype "passive"))
      (node (ref "R44") (pin "2") (pinfunction "2_2") (pintype "passive"))
    )
    (net (code "204") (name "Net-(M34-D)") (class "Default")
      (node (ref "M34") (pin "3") (pinfunction "D_3") (pintype "passive"))
      (node (ref "R41") (pin "2") (pinfunction "2_2") (pintype "passive"))
    )
    (net (code "205") (name "Net-(M301-D)") (class "Default")
      (node (ref "C381") (pin "1") (pinfunction "1_1") (pintype "passive"))
      (node (ref "M301") (pin "3") (pinfunction "D_3") (pintype "passive"))
      (node (ref "Q301") (pin "6") (pinfunction "C2_6") (pintype "passive"))
      (node (ref "R351") (pin "1") (pinfunction "1_1") (pintype "passive"))
    )
    (net (code "206") (name "Net-(M302-D)") (class "Default")
      (node (ref "C382") (pin "1") (pinfunction "1_1") (pintype "passive"))
      (node (ref "M302") (pin "3") (pinfunction "D_3") (pintype "passive"))
      (node (ref "Q302") (pin "6") (pinfunction "C2_6") (pintype "passive"))
      (node (ref "R352") (pin "1") (pinfunction "1_1") (pintype "passive"))
    )
    (net (code "207") (name "Net-(M303-D)") (class "Default")
      (node (ref "C383") (pin "1") (pinfunction "1_1") (pintype "passive"))
      (node (ref "M303") (pin "3") (pinfunction "D_3") (pintype "passive"))
      (node (ref "Q303") (pin "6") (pinfunction "C2_6") (pintype "passive"))
      (node (ref "R353") (pin "1") (pinfunction "1_1") (pintype "passive"))
    )
    (net (code "208") (name "Net-(M304-D)") (class "Default")
      (node (ref "C384") (pin "1") (pinfunction "1_1") (pintype "passive"))
      (node (ref "M304") (pin "3") (pinfunction "D_3") (pintype "passive"))
      (node (ref "Q304") (pin "6") (pinfunction "C2_6") (pintype "passive"))
      (node (ref "R354") (pin "1") (pinfunction "1_1") (pintype "passive"))
    )
    (net (code "209") (name "Net-(M317-D)") (class "Default")
      (node (ref "C397") (pin "1") (pinfunction "1_1") (pintype "passive"))
      (node (ref "M317") (pin "3") (pinfunction "D_3") (pintype "passive"))
      (node (ref "Q317") (pin "6") (pinfunction "C2_6") (pintype "passive"))
      (node (ref "R367") (pin "1") (pinfunction "1_1") (pintype "passive"))
    )
    (net (code "210") (name "Net-(M318-G)") (class "Default")
      (node (ref "M318") (pin "1") (pinfunction "G_1") (pintype "passive"))
      (node (ref "M319") (pin "3") (pinfunction "D_3") (pintype "passive"))
      (node (ref "R309") (pin "2") (pinfunction "2_2") (pintype "passive"))
    )
    (net (code "211") (name "Net-(M501-D)") (class "Default")
      (node (ref "M501") (pin "3") (pinfunction "D_3") (pintype "passive"))
      (node (ref "R501") (pin "2") (pinfunction "2_2") (pintype "passive"))
    )
    (net (code "212") (name "Net-(M502-D)") (class "Default")
      (node (ref "M502") (pin "3") (pinfunction "D_3") (pintype "passive"))
      (node (ref "M503") (pin "1") (pinfunction "G_1") (pintype "passive"))
      (node (ref "M504") (pin "1") (pinfunction "G_1") (pintype "passive"))
      (node (ref "R504") (pin "2") (pinfunction "2_2") (pintype "passive"))
    )
    (net (code "213") (name "Net-(M502-G)") (class "Default")
      (node (ref "M502") (pin "1") (pinfunction "G_1") (pintype "passive"))
      (node (ref "R502") (pin "2") (pinfunction "2_2") (pintype "passive"))
      (node (ref "R503") (pin "1") (pinfunction "1_1") (pintype "passive"))
    )
    (net (code "214") (name "Net-(M503-S)") (class "Default")
      (node (ref "M503") (pin "2") (pinfunction "S_2") (pintype "passive"))
      (node (ref "R505") (pin "1") (pinfunction "1_1") (pintype "passive"))
    )
    (net (code "215") (name "Net-(M505-D)") (class "Default")
      (node (ref "M505") (pin "3") (pinfunction "D_3") (pintype "passive"))
      (node (ref "M507") (pin "1") (pinfunction "G_1") (pintype "passive"))
      (node (ref "R510") (pin "2") (pinfunction "2_2") (pintype "passive"))
    )
    (net (code "216") (name "Net-(M505-G)") (class "Default")
      (node (ref "M505") (pin "1") (pinfunction "G_1") (pintype "passive"))
      (node (ref "R507") (pin "2") (pinfunction "2_2") (pintype "passive"))
      (node (ref "R508") (pin "1") (pinfunction "1_1") (pintype "passive"))
    )
    (net (code "217") (name "Net-(M506-G)") (class "Default")
      (node (ref "M506") (pin "2") (pinfunction "G_2") (pintype "passive"))
      (node (ref "R509") (pin "2") (pinfunction "2_2") (pintype "passive"))
      (node (ref "R510") (pin "1") (pinfunction "1_1") (pintype "passive"))
    )
    (net (code "218") (name "Net-(M506-S)") (class "Default")
      (node (ref "M506") (pin "3") (pinfunction "S_3") (pintype "passive"))
      (node (ref "R511") (pin "2") (pinfunction "2_2") (pintype "passive"))
    )
    (net (code "219") (name "Net-(M508-D)") (class "Default")
      (node (ref "M508") (pin "3") (pinfunction "D_3") (pintype "passive"))
      (node (ref "R515") (pin "1") (pinfunction "1_1") (pintype "passive"))
    )
    (net (code "220") (name "Net-(M508-G)") (class "Default")
      (node (ref "M508") (pin "1") (pinfunction "G_1") (pintype "passive"))
      (node (ref "R513") (pin "2") (pinfunction "2_2") (pintype "passive"))
      (node (ref "R514") (pin "1") (pinfunction "1_1") (pintype "passive"))
    )
    (net (code "221") (name "Net-(M509-D)") (class "Default")
      (node (ref "M509") (pin "3") (pinfunction "D_3") (pintype "passive"))
      (node (ref "R514") (pin "2") (pinfunction "2_2") (pintype "passive"))
    )
    (net (code "222") (name "Net-(M510-D)") (class "Default")
      (node (ref "M510") (pin "3") (pinfunction "D_3") (pintype "passive"))
      (node (ref "R520") (pin "1") (pinfunction "1_1") (pintype "passive"))
      (node (ref "R522") (pin "1") (pinfunction "1_1") (pintype "passive"))
      (node (ref "U502") (pin "3") (pinfunction "IN-_3") (pintype "passive"))
    )
    (net (code "223") (name "Net-(M510-G)") (class "Default")
      (node (ref "M510") (pin "1") (pinfunction "G_1") (pintype "passive"))
      (node (ref "M511") (pin "3") (pinfunction "D_3") (pintype "passive"))
      (node (ref "R519") (pin "2") (pinfunction "2_2") (pintype "passive"))
    )
    (net (code "224") (name "Net-(M512-D)") (class "Default")
      (node (ref "M512") (pin "3") (pinfunction "D_3") (pintype "passive"))
      (node (ref "R522") (pin "2") (pinfunction "2_2") (pintype "passive"))
    )
    (net (code "225") (name "Net-(M513-G)") (class "Default")
      (node (ref "M513") (pin "1") (pinfunction "G_1") (pintype "passive"))
      (node (ref "R523") (pin "2") (pinfunction "2_2") (pintype "passive"))
      (node (ref "R524") (pin "1") (pinfunction "1_1") (pintype "passive"))
      (node (ref "U502") (pin "4") (pinfunction "OUT_4") (pintype "passive"))
    )
    (net (code "226") (name "Net-(M514-D)") (class "Default")
      (node (ref "M514") (pin "3") (pinfunction "D_3") (pintype "passive"))
      (node (ref "M515") (pin "1") (pinfunction "G_1") (pintype "passive"))
      (node (ref "R526") (pin "2") (pinfunction "2_2") (pintype "passive"))
      (node (ref "R527") (pin "2") (pinfunction "2_2") (pintype "passive"))
    )
    (net (code "227") (name "Net-(M515-S)") (class "Default")
      (node (ref "M515") (pin "2") (pinfunction "S_2") (pintype "passive"))
      (node (ref "R528") (pin "1") (pinfunction "1_1") (pintype "passive"))
    )
    (net (code "228") (name "Net-(Q301-B1)") (class "Default")
      (node (ref "Q301") (pin "2") (pinfunction "B2_2") (pintype "passive"))
      (node (ref "Q301") (pin "3") (pinfunction "C1_3") (pintype "passive"))
      (node (ref "Q301") (pin "5") (pinfunction "B1_5") (pintype "passive"))
      (node (ref "Q321") (pin "3") (pinfunction "C_3") (pintype "passive"))
      (node (ref "R281") (pin "2") (pinfunction "2_2") (pintype "passive"))
    )
    (net (code "229") (name "Net-(Q301-E1)") (class "Default")
      (node (ref "Q301") (pin "4") (pinfunction "E1_4") (pintype "passive"))
      (node (ref "R311") (pin "2") (pinfunction "2_2") (pintype "passive"))
    )
    (net (code "230") (name "Net-(Q301-E2)") (class "Default")
      (node (ref "Q301") (pin "1") (pinfunction "E2_1") (pintype "passive"))
      (node (ref "R331") (pin "2") (pinfunction "2_2") (pintype "passive"))
    )
    (net (code "231") (name "Net-(Q302-B1)") (class "Default")
      (node (ref "Q302") (pin "2") (pinfunction "B2_2") (pintype "passive"))
      (node (ref "Q302") (pin "3") (pinfunction "C1_3") (pintype "passive"))
      (node (ref "Q302") (pin "5") (pinfunction "B1_5") (pintype "passive"))
      (node (ref "Q322") (pin "3") (pinfunction "C_3") (pintype "passive"))
      (node (ref "R282") (pin "2") (pinfunction "2_2") (pintype "passive"))
    )
    (net (code "232") (name "Net-(Q302-E1)") (class "Default")
      (node (ref "Q302") (pin "4") (pinfunction "E1_4") (pintype "passive"))
      (node (ref "R312") (pin "2") (pinfunction "2_2") (pintype "passive"))
    )
    (net (code "233") (name "Net-(Q302-E2)") (class "Default")
      (node (ref "Q302") (pin "1") (pinfunction "E2_1") (pintype "passive"))
      (node (ref "R332") (pin "2") (pinfunction "2_2") (pintype "passive"))
    )
    (net (code "234") (name "Net-(Q303-B1)") (class "Default")
      (node (ref "Q303") (pin "2") (pinfunction "B2_2") (pintype "passive"))
      (node (ref "Q303") (pin "3") (pinfunction "C1_3") (pintype "passive"))
      (node (ref "Q303") (pin "5") (pinfunction "B1_5") (pintype "passive"))
      (node (ref "Q323") (pin "3") (pinfunction "C_3") (pintype "passive"))
      (node (ref "R283") (pin "2") (pinfunction "2_2") (pintype "passive"))
    )
    (net (code "235") (name "Net-(Q303-E1)") (class "Default")
      (node (ref "Q303") (pin "4") (pinfunction "E1_4") (pintype "passive"))
      (node (ref "R313") (pin "2") (pinfunction "2_2") (pintype "passive"))
    )
    (net (code "236") (name "Net-(Q303-E2)") (class "Default")
      (node (ref "Q303") (pin "1") (pinfunction "E2_1") (pintype "passive"))
      (node (ref "R333") (pin "2") (pinfunction "2_2") (pintype "passive"))
    )
    (net (code "237") (name "Net-(Q304-B1)") (class "Default")
      (node (ref "Q304") (pin "2") (pinfunction "B2_2") (pintype "passive"))
      (node (ref "Q304") (pin "3") (pinfunction "C1_3") (pintype "passive"))
      (node (ref "Q304") (pin "5") (pinfunction "B1_5") (pintype "passive"))
      (node (ref "Q324") (pin "3") (pinfunction "C_3") (pintype "passive"))
      (node (ref "R284") (pin "2") (pinfunction "2_2") (pintype "passive"))
    )
    (net (code "238") (name "Net-(Q304-E1)") (class "Default")
      (node (ref "Q304") (pin "4") (pinfunction "E1_4") (pintype "passive"))
      (node (ref "R314") (pin "2") (pinfunction "2_2") (pintype "passive"))
    )
    (net (code "239") (name "Net-(Q304-E2)") (class "Default")
      (node (ref "Q304") (pin "1") (pinfunction "E2_1") (pintype "passive"))
      (node (ref "R334") (pin "2") (pinfunction "2_2") (pintype "passive"))
    )
    (net (code "240") (name "Net-(Q317-B1)") (class "Default")
      (node (ref "Q317") (pin "2") (pinfunction "B2_2") (pintype "passive"))
      (node (ref "Q317") (pin "3") (pinfunction "C1_3") (pintype "passive"))
      (node (ref "Q317") (pin "5") (pinfunction "B1_5") (pintype "passive"))
      (node (ref "Q337") (pin "3") (pinfunction "C_3") (pintype "passive"))
      (node (ref "R297") (pin "2") (pinfunction "2_2") (pintype "passive"))
    )
    (net (code "241") (name "Net-(Q317-E1)") (class "Default")
      (node (ref "Q317") (pin "4") (pinfunction "E1_4") (pintype "passive"))
      (node (ref "R327") (pin "2") (pinfunction "2_2") (pintype "passive"))
    )
    (net (code "242") (name "Net-(Q317-E2)") (class "Default")
      (node (ref "Q317") (pin "1") (pinfunction "E2_1") (pintype "passive"))
      (node (ref "R347") (pin "2") (pinfunction "2_2") (pintype "passive"))
    )
    (net (code "243") (name "Net-(Q318-B)") (class "Default")
      (node (ref "Q318") (pin "1") (pinfunction "B_1") (pintype "passive"))
      (node (ref "R277") (pin "2") (pinfunction "2_2") (pintype "passive"))
    )
    (net (code "244") (name "Net-(Q318-E)") (class "Default")
      (node (ref "Q318") (pin "2") (pinfunction "E_2") (pintype "passive"))
      (node (ref "R278") (pin "1") (pinfunction "1_1") (pintype "passive"))
      (node (ref "U305") (pin "B1") (pinfunction "IN1-_B1") (pintype "passive"))
    )
    (net (code "245") (name "Net-(R201-Pad2)") (class "Default")
      (node (ref "R201") (pin "2") (pinfunction "2_2") (pintype "passive"))
      (node (ref "R202") (pin "2") (pinfunction "2_2") (pintype "passive"))
      (node (ref "R205") (pin "1") (pinfunction "1_1") (pintype "passive"))
    )
    (net (code "246") (name "Net-(R206-Pad2)") (class "Default")
      (node (ref "R206") (pin "2") (pinfunction "2_2") (pintype "passive"))
      (node (ref "R207") (pin "2") (pinfunction "2_2") (pintype "passive"))
      (node (ref "R208") (pin "1") (pinfunction "1_1") (pintype "passive"))
    )
    (net (code "247") (name "Net-(R241-Pad2)") (class "Default")
      (node (ref "R241") (pin "2") (pinfunction "2_2") (pintype "passive"))
      (node (ref "R242") (pin "2") (pinfunction "2_2") (pintype "passive"))
      (node (ref "R245") (pin "1") (pinfunction "1_1") (pintype "passive"))
    )
    (net (code "248") (name "Net-(R246-Pad2)") (class "Default")
      (node (ref "R246") (pin "2") (pinfunction "2_2") (pintype "passive"))
      (node (ref "R247") (pin "2") (pinfunction "2_2") (pintype "passive"))
      (node (ref "R248") (pin "1") (pinfunction "1_1") (pintype "passive"))
    )
    (net (code "249") (name "Net-(U2-PROG)") (class "Default")
      (node (ref "R51") (pin "1") (pinfunction "1_1") (pintype "passive"))
      (node (ref "R8") (pin "1") (pinfunction "1_1") (pintype "passive"))
      (node (ref "R9") (pin "1") (pinfunction "1_1") (pintype "passive"))
      (node (ref "U2") (pin "6") (pinfunction "PROG_6") (pintype "passive"))
    )
    (net (code "250") (name "Net-(U3-IN)") (class "Default")
      (node (ref "C6") (pin "2") (pinfunction "2_2") (pintype "passive"))
      (node (ref "R10") (pin "2") (pinfunction "2_2") (pintype "passive"))
      (node (ref "R11") (pin "1") (pinfunction "1_1") (pintype "passive"))
      (node (ref "U3") (pin "A2") (pinfunction "IN_A2") (pintype "passive"))
    )
    (net (code "251") (name "Net-(U4-PROG)") (class "Default")
      (node (ref "R16") (pin "1") (pinfunction "1_1") (pintype "passive"))
      (node (ref "R17") (pin "1") (pinfunction "1_1") (pintype "passive"))
      (node (ref "R52") (pin "1") (pinfunction "1_1") (pintype "passive"))
      (node (ref "U4") (pin "6") (pinfunction "PROG_6") (pintype "passive"))
    )
    (net (code "252") (name "Net-(U5-IN)") (class "Default")
      (node (ref "C8") (pin "2") (pinfunction "2_2") (pintype "passive"))
      (node (ref "R18") (pin "2") (pinfunction "2_2") (pintype "passive"))
      (node (ref "R19") (pin "1") (pinfunction "1_1") (pintype "passive"))
      (node (ref "U5") (pin "A2") (pinfunction "IN_A2") (pintype "passive"))
    )
    (net (code "253") (name "Net-(U6-IN+)") (class "Default")
      (node (ref "R24") (pin "2") (pinfunction "2_2") (pintype "passive"))
      (node (ref "R25") (pin "1") (pinfunction "1_1") (pintype "passive"))
      (node (ref "U6") (pin "C1") (pinfunction "IN+_C1") (pintype "passive"))
    )
    (net (code "254") (name "Net-(U7-IN+)") (class "Default")
      (node (ref "R27") (pin "2") (pinfunction "2_2") (pintype "passive"))
      (node (ref "R28") (pin "1") (pinfunction "1_1") (pintype "passive"))
      (node (ref "U7") (pin "C1") (pinfunction "IN+_C1") (pintype "passive"))
    )
    (net (code "255") (name "Net-(U12-FB)") (class "Default")
      (node (ref "R38") (pin "2") (pinfunction "2_2") (pintype "passive"))
      (node (ref "U12") (pin "3") (pinfunction "FB_3") (pintype "passive"))
      (node (ref "U13") (pin "6") (pinfunction "RW_6") (pintype "passive"))
    )
    (net (code "256") (name "Net-(U13-RH)") (class "Default")
      (node (ref "R39") (pin "1") (pinfunction "1_1") (pintype "passive"))
      (node (ref "U13") (pin "7") (pinfunction "RH_7") (pintype "passive"))
    )
    (net (code "257") (name "Net-(U15-IN+)") (class "Default")
      (node (ref "J5") (pin "1") (pinfunction "1_1") (pintype "passive"))
      (node (ref "R45") (pin "2") (pinfunction "2_2") (pintype "passive"))
      (node (ref "U15") (pin "C1") (pinfunction "IN+_C1") (pintype "passive"))
    )
    (net (code "258") (name "Net-(U16-IN+)") (class "Default")
      (node (ref "J6") (pin "1") (pinfunction "1_1") (pintype "passive"))
      (node (ref "R46") (pin "1") (pinfunction "1_1") (pintype "passive"))
      (node (ref "U16") (pin "C1") (pinfunction "IN+_C1") (pintype "passive"))
    )
    (net (code "259") (name "Net-(U17-BOOT0_{slash}_PH3)") (class "Default")
      (node (ref "R55") (pin "2") (pinfunction "2_2") (pintype "passive"))
      (node (ref "U17") (pin "B5") (pinfunction "BOOT0_/_PH3_B5") (pintype "bidirectional"))
    )
    (net (code "260") (name "Net-(U17-I2C1_SCL_{slash}_VDDSMPS_{slash}_PG14)") (class "Default")
      (node (ref "R48") (pin "1") (pinfunction "1_1") (pintype "passive"))
      (node (ref "U17") (pin "M9") (pinfunction "I2C1_SCL_/_VDDSMPS_/_PG14_M9") (pintype "power_in"))
    )
    (net (code "261") (name "Net-(U17-I2C1_SDA_{slash}_VLXSMPS_{slash}_PG13)") (class "Default")
      (node (ref "L5") (pin "2") (pinfunction "2_2") (pintype "passive"))
      (node (ref "U17") (pin "M10") (pinfunction "I2C1_SDA_/_VLXSMPS_/_PG13_M10") (pintype "power_in"))
    )
    (net (code "262") (name "Net-(U17-OSC_IN_{slash}_PH0)") (class "Default")
      (node (ref "C25") (pin "1") (pinfunction "1_1") (pintype "passive"))
      (node (ref "U17") (pin "F1") (pinfunction "OSC_IN_/_PH0_F1") (pintype "bidirectional"))
      (node (ref "Y2") (pin "1") (pinfunction "1_1") (pintype "passive"))
    )
    (net (code "263") (name "Net-(U17-OSC_OUT_{slash}_PH1)") (class "Default")
      (node (ref "C24") (pin "1") (pinfunction "1_1") (pintype "passive"))
      (node (ref "U17") (pin "G1") (pinfunction "OSC_OUT_/_PH1_G1") (pintype "bidirectional"))
      (node (ref "Y2") (pin "2") (pinfunction "2_2") (pintype "passive"))
    )
    (net (code "264") (name "Net-(U17-PC14_{slash}_OSC32_IN)") (class "Default")
      (node (ref "C23") (pin "2") (pinfunction "2_2") (pintype "passive"))
      (node (ref "U17") (pin "C1") (pinfunction "PC14_/_OSC32_IN_C1") (pintype "bidirectional"))
      (node (ref "Y1") (pin "1") (pinfunction "1_1") (pintype "passive"))
    )
    (net (code "265") (name "Net-(U17-PC15_{slash}_OSC32_OUT)") (class "Default")
      (node (ref "C22") (pin "2") (pinfunction "2_2") (pintype "passive"))
      (node (ref "U17") (pin "D1") (pinfunction "PC15_/_OSC32_OUT_D1") (pintype "bidirectional"))
      (node (ref "Y1") (pin "2") (pinfunction "2_2") (pintype "passive"))
    )
    (net (code "266") (name "Net-(U17-VBAT)") (class "Default")
      (node (ref "R47") (pin "1") (pinfunction "1_1") (pintype "passive"))
      (node (ref "U17") (pin "B1") (pinfunction "VBAT_B1") (pintype "power_in"))
    )
    (net (code "267") (name "Net-(U17-VDD11_{slash}_PG15)") (class "Default")
      (node (ref "C45") (pin "2") (pinfunction "2_2") (pintype "passive"))
      (node (ref "L5") (pin "1") (pinfunction "1_1") (pintype "passive"))
      (node (ref "U17") (pin "B4") (pinfunction "VDD11_/_PG15_B4") (pintype "power_in"))
    )
    (net (code "268") (name "Net-(U17-VDDA)") (class "Default")
      (node (ref "C34") (pin "1") (pinfunction "1_1") (pintype "passive"))
      (node (ref "C35") (pin "2") (pinfunction "2_2") (pintype "passive"))
      (node (ref "L6") (pin "2") (pinfunction "2_2") (pintype "passive"))
      (node (ref "U17") (pin "K1") (pinfunction "VDDA_K1") (pintype "power_in"))
    )
    (net (code "269") (name "Net-(U17-VREF+)") (class "Default")
      (node (ref "C33") (pin "2") (pinfunction "2_2") (pintype "passive"))
      (node (ref "U17") (pin "J1") (pinfunction "VREF+_J1") (pintype "power_in"))
    )
    (net (code "270") (name "Net-(U18-~{MR})") (class "Default")
      (node (ref "SW901") (pin "3") (pinfunction "3_3") (pintype "passive"))
      (node (ref "SW901") (pin "4") (pinfunction "4_4") (pintype "passive"))
      (node (ref "U18") (pin "2") (pinfunction "~{MR}_2") (pintype "passive"))
    )
    (net (code "271") (name "Net-(U91-ANT)") (class "Default")
      (node (ref "C96") (pin "1") (pinfunction "1_1") (pintype "passive"))
      (node (ref "U91") (pin "E1") (pinfunction "ANT_E1") (pintype "passive"))
    )
    (net (code "272") (name "Net-(U91-DEC1)") (class "Default")
      (node (ref "C93") (pin "2") (pinfunction "2_2") (pintype "passive"))
      (node (ref "U91") (pin "B6") (pinfunction "DEC1_B6") (pintype "passive"))
    )
    (net (code "273") (name "Net-(U91-DEC2)") (class "Default")
      (node (ref "C94") (pin "2") (pinfunction "2_2") (pintype "passive"))
      (node (ref "U91") (pin "A3") (pinfunction "DEC2_A3") (pintype "passive"))
    )
    (net (code "274") (name "Net-(U91-DEC4)") (class "Default")
      (node (ref "C95") (pin "1") (pinfunction "1_1") (pintype "passive"))
      (node (ref "U91") (pin "A4") (pinfunction "DEC4_A4") (pintype "passive"))
    )
    (net (code "275") (name "Net-(U91-P0.00_{slash}_XL1)") (class "Default")
      (node (ref "C88") (pin "2") (pinfunction "2_2") (pintype "passive"))
      (node (ref "U91") (pin "B5") (pinfunction "P0.00_/_XL1_B5") (pintype "passive"))
      (node (ref "Y91") (pin "1") (pinfunction "1_1") (pintype "passive"))
    )
    (net (code "276") (name "Net-(U91-P0.01_{slash}_XL2)") (class "Default")
      (node (ref "C87") (pin "2") (pinfunction "2_2") (pintype "passive"))
      (node (ref "U91") (pin "D5") (pinfunction "P0.01_/_XL2_D5") (pintype "passive"))
      (node (ref "Y91") (pin "2") (pinfunction "2_2") (pintype "passive"))
    )
    (net (code "277") (name "Net-(U91-XC1)") (class "Default")
      (node (ref "C89") (pin "1") (pinfunction "1_1") (pintype "passive"))
      (node (ref "U91") (pin "A1") (pinfunction "XC1_A1") (pintype "passive"))
      (node (ref "Y92") (pin "2") (pinfunction "2_2") (pintype "passive"))
    )
    (net (code "278") (name "Net-(U91-XC2)") (class "Default")
      (node (ref "C90") (pin "1") (pinfunction "1_1") (pintype "passive"))
      (node (ref "U91") (pin "A2") (pinfunction "XC2_A2") (pintype "passive"))
      (node (ref "Y92") (pin "1") (pinfunction "1_1") (pintype "passive"))
    )
    (net (code "279") (name "Net-(U201-+IN)") (class "Default")
      (node (ref "R203") (pin "2") (pinfunction "2_2") (pintype "passive"))
      (node (ref "U201") (pin "B5") (pinfunction "+IN_B5") (pintype "input"))
    )
    (net (code "280") (name "Net-(U201--IN)") (class "Default")
      (node (ref "R204") (pin "2") (pinfunction "2_2") (pintype "passive"))
      (node (ref "U201") (pin "C5") (pinfunction "-IN_C5") (pintype "input"))
    )
    (net (code "281") (name "Net-(U201-AC_{slash}_~{DC})") (class "Default")
      (node (ref "R215") (pin "1") (pinfunction "1_1") (pintype "passive"))
      (node (ref "U201") (pin "B2") (pinfunction "AC_/_~{DC}_B2") (pintype "input"))
    )
    (net (code "282") (name "Net-(U201-HPDRIVE)") (class "Default")
      (node (ref "C202") (pin "1") (pinfunction "1_1") (pintype "passive"))
      (node (ref "U201") (pin "A5") (pinfunction "HPDRIVE_A5") (pintype "output"))
    )
    (net (code "283") (name "Net-(U201-HPSENSE)") (class "Default")
      (node (ref "C202") (pin "2") (pinfunction "2_2") (pintype "passive"))
      (node (ref "R208") (pin "2") (pinfunction "2_2") (pintype "passive"))
      (node (ref "U201") (pin "A4") (pinfunction "HPSENSE_A4") (pintype "input"))
    )
    (net (code "284") (name "Net-(U201-IAOUT)") (class "Default")
      (node (ref "R207") (pin "1") (pinfunction "1_1") (pintype "passive"))
      (node (ref "R209") (pin "1") (pinfunction "1_1") (pintype "passive"))
      (node (ref "U201") (pin "B4") (pinfunction "IAOUT_B4") (pintype "output"))
    )
    (net (code "285") (name "Net-(U201-OPAMP+)") (class "Default")
      (node (ref "C204") (pin "1") (pinfunction "1_1") (pintype "passive"))
      (node (ref "R210") (pin "2") (pinfunction "2_2") (pintype "passive"))
      (node (ref "U201") (pin "D3") (pinfunction "OPAMP+_D3") (pintype "input"))
    )
    (net (code "286") (name "Net-(U201-OPAMP-)") (class "Default")
      (node (ref "R211") (pin "2") (pinfunction "2_2") (pintype "passive"))
      (node (ref "R212") (pin "1") (pinfunction "1_1") (pintype "passive"))
      (node (ref "U201") (pin "D2") (pinfunction "OPAMP-_D2") (pintype "input"))
    )
    (net (code "287") (name "Net-(U201-REFIN)") (class "Default")
      (node (ref "C207") (pin "2") (pinfunction "2_2") (pintype "passive"))
      (node (ref "R213") (pin "2") (pinfunction "2_2") (pintype "passive"))
      (node (ref "R214") (pin "1") (pinfunction "1_1") (pintype "passive"))
      (node (ref "U201") (pin "A3") (pinfunction "REFIN_A3") (pintype "input"))
    )
    (net (code "288") (name "Net-(U201-REFOUT)") (class "Default")
      (node (ref "C204") (pin "2") (pinfunction "2_2") (pintype "passive"))
      (node (ref "C205") (pin "1") (pinfunction "1_1") (pintype "passive"))
      (node (ref "R211") (pin "1") (pinfunction "1_1") (pintype "passive"))
      (node (ref "U201") (pin "C3") (pinfunction "REFOUT_C3") (pintype "output"))
    )
    (net (code "289") (name "Net-(U201-RLD)") (class "Default")
      (node (ref "C201") (pin "1") (pinfunction "1_1") (pintype "passive"))
      (node (ref "R205") (pin "2") (pinfunction "2_2") (pintype "passive"))
      (node (ref "U201") (pin "D5") (pinfunction "RLD_D5") (pintype "output"))
    )
    (net (code "290") (name "Net-(U201-RLDFB)") (class "Default")
      (node (ref "C201") (pin "2") (pinfunction "2_2") (pintype "passive"))
      (node (ref "U201") (pin "C4") (pinfunction "RLDFB_C4") (pintype "input"))
    )
    (net (code "291") (name "Net-(U201-SW)") (class "Default")
      (node (ref "C205") (pin "2") (pinfunction "2_2") (pintype "passive"))
      (node (ref "R206") (pin "1") (pinfunction "1_1") (pintype "passive"))
      (node (ref "U201") (pin "D4") (pinfunction "SW_D4") (pintype "passive"))
    )
    (net (code "292") (name "Net-(U203-+IN)") (class "Default")
      (node (ref "R243") (pin "2") (pinfunction "2_2") (pintype "passive"))
      (node (ref "U203") (pin "B5") (pinfunction "+IN_B5") (pintype "input"))
    )
    (net (code "293") (name "Net-(U203--IN)") (class "Default")
      (node (ref "R244") (pin "2") (pinfunction "2_2") (pintype "passive"))
      (node (ref "U203") (pin "C5") (pinfunction "-IN_C5") (pintype "input"))
    )
    (net (code "294") (name "Net-(U203-AC_{slash}_~{DC})") (class "Default")
      (node (ref "R255") (pin "1") (pinfunction "1_1") (pintype "passive"))
      (node (ref "U203") (pin "B2") (pinfunction "AC_/_~{DC}_B2") (pintype "input"))
    )
    (net (code "295") (name "Net-(U203-HPDRIVE)") (class "Default")
      (node (ref "C242") (pin "2") (pinfunction "2_2") (pintype "passive"))
      (node (ref "U203") (pin "A5") (pinfunction "HPDRIVE_A5") (pintype "output"))
    )
    (net (code "296") (name "Net-(U203-HPSENSE)") (class "Default")
      (node (ref "C242") (pin "1") (pinfunction "1_1") (pintype "passive"))
      (node (ref "R248") (pin "2") (pinfunction "2_2") (pintype "passive"))
      (node (ref "U203") (pin "A4") (pinfunction "HPSENSE_A4") (pintype "input"))
    )
    (net (code "297") (name "Net-(U203-IAOUT)") (class "Default")
      (node (ref "R247") (pin "1") (pinfunction "1_1") (pintype "passive"))
      (node (ref "R249") (pin "1") (pinfunction "1_1") (pintype "passive"))
      (node (ref "U203") (pin "B4") (pinfunction "IAOUT_B4") (pintype "output"))
    )
    (net (code "298") (name "Net-(U203-OPAMP+)") (class "Default")
      (node (ref "C244") (pin "1") (pinfunction "1_1") (pintype "passive"))
      (node (ref "R250") (pin "2") (pinfunction "2_2") (pintype "passive"))
      (node (ref "U203") (pin "D3") (pinfunction "OPAMP+_D3") (pintype "input"))
    )
    (net (code "299") (name "Net-(U203-OPAMP-)") (class "Default")
      (node (ref "R251") (pin "2") (pinfunction "2_2") (pintype "passive"))
      (node (ref "R252") (pin "1") (pinfunction "1_1") (pintype "passive"))
      (node (ref "U203") (pin "D2") (pinfunction "OPAMP-_D2") (pintype "input"))
    )
    (net (code "300") (name "Net-(U203-REFIN)") (class "Default")
      (node (ref "C247") (pin "2") (pinfunction "2_2") (pintype "passive"))
      (node (ref "R253") (pin "2") (pinfunction "2_2") (pintype "passive"))
      (node (ref "R254") (pin "1") (pinfunction "1_1") (pintype "passive"))
      (node (ref "U203") (pin "A3") (pinfunction "REFIN_A3") (pintype "input"))
    )
    (net (code "301") (name "Net-(U203-REFOUT)") (class "Default")
      (node (ref "C244") (pin "2") (pinfunction "2_2") (pintype "passive"))
      (node (ref "C245") (pin "2") (pinfunction "2_2") (pintype "passive"))
      (node (ref "R251") (pin "1") (pinfunction "1_1") (pintype "passive"))
      (node (ref "U203") (pin "C3") (pinfunction "REFOUT_C3") (pintype "output"))
    )
    (net (code "302") (name "Net-(U203-RLD)") (class "Default")
      (node (ref "C241") (pin "1") (pinfunction "1_1") (pintype "passive"))
      (node (ref "R245") (pin "2") (pinfunction "2_2") (pintype "passive"))
      (node (ref "U203") (pin "D5") (pinfunction "RLD_D5") (pintype "output"))
    )
    (net (code "303") (name "Net-(U203-RLDFB)") (class "Default")
      (node (ref "C241") (pin "2") (pinfunction "2_2") (pintype "passive"))
      (node (ref "U203") (pin "C4") (pinfunction "RLDFB_C4") (pintype "input"))
    )
    (net (code "304") (name "Net-(U203-SW)") (class "Default")
      (node (ref "C245") (pin "1") (pinfunction "1_1") (pintype "passive"))
      (node (ref "R246") (pin "1") (pinfunction "1_1") (pintype "passive"))
      (node (ref "U203") (pin "D4") (pinfunction "SW_D4") (pintype "passive"))
    )
    (net (code "305") (name "Net-(U301-VOUTA)") (class "Default")
      (node (ref "U301") (pin "2") (pinfunction "VOUTA_2") (pintype "output"))
      (node (ref "U303") (pin "1") (pinfunction "NO_1") (pintype "passive"))
    )
    (net (code "306") (name "Net-(U301-VOUTB)") (class "Default")
      (node (ref "U301") (pin "9") (pinfunction "VOUTB_9") (pintype "output"))
      (node (ref "U304") (pin "1") (pinfunction "NO_1") (pintype "passive"))
    )
    (net (code "307") (name "Net-(U301-VREFIO)") (class "Default")
      (node (ref "TP301") (pin "1") (pinfunction "1_1") (pintype "passive"))
      (node (ref "U301") (pin "10") (pinfunction "VREFIO_10") (pintype "power_in"))
    )
    (net (code "308") (name "Net-(U303-COM)") (class "Default")
      (node (ref "R276") (pin "1") (pinfunction "1_1") (pintype "passive"))
      (node (ref "U303") (pin "4") (pinfunction "COM_4") (pintype "passive"))
      (node (ref "U304") (pin "4") (pinfunction "COM_4") (pintype "passive"))
      (node (ref "U305") (pin "A1") (pinfunction "IN1+_A1") (pintype "passive"))
    )
    (net (code "309") (name "Net-(U305-IN2+)") (class "Default")
      (node (ref "R279") (pin "1") (pinfunction "1_1") (pintype "passive"))
      (node (ref "U305") (pin "A3") (pinfunction "IN2+_A3") (pintype "passive"))
      (node (ref "U305") (pin "B3") (pinfunction "IN2-_B3") (pintype "passive"))
    )
    (net (code "310") (name "Net-(U305-OUT1)") (class "Default")
      (node (ref "R277") (pin "1") (pinfunction "1_1") (pintype "passive"))
      (node (ref "U305") (pin "C1") (pinfunction "OUT1_C1") (pintype "passive"))
    )
    (net (code "311") (name "Net-(U306-CEXT)") (class "Default")
      (node (ref "C305") (pin "1") (pinfunction "1_1") (pintype "passive"))
      (node (ref "U306") (pin "6") (pinfunction "CEXT_6") (pintype "passive"))
    )
    (net (code "312") (name "Net-(U306-Q)") (class "Default")
      (node (ref "R300") (pin "1") (pinfunction "1_1") (pintype "passive"))
      (node (ref "U306") (pin "5") (pinfunction "Q_5") (pintype "output"))
    )
    (net (code "313") (name "Net-(U306-REXT_{slash}_CEXT)") (class "Default")
      (node (ref "C305") (pin "2") (pinfunction "2_2") (pintype "passive"))
      (node (ref "R298") (pin "2") (pinfunction "2_2") (pintype "passive"))
      (node (ref "U306") (pin "7") (pinfunction "REXT_/_CEXT_7") (pintype "passive"))
    )
    (net (code "314") (name "Net-(U307-1B)") (class "Default")
      (node (ref "R299") (pin "2") (pinfunction "2_2") (pintype "passive"))
      (node (ref "R300") (pin "2") (pinfunction "2_2") (pintype "passive"))
      (node (ref "U307") (pin "2") (pinfunction "1B_2") (pintype "input"))
      (node (ref "U307") (pin "5") (pinfunction "2A_5") (pintype "input"))
    )
    (net (code "315") (name "Net-(U310-IN1-)") (class "Default")
      (node (ref "R301") (pin "1") (pinfunction "1_1") (pintype "passive"))
      (node (ref "U310") (pin "B1") (pinfunction "IN1-_B1") (pintype "passive"))
      (node (ref "U310") (pin "C1") (pinfunction "OUT1_C1") (pintype "passive"))
    )
    (net (code "316") (name "Net-(U310-IN2-)") (class "Default")
      (node (ref "R302") (pin "1") (pinfunction "1_1") (pintype "passive"))
      (node (ref "U310") (pin "B3") (pinfunction "IN2-_B3") (pintype "passive"))
      (node (ref "U310") (pin "C3") (pinfunction "OUT2_C3") (pintype "passive"))
    )
    (net (code "317") (name "Net-(U311-+IN)") (class "Default")
      (node (ref "R302") (pin "2") (pinfunction "2_2") (pintype "passive"))
      (node (ref "R306") (pin "1") (pinfunction "1_1") (pintype "passive"))
      (node (ref "U311") (pin "8") (pinfunction "+IN_8") (pintype "passive"))
    )
    (net (code "318") (name "Net-(U311-+OUT)") (class "Default")
      (node (ref "R305") (pin "2") (pinfunction "2_2") (pintype "passive"))
      (node (ref "R307") (pin "1") (pinfunction "1_1") (pintype "passive"))
      (node (ref "U311") (pin "4") (pinfunction "+OUT_4") (pintype "passive"))
    )
    (net (code "319") (name "Net-(U311--IN)") (class "Default")
      (node (ref "R301") (pin "2") (pinfunction "2_2") (pintype "passive"))
      (node (ref "R305") (pin "1") (pinfunction "1_1") (pintype "passive"))
      (node (ref "U311") (pin "1") (pinfunction "-IN_1") (pintype "passive"))
    )
    (net (code "320") (name "Net-(U311--OUT)") (class "Default")
      (node (ref "R306") (pin "2") (pinfunction "2_2") (pintype "passive"))
      (node (ref "R308") (pin "1") (pinfunction "1_1") (pintype "passive"))
      (node (ref "U311") (pin "5") (pinfunction "-OUT_5") (pintype "passive"))
    )
    (net (code "321") (name "Net-(U311-VOCM)") (class "Default")
      (node (ref "R303") (pin "2") (pinfunction "2_2") (pintype "passive"))
      (node (ref "R304") (pin "1") (pinfunction "1_1") (pintype "passive"))
      (node (ref "U311") (pin "2") (pinfunction "VOCM_2") (pintype "passive"))
    )
    (net (code "322") (name "Net-(U501-IN+)") (class "Default")
      (node (ref "R515") (pin "2") (pinfunction "2_2") (pintype "passive"))
      (node (ref "R516") (pin "1") (pinfunction "1_1") (pintype "passive"))
      (node (ref "U501") (pin "C1") (pinfunction "IN+_C1") (pintype "passive"))
    )
    (net (code "323") (name "Net-(U502-IN+)") (class "Default")
      (node (ref "C509") (pin "2") (pinfunction "2_2") (pintype "passive"))
      (node (ref "R520") (pin "2") (pinfunction "2_2") (pintype "passive"))
      (node (ref "R521") (pin "1") (pinfunction "1_1") (pintype "passive"))
      (node (ref "R523") (pin "1") (pinfunction "1_1") (pintype "passive"))
      (node (ref "U502") (pin "1") (pinfunction "IN+_1") (pintype "passive"))
    )
    (net (code "324") (name "Net-(U503-BST1)") (class "Default")
      (node (ref "C512") (pin "1") (pinfunction "1_1") (pintype "passive"))
      (node (ref "U503") (pin "1") (pinfunction "BST1_1") (pintype "passive"))
    )
    (net (code "325") (name "Net-(U503-BST2)") (class "Default")
      (node (ref "C513") (pin "1") (pinfunction "1_1") (pintype "passive"))
      (node (ref "U503") (pin "16") (pinfunction "BST2_16") (pintype "passive"))
    )
    (net (code "326") (name "Net-(U503-MPPC)") (class "Default")
      (node (ref "C511") (pin "1") (pinfunction "1_1") (pintype "passive"))
      (node (ref "R531") (pin "1") (pinfunction "1_1") (pintype "passive"))
      (node (ref "U503") (pin "5") (pinfunction "VCC_5") (pintype "power_in"))
      (node (ref "U503") (pin "6") (pinfunction "MPPC_6") (pintype "passive"))
    )
    (net (code "327") (name "Net-(U503-SW2)") (class "Default")
      (node (ref "C513") (pin "2") (pinfunction "2_2") (pintype "passive"))
      (node (ref "L501") (pin "2") (pinfunction "2_2") (pintype "passive"))
      (node (ref "U503") (pin "15") (pinfunction "SW2_15") (pintype "passive"))
    )
    (net (code "328") (name "Net-(U503-VS2)") (class "Default")
      (node (ref "R529") (pin "2") (pinfunction "2_2") (pintype "passive"))
      (node (ref "R530") (pin "1") (pinfunction "1_1") (pintype "passive"))
      (node (ref "R531") (pin "2") (pinfunction "2_2") (pintype "passive"))
      (node (ref "U503") (pin "9") (pinfunction "VS2_9") (pintype "input"))
    )
    (net (code "329") (name "VBAT1CHG") (class "Default")
      (node (ref "M9") (pin "3") (pinfunction "S_3") (pintype "passive"))
      (node (ref "R10") (pin "1") (pinfunction "1_1") (pintype "passive"))
      (node (ref "R12") (pin "1") (pinfunction "1_1") (pintype "passive"))
      (node (ref "TP14") (pin "1") (pinfunction "1_1") (pintype "passive"))
      (node (ref "U2") (pin "3") (pinfunction "BAT_3") (pintype "power_in"))
    )
    (net (code "330") (name "VBAT1F") (class "Default")
      (node (ref "C1") (pin "2") (pinfunction "2_2") (pintype "passive"))
      (node (ref "D6") (pin "1") (pinfunction "K_1") (pintype "passive"))
      (node (ref "L1") (pin "2") (pinfunction "2_2") (pintype "passive"))
      (node (ref "M1") (pin "2") (pinfunction "S_2") (pintype "passive"))
      (node (ref "M10") (pin "3") (pinfunction "S_3") (pintype "passive"))
      (node (ref "R1") (pin "1") (pinfunction "1_1") (pintype "passive"))
      (node (ref "R13") (pin "1") (pinfunction "1_1") (pintype "passive"))
      (node (ref "TP2") (pin "1") (pinfunction "1_1") (pintype "passive"))
    )
    (net (code "331") (name "VBAT1R") (class "Default")
      (node (ref "C1") (pin "1") (pinfunction "1_1") (pintype "passive"))
      (node (ref "J1") (pin "1") (pinfunction "1_1") (pintype "passive"))
      (node (ref "J1") (pin "2") (pinfunction "2_2") (pintype "passive"))
      (node (ref "J1") (pin "3") (pinfunction "3_3") (pintype "passive"))
      (node (ref "J1") (pin "4") (pinfunction "4_4") (pintype "passive"))
      (node (ref "J901") (pin "2") (pinfunction "2_2") (pintype "passive"))
      (node (ref "L1") (pin "1") (pinfunction "1_1") (pintype "passive"))
      (node (ref "TP1") (pin "1") (pinfunction "1_1") (pintype "passive"))
    )
    (net (code "332") (name "VBAT1SW") (class "Default")
      (node (ref "D11") (pin "2") (pinfunction "A_2") (pintype "passive"))
      (node (ref "D3") (pin "2") (pinfunction "A_2") (pintype "passive"))
      (node (ref "M1") (pin "3") (pinfunction "D_3") (pintype "passive"))
      (node (ref "M21") (pin "2") (pinfunction "S_2") (pintype "passive"))
      (node (ref "R23") (pin "1") (pinfunction "1_1") (pintype "passive"))
      (node (ref "TP7") (pin "1") (pinfunction "1_1") (pintype "passive"))
    )
    (net (code "333") (name "VBAT2CHG") (class "Default")
      (node (ref "M17") (pin "3") (pinfunction "S_3") (pintype "passive"))
      (node (ref "R18") (pin "1") (pinfunction "1_1") (pintype "passive"))
      (node (ref "R20") (pin "1") (pinfunction "1_1") (pintype "passive"))
      (node (ref "TP18") (pin "1") (pinfunction "1_1") (pintype "passive"))
      (node (ref "U4") (pin "3") (pinfunction "BAT_3") (pintype "power_in"))
    )
    (net (code "334") (name "VBAT2F") (class "Default")
      (node (ref "C2") (pin "2") (pinfunction "2_2") (pintype "passive"))
      (node (ref "D7") (pin "1") (pinfunction "K_1") (pintype "passive"))
      (node (ref "L2") (pin "2") (pinfunction "2_2") (pintype "passive"))
      (node (ref "M18") (pin "3") (pinfunction "S_3") (pintype "passive"))
      (node (ref "M2") (pin "2") (pinfunction "S_2") (pintype "passive"))
      (node (ref "R2") (pin "1") (pinfunction "1_1") (pintype "passive"))
      (node (ref "R21") (pin "1") (pinfunction "1_1") (pintype "passive"))
      (node (ref "TP5") (pin "1") (pinfunction "1_1") (pintype "passive"))
    )
    (net (code "335") (name "VBAT2R") (class "Default")
      (node (ref "C2") (pin "1") (pinfunction "1_1") (pintype "passive"))
      (node (ref "J3") (pin "1") (pinfunction "1_1") (pintype "passive"))
      (node (ref "J3") (pin "2") (pinfunction "2_2") (pintype "passive"))
      (node (ref "J3") (pin "3") (pinfunction "3_3") (pintype "passive"))
      (node (ref "J3") (pin "4") (pinfunction "4_4") (pintype "passive"))
      (node (ref "J902") (pin "2") (pinfunction "2_2") (pintype "passive"))
      (node (ref "L2") (pin "1") (pinfunction "1_1") (pintype "passive"))
      (node (ref "TP4") (pin "1") (pinfunction "1_1") (pintype "passive"))
    )
    (net (code "336") (name "VBAT2SW") (class "Default")
      (node (ref "D12") (pin "2") (pinfunction "A_2") (pintype "passive"))
      (node (ref "D5") (pin "2") (pinfunction "A_2") (pintype "passive"))
      (node (ref "M2") (pin "3") (pinfunction "D_3") (pintype "passive"))
      (node (ref "M22") (pin "2") (pinfunction "S_2") (pintype "passive"))
      (node (ref "R26") (pin "1") (pinfunction "1_1") (pintype "passive"))
      (node (ref "TP8") (pin "1") (pinfunction "1_1") (pintype "passive"))
    )
    (net (code "337") (name "VCARR") (class "Default")
      (node (ref "C503") (pin "2") (pinfunction "2_2") (pintype "passive"))
      (node (ref "C504") (pin "2") (pinfunction "2_2") (pintype "passive"))
      (node (ref "C507") (pin "1") (pinfunction "1_1") (pintype "passive"))
      (node (ref "D501") (pin "2") (pinfunction "A_2") (pintype "passive"))
      (node (ref "D504") (pin "2") (pinfunction "A_2") (pintype "passive"))
      (node (ref "D506") (pin "1") (pinfunction "K_1") (pintype "passive"))
      (node (ref "TP503") (pin "1") (pinfunction "1_1") (pintype "passive"))
    )
    (net (code "338") (name "VCHG_RAIL") (class "Default")
      (node (ref "C514") (pin "1") (pinfunction "1_1") (pintype "passive"))
      (node (ref "C7") (pin "2") (pinfunction "2_2") (pintype "passive"))
      (node (ref "C9") (pin "2") (pinfunction "2_2") (pintype "passive"))
      (node (ref "D13") (pin "2") (pinfunction "A_2") (pintype "passive"))
      (node (ref "D4") (pin "2") (pinfunction "A_2") (pintype "passive"))
      (node (ref "M13") (pin "2") (pinfunction "S_2") (pintype "passive"))
      (node (ref "M5") (pin "2") (pinfunction "S_2") (pintype "passive"))
      (node (ref "R15") (pin "1") (pinfunction "1_1") (pintype "passive"))
      (node (ref "R529") (pin "1") (pinfunction "1_1") (pintype "passive"))
      (node (ref "R7") (pin "1") (pinfunction "1_1") (pintype "passive"))
      (node (ref "TP512") (pin "1") (pinfunction "1_1") (pintype "passive"))
      (node (ref "U3") (pin "B1") (pinfunction "V+_B1") (pintype "power_in"))
      (node (ref "U5") (pin "B1") (pinfunction "V+_B1") (pintype "power_in"))
      (node (ref "U503") (pin "14") (pinfunction "VOUT_14") (pintype "power_in"))
    )
    (net (code "339") (name "VDDA") (class "Default")
      (node (ref "C12") (pin "2") (pinfunction "2_2") (pintype "passive"))
      (node (ref "C206") (pin "2") (pinfunction "2_2") (pintype "passive"))
      (node (ref "C246") (pin "2") (pinfunction "2_2") (pintype "passive"))
      (node (ref "R213") (pin "1") (pinfunction "1_1") (pintype "passive"))
      (node (ref "R253") (pin "1") (pinfunction "1_1") (pintype "passive"))
      (node (ref "TP28") (pin "1") (pinfunction "1_1") (pintype "passive"))
      (node (ref "U10") (pin "1") (pinfunction "OUT_1") (pintype "passive"))
      (node (ref "U201") (pin "A2") (pinfunction "+VS_A2") (pintype "power_in"))
      (node (ref "U201") (pin "B3") (pinfunction "FR_B3") (pintype "input"))
      (node (ref "U203") (pin "A2") (pinfunction "+VS_A2") (pintype "power_in"))
      (node (ref "U203") (pin "B3") (pinfunction "FR_B3") (pintype "input"))
    )
    (net (code "340") (name "VDDS") (class "Default")
      (node (ref "C14") (pin "2") (pinfunction "2_2") (pintype "passive"))
      (node (ref "C301") (pin "2") (pinfunction "2_2") (pintype "passive"))
      (node (ref "C303") (pin "2") (pinfunction "2_2") (pintype "passive"))
      (node (ref "C304") (pin "2") (pinfunction "2_2") (pintype "passive"))
      (node (ref "M318") (pin "2") (pinfunction "S_2") (pintype "passive"))
      (node (ref "R298") (pin "1") (pinfunction "1_1") (pintype "passive"))
      (node (ref "R299") (pin "1") (pinfunction "1_1") (pintype "passive"))
      (node (ref "R309") (pin "1") (pinfunction "1_1") (pintype "passive"))
      (node (ref "TP29") (pin "1") (pinfunction "1_1") (pintype "passive"))
      (node (ref "U11") (pin "1") (pinfunction "OUT_1") (pintype "passive"))
      (node (ref "U301") (pin "1") (pinfunction "VDD_1") (pintype "power_in"))
      (node (ref "U303") (pin "5") (pinfunction "V+_5") (pintype "power_in"))
      (node (ref "U304") (pin "5") (pinfunction "V+_5") (pintype "power_in"))
      (node (ref "U305") (pin "C2") (pinfunction "V+_C2") (pintype "power_in"))
      (node (ref "U306") (pin "8") (pinfunction "VCC_8") (pintype "power_in"))
      (node (ref "U307") (pin "8") (pinfunction "VCC_8") (pintype "power_in"))
    )
    (net (code "341") (name "VDD_BLE") (class "Default")
      (node (ref "C91") (pin "2") (pinfunction "2_2") (pintype "passive"))
      (node (ref "C92") (pin "1") (pinfunction "1_1") (pintype "passive"))
      (node (ref "J906") (pin "1") (pinfunction "1_1") (pintype "passive"))
      (node (ref "J907") (pin "3") (pinfunction "3_3") (pintype "passive"))
      (node (ref "J911") (pin "1") (pinfunction "1_1") (pintype "passive"))
      (node (ref "M91") (pin "3") (pinfunction "D_3") (pintype "passive"))
      (node (ref "TP81") (pin "1") (pinfunction "1_1") (pintype "passive"))
      (node (ref "U91") (pin "A6") (pinfunction "VDD_A6") (pintype "passive"))
      (node (ref "U91") (pin "G6") (pinfunction "VDD_G6") (pintype "passive"))
    )
    (net (code "342") (name "VGND1R") (class "Default")
      (node (ref "F1") (pin "1") (pinfunction "1_1") (pintype "passive"))
      (node (ref "J2") (pin "1") (pinfunction "1_1") (pintype "passive"))
      (node (ref "J2") (pin "2") (pinfunction "2_2") (pintype "passive"))
      (node (ref "J2") (pin "3") (pinfunction "3_3") (pintype "passive"))
      (node (ref "J2") (pin "4") (pinfunction "4_4") (pintype "passive"))
      (node (ref "J901") (pin "4") (pinfunction "4_4") (pintype "passive"))
      (node (ref "TP3") (pin "1") (pinfunction "1_1") (pintype "passive"))
    )
    (net (code "343") (name "VGND2R") (class "Default")
      (node (ref "F2") (pin "1") (pinfunction "1_1") (pintype "passive"))
      (node (ref "J4") (pin "1") (pinfunction "1_1") (pintype "passive"))
      (node (ref "J4") (pin "2") (pinfunction "2_2") (pintype "passive"))
      (node (ref "J4") (pin "3") (pinfunction "3_3") (pintype "passive"))
      (node (ref "J4") (pin "4") (pinfunction "4_4") (pintype "passive"))
      (node (ref "J902") (pin "4") (pinfunction "4_4") (pintype "passive"))
      (node (ref "TP6") (pin "1") (pinfunction "1_1") (pintype "passive"))
    )
    (net (code "344") (name "VIMP_3V3") (class "Default")
      (node (ref "C306") (pin "2") (pinfunction "2_2") (pintype "passive"))
      (node (ref "C307") (pin "2") (pinfunction "2_2") (pintype "passive"))
      (node (ref "M318") (pin "3") (pinfunction "D_3") (pintype "passive"))
      (node (ref "R303") (pin "1") (pinfunction "1_1") (pintype "passive"))
      (node (ref "TP307") (pin "1") (pinfunction "1_1") (pintype "passive"))
      (node (ref "U308") (pin "14") (pinfunction "VCC_14") (pintype "power_in"))
      (node (ref "U309") (pin "14") (pinfunction "VCC_14") (pintype "power_in"))
      (node (ref "U310") (pin "C2") (pinfunction "V+_C2") (pintype "power_in"))
      (node (ref "U311") (pin "3") (pinfunction "VS+_3") (pintype "power_in"))
      (node (ref "U311") (pin "7") (pinfunction "~{PD}_7") (pintype "passive"))
    )
    (net (code "345") (name "VPP") (class "Default")
      (node (ref "M32") (pin "3") (pinfunction "D_3") (pintype "passive"))
      (node (ref "R281") (pin "1") (pinfunction "1_1") (pintype "passive"))
      (node (ref "R282") (pin "1") (pinfunction "1_1") (pintype "passive"))
      (node (ref "R283") (pin "1") (pinfunction "1_1") (pintype "passive"))
      (node (ref "R284") (pin "1") (pinfunction "1_1") (pintype "passive"))
      (node (ref "R297") (pin "1") (pinfunction "1_1") (pintype "passive"))
      (node (ref "R311") (pin "1") (pinfunction "1_1") (pintype "passive"))
      (node (ref "R312") (pin "1") (pinfunction "1_1") (pintype "passive"))
      (node (ref "R313") (pin "1") (pinfunction "1_1") (pintype "passive"))
      (node (ref "R314") (pin "1") (pinfunction "1_1") (pintype "passive"))
      (node (ref "R327") (pin "1") (pinfunction "1_1") (pintype "passive"))
      (node (ref "R331") (pin "1") (pinfunction "1_1") (pintype "passive"))
      (node (ref "R332") (pin "1") (pinfunction "1_1") (pintype "passive"))
      (node (ref "R333") (pin "1") (pinfunction "1_1") (pintype "passive"))
      (node (ref "R334") (pin "1") (pinfunction "1_1") (pintype "passive"))
      (node (ref "R347") (pin "1") (pinfunction "1_1") (pintype "passive"))
      (node (ref "TP35") (pin "1") (pinfunction "1_1") (pintype "passive"))
      (node (ref "U30") (pin "13") (pinfunction "VDD_13") (pintype "power_in"))
      (node (ref "U31") (pin "13") (pinfunction "VDD_13") (pintype "power_in"))
    )
    (net (code "346") (name "VRECT") (class "Default")
      (node (ref "C505") (pin "2") (pinfunction "2_2") (pintype "passive"))
      (node (ref "C506") (pin "2") (pinfunction "2_2") (pintype "passive"))
      (node (ref "C510") (pin "2") (pinfunction "2_2") (pintype "passive"))
      (node (ref "C512") (pin "2") (pinfunction "2_2") (pintype "passive"))
      (node (ref "D504") (pin "1") (pinfunction "K_1") (pintype "passive"))
      (node (ref "D505") (pin "1") (pinfunction "K_1") (pintype "passive"))
      (node (ref "J905") (pin "2") (pinfunction "2_2") (pintype "passive"))
      (node (ref "L501") (pin "1") (pinfunction "1_1") (pintype "passive"))
      (node (ref "M503") (pin "3") (pinfunction "D_3") (pintype "passive"))
      (node (ref "M508") (pin "2") (pinfunction "S_2") (pintype "passive"))
      (node (ref "M515") (pin "3") (pinfunction "D_3") (pintype "passive"))
      (node (ref "R502") (pin "1") (pinfunction "1_1") (pintype "passive"))
      (node (ref "R504") (pin "1") (pinfunction "1_1") (pintype "passive"))
      (node (ref "R507") (pin "1") (pinfunction "1_1") (pintype "passive"))
      (node (ref "R509") (pin "1") (pinfunction "1_1") (pintype "passive"))
      (node (ref "R511") (pin "1") (pinfunction "1_1") (pintype "passive"))
      (node (ref "R513") (pin "1") (pinfunction "1_1") (pintype "passive"))
      (node (ref "R517") (pin "1") (pinfunction "1_1") (pintype "passive"))
      (node (ref "TP504") (pin "1") (pinfunction "1_1") (pintype "passive"))
      (node (ref "U503") (pin "2") (pinfunction "PVIN_2") (pintype "power_in"))
      (node (ref "U503") (pin "20") (pinfunction "SW1_20") (pintype "passive"))
      (node (ref "U503") (pin "3") (pinfunction "VIN_3") (pintype "power_in"))
      (node (ref "U503") (pin "4") (pinfunction "RUN_4") (pintype "input"))
    )
    (net (code "347") (name "V_UNREG") (class "Default")
      (node (ref "C11") (pin "2") (pinfunction "2_2") (pintype "passive"))
      (node (ref "C13") (pin "2") (pinfunction "2_2") (pintype "passive"))
      (node (ref "C3") (pin "1") (pinfunction "1_1") (pintype "passive"))
      (node (ref "C4") (pin "2") (pinfunction "2_2") (pintype "passive"))
      (node (ref "D3") (pin "1") (pinfunction "K_1") (pintype "passive"))
      (node (ref "D4") (pin "1") (pinfunction "K_1") (pintype "passive"))
      (node (ref "D5") (pin "1") (pinfunction "K_1") (pintype "passive"))
      (node (ref "R5") (pin "1") (pinfunction "1_1") (pintype "passive"))
      (node (ref "TP10") (pin "1") (pinfunction "1_1") (pintype "passive"))
      (node (ref "U1") (pin "4") (pinfunction "IN_4") (pintype "passive"))
      (node (ref "U10") (pin "4") (pinfunction "IN_4") (pintype "passive"))
      (node (ref "U11") (pin "4") (pinfunction "IN_4") (pintype "passive"))
    )
    (net (code "348") (name "unconnected-(J901-Pad1)") (class "Default")
      (node (ref "J901") (pin "1") (pinfunction "1_1") (pintype "passive+no_connect"))
    )
    (net (code "349") (name "unconnected-(J901-Pad3)") (class "Default")
      (node (ref "J901") (pin "3") (pinfunction "3_3") (pintype "passive+no_connect"))
    )
    (net (code "350") (name "unconnected-(J902-Pad1)") (class "Default")
      (node (ref "J902") (pin "1") (pinfunction "1_1") (pintype "passive+no_connect"))
    )
    (net (code "351") (name "unconnected-(J902-Pad3)") (class "Default")
      (node (ref "J902") (pin "3") (pinfunction "3_3") (pintype "passive+no_connect"))
    )
    (net (code "352") (name "unconnected-(J905-Pad1)") (class "Default")
      (node (ref "J905") (pin "1") (pinfunction "1_1") (pintype "passive+no_connect"))
    )
    (net (code "353") (name "unconnected-(J905-Pad3)") (class "Default")
      (node (ref "J905") (pin "3") (pinfunction "3_3") (pintype "passive+no_connect"))
    )
    (net (code "354") (name "unconnected-(J906-Pad6)") (class "Default")
      (node (ref "J906") (pin "6") (pinfunction "6_6") (pintype "passive+no_connect"))
    )
    (net (code "355") (name "unconnected-(J907-Pad2)") (class "Default")
      (node (ref "J907") (pin "2") (pinfunction "2_2") (pintype "passive+no_connect"))
    )
    (net (code "356") (name "unconnected-(J907-Pad6)") (class "Default")
      (node (ref "J907") (pin "6") (pinfunction "6_6") (pintype "passive+no_connect"))
    )
    (net (code "357") (name "unconnected-(J910-Pad7)") (class "Default")
      (node (ref "J910") (pin "7") (pinfunction "7_7") (pintype "passive+no_connect"))
    )
    (net (code "358") (name "unconnected-(J910-Pad8)") (class "Default")
      (node (ref "J910") (pin "8") (pinfunction "8_8") (pintype "passive+no_connect"))
    )
    (net (code "359") (name "unconnected-(J911-Pad6)") (class "Default")
      (node (ref "J911") (pin "6") (pinfunction "6_6") (pintype "passive+no_connect"))
    )
    (net (code "360") (name "unconnected-(J911-Pad7)") (class "Default")
      (node (ref "J911") (pin "7") (pinfunction "7_7") (pintype "passive+no_connect"))
    )
    (net (code "361") (name "unconnected-(J911-Pad8)") (class "Default")
      (node (ref "J911") (pin "8") (pinfunction "8_8") (pintype "passive+no_connect"))
    )
    (net (code "362") (name "unconnected-(U6-NC-PadB2)") (class "Default")
      (node (ref "U6") (pin "B2") (pinfunction "NC_B2") (pintype "power_in+no_connect"))
    )
    (net (code "363") (name "unconnected-(U7-NC-PadB2)") (class "Default")
      (node (ref "U7") (pin "B2") (pinfunction "NC_B2") (pintype "power_in+no_connect"))
    )
    (net (code "364") (name "unconnected-(U8-NC-Pad1)") (class "Default")
      (node (ref "U8") (pin "1") (pinfunction "NC_1") (pintype "passive+no_connect"))
    )
    (net (code "365") (name "unconnected-(U9-DNU-Pad7)") (class "Default")
      (node (ref "U9") (pin "7") (pinfunction "DNU_7") (pintype "passive+no_connect"))
    )
    (net (code "366") (name "unconnected-(U13-RL-Pad5)") (class "Default")
      (node (ref "U13") (pin "5") (pinfunction "RL_5") (pintype "passive+no_connect"))
    )
    (net (code "367") (name "unconnected-(U14-NC-PadB2)") (class "Default")
      (node (ref "U14") (pin "B2") (pinfunction "NC_B2") (pintype "power_in+no_connect"))
    )
    (net (code "368") (name "unconnected-(U15-NC-PadB2)") (class "Default")
      (node (ref "U15") (pin "B2") (pinfunction "NC_B2") (pintype "power_in+no_connect"))
    )
    (net (code "369") (name "unconnected-(U16-NC-PadB2)") (class "Default")
      (node (ref "U16") (pin "B2") (pinfunction "NC_B2") (pintype "power_in+no_connect"))
    )
    (net (code "370") (name "unconnected-(U17-OPAMP1_VINM-PadH3)") (class "Default")
      (node (ref "U17") (pin "H3") (pinfunction "OPAMP1_VINM_H3") (pintype "passive+no_connect"))
    )
    (net (code "371") (name "unconnected-(U17-OPAMP2_VINM-PadM2)") (class "Default")
      (node (ref "U17") (pin "M2") (pinfunction "OPAMP2_VINM_M2") (pintype "passive+no_connect"))
    )
    (net (code "372") (name "unconnected-(U91-DCC-PadA5)") (class "Default")
      (node (ref "U91") (pin "A5") (pinfunction "DCC_A5") (pintype "passive+no_connect"))
    )
    (net (code "373") (name "unconnected-(U303-NC-Pad3)") (class "Default")
      (node (ref "U303") (pin "3") (pinfunction "NC_3") (pintype "passive+no_connect"))
    )
    (net (code "374") (name "unconnected-(U304-NC-Pad3)") (class "Default")
      (node (ref "U304") (pin "3") (pinfunction "NC_3") (pintype "passive+no_connect"))
    )
    (net (code "375") (name "unconnected-(U305-OUT2-PadC3)") (class "Default")
      (node (ref "U305") (pin "C3") (pinfunction "OUT2_C3") (pintype "passive+no_connect"))
    )
    (net (code "376") (name "unconnected-(U308-NC-Pad5)") (class "Default")
      (node (ref "U308") (pin "5") (pinfunction "NC_5") (pintype "passive+no_connect"))
    )
    (net (code "377") (name "unconnected-(U309-NC-Pad5)") (class "Default")
      (node (ref "U309") (pin "5") (pinfunction "NC_5") (pintype "passive+no_connect"))
    )
    (net (code "378") (name "unconnected-(U501-NC-PadB2)") (class "Default")
      (node (ref "U501") (pin "B2") (pinfunction "NC_B2") (pintype "power_in+no_connect"))
    )
    (net (code "379") (name "unconnected-(U503-NC-Pad17)") (class "Default")
      (node (ref "U503") (pin "17") (pinfunction "NC_17") (pintype "passive+no_connect"))
    )
  )
)
